# GridSeed.net
KiCad netlist of a schematic drawn in Altium Designer
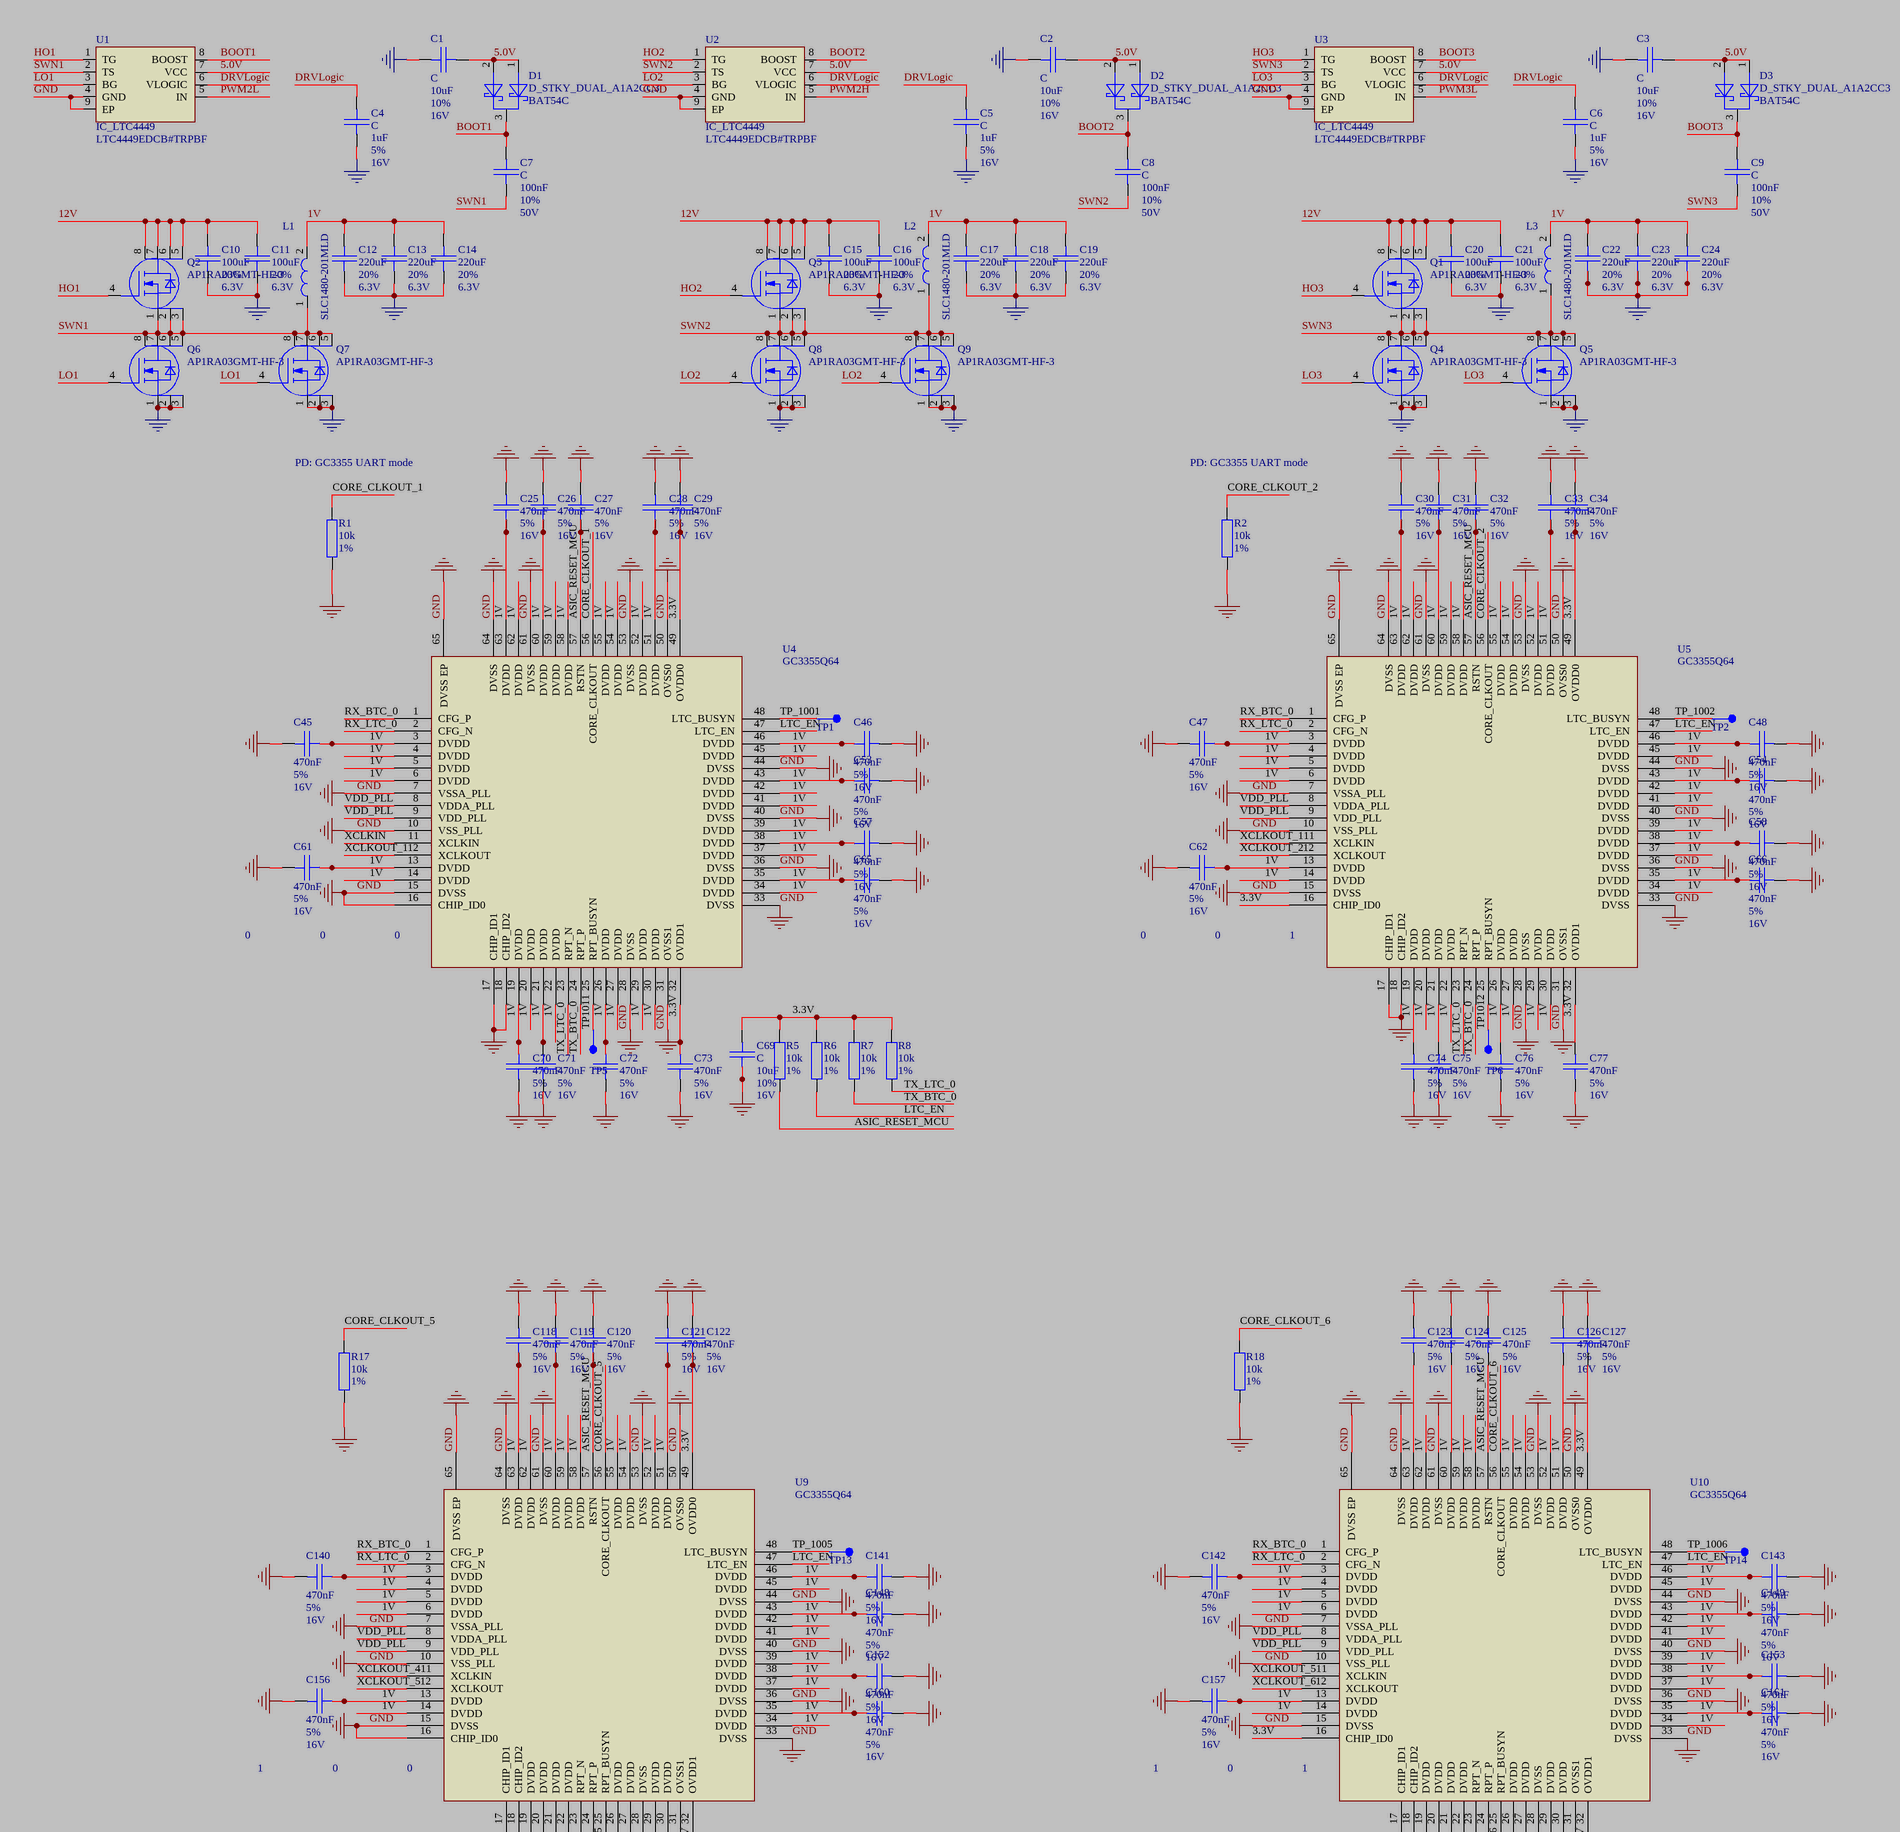
[diagram p0: GridSeed.SchDoc, top left]
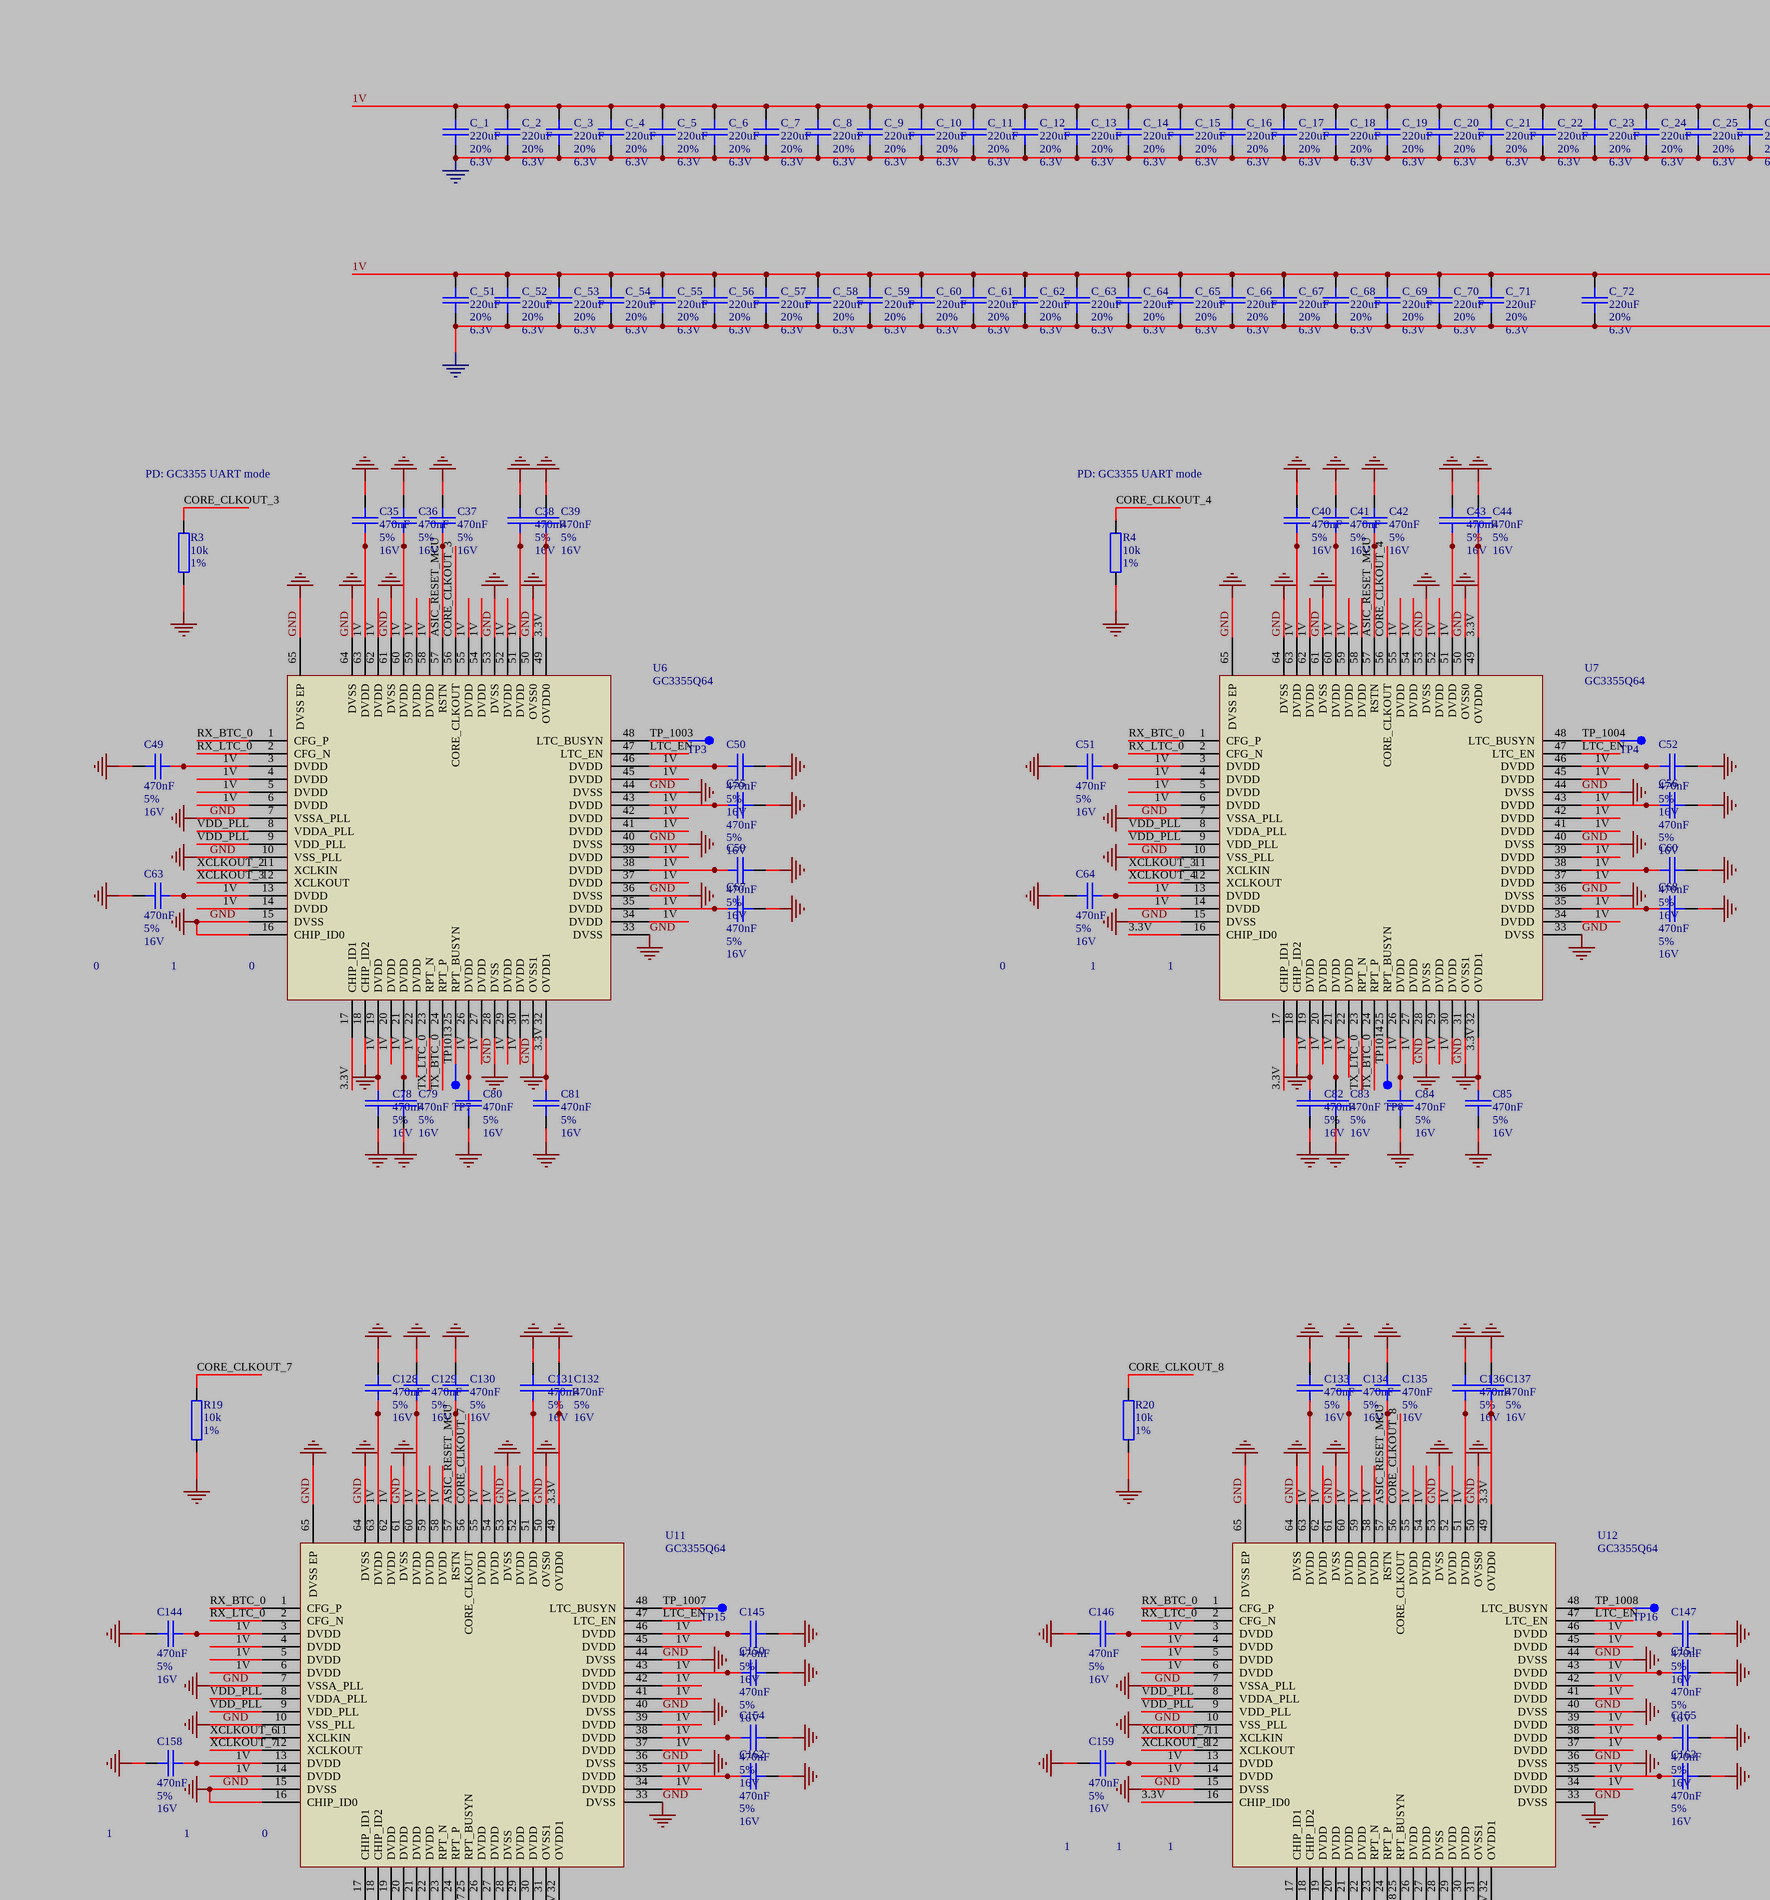
[diagram p1: GridSeed.SchDoc, top middle]
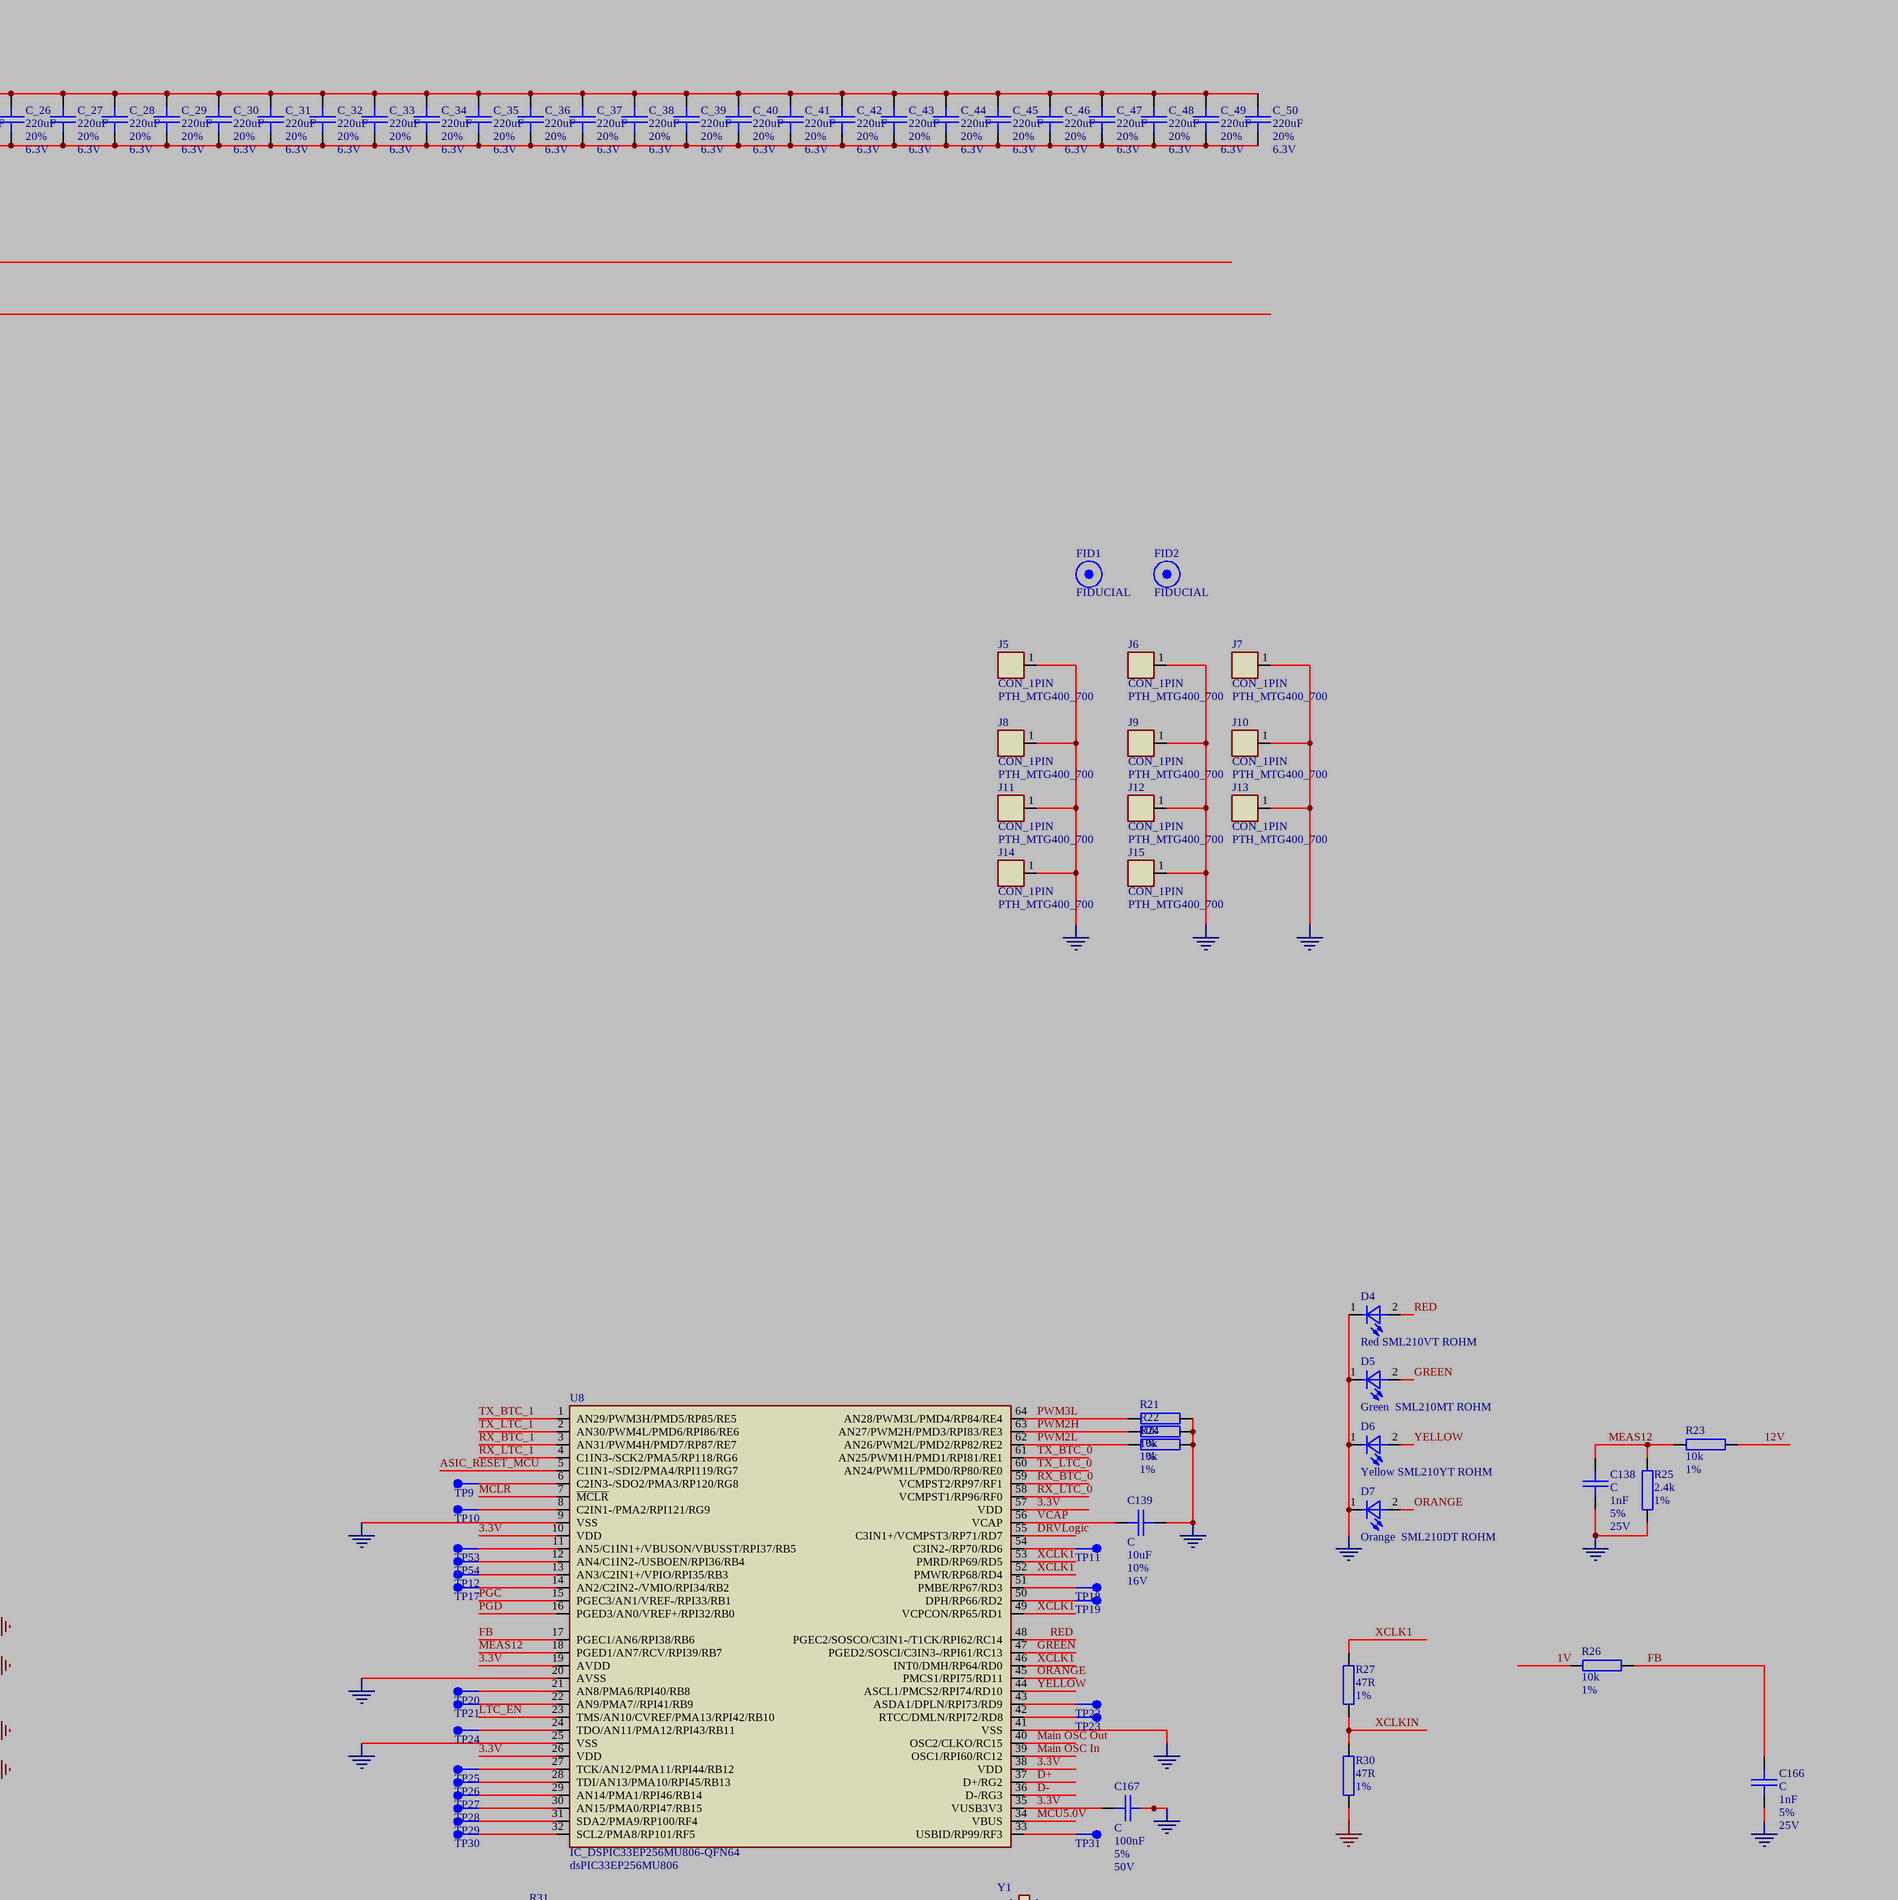
[diagram p2: GridSeed.SchDoc, top right]
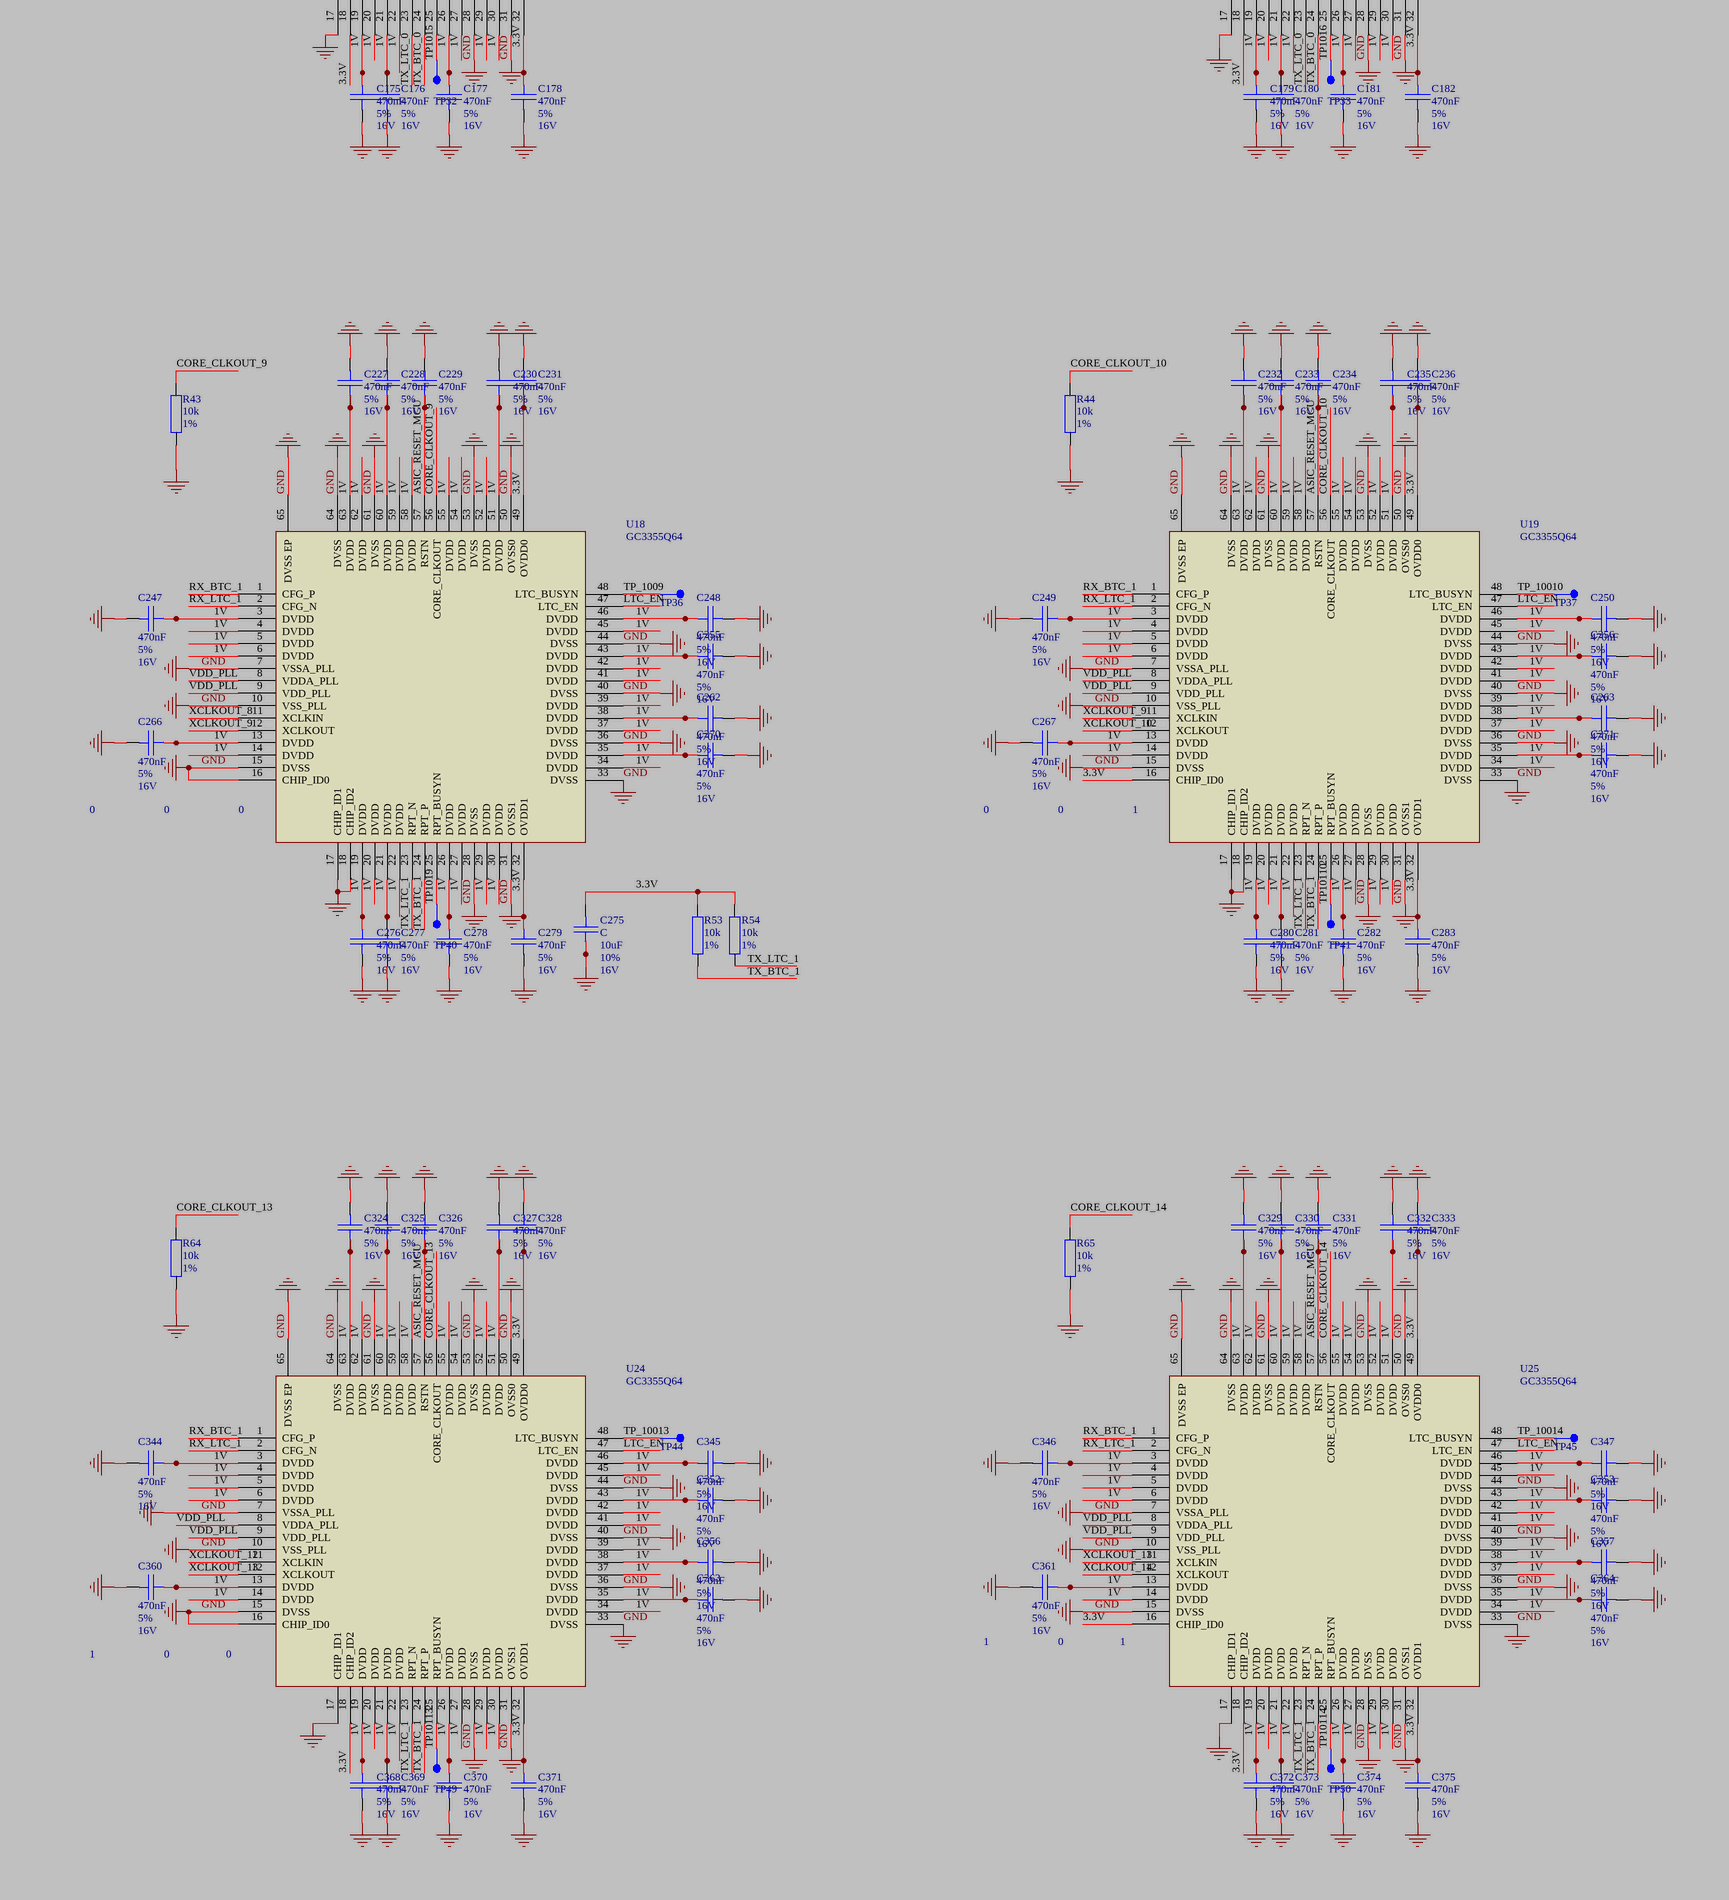
[diagram p3: GridSeed.SchDoc, bottom left]
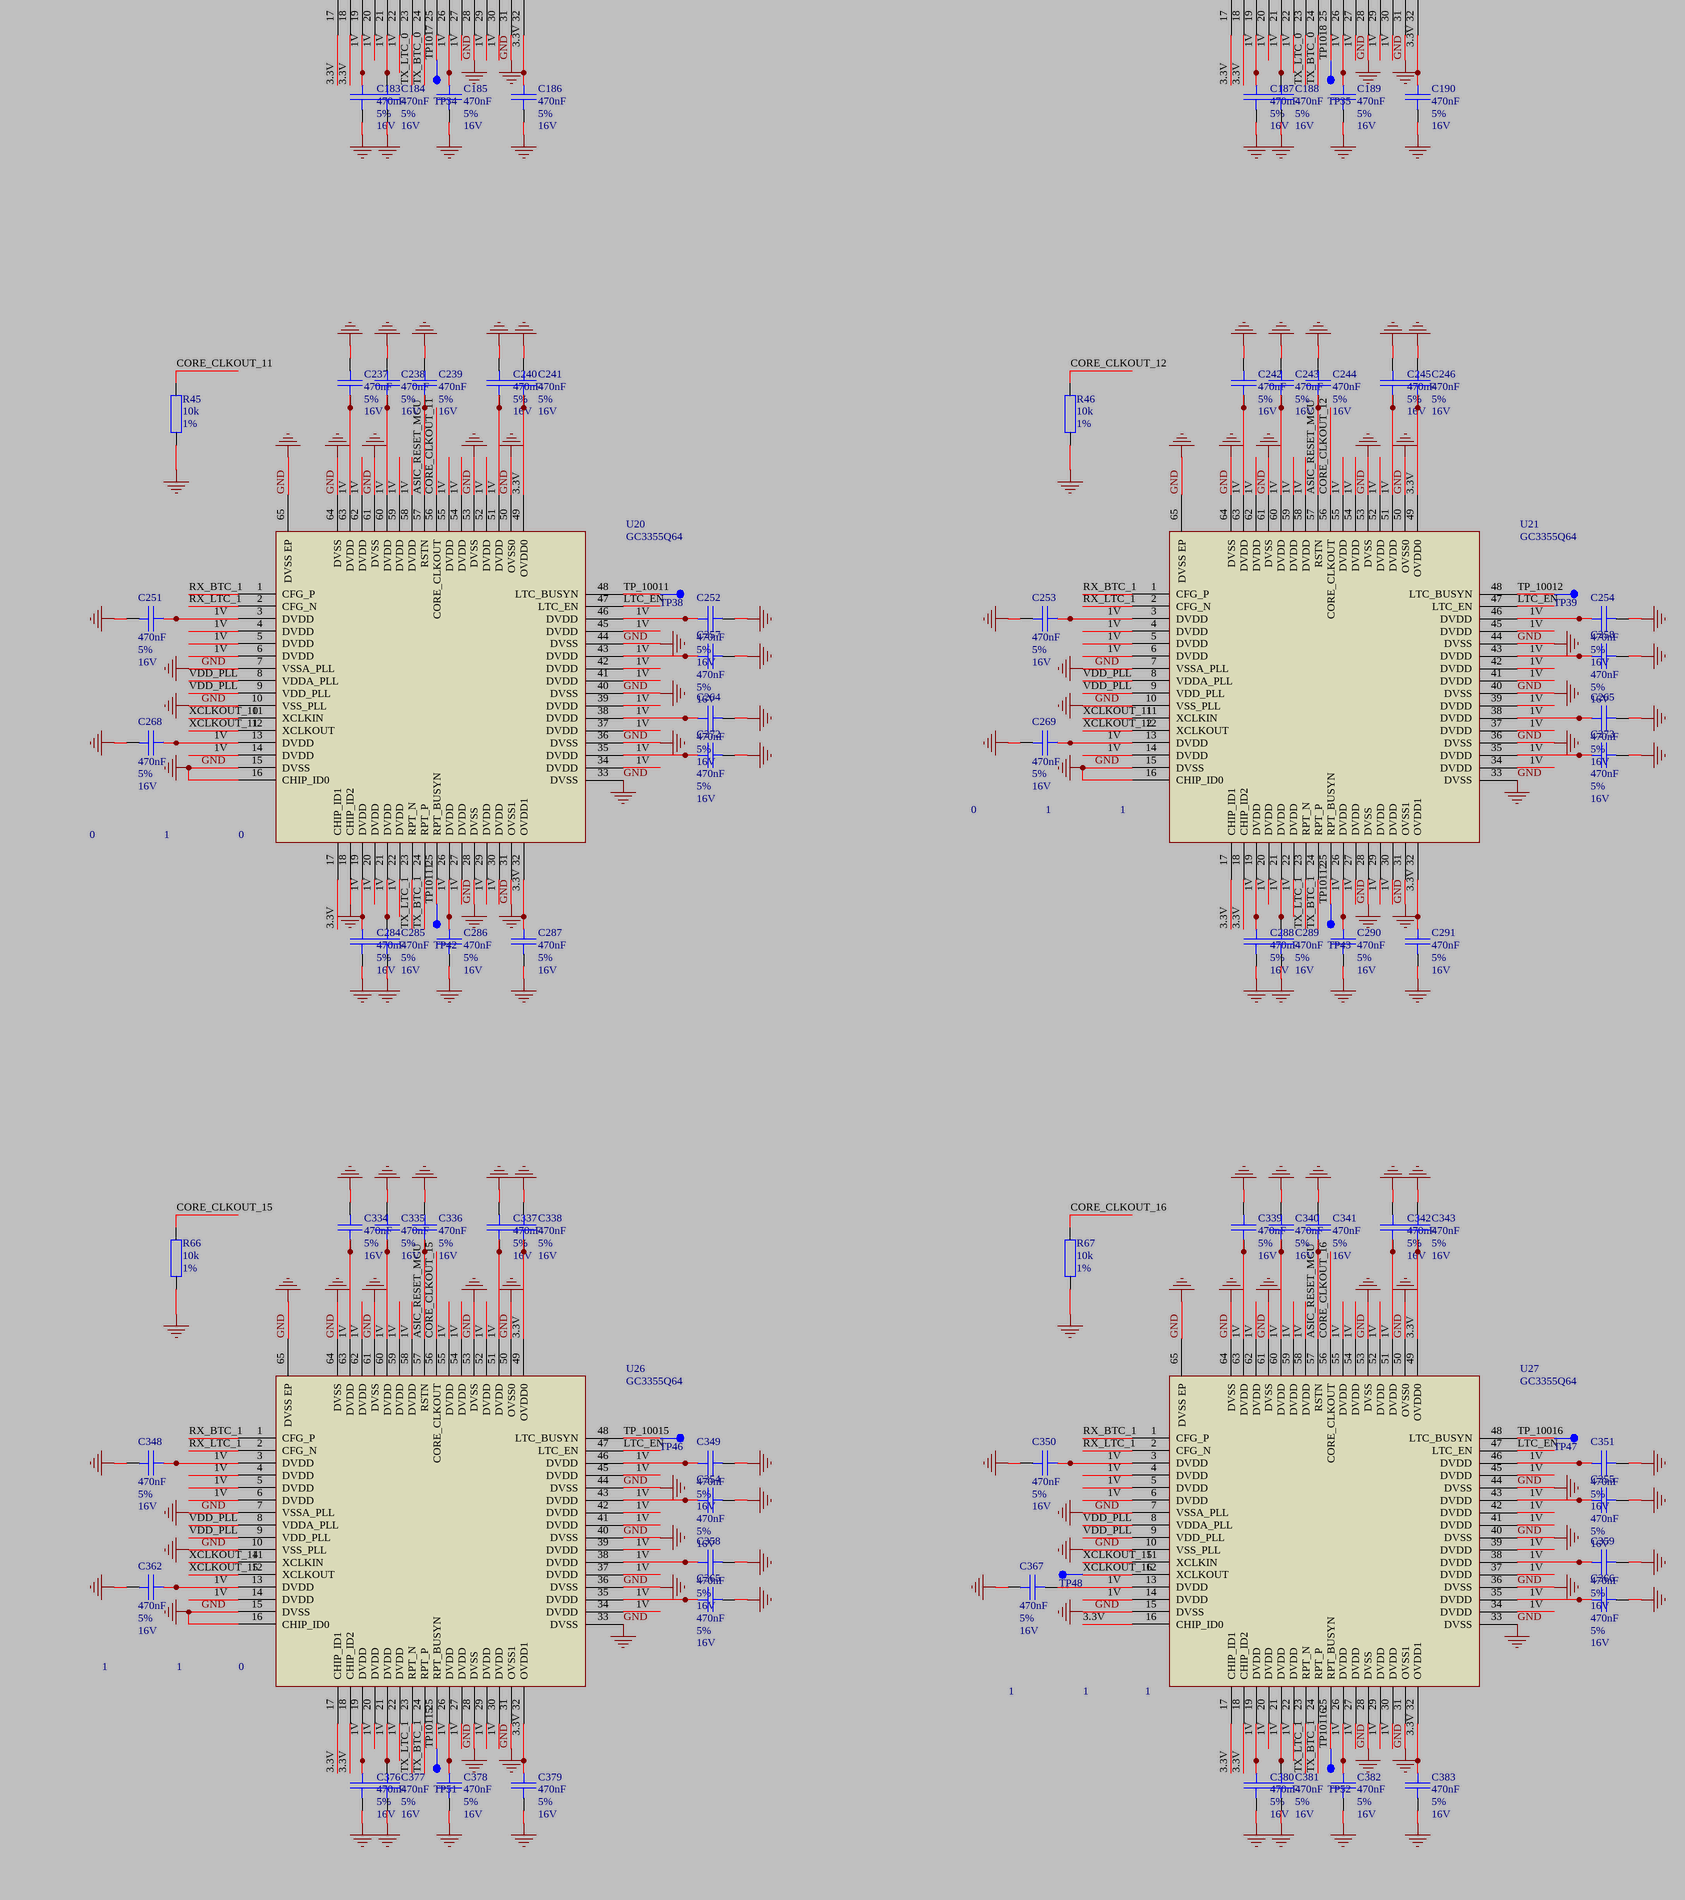
[diagram p4: GridSeed.SchDoc, bottom middle]
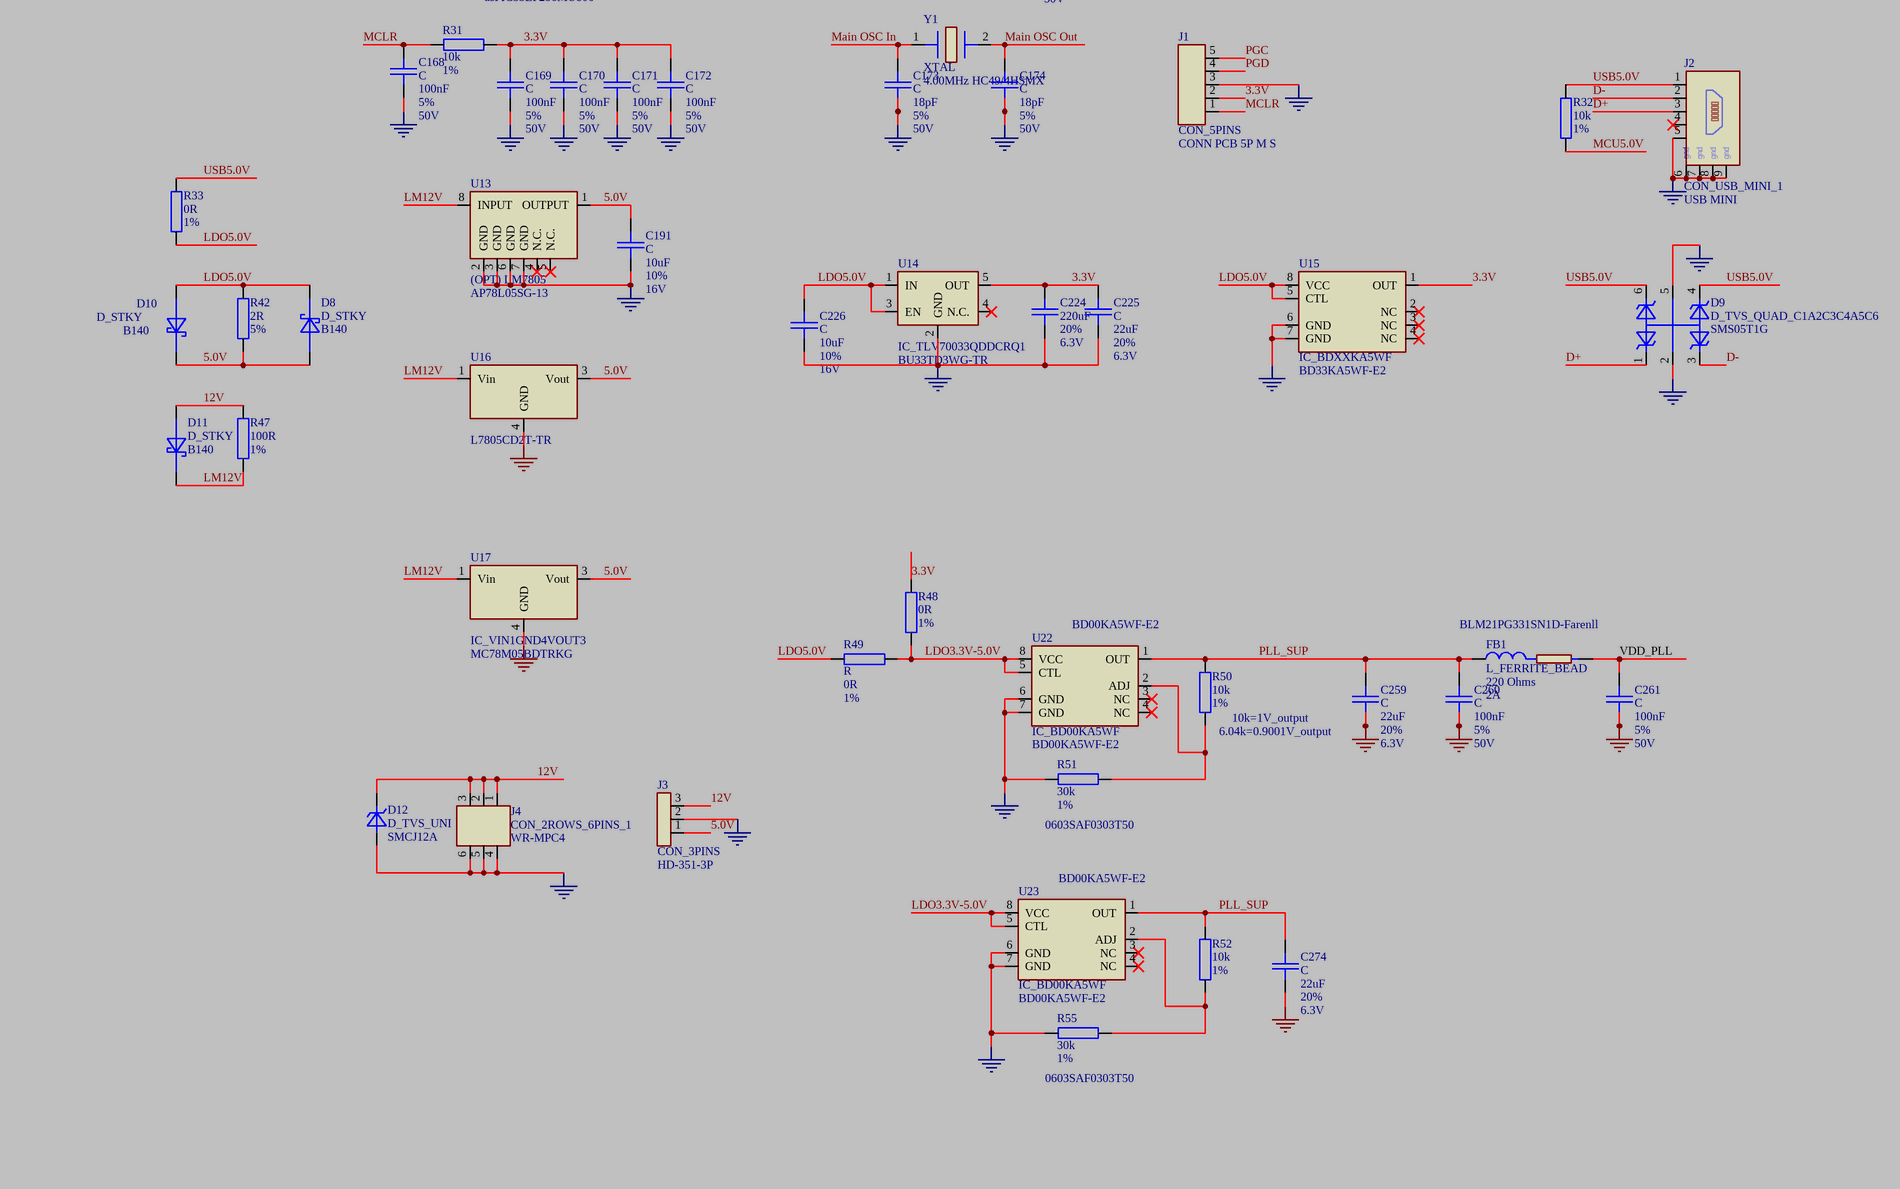
[diagram p5: GridSeed.SchDoc, bottom right]

(export (version "E")
  (design (tool "Eeschema 10.0.6"))
  (components
    (comp (ref "C1")
      (value "C")
      (footprint "SMD_0805_CAPC2012X145N")
      (fields
        (field (name "DB_PART_NUMBER") "CAP000043636")
        (field (name "DB_VALUE") "10uF")
        (field (name "DB_TOLERANCE") "10%")
        (field (name "DB_VOLTAGE") "16V")
        (field (name "DB_MANUFACTURER_PART") "KEMET    C0805C106K4PAC")
        (field (name "DB_APPROVED_BY") "ISHIDDEN=T")
      )
      (libsource (lib "Database_Libs1") (part "C"))
    )
    (comp (ref "C2")
      (value "C")
      (footprint "SMD_0805_CAPC2012X145N")
      (fields
        (field (name "DB_PART_NUMBER") "CAP000043636")
        (field (name "DB_VALUE") "10uF")
        (field (name "DB_TOLERANCE") "10%")
        (field (name "DB_VOLTAGE") "16V")
        (field (name "DB_MANUFACTURER_PART") "KEMET    C0805C106K4PAC")
        (field (name "DB_APPROVED_BY") "ISHIDDEN=T")
      )
      (libsource (lib "Database_Libs1") (part "C"))
    )
    (comp (ref "C3")
      (value "C")
      (footprint "SMD_0805_CAPC2012X145N")
      (fields
        (field (name "DB_PART_NUMBER") "CAP000043636")
        (field (name "DB_VALUE") "10uF")
        (field (name "DB_TOLERANCE") "10%")
        (field (name "DB_VOLTAGE") "16V")
        (field (name "DB_MANUFACTURER_PART") "KEMET    C0805C106K4PAC")
        (field (name "DB_APPROVED_BY") "ISHIDDEN=T")
      )
      (libsource (lib "Database_Libs1") (part "C"))
    )
    (comp (ref "C4")
      (value "C")
      (footprint "SMD_0805_CAPC2012X145N")
      (fields
        (field (name "DB_PART_NUMBER") "CAP000028589")
        (field (name "DB_VALUE") "1uF")
        (field (name "DB_TOLERANCE") "5%")
        (field (name "DB_VOLTAGE") "16V")
        (field (name "DB_MANUFACTURER_PART") "KEMET    C0805C105J4RAC")
        (field (name "DB_APPROVED_BY") "ISHIDDEN=T")
      )
      (libsource (lib "Database_Libs1") (part "C"))
    )
    (comp (ref "C5")
      (value "C")
      (footprint "SMD_0805_CAPC2012X145N")
      (fields
        (field (name "DB_PART_NUMBER") "CAP000028589")
        (field (name "DB_VALUE") "1uF")
        (field (name "DB_TOLERANCE") "5%")
        (field (name "DB_VOLTAGE") "16V")
        (field (name "DB_MANUFACTURER_PART") "KEMET    C0805C105J4RAC")
        (field (name "DB_APPROVED_BY") "ISHIDDEN=T")
      )
      (libsource (lib "Database_Libs1") (part "C"))
    )
    (comp (ref "C6")
      (value "C")
      (footprint "SMD_0805_CAPC2012X145N")
      (fields
        (field (name "DB_PART_NUMBER") "CAP000028589")
        (field (name "DB_VALUE") "1uF")
        (field (name "DB_TOLERANCE") "5%")
        (field (name "DB_VOLTAGE") "16V")
        (field (name "DB_MANUFACTURER_PART") "KEMET    C0805C105J4RAC")
        (field (name "DB_APPROVED_BY") "ISHIDDEN=T")
      )
      (libsource (lib "Database_Libs1") (part "C"))
    )
    (comp (ref "C7")
      (value "C")
      (footprint "SMD_0805_CAPC2012X145N")
      (fields
        (field (name "DB_PART_NUMBER") "CAP000027193")
        (field (name "DB_VALUE") "100nF")
        (field (name "DB_TOLERANCE") "10%")
        (field (name "DB_VOLTAGE") "50V")
        (field (name "DB_MANUFACTURER_PART") "KEMET    C0805C104K5RAC")
        (field (name "DB_APPROVED_BY") "ISHIDDEN=T")
      )
      (libsource (lib "Database_Libs1") (part "C"))
    )
    (comp (ref "C8")
      (value "C")
      (footprint "SMD_0805_CAPC2012X145N")
      (fields
        (field (name "DB_PART_NUMBER") "CAP000027193")
        (field (name "DB_VALUE") "100nF")
        (field (name "DB_TOLERANCE") "10%")
        (field (name "DB_VOLTAGE") "50V")
        (field (name "DB_MANUFACTURER_PART") "KEMET    C0805C104K5RAC")
        (field (name "DB_APPROVED_BY") "ISHIDDEN=T")
      )
      (libsource (lib "Database_Libs1") (part "C"))
    )
    (comp (ref "C9")
      (value "C")
      (footprint "SMD_0805_CAPC2012X145N")
      (fields
        (field (name "DB_PART_NUMBER") "CAP000027193")
        (field (name "DB_VALUE") "100nF")
        (field (name "DB_TOLERANCE") "10%")
        (field (name "DB_VOLTAGE") "50V")
        (field (name "DB_MANUFACTURER_PART") "KEMET    C0805C104K5RAC")
        (field (name "DB_APPROVED_BY") "ISHIDDEN=T")
      )
      (libsource (lib "Database_Libs1") (part "C"))
    )
    (comp (ref "C10")
      (value "C")
      (footprint "SMD_1210_CAPC3225X270N")
      (fields
        (field (name "DB_PART_NUMBER") "CAP000043701")
        (field (name "DB_VALUE") "100uF")
        (field (name "DB_TOLERANCE") "20%")
        (field (name "DB_VOLTAGE") "6.3V")
        (field (name "DB_MANUFACTURER_PART") "KEMET    C1210C107M9PAC")
        (field (name "DB_APPROVED_BY") "ISHIDDEN=T")
      )
      (libsource (lib "Database_Libs1") (part "C"))
    )
    (comp (ref "C11")
      (value "C")
      (footprint "SMD_1210_CAPC3225X270N")
      (fields
        (field (name "DB_PART_NUMBER") "CAP000043701")
        (field (name "DB_VALUE") "100uF")
        (field (name "DB_TOLERANCE") "20%")
        (field (name "DB_VOLTAGE") "6.3V")
        (field (name "DB_MANUFACTURER_PART") "KEMET    C1210C107M9PAC")
        (field (name "DB_APPROVED_BY") "ISHIDDEN=T")
      )
      (libsource (lib "Database_Libs1") (part "C"))
    )
    (comp (ref "C12")
      (value "C")
      (footprint "SMD_1210_CAPC3225X279N")
      (fields
        (field (name "DB_PART_NUMBER") "CAP000047355")
        (field (name "DB_VALUE") "220uF")
        (field (name "DB_TOLERANCE") "20%")
        (field (name "DB_VOLTAGE") "6.3V")
        (field (name "DB_MANUFACTURER_PART") "SAMSUNG    CL32A227MQVNNNE")
        (field (name "DB_APPROVED_BY") "VSN")
      )
      (libsource (lib "Database_Libs1") (part "C"))
    )
    (comp (ref "C13")
      (value "C")
      (footprint "SMD_1210_CAPC3225X279N")
      (fields
        (field (name "DB_PART_NUMBER") "CAP000047355")
        (field (name "DB_VALUE") "220uF")
        (field (name "DB_TOLERANCE") "20%")
        (field (name "DB_VOLTAGE") "6.3V")
        (field (name "DB_MANUFACTURER_PART") "SAMSUNG    CL32A227MQVNNNE")
        (field (name "DB_APPROVED_BY") "VSN")
      )
      (libsource (lib "Database_Libs1") (part "C"))
    )
    (comp (ref "C14")
      (value "C")
      (footprint "SMD_1210_CAPC3225X279N")
      (fields
        (field (name "DB_PART_NUMBER") "CAP000047355")
        (field (name "DB_VALUE") "220uF")
        (field (name "DB_TOLERANCE") "20%")
        (field (name "DB_VOLTAGE") "6.3V")
        (field (name "DB_MANUFACTURER_PART") "SAMSUNG    CL32A227MQVNNNE")
        (field (name "DB_APPROVED_BY") "VSN")
      )
      (libsource (lib "Database_Libs1") (part "C"))
    )
    (comp (ref "C15")
      (value "C")
      (footprint "SMD_1210_CAPC3225X270N")
      (fields
        (field (name "DB_PART_NUMBER") "CAP000043701")
        (field (name "DB_VALUE") "100uF")
        (field (name "DB_TOLERANCE") "20%")
        (field (name "DB_VOLTAGE") "6.3V")
        (field (name "DB_MANUFACTURER_PART") "KEMET    C1210C107M9PAC")
        (field (name "DB_APPROVED_BY") "ISHIDDEN=T")
      )
      (libsource (lib "Database_Libs1") (part "C"))
    )
    (comp (ref "C16")
      (value "C")
      (footprint "SMD_1210_CAPC3225X270N")
      (fields
        (field (name "DB_PART_NUMBER") "CAP000043701")
        (field (name "DB_VALUE") "100uF")
        (field (name "DB_TOLERANCE") "20%")
        (field (name "DB_VOLTAGE") "6.3V")
        (field (name "DB_MANUFACTURER_PART") "KEMET    C1210C107M9PAC")
        (field (name "DB_APPROVED_BY") "ISHIDDEN=T")
      )
      (libsource (lib "Database_Libs1") (part "C"))
    )
    (comp (ref "C17")
      (value "C")
      (footprint "SMD_1210_CAPC3225X279N")
      (fields
        (field (name "DB_PART_NUMBER") "CAP000047355")
        (field (name "DB_VALUE") "220uF")
        (field (name "DB_TOLERANCE") "20%")
        (field (name "DB_VOLTAGE") "6.3V")
        (field (name "DB_MANUFACTURER_PART") "SAMSUNG    CL32A227MQVNNNE")
        (field (name "DB_APPROVED_BY") "VSN")
      )
      (libsource (lib "Database_Libs1") (part "C"))
    )
    (comp (ref "C18")
      (value "C")
      (footprint "SMD_1210_CAPC3225X279N")
      (fields
        (field (name "DB_PART_NUMBER") "CAP000047355")
        (field (name "DB_VALUE") "220uF")
        (field (name "DB_TOLERANCE") "20%")
        (field (name "DB_VOLTAGE") "6.3V")
        (field (name "DB_MANUFACTURER_PART") "SAMSUNG    CL32A227MQVNNNE")
        (field (name "DB_APPROVED_BY") "VSN")
      )
      (libsource (lib "Database_Libs1") (part "C"))
    )
    (comp (ref "C19")
      (value "C")
      (footprint "SMD_1210_CAPC3225X279N")
      (fields
        (field (name "DB_PART_NUMBER") "CAP000047355")
        (field (name "DB_VALUE") "220uF")
        (field (name "DB_TOLERANCE") "20%")
        (field (name "DB_VOLTAGE") "6.3V")
        (field (name "DB_MANUFACTURER_PART") "SAMSUNG    CL32A227MQVNNNE")
        (field (name "DB_APPROVED_BY") "VSN")
      )
      (libsource (lib "Database_Libs1") (part "C"))
    )
    (comp (ref "C20")
      (value "C")
      (footprint "SMD_1210_CAPC3225X270N")
      (fields
        (field (name "DB_PART_NUMBER") "CAP000043701")
        (field (name "DB_VALUE") "100uF")
        (field (name "DB_TOLERANCE") "20%")
        (field (name "DB_VOLTAGE") "6.3V")
        (field (name "DB_MANUFACTURER_PART") "KEMET    C1210C107M9PAC")
        (field (name "DB_APPROVED_BY") "ISHIDDEN=T")
      )
      (libsource (lib "Database_Libs1") (part "C"))
    )
    (comp (ref "C21")
      (value "C")
      (footprint "SMD_1210_CAPC3225X270N")
      (fields
        (field (name "DB_PART_NUMBER") "CAP000043701")
        (field (name "DB_VALUE") "100uF")
        (field (name "DB_TOLERANCE") "20%")
        (field (name "DB_VOLTAGE") "6.3V")
        (field (name "DB_MANUFACTURER_PART") "KEMET    C1210C107M9PAC")
        (field (name "DB_APPROVED_BY") "ISHIDDEN=T")
      )
      (libsource (lib "Database_Libs1") (part "C"))
    )
    (comp (ref "C22")
      (value "C")
      (footprint "SMD_1210_CAPC3225X279N")
      (fields
        (field (name "DB_PART_NUMBER") "CAP000047355")
        (field (name "DB_VALUE") "220uF")
        (field (name "DB_TOLERANCE") "20%")
        (field (name "DB_VOLTAGE") "6.3V")
        (field (name "DB_MANUFACTURER_PART") "SAMSUNG    CL32A227MQVNNNE")
        (field (name "DB_APPROVED_BY") "VSN")
      )
      (libsource (lib "Database_Libs1") (part "C"))
    )
    (comp (ref "C23")
      (value "C")
      (footprint "SMD_1210_CAPC3225X279N")
      (fields
        (field (name "DB_PART_NUMBER") "CAP000047355")
        (field (name "DB_VALUE") "220uF")
        (field (name "DB_TOLERANCE") "20%")
        (field (name "DB_VOLTAGE") "6.3V")
        (field (name "DB_MANUFACTURER_PART") "SAMSUNG    CL32A227MQVNNNE")
        (field (name "DB_APPROVED_BY") "VSN")
      )
      (libsource (lib "Database_Libs1") (part "C"))
    )
    (comp (ref "C24")
      (value "C")
      (footprint "SMD_1210_CAPC3225X279N")
      (fields
        (field (name "DB_PART_NUMBER") "CAP000047355")
        (field (name "DB_VALUE") "220uF")
        (field (name "DB_TOLERANCE") "20%")
        (field (name "DB_VOLTAGE") "6.3V")
        (field (name "DB_MANUFACTURER_PART") "SAMSUNG    CL32A227MQVNNNE")
        (field (name "DB_APPROVED_BY") "VSN")
      )
      (libsource (lib "Database_Libs1") (part "C"))
    )
    (comp (ref "C25")
      (value "C")
      (footprint "SMD_0603_CAPC1608X95N")
      (fields
        (field (name "DB_PART_NUMBER") "CAP000028169")
        (field (name "DB_VALUE") "470nF")
        (field (name "DB_TOLERANCE") "5%")
        (field (name "DB_VOLTAGE") "16V")
        (field (name "DB_MANUFACTURER_PART") "KEMET    C0603C474J4RAC")
        (field (name "DB_APPROVED_BY") "ISHIDDEN=T")
      )
      (libsource (lib "Database_Libs1") (part "C"))
    )
    (comp (ref "C26")
      (value "C")
      (footprint "SMD_0603_CAPC1608X95N")
      (fields
        (field (name "DB_PART_NUMBER") "CAP000028169")
        (field (name "DB_VALUE") "470nF")
        (field (name "DB_TOLERANCE") "5%")
        (field (name "DB_VOLTAGE") "16V")
        (field (name "DB_MANUFACTURER_PART") "KEMET    C0603C474J4RAC")
        (field (name "DB_APPROVED_BY") "ISHIDDEN=T")
      )
      (libsource (lib "Database_Libs1") (part "C"))
    )
    (comp (ref "C27")
      (value "C")
      (footprint "SMD_0603_CAPC1608X95N")
      (fields
        (field (name "DB_PART_NUMBER") "CAP000028169")
        (field (name "DB_VALUE") "470nF")
        (field (name "DB_TOLERANCE") "5%")
        (field (name "DB_VOLTAGE") "16V")
        (field (name "DB_MANUFACTURER_PART") "KEMET    C0603C474J4RAC")
        (field (name "DB_APPROVED_BY") "ISHIDDEN=T")
      )
      (libsource (lib "Database_Libs1") (part "C"))
    )
    (comp (ref "C28")
      (value "C")
      (footprint "SMD_0603_CAPC1608X95N")
      (fields
        (field (name "DB_PART_NUMBER") "CAP000028169")
        (field (name "DB_VALUE") "470nF")
        (field (name "DB_TOLERANCE") "5%")
        (field (name "DB_VOLTAGE") "16V")
        (field (name "DB_MANUFACTURER_PART") "KEMET    C0603C474J4RAC")
        (field (name "DB_APPROVED_BY") "ISHIDDEN=T")
      )
      (libsource (lib "Database_Libs1") (part "C"))
    )
    (comp (ref "C29")
      (value "C")
      (footprint "SMD_0603_CAPC1608X95N")
      (fields
        (field (name "DB_PART_NUMBER") "CAP000028169")
        (field (name "DB_VALUE") "470nF")
        (field (name "DB_TOLERANCE") "5%")
        (field (name "DB_VOLTAGE") "16V")
        (field (name "DB_MANUFACTURER_PART") "KEMET    C0603C474J4RAC")
        (field (name "DB_APPROVED_BY") "ISHIDDEN=T")
      )
      (libsource (lib "Database_Libs1") (part "C"))
    )
    (comp (ref "C30")
      (value "C")
      (footprint "SMD_0603_CAPC1608X95N")
      (fields
        (field (name "DB_PART_NUMBER") "CAP000028169")
        (field (name "DB_VALUE") "470nF")
        (field (name "DB_TOLERANCE") "5%")
        (field (name "DB_VOLTAGE") "16V")
        (field (name "DB_MANUFACTURER_PART") "KEMET    C0603C474J4RAC")
        (field (name "DB_APPROVED_BY") "ISHIDDEN=T")
      )
      (libsource (lib "Database_Libs1") (part "C"))
    )
    (comp (ref "C31")
      (value "C")
      (footprint "SMD_0603_CAPC1608X95N")
      (fields
        (field (name "DB_PART_NUMBER") "CAP000028169")
        (field (name "DB_VALUE") "470nF")
        (field (name "DB_TOLERANCE") "5%")
        (field (name "DB_VOLTAGE") "16V")
        (field (name "DB_MANUFACTURER_PART") "KEMET    C0603C474J4RAC")
        (field (name "DB_APPROVED_BY") "ISHIDDEN=T")
      )
      (libsource (lib "Database_Libs1") (part "C"))
    )
    (comp (ref "C32")
      (value "C")
      (footprint "SMD_0603_CAPC1608X95N")
      (fields
        (field (name "DB_PART_NUMBER") "CAP000028169")
        (field (name "DB_VALUE") "470nF")
        (field (name "DB_TOLERANCE") "5%")
        (field (name "DB_VOLTAGE") "16V")
        (field (name "DB_MANUFACTURER_PART") "KEMET    C0603C474J4RAC")
        (field (name "DB_APPROVED_BY") "ISHIDDEN=T")
      )
      (libsource (lib "Database_Libs1") (part "C"))
    )
    (comp (ref "C33")
      (value "C")
      (footprint "SMD_0603_CAPC1608X95N")
      (fields
        (field (name "DB_PART_NUMBER") "CAP000028169")
        (field (name "DB_VALUE") "470nF")
        (field (name "DB_TOLERANCE") "5%")
        (field (name "DB_VOLTAGE") "16V")
        (field (name "DB_MANUFACTURER_PART") "KEMET    C0603C474J4RAC")
        (field (name "DB_APPROVED_BY") "ISHIDDEN=T")
      )
      (libsource (lib "Database_Libs1") (part "C"))
    )
    (comp (ref "C34")
      (value "C")
      (footprint "SMD_0603_CAPC1608X95N")
      (fields
        (field (name "DB_PART_NUMBER") "CAP000028169")
        (field (name "DB_VALUE") "470nF")
        (field (name "DB_TOLERANCE") "5%")
        (field (name "DB_VOLTAGE") "16V")
        (field (name "DB_MANUFACTURER_PART") "KEMET    C0603C474J4RAC")
        (field (name "DB_APPROVED_BY") "ISHIDDEN=T")
      )
      (libsource (lib "Database_Libs1") (part "C"))
    )
    (comp (ref "C35")
      (value "C")
      (footprint "SMD_0603_CAPC1608X95N")
      (fields
        (field (name "DB_PART_NUMBER") "CAP000028169")
        (field (name "DB_VALUE") "470nF")
        (field (name "DB_TOLERANCE") "5%")
        (field (name "DB_VOLTAGE") "16V")
        (field (name "DB_MANUFACTURER_PART") "KEMET    C0603C474J4RAC")
        (field (name "DB_APPROVED_BY") "ISHIDDEN=T")
      )
      (libsource (lib "Database_Libs1") (part "C"))
    )
    (comp (ref "C36")
      (value "C")
      (footprint "SMD_0603_CAPC1608X95N")
      (fields
        (field (name "DB_PART_NUMBER") "CAP000028169")
        (field (name "DB_VALUE") "470nF")
        (field (name "DB_TOLERANCE") "5%")
        (field (name "DB_VOLTAGE") "16V")
        (field (name "DB_MANUFACTURER_PART") "KEMET    C0603C474J4RAC")
        (field (name "DB_APPROVED_BY") "ISHIDDEN=T")
      )
      (libsource (lib "Database_Libs1") (part "C"))
    )
    (comp (ref "C37")
      (value "C")
      (footprint "SMD_0603_CAPC1608X95N")
      (fields
        (field (name "DB_PART_NUMBER") "CAP000028169")
        (field (name "DB_VALUE") "470nF")
        (field (name "DB_TOLERANCE") "5%")
        (field (name "DB_VOLTAGE") "16V")
        (field (name "DB_MANUFACTURER_PART") "KEMET    C0603C474J4RAC")
        (field (name "DB_APPROVED_BY") "ISHIDDEN=T")
      )
      (libsource (lib "Database_Libs1") (part "C"))
    )
    (comp (ref "C38")
      (value "C")
      (footprint "SMD_0603_CAPC1608X95N")
      (fields
        (field (name "DB_PART_NUMBER") "CAP000028169")
        (field (name "DB_VALUE") "470nF")
        (field (name "DB_TOLERANCE") "5%")
        (field (name "DB_VOLTAGE") "16V")
        (field (name "DB_MANUFACTURER_PART") "KEMET    C0603C474J4RAC")
        (field (name "DB_APPROVED_BY") "ISHIDDEN=T")
      )
      (libsource (lib "Database_Libs1") (part "C"))
    )
    (comp (ref "C39")
      (value "C")
      (footprint "SMD_0603_CAPC1608X95N")
      (fields
        (field (name "DB_PART_NUMBER") "CAP000028169")
        (field (name "DB_VALUE") "470nF")
        (field (name "DB_TOLERANCE") "5%")
        (field (name "DB_VOLTAGE") "16V")
        (field (name "DB_MANUFACTURER_PART") "KEMET    C0603C474J4RAC")
        (field (name "DB_APPROVED_BY") "ISHIDDEN=T")
      )
      (libsource (lib "Database_Libs1") (part "C"))
    )
    (comp (ref "C40")
      (value "C")
      (footprint "SMD_0603_CAPC1608X95N")
      (fields
        (field (name "DB_PART_NUMBER") "CAP000028169")
        (field (name "DB_VALUE") "470nF")
        (field (name "DB_TOLERANCE") "5%")
        (field (name "DB_VOLTAGE") "16V")
        (field (name "DB_MANUFACTURER_PART") "KEMET    C0603C474J4RAC")
        (field (name "DB_APPROVED_BY") "ISHIDDEN=T")
      )
      (libsource (lib "Database_Libs1") (part "C"))
    )
    (comp (ref "C41")
      (value "C")
      (footprint "SMD_0603_CAPC1608X95N")
      (fields
        (field (name "DB_PART_NUMBER") "CAP000028169")
        (field (name "DB_VALUE") "470nF")
        (field (name "DB_TOLERANCE") "5%")
        (field (name "DB_VOLTAGE") "16V")
        (field (name "DB_MANUFACTURER_PART") "KEMET    C0603C474J4RAC")
        (field (name "DB_APPROVED_BY") "ISHIDDEN=T")
      )
      (libsource (lib "Database_Libs1") (part "C"))
    )
    (comp (ref "C42")
      (value "C")
      (footprint "SMD_0603_CAPC1608X95N")
      (fields
        (field (name "DB_PART_NUMBER") "CAP000028169")
        (field (name "DB_VALUE") "470nF")
        (field (name "DB_TOLERANCE") "5%")
        (field (name "DB_VOLTAGE") "16V")
        (field (name "DB_MANUFACTURER_PART") "KEMET    C0603C474J4RAC")
        (field (name "DB_APPROVED_BY") "ISHIDDEN=T")
      )
      (libsource (lib "Database_Libs1") (part "C"))
    )
    (comp (ref "C43")
      (value "C")
      (footprint "SMD_0603_CAPC1608X95N")
      (fields
        (field (name "DB_PART_NUMBER") "CAP000028169")
        (field (name "DB_VALUE") "470nF")
        (field (name "DB_TOLERANCE") "5%")
        (field (name "DB_VOLTAGE") "16V")
        (field (name "DB_MANUFACTURER_PART") "KEMET    C0603C474J4RAC")
        (field (name "DB_APPROVED_BY") "ISHIDDEN=T")
      )
      (libsource (lib "Database_Libs1") (part "C"))
    )
    (comp (ref "C44")
      (value "C")
      (footprint "SMD_0603_CAPC1608X95N")
      (fields
        (field (name "DB_PART_NUMBER") "CAP000028169")
        (field (name "DB_VALUE") "470nF")
        (field (name "DB_TOLERANCE") "5%")
        (field (name "DB_VOLTAGE") "16V")
        (field (name "DB_MANUFACTURER_PART") "KEMET    C0603C474J4RAC")
        (field (name "DB_APPROVED_BY") "ISHIDDEN=T")
      )
      (libsource (lib "Database_Libs1") (part "C"))
    )
    (comp (ref "C45")
      (value "C")
      (footprint "SMD_0603_CAPC1608X95N")
      (fields
        (field (name "DB_PART_NUMBER") "CAP000028169")
        (field (name "DB_VALUE") "470nF")
        (field (name "DB_TOLERANCE") "5%")
        (field (name "DB_VOLTAGE") "16V")
        (field (name "DB_MANUFACTURER_PART") "KEMET    C0603C474J4RAC")
        (field (name "DB_APPROVED_BY") "ISHIDDEN=T")
      )
      (libsource (lib "Database_Libs1") (part "C"))
    )
    (comp (ref "C46")
      (value "C")
      (footprint "SMD_0603_CAPC1608X95N")
      (fields
        (field (name "DB_PART_NUMBER") "CAP000028169")
        (field (name "DB_VALUE") "470nF")
        (field (name "DB_TOLERANCE") "5%")
        (field (name "DB_VOLTAGE") "16V")
        (field (name "DB_MANUFACTURER_PART") "KEMET    C0603C474J4RAC")
        (field (name "DB_APPROVED_BY") "ISHIDDEN=T")
      )
      (libsource (lib "Database_Libs1") (part "C"))
    )
    (comp (ref "C47")
      (value "C")
      (footprint "SMD_0603_CAPC1608X95N")
      (fields
        (field (name "DB_PART_NUMBER") "CAP000028169")
        (field (name "DB_VALUE") "470nF")
        (field (name "DB_TOLERANCE") "5%")
        (field (name "DB_VOLTAGE") "16V")
        (field (name "DB_MANUFACTURER_PART") "KEMET    C0603C474J4RAC")
        (field (name "DB_APPROVED_BY") "ISHIDDEN=T")
      )
      (libsource (lib "Database_Libs1") (part "C"))
    )
    (comp (ref "C48")
      (value "C")
      (footprint "SMD_0603_CAPC1608X95N")
      (fields
        (field (name "DB_PART_NUMBER") "CAP000028169")
        (field (name "DB_VALUE") "470nF")
        (field (name "DB_TOLERANCE") "5%")
        (field (name "DB_VOLTAGE") "16V")
        (field (name "DB_MANUFACTURER_PART") "KEMET    C0603C474J4RAC")
        (field (name "DB_APPROVED_BY") "ISHIDDEN=T")
      )
      (libsource (lib "Database_Libs1") (part "C"))
    )
    (comp (ref "C49")
      (value "C")
      (footprint "SMD_0603_CAPC1608X95N")
      (fields
        (field (name "DB_PART_NUMBER") "CAP000028169")
        (field (name "DB_VALUE") "470nF")
        (field (name "DB_TOLERANCE") "5%")
        (field (name "DB_VOLTAGE") "16V")
        (field (name "DB_MANUFACTURER_PART") "KEMET    C0603C474J4RAC")
        (field (name "DB_APPROVED_BY") "ISHIDDEN=T")
      )
      (libsource (lib "Database_Libs1") (part "C"))
    )
    (comp (ref "C50")
      (value "C")
      (footprint "SMD_0603_CAPC1608X95N")
      (fields
        (field (name "DB_PART_NUMBER") "CAP000028169")
        (field (name "DB_VALUE") "470nF")
        (field (name "DB_TOLERANCE") "5%")
        (field (name "DB_VOLTAGE") "16V")
        (field (name "DB_MANUFACTURER_PART") "KEMET    C0603C474J4RAC")
        (field (name "DB_APPROVED_BY") "ISHIDDEN=T")
      )
      (libsource (lib "Database_Libs1") (part "C"))
    )
    (comp (ref "C51")
      (value "C")
      (footprint "SMD_0603_CAPC1608X95N")
      (fields
        (field (name "DB_PART_NUMBER") "CAP000028169")
        (field (name "DB_VALUE") "470nF")
        (field (name "DB_TOLERANCE") "5%")
        (field (name "DB_VOLTAGE") "16V")
        (field (name "DB_MANUFACTURER_PART") "KEMET    C0603C474J4RAC")
        (field (name "DB_APPROVED_BY") "ISHIDDEN=T")
      )
      (libsource (lib "Database_Libs1") (part "C"))
    )
    (comp (ref "C52")
      (value "C")
      (footprint "SMD_0603_CAPC1608X95N")
      (fields
        (field (name "DB_PART_NUMBER") "CAP000028169")
        (field (name "DB_VALUE") "470nF")
        (field (name "DB_TOLERANCE") "5%")
        (field (name "DB_VOLTAGE") "16V")
        (field (name "DB_MANUFACTURER_PART") "KEMET    C0603C474J4RAC")
        (field (name "DB_APPROVED_BY") "ISHIDDEN=T")
      )
      (libsource (lib "Database_Libs1") (part "C"))
    )
    (comp (ref "C53")
      (value "C")
      (footprint "SMD_0603_CAPC1608X95N")
      (fields
        (field (name "DB_PART_NUMBER") "CAP000028169")
        (field (name "DB_VALUE") "470nF")
        (field (name "DB_TOLERANCE") "5%")
        (field (name "DB_VOLTAGE") "16V")
        (field (name "DB_MANUFACTURER_PART") "KEMET    C0603C474J4RAC")
        (field (name "DB_APPROVED_BY") "ISHIDDEN=T")
      )
      (libsource (lib "Database_Libs1") (part "C"))
    )
    (comp (ref "C54")
      (value "C")
      (footprint "SMD_0603_CAPC1608X95N")
      (fields
        (field (name "DB_PART_NUMBER") "CAP000028169")
        (field (name "DB_VALUE") "470nF")
        (field (name "DB_TOLERANCE") "5%")
        (field (name "DB_VOLTAGE") "16V")
        (field (name "DB_MANUFACTURER_PART") "KEMET    C0603C474J4RAC")
        (field (name "DB_APPROVED_BY") "ISHIDDEN=T")
      )
      (libsource (lib "Database_Libs1") (part "C"))
    )
    (comp (ref "C55")
      (value "C")
      (footprint "SMD_0603_CAPC1608X95N")
      (fields
        (field (name "DB_PART_NUMBER") "CAP000028169")
        (field (name "DB_VALUE") "470nF")
        (field (name "DB_TOLERANCE") "5%")
        (field (name "DB_VOLTAGE") "16V")
        (field (name "DB_MANUFACTURER_PART") "KEMET    C0603C474J4RAC")
        (field (name "DB_APPROVED_BY") "ISHIDDEN=T")
      )
      (libsource (lib "Database_Libs1") (part "C"))
    )
    (comp (ref "C56")
      (value "C")
      (footprint "SMD_0603_CAPC1608X95N")
      (fields
        (field (name "DB_PART_NUMBER") "CAP000028169")
        (field (name "DB_VALUE") "470nF")
        (field (name "DB_TOLERANCE") "5%")
        (field (name "DB_VOLTAGE") "16V")
        (field (name "DB_MANUFACTURER_PART") "KEMET    C0603C474J4RAC")
        (field (name "DB_APPROVED_BY") "ISHIDDEN=T")
      )
      (libsource (lib "Database_Libs1") (part "C"))
    )
    (comp (ref "C57")
      (value "C")
      (footprint "SMD_0603_CAPC1608X95N")
      (fields
        (field (name "DB_PART_NUMBER") "CAP000028169")
        (field (name "DB_VALUE") "470nF")
        (field (name "DB_TOLERANCE") "5%")
        (field (name "DB_VOLTAGE") "16V")
        (field (name "DB_MANUFACTURER_PART") "KEMET    C0603C474J4RAC")
        (field (name "DB_APPROVED_BY") "ISHIDDEN=T")
      )
      (libsource (lib "Database_Libs1") (part "C"))
    )
    (comp (ref "C58")
      (value "C")
      (footprint "SMD_0603_CAPC1608X95N")
      (fields
        (field (name "DB_PART_NUMBER") "CAP000028169")
        (field (name "DB_VALUE") "470nF")
        (field (name "DB_TOLERANCE") "5%")
        (field (name "DB_VOLTAGE") "16V")
        (field (name "DB_MANUFACTURER_PART") "KEMET    C0603C474J4RAC")
        (field (name "DB_APPROVED_BY") "ISHIDDEN=T")
      )
      (libsource (lib "Database_Libs1") (part "C"))
    )
    (comp (ref "C59")
      (value "C")
      (footprint "SMD_0603_CAPC1608X95N")
      (fields
        (field (name "DB_PART_NUMBER") "CAP000028169")
        (field (name "DB_VALUE") "470nF")
        (field (name "DB_TOLERANCE") "5%")
        (field (name "DB_VOLTAGE") "16V")
        (field (name "DB_MANUFACTURER_PART") "KEMET    C0603C474J4RAC")
        (field (name "DB_APPROVED_BY") "ISHIDDEN=T")
      )
      (libsource (lib "Database_Libs1") (part "C"))
    )
    (comp (ref "C60")
      (value "C")
      (footprint "SMD_0603_CAPC1608X95N")
      (fields
        (field (name "DB_PART_NUMBER") "CAP000028169")
        (field (name "DB_VALUE") "470nF")
        (field (name "DB_TOLERANCE") "5%")
        (field (name "DB_VOLTAGE") "16V")
        (field (name "DB_MANUFACTURER_PART") "KEMET    C0603C474J4RAC")
        (field (name "DB_APPROVED_BY") "ISHIDDEN=T")
      )
      (libsource (lib "Database_Libs1") (part "C"))
    )
    (comp (ref "C61")
      (value "C")
      (footprint "SMD_0603_CAPC1608X95N")
      (fields
        (field (name "DB_PART_NUMBER") "CAP000028169")
        (field (name "DB_VALUE") "470nF")
        (field (name "DB_TOLERANCE") "5%")
        (field (name "DB_VOLTAGE") "16V")
        (field (name "DB_MANUFACTURER_PART") "KEMET    C0603C474J4RAC")
        (field (name "DB_APPROVED_BY") "ISHIDDEN=T")
      )
      (libsource (lib "Database_Libs1") (part "C"))
    )
    (comp (ref "C62")
      (value "C")
      (footprint "SMD_0603_CAPC1608X95N")
      (fields
        (field (name "DB_PART_NUMBER") "CAP000028169")
        (field (name "DB_VALUE") "470nF")
        (field (name "DB_TOLERANCE") "5%")
        (field (name "DB_VOLTAGE") "16V")
        (field (name "DB_MANUFACTURER_PART") "KEMET    C0603C474J4RAC")
        (field (name "DB_APPROVED_BY") "ISHIDDEN=T")
      )
      (libsource (lib "Database_Libs1") (part "C"))
    )
    (comp (ref "C63")
      (value "C")
      (footprint "SMD_0603_CAPC1608X95N")
      (fields
        (field (name "DB_PART_NUMBER") "CAP000028169")
        (field (name "DB_VALUE") "470nF")
        (field (name "DB_TOLERANCE") "5%")
        (field (name "DB_VOLTAGE") "16V")
        (field (name "DB_MANUFACTURER_PART") "KEMET    C0603C474J4RAC")
        (field (name "DB_APPROVED_BY") "ISHIDDEN=T")
      )
      (libsource (lib "Database_Libs1") (part "C"))
    )
    (comp (ref "C64")
      (value "C")
      (footprint "SMD_0603_CAPC1608X95N")
      (fields
        (field (name "DB_PART_NUMBER") "CAP000028169")
        (field (name "DB_VALUE") "470nF")
        (field (name "DB_TOLERANCE") "5%")
        (field (name "DB_VOLTAGE") "16V")
        (field (name "DB_MANUFACTURER_PART") "KEMET    C0603C474J4RAC")
        (field (name "DB_APPROVED_BY") "ISHIDDEN=T")
      )
      (libsource (lib "Database_Libs1") (part "C"))
    )
    (comp (ref "C65")
      (value "C")
      (footprint "SMD_0603_CAPC1608X95N")
      (fields
        (field (name "DB_PART_NUMBER") "CAP000028169")
        (field (name "DB_VALUE") "470nF")
        (field (name "DB_TOLERANCE") "5%")
        (field (name "DB_VOLTAGE") "16V")
        (field (name "DB_MANUFACTURER_PART") "KEMET    C0603C474J4RAC")
        (field (name "DB_APPROVED_BY") "ISHIDDEN=T")
      )
      (libsource (lib "Database_Libs1") (part "C"))
    )
    (comp (ref "C66")
      (value "C")
      (footprint "SMD_0603_CAPC1608X95N")
      (fields
        (field (name "DB_PART_NUMBER") "CAP000028169")
        (field (name "DB_VALUE") "470nF")
        (field (name "DB_TOLERANCE") "5%")
        (field (name "DB_VOLTAGE") "16V")
        (field (name "DB_MANUFACTURER_PART") "KEMET    C0603C474J4RAC")
        (field (name "DB_APPROVED_BY") "ISHIDDEN=T")
      )
      (libsource (lib "Database_Libs1") (part "C"))
    )
    (comp (ref "C67")
      (value "C")
      (footprint "SMD_0603_CAPC1608X95N")
      (fields
        (field (name "DB_PART_NUMBER") "CAP000028169")
        (field (name "DB_VALUE") "470nF")
        (field (name "DB_TOLERANCE") "5%")
        (field (name "DB_VOLTAGE") "16V")
        (field (name "DB_MANUFACTURER_PART") "KEMET    C0603C474J4RAC")
        (field (name "DB_APPROVED_BY") "ISHIDDEN=T")
      )
      (libsource (lib "Database_Libs1") (part "C"))
    )
    (comp (ref "C68")
      (value "C")
      (footprint "SMD_0603_CAPC1608X95N")
      (fields
        (field (name "DB_PART_NUMBER") "CAP000028169")
        (field (name "DB_VALUE") "470nF")
        (field (name "DB_TOLERANCE") "5%")
        (field (name "DB_VOLTAGE") "16V")
        (field (name "DB_MANUFACTURER_PART") "KEMET    C0603C474J4RAC")
        (field (name "DB_APPROVED_BY") "ISHIDDEN=T")
      )
      (libsource (lib "Database_Libs1") (part "C"))
    )
    (comp (ref "C69")
      (value "C")
      (footprint "SMD_0805_CAPC2012X145N")
      (fields
        (field (name "DB_PART_NUMBER") "CAP000043636")
        (field (name "DB_VALUE") "10uF")
        (field (name "DB_TOLERANCE") "10%")
        (field (name "DB_VOLTAGE") "16V")
        (field (name "DB_MANUFACTURER_PART") "KEMET    C0805C106K4PAC")
        (field (name "DB_APPROVED_BY") "ISHIDDEN=T")
      )
      (libsource (lib "Database_Libs1") (part "C"))
    )
    (comp (ref "C70")
      (value "C")
      (footprint "SMD_0603_CAPC1608X95N")
      (fields
        (field (name "DB_PART_NUMBER") "CAP000028169")
        (field (name "DB_VALUE") "470nF")
        (field (name "DB_TOLERANCE") "5%")
        (field (name "DB_VOLTAGE") "16V")
        (field (name "DB_MANUFACTURER_PART") "KEMET    C0603C474J4RAC")
        (field (name "DB_APPROVED_BY") "ISHIDDEN=T")
      )
      (libsource (lib "Database_Libs1") (part "C"))
    )
    (comp (ref "C71")
      (value "C")
      (footprint "SMD_0603_CAPC1608X95N")
      (fields
        (field (name "DB_PART_NUMBER") "CAP000028169")
        (field (name "DB_VALUE") "470nF")
        (field (name "DB_TOLERANCE") "5%")
        (field (name "DB_VOLTAGE") "16V")
        (field (name "DB_MANUFACTURER_PART") "KEMET    C0603C474J4RAC")
        (field (name "DB_APPROVED_BY") "ISHIDDEN=T")
      )
      (libsource (lib "Database_Libs1") (part "C"))
    )
    (comp (ref "C72")
      (value "C")
      (footprint "SMD_0603_CAPC1608X95N")
      (fields
        (field (name "DB_PART_NUMBER") "CAP000028169")
        (field (name "DB_VALUE") "470nF")
        (field (name "DB_TOLERANCE") "5%")
        (field (name "DB_VOLTAGE") "16V")
        (field (name "DB_MANUFACTURER_PART") "KEMET    C0603C474J4RAC")
        (field (name "DB_APPROVED_BY") "ISHIDDEN=T")
      )
      (libsource (lib "Database_Libs1") (part "C"))
    )
    (comp (ref "C73")
      (value "C")
      (footprint "SMD_0603_CAPC1608X95N")
      (fields
        (field (name "DB_PART_NUMBER") "CAP000028169")
        (field (name "DB_VALUE") "470nF")
        (field (name "DB_TOLERANCE") "5%")
        (field (name "DB_VOLTAGE") "16V")
        (field (name "DB_MANUFACTURER_PART") "KEMET    C0603C474J4RAC")
        (field (name "DB_APPROVED_BY") "ISHIDDEN=T")
      )
      (libsource (lib "Database_Libs1") (part "C"))
    )
    (comp (ref "C74")
      (value "C")
      (footprint "SMD_0603_CAPC1608X95N")
      (fields
        (field (name "DB_PART_NUMBER") "CAP000028169")
        (field (name "DB_VALUE") "470nF")
        (field (name "DB_TOLERANCE") "5%")
        (field (name "DB_VOLTAGE") "16V")
        (field (name "DB_MANUFACTURER_PART") "KEMET    C0603C474J4RAC")
        (field (name "DB_APPROVED_BY") "ISHIDDEN=T")
      )
      (libsource (lib "Database_Libs1") (part "C"))
    )
    (comp (ref "C75")
      (value "C")
      (footprint "SMD_0603_CAPC1608X95N")
      (fields
        (field (name "DB_PART_NUMBER") "CAP000028169")
        (field (name "DB_VALUE") "470nF")
        (field (name "DB_TOLERANCE") "5%")
        (field (name "DB_VOLTAGE") "16V")
        (field (name "DB_MANUFACTURER_PART") "KEMET    C0603C474J4RAC")
        (field (name "DB_APPROVED_BY") "ISHIDDEN=T")
      )
      (libsource (lib "Database_Libs1") (part "C"))
    )
    (comp (ref "C76")
      (value "C")
      (footprint "SMD_0603_CAPC1608X95N")
      (fields
        (field (name "DB_PART_NUMBER") "CAP000028169")
        (field (name "DB_VALUE") "470nF")
        (field (name "DB_TOLERANCE") "5%")
        (field (name "DB_VOLTAGE") "16V")
        (field (name "DB_MANUFACTURER_PART") "KEMET    C0603C474J4RAC")
        (field (name "DB_APPROVED_BY") "ISHIDDEN=T")
      )
      (libsource (lib "Database_Libs1") (part "C"))
    )
    (comp (ref "C77")
      (value "C")
      (footprint "SMD_0603_CAPC1608X95N")
      (fields
        (field (name "DB_PART_NUMBER") "CAP000028169")
        (field (name "DB_VALUE") "470nF")
        (field (name "DB_TOLERANCE") "5%")
        (field (name "DB_VOLTAGE") "16V")
        (field (name "DB_MANUFACTURER_PART") "KEMET    C0603C474J4RAC")
        (field (name "DB_APPROVED_BY") "ISHIDDEN=T")
      )
      (libsource (lib "Database_Libs1") (part "C"))
    )
    (comp (ref "C78")
      (value "C")
      (footprint "SMD_0603_CAPC1608X95N")
      (fields
        (field (name "DB_PART_NUMBER") "CAP000028169")
        (field (name "DB_VALUE") "470nF")
        (field (name "DB_TOLERANCE") "5%")
        (field (name "DB_VOLTAGE") "16V")
        (field (name "DB_MANUFACTURER_PART") "KEMET    C0603C474J4RAC")
        (field (name "DB_APPROVED_BY") "ISHIDDEN=T")
      )
      (libsource (lib "Database_Libs1") (part "C"))
    )
    (comp (ref "C79")
      (value "C")
      (footprint "SMD_0603_CAPC1608X95N")
      (fields
        (field (name "DB_PART_NUMBER") "CAP000028169")
        (field (name "DB_VALUE") "470nF")
        (field (name "DB_TOLERANCE") "5%")
        (field (name "DB_VOLTAGE") "16V")
        (field (name "DB_MANUFACTURER_PART") "KEMET    C0603C474J4RAC")
        (field (name "DB_APPROVED_BY") "ISHIDDEN=T")
      )
      (libsource (lib "Database_Libs1") (part "C"))
    )
    (comp (ref "C80")
      (value "C")
      (footprint "SMD_0603_CAPC1608X95N")
      (fields
        (field (name "DB_PART_NUMBER") "CAP000028169")
        (field (name "DB_VALUE") "470nF")
        (field (name "DB_TOLERANCE") "5%")
        (field (name "DB_VOLTAGE") "16V")
        (field (name "DB_MANUFACTURER_PART") "KEMET    C0603C474J4RAC")
        (field (name "DB_APPROVED_BY") "ISHIDDEN=T")
      )
      (libsource (lib "Database_Libs1") (part "C"))
    )
    (comp (ref "C81")
      (value "C")
      (footprint "SMD_0603_CAPC1608X95N")
      (fields
        (field (name "DB_PART_NUMBER") "CAP000028169")
        (field (name "DB_VALUE") "470nF")
        (field (name "DB_TOLERANCE") "5%")
        (field (name "DB_VOLTAGE") "16V")
        (field (name "DB_MANUFACTURER_PART") "KEMET    C0603C474J4RAC")
        (field (name "DB_APPROVED_BY") "ISHIDDEN=T")
      )
      (libsource (lib "Database_Libs1") (part "C"))
    )
    (comp (ref "C82")
      (value "C")
      (footprint "SMD_0603_CAPC1608X95N")
      (fields
        (field (name "DB_PART_NUMBER") "CAP000028169")
        (field (name "DB_VALUE") "470nF")
        (field (name "DB_TOLERANCE") "5%")
        (field (name "DB_VOLTAGE") "16V")
        (field (name "DB_MANUFACTURER_PART") "KEMET    C0603C474J4RAC")
        (field (name "DB_APPROVED_BY") "ISHIDDEN=T")
      )
      (libsource (lib "Database_Libs1") (part "C"))
    )
    (comp (ref "C83")
      (value "C")
      (footprint "SMD_0603_CAPC1608X95N")
      (fields
        (field (name "DB_PART_NUMBER") "CAP000028169")
        (field (name "DB_VALUE") "470nF")
        (field (name "DB_TOLERANCE") "5%")
        (field (name "DB_VOLTAGE") "16V")
        (field (name "DB_MANUFACTURER_PART") "KEMET    C0603C474J4RAC")
        (field (name "DB_APPROVED_BY") "ISHIDDEN=T")
      )
      (libsource (lib "Database_Libs1") (part "C"))
    )
    (comp (ref "C84")
      (value "C")
      (footprint "SMD_0603_CAPC1608X95N")
      (fields
        (field (name "DB_PART_NUMBER") "CAP000028169")
        (field (name "DB_VALUE") "470nF")
        (field (name "DB_TOLERANCE") "5%")
        (field (name "DB_VOLTAGE") "16V")
        (field (name "DB_MANUFACTURER_PART") "KEMET    C0603C474J4RAC")
        (field (name "DB_APPROVED_BY") "ISHIDDEN=T")
      )
      (libsource (lib "Database_Libs1") (part "C"))
    )
    (comp (ref "C85")
      (value "C")
      (footprint "SMD_0603_CAPC1608X95N")
      (fields
        (field (name "DB_PART_NUMBER") "CAP000028169")
        (field (name "DB_VALUE") "470nF")
        (field (name "DB_TOLERANCE") "5%")
        (field (name "DB_VOLTAGE") "16V")
        (field (name "DB_MANUFACTURER_PART") "KEMET    C0603C474J4RAC")
        (field (name "DB_APPROVED_BY") "ISHIDDEN=T")
      )
      (libsource (lib "Database_Libs1") (part "C"))
    )
    (comp (ref "C118")
      (value "C")
      (footprint "SMD_0603_CAPC1608X95N")
      (fields
        (field (name "DB_PART_NUMBER") "CAP000028169")
        (field (name "DB_VALUE") "470nF")
        (field (name "DB_TOLERANCE") "5%")
        (field (name "DB_VOLTAGE") "16V")
        (field (name "DB_MANUFACTURER_PART") "KEMET    C0603C474J4RAC")
        (field (name "DB_APPROVED_BY") "ISHIDDEN=T")
      )
      (libsource (lib "Database_Libs1") (part "C"))
    )
    (comp (ref "C119")
      (value "C")
      (footprint "SMD_0603_CAPC1608X95N")
      (fields
        (field (name "DB_PART_NUMBER") "CAP000028169")
        (field (name "DB_VALUE") "470nF")
        (field (name "DB_TOLERANCE") "5%")
        (field (name "DB_VOLTAGE") "16V")
        (field (name "DB_MANUFACTURER_PART") "KEMET    C0603C474J4RAC")
        (field (name "DB_APPROVED_BY") "ISHIDDEN=T")
      )
      (libsource (lib "Database_Libs1") (part "C"))
    )
    (comp (ref "C120")
      (value "C")
      (footprint "SMD_0603_CAPC1608X95N")
      (fields
        (field (name "DB_PART_NUMBER") "CAP000028169")
        (field (name "DB_VALUE") "470nF")
        (field (name "DB_TOLERANCE") "5%")
        (field (name "DB_VOLTAGE") "16V")
        (field (name "DB_MANUFACTURER_PART") "KEMET    C0603C474J4RAC")
        (field (name "DB_APPROVED_BY") "ISHIDDEN=T")
      )
      (libsource (lib "Database_Libs1") (part "C"))
    )
    (comp (ref "C121")
      (value "C")
      (footprint "SMD_0603_CAPC1608X95N")
      (fields
        (field (name "DB_PART_NUMBER") "CAP000028169")
        (field (name "DB_VALUE") "470nF")
        (field (name "DB_TOLERANCE") "5%")
        (field (name "DB_VOLTAGE") "16V")
        (field (name "DB_MANUFACTURER_PART") "KEMET    C0603C474J4RAC")
        (field (name "DB_APPROVED_BY") "ISHIDDEN=T")
      )
      (libsource (lib "Database_Libs1") (part "C"))
    )
    (comp (ref "C122")
      (value "C")
      (footprint "SMD_0603_CAPC1608X95N")
      (fields
        (field (name "DB_PART_NUMBER") "CAP000028169")
        (field (name "DB_VALUE") "470nF")
        (field (name "DB_TOLERANCE") "5%")
        (field (name "DB_VOLTAGE") "16V")
        (field (name "DB_MANUFACTURER_PART") "KEMET    C0603C474J4RAC")
        (field (name "DB_APPROVED_BY") "ISHIDDEN=T")
      )
      (libsource (lib "Database_Libs1") (part "C"))
    )
    (comp (ref "C123")
      (value "C")
      (footprint "SMD_0603_CAPC1608X95N")
      (fields
        (field (name "DB_PART_NUMBER") "CAP000028169")
        (field (name "DB_VALUE") "470nF")
        (field (name "DB_TOLERANCE") "5%")
        (field (name "DB_VOLTAGE") "16V")
        (field (name "DB_MANUFACTURER_PART") "KEMET    C0603C474J4RAC")
        (field (name "DB_APPROVED_BY") "ISHIDDEN=T")
      )
      (libsource (lib "Database_Libs1") (part "C"))
    )
    (comp (ref "C124")
      (value "C")
      (footprint "SMD_0603_CAPC1608X95N")
      (fields
        (field (name "DB_PART_NUMBER") "CAP000028169")
        (field (name "DB_VALUE") "470nF")
        (field (name "DB_TOLERANCE") "5%")
        (field (name "DB_VOLTAGE") "16V")
        (field (name "DB_MANUFACTURER_PART") "KEMET    C0603C474J4RAC")
        (field (name "DB_APPROVED_BY") "ISHIDDEN=T")
      )
      (libsource (lib "Database_Libs1") (part "C"))
    )
    (comp (ref "C125")
      (value "C")
      (footprint "SMD_0603_CAPC1608X95N")
      (fields
        (field (name "DB_PART_NUMBER") "CAP000028169")
        (field (name "DB_VALUE") "470nF")
        (field (name "DB_TOLERANCE") "5%")
        (field (name "DB_VOLTAGE") "16V")
        (field (name "DB_MANUFACTURER_PART") "KEMET    C0603C474J4RAC")
        (field (name "DB_APPROVED_BY") "ISHIDDEN=T")
      )
      (libsource (lib "Database_Libs1") (part "C"))
    )
    (comp (ref "C126")
      (value "C")
      (footprint "SMD_0603_CAPC1608X95N")
      (fields
        (field (name "DB_PART_NUMBER") "CAP000028169")
        (field (name "DB_VALUE") "470nF")
        (field (name "DB_TOLERANCE") "5%")
        (field (name "DB_VOLTAGE") "16V")
        (field (name "DB_MANUFACTURER_PART") "KEMET    C0603C474J4RAC")
        (field (name "DB_APPROVED_BY") "ISHIDDEN=T")
      )
      (libsource (lib "Database_Libs1") (part "C"))
    )
    (comp (ref "C127")
      (value "C")
      (footprint "SMD_0603_CAPC1608X95N")
      (fields
        (field (name "DB_PART_NUMBER") "CAP000028169")
        (field (name "DB_VALUE") "470nF")
        (field (name "DB_TOLERANCE") "5%")
        (field (name "DB_VOLTAGE") "16V")
        (field (name "DB_MANUFACTURER_PART") "KEMET    C0603C474J4RAC")
        (field (name "DB_APPROVED_BY") "ISHIDDEN=T")
      )
      (libsource (lib "Database_Libs1") (part "C"))
    )
    (comp (ref "C128")
      (value "C")
      (footprint "SMD_0603_CAPC1608X95N")
      (fields
        (field (name "DB_PART_NUMBER") "CAP000028169")
        (field (name "DB_VALUE") "470nF")
        (field (name "DB_TOLERANCE") "5%")
        (field (name "DB_VOLTAGE") "16V")
        (field (name "DB_MANUFACTURER_PART") "KEMET    C0603C474J4RAC")
        (field (name "DB_APPROVED_BY") "ISHIDDEN=T")
      )
      (libsource (lib "Database_Libs1") (part "C"))
    )
    (comp (ref "C129")
      (value "C")
      (footprint "SMD_0603_CAPC1608X95N")
      (fields
        (field (name "DB_PART_NUMBER") "CAP000028169")
        (field (name "DB_VALUE") "470nF")
        (field (name "DB_TOLERANCE") "5%")
        (field (name "DB_VOLTAGE") "16V")
        (field (name "DB_MANUFACTURER_PART") "KEMET    C0603C474J4RAC")
        (field (name "DB_APPROVED_BY") "ISHIDDEN=T")
      )
      (libsource (lib "Database_Libs1") (part "C"))
    )
    (comp (ref "C130")
      (value "C")
      (footprint "SMD_0603_CAPC1608X95N")
      (fields
        (field (name "DB_PART_NUMBER") "CAP000028169")
        (field (name "DB_VALUE") "470nF")
        (field (name "DB_TOLERANCE") "5%")
        (field (name "DB_VOLTAGE") "16V")
        (field (name "DB_MANUFACTURER_PART") "KEMET    C0603C474J4RAC")
        (field (name "DB_APPROVED_BY") "ISHIDDEN=T")
      )
      (libsource (lib "Database_Libs1") (part "C"))
    )
    (comp (ref "C131")
      (value "C")
      (footprint "SMD_0603_CAPC1608X95N")
      (fields
        (field (name "DB_PART_NUMBER") "CAP000028169")
        (field (name "DB_VALUE") "470nF")
        (field (name "DB_TOLERANCE") "5%")
        (field (name "DB_VOLTAGE") "16V")
        (field (name "DB_MANUFACTURER_PART") "KEMET    C0603C474J4RAC")
        (field (name "DB_APPROVED_BY") "ISHIDDEN=T")
      )
      (libsource (lib "Database_Libs1") (part "C"))
    )
    (comp (ref "C132")
      (value "C")
      (footprint "SMD_0603_CAPC1608X95N")
      (fields
        (field (name "DB_PART_NUMBER") "CAP000028169")
        (field (name "DB_VALUE") "470nF")
        (field (name "DB_TOLERANCE") "5%")
        (field (name "DB_VOLTAGE") "16V")
        (field (name "DB_MANUFACTURER_PART") "KEMET    C0603C474J4RAC")
        (field (name "DB_APPROVED_BY") "ISHIDDEN=T")
      )
      (libsource (lib "Database_Libs1") (part "C"))
    )
    (comp (ref "C133")
      (value "C")
      (footprint "SMD_0603_CAPC1608X95N")
      (fields
        (field (name "DB_PART_NUMBER") "CAP000028169")
        (field (name "DB_VALUE") "470nF")
        (field (name "DB_TOLERANCE") "5%")
        (field (name "DB_VOLTAGE") "16V")
        (field (name "DB_MANUFACTURER_PART") "KEMET    C0603C474J4RAC")
        (field (name "DB_APPROVED_BY") "ISHIDDEN=T")
      )
      (libsource (lib "Database_Libs1") (part "C"))
    )
    (comp (ref "C134")
      (value "C")
      (footprint "SMD_0603_CAPC1608X95N")
      (fields
        (field (name "DB_PART_NUMBER") "CAP000028169")
        (field (name "DB_VALUE") "470nF")
        (field (name "DB_TOLERANCE") "5%")
        (field (name "DB_VOLTAGE") "16V")
        (field (name "DB_MANUFACTURER_PART") "KEMET    C0603C474J4RAC")
        (field (name "DB_APPROVED_BY") "ISHIDDEN=T")
      )
      (libsource (lib "Database_Libs1") (part "C"))
    )
    (comp (ref "C135")
      (value "C")
      (footprint "SMD_0603_CAPC1608X95N")
      (fields
        (field (name "DB_PART_NUMBER") "CAP000028169")
        (field (name "DB_VALUE") "470nF")
        (field (name "DB_TOLERANCE") "5%")
        (field (name "DB_VOLTAGE") "16V")
        (field (name "DB_MANUFACTURER_PART") "KEMET    C0603C474J4RAC")
        (field (name "DB_APPROVED_BY") "ISHIDDEN=T")
      )
      (libsource (lib "Database_Libs1") (part "C"))
    )
    (comp (ref "C136")
      (value "C")
      (footprint "SMD_0603_CAPC1608X95N")
      (fields
        (field (name "DB_PART_NUMBER") "CAP000028169")
        (field (name "DB_VALUE") "470nF")
        (field (name "DB_TOLERANCE") "5%")
        (field (name "DB_VOLTAGE") "16V")
        (field (name "DB_MANUFACTURER_PART") "KEMET    C0603C474J4RAC")
        (field (name "DB_APPROVED_BY") "ISHIDDEN=T")
      )
      (libsource (lib "Database_Libs1") (part "C"))
    )
    (comp (ref "C137")
      (value "C")
      (footprint "SMD_0603_CAPC1608X95N")
      (fields
        (field (name "DB_PART_NUMBER") "CAP000028169")
        (field (name "DB_VALUE") "470nF")
        (field (name "DB_TOLERANCE") "5%")
        (field (name "DB_VOLTAGE") "16V")
        (field (name "DB_MANUFACTURER_PART") "KEMET    C0603C474J4RAC")
        (field (name "DB_APPROVED_BY") "ISHIDDEN=T")
      )
      (libsource (lib "Database_Libs1") (part "C"))
    )
    (comp (ref "C138")
      (value "C")
      (footprint "SMD_0603_CAPC1608X95N")
      (fields
        (field (name "DB_PART_NUMBER") "CAP000024113")
        (field (name "DB_VALUE") "1nF")
        (field (name "DB_TOLERANCE") "5%")
        (field (name "DB_VOLTAGE") "25V")
        (field (name "DB_MANUFACTURER_PART") "KEMET    C0603C102J3RAC")
        (field (name "DB_APPROVED_BY") "ISHIDDEN=T")
      )
      (libsource (lib "Database_Libs1") (part "C"))
    )
    (comp (ref "C139")
      (value "C")
      (footprint "SMD_0805_CAPC2012X145N")
      (fields
        (field (name "DB_PART_NUMBER") "CAP000043636")
        (field (name "DB_VALUE") "10uF")
        (field (name "DB_TOLERANCE") "10%")
        (field (name "DB_VOLTAGE") "16V")
        (field (name "DB_MANUFACTURER_PART") "KEMET    C0805C106K4PAC")
        (field (name "DB_APPROVED_BY") "ISHIDDEN=T")
      )
      (libsource (lib "Database_Libs1") (part "C"))
    )
    (comp (ref "C140")
      (value "C")
      (footprint "SMD_0603_CAPC1608X95N")
      (fields
        (field (name "DB_PART_NUMBER") "CAP000028169")
        (field (name "DB_VALUE") "470nF")
        (field (name "DB_TOLERANCE") "5%")
        (field (name "DB_VOLTAGE") "16V")
        (field (name "DB_MANUFACTURER_PART") "KEMET    C0603C474J4RAC")
        (field (name "DB_APPROVED_BY") "ISHIDDEN=T")
      )
      (libsource (lib "Database_Libs1") (part "C"))
    )
    (comp (ref "C141")
      (value "C")
      (footprint "SMD_0603_CAPC1608X95N")
      (fields
        (field (name "DB_PART_NUMBER") "CAP000028169")
        (field (name "DB_VALUE") "470nF")
        (field (name "DB_TOLERANCE") "5%")
        (field (name "DB_VOLTAGE") "16V")
        (field (name "DB_MANUFACTURER_PART") "KEMET    C0603C474J4RAC")
        (field (name "DB_APPROVED_BY") "ISHIDDEN=T")
      )
      (libsource (lib "Database_Libs1") (part "C"))
    )
    (comp (ref "C142")
      (value "C")
      (footprint "SMD_0603_CAPC1608X95N")
      (fields
        (field (name "DB_PART_NUMBER") "CAP000028169")
        (field (name "DB_VALUE") "470nF")
        (field (name "DB_TOLERANCE") "5%")
        (field (name "DB_VOLTAGE") "16V")
        (field (name "DB_MANUFACTURER_PART") "KEMET    C0603C474J4RAC")
        (field (name "DB_APPROVED_BY") "ISHIDDEN=T")
      )
      (libsource (lib "Database_Libs1") (part "C"))
    )
    (comp (ref "C143")
      (value "C")
      (footprint "SMD_0603_CAPC1608X95N")
      (fields
        (field (name "DB_PART_NUMBER") "CAP000028169")
        (field (name "DB_VALUE") "470nF")
        (field (name "DB_TOLERANCE") "5%")
        (field (name "DB_VOLTAGE") "16V")
        (field (name "DB_MANUFACTURER_PART") "KEMET    C0603C474J4RAC")
        (field (name "DB_APPROVED_BY") "ISHIDDEN=T")
      )
      (libsource (lib "Database_Libs1") (part "C"))
    )
    (comp (ref "C144")
      (value "C")
      (footprint "SMD_0603_CAPC1608X95N")
      (fields
        (field (name "DB_PART_NUMBER") "CAP000028169")
        (field (name "DB_VALUE") "470nF")
        (field (name "DB_TOLERANCE") "5%")
        (field (name "DB_VOLTAGE") "16V")
        (field (name "DB_MANUFACTURER_PART") "KEMET    C0603C474J4RAC")
        (field (name "DB_APPROVED_BY") "ISHIDDEN=T")
      )
      (libsource (lib "Database_Libs1") (part "C"))
    )
    (comp (ref "C145")
      (value "C")
      (footprint "SMD_0603_CAPC1608X95N")
      (fields
        (field (name "DB_PART_NUMBER") "CAP000028169")
        (field (name "DB_VALUE") "470nF")
        (field (name "DB_TOLERANCE") "5%")
        (field (name "DB_VOLTAGE") "16V")
        (field (name "DB_MANUFACTURER_PART") "KEMET    C0603C474J4RAC")
        (field (name "DB_APPROVED_BY") "ISHIDDEN=T")
      )
      (libsource (lib "Database_Libs1") (part "C"))
    )
    (comp (ref "C146")
      (value "C")
      (footprint "SMD_0603_CAPC1608X95N")
      (fields
        (field (name "DB_PART_NUMBER") "CAP000028169")
        (field (name "DB_VALUE") "470nF")
        (field (name "DB_TOLERANCE") "5%")
        (field (name "DB_VOLTAGE") "16V")
        (field (name "DB_MANUFACTURER_PART") "KEMET    C0603C474J4RAC")
        (field (name "DB_APPROVED_BY") "ISHIDDEN=T")
      )
      (libsource (lib "Database_Libs1") (part "C"))
    )
    (comp (ref "C147")
      (value "C")
      (footprint "SMD_0603_CAPC1608X95N")
      (fields
        (field (name "DB_PART_NUMBER") "CAP000028169")
        (field (name "DB_VALUE") "470nF")
        (field (name "DB_TOLERANCE") "5%")
        (field (name "DB_VOLTAGE") "16V")
        (field (name "DB_MANUFACTURER_PART") "KEMET    C0603C474J4RAC")
        (field (name "DB_APPROVED_BY") "ISHIDDEN=T")
      )
      (libsource (lib "Database_Libs1") (part "C"))
    )
    (comp (ref "C148")
      (value "C")
      (footprint "SMD_0603_CAPC1608X95N")
      (fields
        (field (name "DB_PART_NUMBER") "CAP000028169")
        (field (name "DB_VALUE") "470nF")
        (field (name "DB_TOLERANCE") "5%")
        (field (name "DB_VOLTAGE") "16V")
        (field (name "DB_MANUFACTURER_PART") "KEMET    C0603C474J4RAC")
        (field (name "DB_APPROVED_BY") "ISHIDDEN=T")
      )
      (libsource (lib "Database_Libs1") (part "C"))
    )
    (comp (ref "C149")
      (value "C")
      (footprint "SMD_0603_CAPC1608X95N")
      (fields
        (field (name "DB_PART_NUMBER") "CAP000028169")
        (field (name "DB_VALUE") "470nF")
        (field (name "DB_TOLERANCE") "5%")
        (field (name "DB_VOLTAGE") "16V")
        (field (name "DB_MANUFACTURER_PART") "KEMET    C0603C474J4RAC")
        (field (name "DB_APPROVED_BY") "ISHIDDEN=T")
      )
      (libsource (lib "Database_Libs1") (part "C"))
    )
    (comp (ref "C150")
      (value "C")
      (footprint "SMD_0603_CAPC1608X95N")
      (fields
        (field (name "DB_PART_NUMBER") "CAP000028169")
        (field (name "DB_VALUE") "470nF")
        (field (name "DB_TOLERANCE") "5%")
        (field (name "DB_VOLTAGE") "16V")
        (field (name "DB_MANUFACTURER_PART") "KEMET    C0603C474J4RAC")
        (field (name "DB_APPROVED_BY") "ISHIDDEN=T")
      )
      (libsource (lib "Database_Libs1") (part "C"))
    )
    (comp (ref "C151")
      (value "C")
      (footprint "SMD_0603_CAPC1608X95N")
      (fields
        (field (name "DB_PART_NUMBER") "CAP000028169")
        (field (name "DB_VALUE") "470nF")
        (field (name "DB_TOLERANCE") "5%")
        (field (name "DB_VOLTAGE") "16V")
        (field (name "DB_MANUFACTURER_PART") "KEMET    C0603C474J4RAC")
        (field (name "DB_APPROVED_BY") "ISHIDDEN=T")
      )
      (libsource (lib "Database_Libs1") (part "C"))
    )
    (comp (ref "C152")
      (value "C")
      (footprint "SMD_0603_CAPC1608X95N")
      (fields
        (field (name "DB_PART_NUMBER") "CAP000028169")
        (field (name "DB_VALUE") "470nF")
        (field (name "DB_TOLERANCE") "5%")
        (field (name "DB_VOLTAGE") "16V")
        (field (name "DB_MANUFACTURER_PART") "KEMET    C0603C474J4RAC")
        (field (name "DB_APPROVED_BY") "ISHIDDEN=T")
      )
      (libsource (lib "Database_Libs1") (part "C"))
    )
    (comp (ref "C153")
      (value "C")
      (footprint "SMD_0603_CAPC1608X95N")
      (fields
        (field (name "DB_PART_NUMBER") "CAP000028169")
        (field (name "DB_VALUE") "470nF")
        (field (name "DB_TOLERANCE") "5%")
        (field (name "DB_VOLTAGE") "16V")
        (field (name "DB_MANUFACTURER_PART") "KEMET    C0603C474J4RAC")
        (field (name "DB_APPROVED_BY") "ISHIDDEN=T")
      )
      (libsource (lib "Database_Libs1") (part "C"))
    )
    (comp (ref "C154")
      (value "C")
      (footprint "SMD_0603_CAPC1608X95N")
      (fields
        (field (name "DB_PART_NUMBER") "CAP000028169")
        (field (name "DB_VALUE") "470nF")
        (field (name "DB_TOLERANCE") "5%")
        (field (name "DB_VOLTAGE") "16V")
        (field (name "DB_MANUFACTURER_PART") "KEMET    C0603C474J4RAC")
        (field (name "DB_APPROVED_BY") "ISHIDDEN=T")
      )
      (libsource (lib "Database_Libs1") (part "C"))
    )
    (comp (ref "C155")
      (value "C")
      (footprint "SMD_0603_CAPC1608X95N")
      (fields
        (field (name "DB_PART_NUMBER") "CAP000028169")
        (field (name "DB_VALUE") "470nF")
        (field (name "DB_TOLERANCE") "5%")
        (field (name "DB_VOLTAGE") "16V")
        (field (name "DB_MANUFACTURER_PART") "KEMET    C0603C474J4RAC")
        (field (name "DB_APPROVED_BY") "ISHIDDEN=T")
      )
      (libsource (lib "Database_Libs1") (part "C"))
    )
    (comp (ref "C156")
      (value "C")
      (footprint "SMD_0603_CAPC1608X95N")
      (fields
        (field (name "DB_PART_NUMBER") "CAP000028169")
        (field (name "DB_VALUE") "470nF")
        (field (name "DB_TOLERANCE") "5%")
        (field (name "DB_VOLTAGE") "16V")
        (field (name "DB_MANUFACTURER_PART") "KEMET    C0603C474J4RAC")
        (field (name "DB_APPROVED_BY") "ISHIDDEN=T")
      )
      (libsource (lib "Database_Libs1") (part "C"))
    )
    (comp (ref "C157")
      (value "C")
      (footprint "SMD_0603_CAPC1608X95N")
      (fields
        (field (name "DB_PART_NUMBER") "CAP000028169")
        (field (name "DB_VALUE") "470nF")
        (field (name "DB_TOLERANCE") "5%")
        (field (name "DB_VOLTAGE") "16V")
        (field (name "DB_MANUFACTURER_PART") "KEMET    C0603C474J4RAC")
        (field (name "DB_APPROVED_BY") "ISHIDDEN=T")
      )
      (libsource (lib "Database_Libs1") (part "C"))
    )
    (comp (ref "C158")
      (value "C")
      (footprint "SMD_0603_CAPC1608X95N")
      (fields
        (field (name "DB_PART_NUMBER") "CAP000028169")
        (field (name "DB_VALUE") "470nF")
        (field (name "DB_TOLERANCE") "5%")
        (field (name "DB_VOLTAGE") "16V")
        (field (name "DB_MANUFACTURER_PART") "KEMET    C0603C474J4RAC")
        (field (name "DB_APPROVED_BY") "ISHIDDEN=T")
      )
      (libsource (lib "Database_Libs1") (part "C"))
    )
    (comp (ref "C159")
      (value "C")
      (footprint "SMD_0603_CAPC1608X95N")
      (fields
        (field (name "DB_PART_NUMBER") "CAP000028169")
        (field (name "DB_VALUE") "470nF")
        (field (name "DB_TOLERANCE") "5%")
        (field (name "DB_VOLTAGE") "16V")
        (field (name "DB_MANUFACTURER_PART") "KEMET    C0603C474J4RAC")
        (field (name "DB_APPROVED_BY") "ISHIDDEN=T")
      )
      (libsource (lib "Database_Libs1") (part "C"))
    )
    (comp (ref "C160")
      (value "C")
      (footprint "SMD_0603_CAPC1608X95N")
      (fields
        (field (name "DB_PART_NUMBER") "CAP000028169")
        (field (name "DB_VALUE") "470nF")
        (field (name "DB_TOLERANCE") "5%")
        (field (name "DB_VOLTAGE") "16V")
        (field (name "DB_MANUFACTURER_PART") "KEMET    C0603C474J4RAC")
        (field (name "DB_APPROVED_BY") "ISHIDDEN=T")
      )
      (libsource (lib "Database_Libs1") (part "C"))
    )
    (comp (ref "C161")
      (value "C")
      (footprint "SMD_0603_CAPC1608X95N")
      (fields
        (field (name "DB_PART_NUMBER") "CAP000028169")
        (field (name "DB_VALUE") "470nF")
        (field (name "DB_TOLERANCE") "5%")
        (field (name "DB_VOLTAGE") "16V")
        (field (name "DB_MANUFACTURER_PART") "KEMET    C0603C474J4RAC")
        (field (name "DB_APPROVED_BY") "ISHIDDEN=T")
      )
      (libsource (lib "Database_Libs1") (part "C"))
    )
    (comp (ref "C162")
      (value "C")
      (footprint "SMD_0603_CAPC1608X95N")
      (fields
        (field (name "DB_PART_NUMBER") "CAP000028169")
        (field (name "DB_VALUE") "470nF")
        (field (name "DB_TOLERANCE") "5%")
        (field (name "DB_VOLTAGE") "16V")
        (field (name "DB_MANUFACTURER_PART") "KEMET    C0603C474J4RAC")
        (field (name "DB_APPROVED_BY") "ISHIDDEN=T")
      )
      (libsource (lib "Database_Libs1") (part "C"))
    )
    (comp (ref "C163")
      (value "C")
      (footprint "SMD_0603_CAPC1608X95N")
      (fields
        (field (name "DB_PART_NUMBER") "CAP000028169")
        (field (name "DB_VALUE") "470nF")
        (field (name "DB_TOLERANCE") "5%")
        (field (name "DB_VOLTAGE") "16V")
        (field (name "DB_MANUFACTURER_PART") "KEMET    C0603C474J4RAC")
        (field (name "DB_APPROVED_BY") "ISHIDDEN=T")
      )
      (libsource (lib "Database_Libs1") (part "C"))
    )
    (comp (ref "C166")
      (value "C")
      (footprint "SMD_0603_CAPC1608X95N")
      (fields
        (field (name "DB_PART_NUMBER") "CAP000024113")
        (field (name "DB_VALUE") "1nF")
        (field (name "DB_TOLERANCE") "5%")
        (field (name "DB_VOLTAGE") "25V")
        (field (name "DB_MANUFACTURER_PART") "KEMET    C0603C102J3RAC")
        (field (name "DB_APPROVED_BY") "ISHIDDEN=T")
      )
      (libsource (lib "Database_Libs1") (part "C"))
    )
    (comp (ref "C167")
      (value "C")
      (footprint "SMD_0603_CAPC1608X95N")
      (fields
        (field (name "DB_PART_NUMBER") "CAP000027136")
        (field (name "DB_VALUE") "100nF")
        (field (name "DB_TOLERANCE") "5%")
        (field (name "DB_VOLTAGE") "50V")
        (field (name "DB_MANUFACTURER_PART") "KEMET    C0603C104J5RAC")
        (field (name "DB_APPROVED_BY") "ISHIDDEN=T")
      )
      (libsource (lib "Database_Libs1") (part "C"))
    )
    (comp (ref "C168")
      (value "C")
      (footprint "SMD_0603_CAPC1608X95N")
      (fields
        (field (name "DB_PART_NUMBER") "CAP000027136")
        (field (name "DB_VALUE") "100nF")
        (field (name "DB_TOLERANCE") "5%")
        (field (name "DB_VOLTAGE") "50V")
        (field (name "DB_MANUFACTURER_PART") "KEMET    C0603C104J5RAC")
        (field (name "DB_APPROVED_BY") "ISHIDDEN=T")
      )
      (libsource (lib "Database_Libs1") (part "C"))
    )
    (comp (ref "C169")
      (value "C")
      (footprint "SMD_0603_CAPC1608X95N")
      (fields
        (field (name "DB_PART_NUMBER") "CAP000027136")
        (field (name "DB_VALUE") "100nF")
        (field (name "DB_TOLERANCE") "5%")
        (field (name "DB_VOLTAGE") "50V")
        (field (name "DB_MANUFACTURER_PART") "KEMET    C0603C104J5RAC")
        (field (name "DB_APPROVED_BY") "ISHIDDEN=T")
      )
      (libsource (lib "Database_Libs1") (part "C"))
    )
    (comp (ref "C170")
      (value "C")
      (footprint "SMD_0603_CAPC1608X95N")
      (fields
        (field (name "DB_PART_NUMBER") "CAP000027136")
        (field (name "DB_VALUE") "100nF")
        (field (name "DB_TOLERANCE") "5%")
        (field (name "DB_VOLTAGE") "50V")
        (field (name "DB_MANUFACTURER_PART") "KEMET    C0603C104J5RAC")
        (field (name "DB_APPROVED_BY") "ISHIDDEN=T")
      )
      (libsource (lib "Database_Libs1") (part "C"))
    )
    (comp (ref "C171")
      (value "C")
      (footprint "SMD_0603_CAPC1608X95N")
      (fields
        (field (name "DB_PART_NUMBER") "CAP000027136")
        (field (name "DB_VALUE") "100nF")
        (field (name "DB_TOLERANCE") "5%")
        (field (name "DB_VOLTAGE") "50V")
        (field (name "DB_MANUFACTURER_PART") "KEMET    C0603C104J5RAC")
        (field (name "DB_APPROVED_BY") "ISHIDDEN=T")
      )
      (libsource (lib "Database_Libs1") (part "C"))
    )
    (comp (ref "C172")
      (value "C")
      (footprint "SMD_0603_CAPC1608X95N")
      (fields
        (field (name "DB_PART_NUMBER") "CAP000027136")
        (field (name "DB_VALUE") "100nF")
        (field (name "DB_TOLERANCE") "5%")
        (field (name "DB_VOLTAGE") "50V")
        (field (name "DB_MANUFACTURER_PART") "KEMET    C0603C104J5RAC")
        (field (name "DB_APPROVED_BY") "ISHIDDEN=T")
      )
      (libsource (lib "Database_Libs1") (part "C"))
    )
    (comp (ref "C173")
      (value "C")
      (footprint "SMD_0603_CAPC1608X95N")
      (fields
        (field (name "DB_PART_NUMBER") "CAP000031922")
        (field (name "DB_VALUE") "18pF")
        (field (name "DB_TOLERANCE") "5%")
        (field (name "DB_VOLTAGE") "50V")
        (field (name "DB_MANUFACTURER_PART") "KEMET    C0603C180J5GAC")
        (field (name "DB_APPROVED_BY") "ISHIDDEN=T")
      )
      (libsource (lib "Database_Libs1") (part "C"))
    )
    (comp (ref "C174")
      (value "C")
      (footprint "SMD_0603_CAPC1608X95N")
      (fields
        (field (name "DB_PART_NUMBER") "CAP000031922")
        (field (name "DB_VALUE") "18pF")
        (field (name "DB_TOLERANCE") "5%")
        (field (name "DB_VOLTAGE") "50V")
        (field (name "DB_MANUFACTURER_PART") "KEMET    C0603C180J5GAC")
        (field (name "DB_APPROVED_BY") "ISHIDDEN=T")
      )
      (libsource (lib "Database_Libs1") (part "C"))
    )
    (comp (ref "C175")
      (value "C")
      (footprint "SMD_0603_CAPC1608X95N")
      (fields
        (field (name "DB_PART_NUMBER") "CAP000028169")
        (field (name "DB_VALUE") "470nF")
        (field (name "DB_TOLERANCE") "5%")
        (field (name "DB_VOLTAGE") "16V")
        (field (name "DB_MANUFACTURER_PART") "KEMET    C0603C474J4RAC")
        (field (name "DB_APPROVED_BY") "ISHIDDEN=T")
      )
      (libsource (lib "Database_Libs1") (part "C"))
    )
    (comp (ref "C176")
      (value "C")
      (footprint "SMD_0603_CAPC1608X95N")
      (fields
        (field (name "DB_PART_NUMBER") "CAP000028169")
        (field (name "DB_VALUE") "470nF")
        (field (name "DB_TOLERANCE") "5%")
        (field (name "DB_VOLTAGE") "16V")
        (field (name "DB_MANUFACTURER_PART") "KEMET    C0603C474J4RAC")
        (field (name "DB_APPROVED_BY") "ISHIDDEN=T")
      )
      (libsource (lib "Database_Libs1") (part "C"))
    )
    (comp (ref "C177")
      (value "C")
      (footprint "SMD_0603_CAPC1608X95N")
      (fields
        (field (name "DB_PART_NUMBER") "CAP000028169")
        (field (name "DB_VALUE") "470nF")
        (field (name "DB_TOLERANCE") "5%")
        (field (name "DB_VOLTAGE") "16V")
        (field (name "DB_MANUFACTURER_PART") "KEMET    C0603C474J4RAC")
        (field (name "DB_APPROVED_BY") "ISHIDDEN=T")
      )
      (libsource (lib "Database_Libs1") (part "C"))
    )
    (comp (ref "C178")
      (value "C")
      (footprint "SMD_0603_CAPC1608X95N")
      (fields
        (field (name "DB_PART_NUMBER") "CAP000028169")
        (field (name "DB_VALUE") "470nF")
        (field (name "DB_TOLERANCE") "5%")
        (field (name "DB_VOLTAGE") "16V")
        (field (name "DB_MANUFACTURER_PART") "KEMET    C0603C474J4RAC")
        (field (name "DB_APPROVED_BY") "ISHIDDEN=T")
      )
      (libsource (lib "Database_Libs1") (part "C"))
    )
    (comp (ref "C179")
      (value "C")
      (footprint "SMD_0603_CAPC1608X95N")
      (fields
        (field (name "DB_PART_NUMBER") "CAP000028169")
        (field (name "DB_VALUE") "470nF")
        (field (name "DB_TOLERANCE") "5%")
        (field (name "DB_VOLTAGE") "16V")
        (field (name "DB_MANUFACTURER_PART") "KEMET    C0603C474J4RAC")
        (field (name "DB_APPROVED_BY") "ISHIDDEN=T")
      )
      (libsource (lib "Database_Libs1") (part "C"))
    )
    (comp (ref "C180")
      (value "C")
      (footprint "SMD_0603_CAPC1608X95N")
      (fields
        (field (name "DB_PART_NUMBER") "CAP000028169")
        (field (name "DB_VALUE") "470nF")
        (field (name "DB_TOLERANCE") "5%")
        (field (name "DB_VOLTAGE") "16V")
        (field (name "DB_MANUFACTURER_PART") "KEMET    C0603C474J4RAC")
        (field (name "DB_APPROVED_BY") "ISHIDDEN=T")
      )
      (libsource (lib "Database_Libs1") (part "C"))
    )
    (comp (ref "C181")
      (value "C")
      (footprint "SMD_0603_CAPC1608X95N")
      (fields
        (field (name "DB_PART_NUMBER") "CAP000028169")
        (field (name "DB_VALUE") "470nF")
        (field (name "DB_TOLERANCE") "5%")
        (field (name "DB_VOLTAGE") "16V")
        (field (name "DB_MANUFACTURER_PART") "KEMET    C0603C474J4RAC")
        (field (name "DB_APPROVED_BY") "ISHIDDEN=T")
      )
      (libsource (lib "Database_Libs1") (part "C"))
    )
    (comp (ref "C182")
      (value "C")
      (footprint "SMD_0603_CAPC1608X95N")
      (fields
        (field (name "DB_PART_NUMBER") "CAP000028169")
        (field (name "DB_VALUE") "470nF")
        (field (name "DB_TOLERANCE") "5%")
        (field (name "DB_VOLTAGE") "16V")
        (field (name "DB_MANUFACTURER_PART") "KEMET    C0603C474J4RAC")
        (field (name "DB_APPROVED_BY") "ISHIDDEN=T")
      )
      (libsource (lib "Database_Libs1") (part "C"))
    )
    (comp (ref "C183")
      (value "C")
      (footprint "SMD_0603_CAPC1608X95N")
      (fields
        (field (name "DB_PART_NUMBER") "CAP000028169")
        (field (name "DB_VALUE") "470nF")
        (field (name "DB_TOLERANCE") "5%")
        (field (name "DB_VOLTAGE") "16V")
        (field (name "DB_MANUFACTURER_PART") "KEMET    C0603C474J4RAC")
        (field (name "DB_APPROVED_BY") "ISHIDDEN=T")
      )
      (libsource (lib "Database_Libs1") (part "C"))
    )
    (comp (ref "C184")
      (value "C")
      (footprint "SMD_0603_CAPC1608X95N")
      (fields
        (field (name "DB_PART_NUMBER") "CAP000028169")
        (field (name "DB_VALUE") "470nF")
        (field (name "DB_TOLERANCE") "5%")
        (field (name "DB_VOLTAGE") "16V")
        (field (name "DB_MANUFACTURER_PART") "KEMET    C0603C474J4RAC")
        (field (name "DB_APPROVED_BY") "ISHIDDEN=T")
      )
      (libsource (lib "Database_Libs1") (part "C"))
    )
    (comp (ref "C185")
      (value "C")
      (footprint "SMD_0603_CAPC1608X95N")
      (fields
        (field (name "DB_PART_NUMBER") "CAP000028169")
        (field (name "DB_VALUE") "470nF")
        (field (name "DB_TOLERANCE") "5%")
        (field (name "DB_VOLTAGE") "16V")
        (field (name "DB_MANUFACTURER_PART") "KEMET    C0603C474J4RAC")
        (field (name "DB_APPROVED_BY") "ISHIDDEN=T")
      )
      (libsource (lib "Database_Libs1") (part "C"))
    )
    (comp (ref "C186")
      (value "C")
      (footprint "SMD_0603_CAPC1608X95N")
      (fields
        (field (name "DB_PART_NUMBER") "CAP000028169")
        (field (name "DB_VALUE") "470nF")
        (field (name "DB_TOLERANCE") "5%")
        (field (name "DB_VOLTAGE") "16V")
        (field (name "DB_MANUFACTURER_PART") "KEMET    C0603C474J4RAC")
        (field (name "DB_APPROVED_BY") "ISHIDDEN=T")
      )
      (libsource (lib "Database_Libs1") (part "C"))
    )
    (comp (ref "C187")
      (value "C")
      (footprint "SMD_0603_CAPC1608X95N")
      (fields
        (field (name "DB_PART_NUMBER") "CAP000028169")
        (field (name "DB_VALUE") "470nF")
        (field (name "DB_TOLERANCE") "5%")
        (field (name "DB_VOLTAGE") "16V")
        (field (name "DB_MANUFACTURER_PART") "KEMET    C0603C474J4RAC")
        (field (name "DB_APPROVED_BY") "ISHIDDEN=T")
      )
      (libsource (lib "Database_Libs1") (part "C"))
    )
    (comp (ref "C188")
      (value "C")
      (footprint "SMD_0603_CAPC1608X95N")
      (fields
        (field (name "DB_PART_NUMBER") "CAP000028169")
        (field (name "DB_VALUE") "470nF")
        (field (name "DB_TOLERANCE") "5%")
        (field (name "DB_VOLTAGE") "16V")
        (field (name "DB_MANUFACTURER_PART") "KEMET    C0603C474J4RAC")
        (field (name "DB_APPROVED_BY") "ISHIDDEN=T")
      )
      (libsource (lib "Database_Libs1") (part "C"))
    )
    (comp (ref "C189")
      (value "C")
      (footprint "SMD_0603_CAPC1608X95N")
      (fields
        (field (name "DB_PART_NUMBER") "CAP000028169")
        (field (name "DB_VALUE") "470nF")
        (field (name "DB_TOLERANCE") "5%")
        (field (name "DB_VOLTAGE") "16V")
        (field (name "DB_MANUFACTURER_PART") "KEMET    C0603C474J4RAC")
        (field (name "DB_APPROVED_BY") "ISHIDDEN=T")
      )
      (libsource (lib "Database_Libs1") (part "C"))
    )
    (comp (ref "C190")
      (value "C")
      (footprint "SMD_0603_CAPC1608X95N")
      (fields
        (field (name "DB_PART_NUMBER") "CAP000028169")
        (field (name "DB_VALUE") "470nF")
        (field (name "DB_TOLERANCE") "5%")
        (field (name "DB_VOLTAGE") "16V")
        (field (name "DB_MANUFACTURER_PART") "KEMET    C0603C474J4RAC")
        (field (name "DB_APPROVED_BY") "ISHIDDEN=T")
      )
      (libsource (lib "Database_Libs1") (part "C"))
    )
    (comp (ref "C191")
      (value "C")
      (footprint "SMD_0805_CAPC2012X145N")
      (fields
        (field (name "DB_PART_NUMBER") "CAP000043636")
        (field (name "DB_VALUE") "10uF")
        (field (name "DB_TOLERANCE") "10%")
        (field (name "DB_VOLTAGE") "16V")
        (field (name "DB_MANUFACTURER_PART") "KEMET    C0805C106K4PAC")
        (field (name "DB_APPROVED_BY") "ISHIDDEN=T")
      )
      (libsource (lib "Database_Libs1") (part "C"))
    )
    (comp (ref "C224")
      (value "C")
      (footprint "SMD_1210_CAPC3225X279N")
      (fields
        (field (name "DB_PART_NUMBER") "CAP000047355")
        (field (name "DB_VALUE") "220uF")
        (field (name "DB_TOLERANCE") "20%")
        (field (name "DB_VOLTAGE") "6.3V")
        (field (name "DB_MANUFACTURER_PART") "SAMSUNG    CL32A227MQVNNNE")
        (field (name "DB_APPROVED_BY") "VSN")
      )
      (libsource (lib "Database_Libs1") (part "C"))
    )
    (comp (ref "C225")
      (value "C")
      (footprint "SMD_0805_CAPC2012X145N")
      (fields
        (field (name "DB_PART_NUMBER") "CAP000043686")
        (field (name "DB_VALUE") "22uF")
        (field (name "DB_TOLERANCE") "20%")
        (field (name "DB_VOLTAGE") "6.3V")
        (field (name "DB_MANUFACTURER_PART") "KEMET    C0805C226M9PAC")
        (field (name "DB_APPROVED_BY") "ISHIDDEN=T")
      )
      (libsource (lib "Database_Libs1") (part "C"))
    )
    (comp (ref "C226")
      (value "C")
      (footprint "SMD_0805_CAPC2012X145N")
      (fields
        (field (name "DB_PART_NUMBER") "CAP000043636")
        (field (name "DB_VALUE") "10uF")
        (field (name "DB_TOLERANCE") "10%")
        (field (name "DB_VOLTAGE") "16V")
        (field (name "DB_MANUFACTURER_PART") "KEMET    C0805C106K4PAC")
        (field (name "DB_APPROVED_BY") "ISHIDDEN=T")
      )
      (libsource (lib "Database_Libs1") (part "C"))
    )
    (comp (ref "C227")
      (value "C")
      (footprint "SMD_0603_CAPC1608X95N")
      (fields
        (field (name "DB_PART_NUMBER") "CAP000028169")
        (field (name "DB_VALUE") "470nF")
        (field (name "DB_TOLERANCE") "5%")
        (field (name "DB_VOLTAGE") "16V")
        (field (name "DB_MANUFACTURER_PART") "KEMET    C0603C474J4RAC")
        (field (name "DB_APPROVED_BY") "ISHIDDEN=T")
      )
      (libsource (lib "Database_Libs1") (part "C"))
    )
    (comp (ref "C228")
      (value "C")
      (footprint "SMD_0603_CAPC1608X95N")
      (fields
        (field (name "DB_PART_NUMBER") "CAP000028169")
        (field (name "DB_VALUE") "470nF")
        (field (name "DB_TOLERANCE") "5%")
        (field (name "DB_VOLTAGE") "16V")
        (field (name "DB_MANUFACTURER_PART") "KEMET    C0603C474J4RAC")
        (field (name "DB_APPROVED_BY") "ISHIDDEN=T")
      )
      (libsource (lib "Database_Libs1") (part "C"))
    )
    (comp (ref "C229")
      (value "C")
      (footprint "SMD_0603_CAPC1608X95N")
      (fields
        (field (name "DB_PART_NUMBER") "CAP000028169")
        (field (name "DB_VALUE") "470nF")
        (field (name "DB_TOLERANCE") "5%")
        (field (name "DB_VOLTAGE") "16V")
        (field (name "DB_MANUFACTURER_PART") "KEMET    C0603C474J4RAC")
        (field (name "DB_APPROVED_BY") "ISHIDDEN=T")
      )
      (libsource (lib "Database_Libs1") (part "C"))
    )
    (comp (ref "C230")
      (value "C")
      (footprint "SMD_0603_CAPC1608X95N")
      (fields
        (field (name "DB_PART_NUMBER") "CAP000028169")
        (field (name "DB_VALUE") "470nF")
        (field (name "DB_TOLERANCE") "5%")
        (field (name "DB_VOLTAGE") "16V")
        (field (name "DB_MANUFACTURER_PART") "KEMET    C0603C474J4RAC")
        (field (name "DB_APPROVED_BY") "ISHIDDEN=T")
      )
      (libsource (lib "Database_Libs1") (part "C"))
    )
    (comp (ref "C231")
      (value "C")
      (footprint "SMD_0603_CAPC1608X95N")
      (fields
        (field (name "DB_PART_NUMBER") "CAP000028169")
        (field (name "DB_VALUE") "470nF")
        (field (name "DB_TOLERANCE") "5%")
        (field (name "DB_VOLTAGE") "16V")
        (field (name "DB_MANUFACTURER_PART") "KEMET    C0603C474J4RAC")
        (field (name "DB_APPROVED_BY") "ISHIDDEN=T")
      )
      (libsource (lib "Database_Libs1") (part "C"))
    )
    (comp (ref "C232")
      (value "C")
      (footprint "SMD_0603_CAPC1608X95N")
      (fields
        (field (name "DB_PART_NUMBER") "CAP000028169")
        (field (name "DB_VALUE") "470nF")
        (field (name "DB_TOLERANCE") "5%")
        (field (name "DB_VOLTAGE") "16V")
        (field (name "DB_MANUFACTURER_PART") "KEMET    C0603C474J4RAC")
        (field (name "DB_APPROVED_BY") "ISHIDDEN=T")
      )
      (libsource (lib "Database_Libs1") (part "C"))
    )
    (comp (ref "C233")
      (value "C")
      (footprint "SMD_0603_CAPC1608X95N")
      (fields
        (field (name "DB_PART_NUMBER") "CAP000028169")
        (field (name "DB_VALUE") "470nF")
        (field (name "DB_TOLERANCE") "5%")
        (field (name "DB_VOLTAGE") "16V")
        (field (name "DB_MANUFACTURER_PART") "KEMET    C0603C474J4RAC")
        (field (name "DB_APPROVED_BY") "ISHIDDEN=T")
      )
      (libsource (lib "Database_Libs1") (part "C"))
    )
    (comp (ref "C234")
      (value "C")
      (footprint "SMD_0603_CAPC1608X95N")
      (fields
        (field (name "DB_PART_NUMBER") "CAP000028169")
        (field (name "DB_VALUE") "470nF")
        (field (name "DB_TOLERANCE") "5%")
        (field (name "DB_VOLTAGE") "16V")
        (field (name "DB_MANUFACTURER_PART") "KEMET    C0603C474J4RAC")
        (field (name "DB_APPROVED_BY") "ISHIDDEN=T")
      )
      (libsource (lib "Database_Libs1") (part "C"))
    )
    (comp (ref "C235")
      (value "C")
      (footprint "SMD_0603_CAPC1608X95N")
      (fields
        (field (name "DB_PART_NUMBER") "CAP000028169")
        (field (name "DB_VALUE") "470nF")
        (field (name "DB_TOLERANCE") "5%")
        (field (name "DB_VOLTAGE") "16V")
        (field (name "DB_MANUFACTURER_PART") "KEMET    C0603C474J4RAC")
        (field (name "DB_APPROVED_BY") "ISHIDDEN=T")
      )
      (libsource (lib "Database_Libs1") (part "C"))
    )
    (comp (ref "C236")
      (value "C")
      (footprint "SMD_0603_CAPC1608X95N")
      (fields
        (field (name "DB_PART_NUMBER") "CAP000028169")
        (field (name "DB_VALUE") "470nF")
        (field (name "DB_TOLERANCE") "5%")
        (field (name "DB_VOLTAGE") "16V")
        (field (name "DB_MANUFACTURER_PART") "KEMET    C0603C474J4RAC")
        (field (name "DB_APPROVED_BY") "ISHIDDEN=T")
      )
      (libsource (lib "Database_Libs1") (part "C"))
    )
    (comp (ref "C237")
      (value "C")
      (footprint "SMD_0603_CAPC1608X95N")
      (fields
        (field (name "DB_PART_NUMBER") "CAP000028169")
        (field (name "DB_VALUE") "470nF")
        (field (name "DB_TOLERANCE") "5%")
        (field (name "DB_VOLTAGE") "16V")
        (field (name "DB_MANUFACTURER_PART") "KEMET    C0603C474J4RAC")
        (field (name "DB_APPROVED_BY") "ISHIDDEN=T")
      )
      (libsource (lib "Database_Libs1") (part "C"))
    )
    (comp (ref "C238")
      (value "C")
      (footprint "SMD_0603_CAPC1608X95N")
      (fields
        (field (name "DB_PART_NUMBER") "CAP000028169")
        (field (name "DB_VALUE") "470nF")
        (field (name "DB_TOLERANCE") "5%")
        (field (name "DB_VOLTAGE") "16V")
        (field (name "DB_MANUFACTURER_PART") "KEMET    C0603C474J4RAC")
        (field (name "DB_APPROVED_BY") "ISHIDDEN=T")
      )
      (libsource (lib "Database_Libs1") (part "C"))
    )
    (comp (ref "C239")
      (value "C")
      (footprint "SMD_0603_CAPC1608X95N")
      (fields
        (field (name "DB_PART_NUMBER") "CAP000028169")
        (field (name "DB_VALUE") "470nF")
        (field (name "DB_TOLERANCE") "5%")
        (field (name "DB_VOLTAGE") "16V")
        (field (name "DB_MANUFACTURER_PART") "KEMET    C0603C474J4RAC")
        (field (name "DB_APPROVED_BY") "ISHIDDEN=T")
      )
      (libsource (lib "Database_Libs1") (part "C"))
    )
    (comp (ref "C240")
      (value "C")
      (footprint "SMD_0603_CAPC1608X95N")
      (fields
        (field (name "DB_PART_NUMBER") "CAP000028169")
        (field (name "DB_VALUE") "470nF")
        (field (name "DB_TOLERANCE") "5%")
        (field (name "DB_VOLTAGE") "16V")
        (field (name "DB_MANUFACTURER_PART") "KEMET    C0603C474J4RAC")
        (field (name "DB_APPROVED_BY") "ISHIDDEN=T")
      )
      (libsource (lib "Database_Libs1") (part "C"))
    )
    (comp (ref "C241")
      (value "C")
      (footprint "SMD_0603_CAPC1608X95N")
      (fields
        (field (name "DB_PART_NUMBER") "CAP000028169")
        (field (name "DB_VALUE") "470nF")
        (field (name "DB_TOLERANCE") "5%")
        (field (name "DB_VOLTAGE") "16V")
        (field (name "DB_MANUFACTURER_PART") "KEMET    C0603C474J4RAC")
        (field (name "DB_APPROVED_BY") "ISHIDDEN=T")
      )
      (libsource (lib "Database_Libs1") (part "C"))
    )
    (comp (ref "C242")
      (value "C")
      (footprint "SMD_0603_CAPC1608X95N")
      (fields
        (field (name "DB_PART_NUMBER") "CAP000028169")
        (field (name "DB_VALUE") "470nF")
        (field (name "DB_TOLERANCE") "5%")
        (field (name "DB_VOLTAGE") "16V")
        (field (name "DB_MANUFACTURER_PART") "KEMET    C0603C474J4RAC")
        (field (name "DB_APPROVED_BY") "ISHIDDEN=T")
      )
      (libsource (lib "Database_Libs1") (part "C"))
    )
    (comp (ref "C243")
      (value "C")
      (footprint "SMD_0603_CAPC1608X95N")
      (fields
        (field (name "DB_PART_NUMBER") "CAP000028169")
        (field (name "DB_VALUE") "470nF")
        (field (name "DB_TOLERANCE") "5%")
        (field (name "DB_VOLTAGE") "16V")
        (field (name "DB_MANUFACTURER_PART") "KEMET    C0603C474J4RAC")
        (field (name "DB_APPROVED_BY") "ISHIDDEN=T")
      )
      (libsource (lib "Database_Libs1") (part "C"))
    )
    (comp (ref "C244")
      (value "C")
      (footprint "SMD_0603_CAPC1608X95N")
      (fields
        (field (name "DB_PART_NUMBER") "CAP000028169")
        (field (name "DB_VALUE") "470nF")
        (field (name "DB_TOLERANCE") "5%")
        (field (name "DB_VOLTAGE") "16V")
        (field (name "DB_MANUFACTURER_PART") "KEMET    C0603C474J4RAC")
        (field (name "DB_APPROVED_BY") "ISHIDDEN=T")
      )
      (libsource (lib "Database_Libs1") (part "C"))
    )
    (comp (ref "C245")
      (value "C")
      (footprint "SMD_0603_CAPC1608X95N")
      (fields
        (field (name "DB_PART_NUMBER") "CAP000028169")
        (field (name "DB_VALUE") "470nF")
        (field (name "DB_TOLERANCE") "5%")
        (field (name "DB_VOLTAGE") "16V")
        (field (name "DB_MANUFACTURER_PART") "KEMET    C0603C474J4RAC")
        (field (name "DB_APPROVED_BY") "ISHIDDEN=T")
      )
      (libsource (lib "Database_Libs1") (part "C"))
    )
    (comp (ref "C246")
      (value "C")
      (footprint "SMD_0603_CAPC1608X95N")
      (fields
        (field (name "DB_PART_NUMBER") "CAP000028169")
        (field (name "DB_VALUE") "470nF")
        (field (name "DB_TOLERANCE") "5%")
        (field (name "DB_VOLTAGE") "16V")
        (field (name "DB_MANUFACTURER_PART") "KEMET    C0603C474J4RAC")
        (field (name "DB_APPROVED_BY") "ISHIDDEN=T")
      )
      (libsource (lib "Database_Libs1") (part "C"))
    )
    (comp (ref "C247")
      (value "C")
      (footprint "SMD_0603_CAPC1608X95N")
      (fields
        (field (name "DB_PART_NUMBER") "CAP000028169")
        (field (name "DB_VALUE") "470nF")
        (field (name "DB_TOLERANCE") "5%")
        (field (name "DB_VOLTAGE") "16V")
        (field (name "DB_MANUFACTURER_PART") "KEMET    C0603C474J4RAC")
        (field (name "DB_APPROVED_BY") "ISHIDDEN=T")
      )
      (libsource (lib "Database_Libs1") (part "C"))
    )
    (comp (ref "C248")
      (value "C")
      (footprint "SMD_0603_CAPC1608X95N")
      (fields
        (field (name "DB_PART_NUMBER") "CAP000028169")
        (field (name "DB_VALUE") "470nF")
        (field (name "DB_TOLERANCE") "5%")
        (field (name "DB_VOLTAGE") "16V")
        (field (name "DB_MANUFACTURER_PART") "KEMET    C0603C474J4RAC")
        (field (name "DB_APPROVED_BY") "ISHIDDEN=T")
      )
      (libsource (lib "Database_Libs1") (part "C"))
    )
    (comp (ref "C249")
      (value "C")
      (footprint "SMD_0603_CAPC1608X95N")
      (fields
        (field (name "DB_PART_NUMBER") "CAP000028169")
        (field (name "DB_VALUE") "470nF")
        (field (name "DB_TOLERANCE") "5%")
        (field (name "DB_VOLTAGE") "16V")
        (field (name "DB_MANUFACTURER_PART") "KEMET    C0603C474J4RAC")
        (field (name "DB_APPROVED_BY") "ISHIDDEN=T")
      )
      (libsource (lib "Database_Libs1") (part "C"))
    )
    (comp (ref "C250")
      (value "C")
      (footprint "SMD_0603_CAPC1608X95N")
      (fields
        (field (name "DB_PART_NUMBER") "CAP000028169")
        (field (name "DB_VALUE") "470nF")
        (field (name "DB_TOLERANCE") "5%")
        (field (name "DB_VOLTAGE") "16V")
        (field (name "DB_MANUFACTURER_PART") "KEMET    C0603C474J4RAC")
        (field (name "DB_APPROVED_BY") "ISHIDDEN=T")
      )
      (libsource (lib "Database_Libs1") (part "C"))
    )
    (comp (ref "C251")
      (value "C")
      (footprint "SMD_0603_CAPC1608X95N")
      (fields
        (field (name "DB_PART_NUMBER") "CAP000028169")
        (field (name "DB_VALUE") "470nF")
        (field (name "DB_TOLERANCE") "5%")
        (field (name "DB_VOLTAGE") "16V")
        (field (name "DB_MANUFACTURER_PART") "KEMET    C0603C474J4RAC")
        (field (name "DB_APPROVED_BY") "ISHIDDEN=T")
      )
      (libsource (lib "Database_Libs1") (part "C"))
    )
    (comp (ref "C252")
      (value "C")
      (footprint "SMD_0603_CAPC1608X95N")
      (fields
        (field (name "DB_PART_NUMBER") "CAP000028169")
        (field (name "DB_VALUE") "470nF")
        (field (name "DB_TOLERANCE") "5%")
        (field (name "DB_VOLTAGE") "16V")
        (field (name "DB_MANUFACTURER_PART") "KEMET    C0603C474J4RAC")
        (field (name "DB_APPROVED_BY") "ISHIDDEN=T")
      )
      (libsource (lib "Database_Libs1") (part "C"))
    )
    (comp (ref "C253")
      (value "C")
      (footprint "SMD_0603_CAPC1608X95N")
      (fields
        (field (name "DB_PART_NUMBER") "CAP000028169")
        (field (name "DB_VALUE") "470nF")
        (field (name "DB_TOLERANCE") "5%")
        (field (name "DB_VOLTAGE") "16V")
        (field (name "DB_MANUFACTURER_PART") "KEMET    C0603C474J4RAC")
        (field (name "DB_APPROVED_BY") "ISHIDDEN=T")
      )
      (libsource (lib "Database_Libs1") (part "C"))
    )
    (comp (ref "C254")
      (value "C")
      (footprint "SMD_0603_CAPC1608X95N")
      (fields
        (field (name "DB_PART_NUMBER") "CAP000028169")
        (field (name "DB_VALUE") "470nF")
        (field (name "DB_TOLERANCE") "5%")
        (field (name "DB_VOLTAGE") "16V")
        (field (name "DB_MANUFACTURER_PART") "KEMET    C0603C474J4RAC")
        (field (name "DB_APPROVED_BY") "ISHIDDEN=T")
      )
      (libsource (lib "Database_Libs1") (part "C"))
    )
    (comp (ref "C255")
      (value "C")
      (footprint "SMD_0603_CAPC1608X95N")
      (fields
        (field (name "DB_PART_NUMBER") "CAP000028169")
        (field (name "DB_VALUE") "470nF")
        (field (name "DB_TOLERANCE") "5%")
        (field (name "DB_VOLTAGE") "16V")
        (field (name "DB_MANUFACTURER_PART") "KEMET    C0603C474J4RAC")
        (field (name "DB_APPROVED_BY") "ISHIDDEN=T")
      )
      (libsource (lib "Database_Libs1") (part "C"))
    )
    (comp (ref "C256")
      (value "C")
      (footprint "SMD_0603_CAPC1608X95N")
      (fields
        (field (name "DB_PART_NUMBER") "CAP000028169")
        (field (name "DB_VALUE") "470nF")
        (field (name "DB_TOLERANCE") "5%")
        (field (name "DB_VOLTAGE") "16V")
        (field (name "DB_MANUFACTURER_PART") "KEMET    C0603C474J4RAC")
        (field (name "DB_APPROVED_BY") "ISHIDDEN=T")
      )
      (libsource (lib "Database_Libs1") (part "C"))
    )
    (comp (ref "C257")
      (value "C")
      (footprint "SMD_0603_CAPC1608X95N")
      (fields
        (field (name "DB_PART_NUMBER") "CAP000028169")
        (field (name "DB_VALUE") "470nF")
        (field (name "DB_TOLERANCE") "5%")
        (field (name "DB_VOLTAGE") "16V")
        (field (name "DB_MANUFACTURER_PART") "KEMET    C0603C474J4RAC")
        (field (name "DB_APPROVED_BY") "ISHIDDEN=T")
      )
      (libsource (lib "Database_Libs1") (part "C"))
    )
    (comp (ref "C258")
      (value "C")
      (footprint "SMD_0603_CAPC1608X95N")
      (fields
        (field (name "DB_PART_NUMBER") "CAP000028169")
        (field (name "DB_VALUE") "470nF")
        (field (name "DB_TOLERANCE") "5%")
        (field (name "DB_VOLTAGE") "16V")
        (field (name "DB_MANUFACTURER_PART") "KEMET    C0603C474J4RAC")
        (field (name "DB_APPROVED_BY") "ISHIDDEN=T")
      )
      (libsource (lib "Database_Libs1") (part "C"))
    )
    (comp (ref "C259")
      (value "C")
      (footprint "SMD_0805_CAPC2012X145N")
      (fields
        (field (name "DB_PART_NUMBER") "CAP000043686")
        (field (name "DB_VALUE") "22uF")
        (field (name "DB_TOLERANCE") "20%")
        (field (name "DB_VOLTAGE") "6.3V")
        (field (name "DB_MANUFACTURER_PART") "KEMET    C0805C226M9PAC")
        (field (name "DB_APPROVED_BY") "ISHIDDEN=T")
      )
      (libsource (lib "Database_Libs1") (part "C"))
    )
    (comp (ref "C260")
      (value "C")
      (footprint "SMD_0603_CAPC1608X95N")
      (fields
        (field (name "DB_PART_NUMBER") "CAP000027136")
        (field (name "DB_VALUE") "100nF")
        (field (name "DB_TOLERANCE") "5%")
        (field (name "DB_VOLTAGE") "50V")
        (field (name "DB_MANUFACTURER_PART") "KEMET    C0603C104J5RAC")
        (field (name "DB_APPROVED_BY") "ISHIDDEN=T")
      )
      (libsource (lib "Database_Libs1") (part "C"))
    )
    (comp (ref "C261")
      (value "C")
      (footprint "SMD_0603_CAPC1608X95N")
      (fields
        (field (name "DB_PART_NUMBER") "CAP000027136")
        (field (name "DB_VALUE") "100nF")
        (field (name "DB_TOLERANCE") "5%")
        (field (name "DB_VOLTAGE") "50V")
        (field (name "DB_MANUFACTURER_PART") "KEMET    C0603C104J5RAC")
        (field (name "DB_APPROVED_BY") "ISHIDDEN=T")
      )
      (libsource (lib "Database_Libs1") (part "C"))
    )
    (comp (ref "C262")
      (value "C")
      (footprint "SMD_0603_CAPC1608X95N")
      (fields
        (field (name "DB_PART_NUMBER") "CAP000028169")
        (field (name "DB_VALUE") "470nF")
        (field (name "DB_TOLERANCE") "5%")
        (field (name "DB_VOLTAGE") "16V")
        (field (name "DB_MANUFACTURER_PART") "KEMET    C0603C474J4RAC")
        (field (name "DB_APPROVED_BY") "ISHIDDEN=T")
      )
      (libsource (lib "Database_Libs1") (part "C"))
    )
    (comp (ref "C263")
      (value "C")
      (footprint "SMD_0603_CAPC1608X95N")
      (fields
        (field (name "DB_PART_NUMBER") "CAP000028169")
        (field (name "DB_VALUE") "470nF")
        (field (name "DB_TOLERANCE") "5%")
        (field (name "DB_VOLTAGE") "16V")
        (field (name "DB_MANUFACTURER_PART") "KEMET    C0603C474J4RAC")
        (field (name "DB_APPROVED_BY") "ISHIDDEN=T")
      )
      (libsource (lib "Database_Libs1") (part "C"))
    )
    (comp (ref "C264")
      (value "C")
      (footprint "SMD_0603_CAPC1608X95N")
      (fields
        (field (name "DB_PART_NUMBER") "CAP000028169")
        (field (name "DB_VALUE") "470nF")
        (field (name "DB_TOLERANCE") "5%")
        (field (name "DB_VOLTAGE") "16V")
        (field (name "DB_MANUFACTURER_PART") "KEMET    C0603C474J4RAC")
        (field (name "DB_APPROVED_BY") "ISHIDDEN=T")
      )
      (libsource (lib "Database_Libs1") (part "C"))
    )
    (comp (ref "C265")
      (value "C")
      (footprint "SMD_0603_CAPC1608X95N")
      (fields
        (field (name "DB_PART_NUMBER") "CAP000028169")
        (field (name "DB_VALUE") "470nF")
        (field (name "DB_TOLERANCE") "5%")
        (field (name "DB_VOLTAGE") "16V")
        (field (name "DB_MANUFACTURER_PART") "KEMET    C0603C474J4RAC")
        (field (name "DB_APPROVED_BY") "ISHIDDEN=T")
      )
      (libsource (lib "Database_Libs1") (part "C"))
    )
    (comp (ref "C266")
      (value "C")
      (footprint "SMD_0603_CAPC1608X95N")
      (fields
        (field (name "DB_PART_NUMBER") "CAP000028169")
        (field (name "DB_VALUE") "470nF")
        (field (name "DB_TOLERANCE") "5%")
        (field (name "DB_VOLTAGE") "16V")
        (field (name "DB_MANUFACTURER_PART") "KEMET    C0603C474J4RAC")
        (field (name "DB_APPROVED_BY") "ISHIDDEN=T")
      )
      (libsource (lib "Database_Libs1") (part "C"))
    )
    (comp (ref "C267")
      (value "C")
      (footprint "SMD_0603_CAPC1608X95N")
      (fields
        (field (name "DB_PART_NUMBER") "CAP000028169")
        (field (name "DB_VALUE") "470nF")
        (field (name "DB_TOLERANCE") "5%")
        (field (name "DB_VOLTAGE") "16V")
        (field (name "DB_MANUFACTURER_PART") "KEMET    C0603C474J4RAC")
        (field (name "DB_APPROVED_BY") "ISHIDDEN=T")
      )
      (libsource (lib "Database_Libs1") (part "C"))
    )
    (comp (ref "C268")
      (value "C")
      (footprint "SMD_0603_CAPC1608X95N")
      (fields
        (field (name "DB_PART_NUMBER") "CAP000028169")
        (field (name "DB_VALUE") "470nF")
        (field (name "DB_TOLERANCE") "5%")
        (field (name "DB_VOLTAGE") "16V")
        (field (name "DB_MANUFACTURER_PART") "KEMET    C0603C474J4RAC")
        (field (name "DB_APPROVED_BY") "ISHIDDEN=T")
      )
      (libsource (lib "Database_Libs1") (part "C"))
    )
    (comp (ref "C269")
      (value "C")
      (footprint "SMD_0603_CAPC1608X95N")
      (fields
        (field (name "DB_PART_NUMBER") "CAP000028169")
        (field (name "DB_VALUE") "470nF")
        (field (name "DB_TOLERANCE") "5%")
        (field (name "DB_VOLTAGE") "16V")
        (field (name "DB_MANUFACTURER_PART") "KEMET    C0603C474J4RAC")
        (field (name "DB_APPROVED_BY") "ISHIDDEN=T")
      )
      (libsource (lib "Database_Libs1") (part "C"))
    )
    (comp (ref "C270")
      (value "C")
      (footprint "SMD_0603_CAPC1608X95N")
      (fields
        (field (name "DB_PART_NUMBER") "CAP000028169")
        (field (name "DB_VALUE") "470nF")
        (field (name "DB_TOLERANCE") "5%")
        (field (name "DB_VOLTAGE") "16V")
        (field (name "DB_MANUFACTURER_PART") "KEMET    C0603C474J4RAC")
        (field (name "DB_APPROVED_BY") "ISHIDDEN=T")
      )
      (libsource (lib "Database_Libs1") (part "C"))
    )
    (comp (ref "C271")
      (value "C")
      (footprint "SMD_0603_CAPC1608X95N")
      (fields
        (field (name "DB_PART_NUMBER") "CAP000028169")
        (field (name "DB_VALUE") "470nF")
        (field (name "DB_TOLERANCE") "5%")
        (field (name "DB_VOLTAGE") "16V")
        (field (name "DB_MANUFACTURER_PART") "KEMET    C0603C474J4RAC")
        (field (name "DB_APPROVED_BY") "ISHIDDEN=T")
      )
      (libsource (lib "Database_Libs1") (part "C"))
    )
    (comp (ref "C272")
      (value "C")
      (footprint "SMD_0603_CAPC1608X95N")
      (fields
        (field (name "DB_PART_NUMBER") "CAP000028169")
        (field (name "DB_VALUE") "470nF")
        (field (name "DB_TOLERANCE") "5%")
        (field (name "DB_VOLTAGE") "16V")
        (field (name "DB_MANUFACTURER_PART") "KEMET    C0603C474J4RAC")
        (field (name "DB_APPROVED_BY") "ISHIDDEN=T")
      )
      (libsource (lib "Database_Libs1") (part "C"))
    )
    (comp (ref "C273")
      (value "C")
      (footprint "SMD_0603_CAPC1608X95N")
      (fields
        (field (name "DB_PART_NUMBER") "CAP000028169")
        (field (name "DB_VALUE") "470nF")
        (field (name "DB_TOLERANCE") "5%")
        (field (name "DB_VOLTAGE") "16V")
        (field (name "DB_MANUFACTURER_PART") "KEMET    C0603C474J4RAC")
        (field (name "DB_APPROVED_BY") "ISHIDDEN=T")
      )
      (libsource (lib "Database_Libs1") (part "C"))
    )
    (comp (ref "C274")
      (value "C")
      (footprint "SMD_0805_CAPC2012X145N")
      (fields
        (field (name "DB_PART_NUMBER") "CAP000043686")
        (field (name "DB_VALUE") "22uF")
        (field (name "DB_TOLERANCE") "20%")
        (field (name "DB_VOLTAGE") "6.3V")
        (field (name "DB_MANUFACTURER_PART") "KEMET    C0805C226M9PAC")
        (field (name "DB_APPROVED_BY") "ISHIDDEN=T")
      )
      (libsource (lib "Database_Libs1") (part "C"))
    )
    (comp (ref "C275")
      (value "C")
      (footprint "SMD_0805_CAPC2012X145N")
      (fields
        (field (name "DB_PART_NUMBER") "CAP000043636")
        (field (name "DB_VALUE") "10uF")
        (field (name "DB_TOLERANCE") "10%")
        (field (name "DB_VOLTAGE") "16V")
        (field (name "DB_MANUFACTURER_PART") "KEMET    C0805C106K4PAC")
        (field (name "DB_APPROVED_BY") "ISHIDDEN=T")
      )
      (libsource (lib "Database_Libs1") (part "C"))
    )
    (comp (ref "C276")
      (value "C")
      (footprint "SMD_0603_CAPC1608X95N")
      (fields
        (field (name "DB_PART_NUMBER") "CAP000028169")
        (field (name "DB_VALUE") "470nF")
        (field (name "DB_TOLERANCE") "5%")
        (field (name "DB_VOLTAGE") "16V")
        (field (name "DB_MANUFACTURER_PART") "KEMET    C0603C474J4RAC")
        (field (name "DB_APPROVED_BY") "ISHIDDEN=T")
      )
      (libsource (lib "Database_Libs1") (part "C"))
    )
    (comp (ref "C277")
      (value "C")
      (footprint "SMD_0603_CAPC1608X95N")
      (fields
        (field (name "DB_PART_NUMBER") "CAP000028169")
        (field (name "DB_VALUE") "470nF")
        (field (name "DB_TOLERANCE") "5%")
        (field (name "DB_VOLTAGE") "16V")
        (field (name "DB_MANUFACTURER_PART") "KEMET    C0603C474J4RAC")
        (field (name "DB_APPROVED_BY") "ISHIDDEN=T")
      )
      (libsource (lib "Database_Libs1") (part "C"))
    )
    (comp (ref "C278")
      (value "C")
      (footprint "SMD_0603_CAPC1608X95N")
      (fields
        (field (name "DB_PART_NUMBER") "CAP000028169")
        (field (name "DB_VALUE") "470nF")
        (field (name "DB_TOLERANCE") "5%")
        (field (name "DB_VOLTAGE") "16V")
        (field (name "DB_MANUFACTURER_PART") "KEMET    C0603C474J4RAC")
        (field (name "DB_APPROVED_BY") "ISHIDDEN=T")
      )
      (libsource (lib "Database_Libs1") (part "C"))
    )
    (comp (ref "C279")
      (value "C")
      (footprint "SMD_0603_CAPC1608X95N")
      (fields
        (field (name "DB_PART_NUMBER") "CAP000028169")
        (field (name "DB_VALUE") "470nF")
        (field (name "DB_TOLERANCE") "5%")
        (field (name "DB_VOLTAGE") "16V")
        (field (name "DB_MANUFACTURER_PART") "KEMET    C0603C474J4RAC")
        (field (name "DB_APPROVED_BY") "ISHIDDEN=T")
      )
      (libsource (lib "Database_Libs1") (part "C"))
    )
    (comp (ref "C280")
      (value "C")
      (footprint "SMD_0603_CAPC1608X95N")
      (fields
        (field (name "DB_PART_NUMBER") "CAP000028169")
        (field (name "DB_VALUE") "470nF")
        (field (name "DB_TOLERANCE") "5%")
        (field (name "DB_VOLTAGE") "16V")
        (field (name "DB_MANUFACTURER_PART") "KEMET    C0603C474J4RAC")
        (field (name "DB_APPROVED_BY") "ISHIDDEN=T")
      )
      (libsource (lib "Database_Libs1") (part "C"))
    )
    (comp (ref "C281")
      (value "C")
      (footprint "SMD_0603_CAPC1608X95N")
      (fields
        (field (name "DB_PART_NUMBER") "CAP000028169")
        (field (name "DB_VALUE") "470nF")
        (field (name "DB_TOLERANCE") "5%")
        (field (name "DB_VOLTAGE") "16V")
        (field (name "DB_MANUFACTURER_PART") "KEMET    C0603C474J4RAC")
        (field (name "DB_APPROVED_BY") "ISHIDDEN=T")
      )
      (libsource (lib "Database_Libs1") (part "C"))
    )
    (comp (ref "C282")
      (value "C")
      (footprint "SMD_0603_CAPC1608X95N")
      (fields
        (field (name "DB_PART_NUMBER") "CAP000028169")
        (field (name "DB_VALUE") "470nF")
        (field (name "DB_TOLERANCE") "5%")
        (field (name "DB_VOLTAGE") "16V")
        (field (name "DB_MANUFACTURER_PART") "KEMET    C0603C474J4RAC")
        (field (name "DB_APPROVED_BY") "ISHIDDEN=T")
      )
      (libsource (lib "Database_Libs1") (part "C"))
    )
    (comp (ref "C283")
      (value "C")
      (footprint "SMD_0603_CAPC1608X95N")
      (fields
        (field (name "DB_PART_NUMBER") "CAP000028169")
        (field (name "DB_VALUE") "470nF")
        (field (name "DB_TOLERANCE") "5%")
        (field (name "DB_VOLTAGE") "16V")
        (field (name "DB_MANUFACTURER_PART") "KEMET    C0603C474J4RAC")
        (field (name "DB_APPROVED_BY") "ISHIDDEN=T")
      )
      (libsource (lib "Database_Libs1") (part "C"))
    )
    (comp (ref "C284")
      (value "C")
      (footprint "SMD_0603_CAPC1608X95N")
      (fields
        (field (name "DB_PART_NUMBER") "CAP000028169")
        (field (name "DB_VALUE") "470nF")
        (field (name "DB_TOLERANCE") "5%")
        (field (name "DB_VOLTAGE") "16V")
        (field (name "DB_MANUFACTURER_PART") "KEMET    C0603C474J4RAC")
        (field (name "DB_APPROVED_BY") "ISHIDDEN=T")
      )
      (libsource (lib "Database_Libs1") (part "C"))
    )
    (comp (ref "C285")
      (value "C")
      (footprint "SMD_0603_CAPC1608X95N")
      (fields
        (field (name "DB_PART_NUMBER") "CAP000028169")
        (field (name "DB_VALUE") "470nF")
        (field (name "DB_TOLERANCE") "5%")
        (field (name "DB_VOLTAGE") "16V")
        (field (name "DB_MANUFACTURER_PART") "KEMET    C0603C474J4RAC")
        (field (name "DB_APPROVED_BY") "ISHIDDEN=T")
      )
      (libsource (lib "Database_Libs1") (part "C"))
    )
    (comp (ref "C286")
      (value "C")
      (footprint "SMD_0603_CAPC1608X95N")
      (fields
        (field (name "DB_PART_NUMBER") "CAP000028169")
        (field (name "DB_VALUE") "470nF")
        (field (name "DB_TOLERANCE") "5%")
        (field (name "DB_VOLTAGE") "16V")
        (field (name "DB_MANUFACTURER_PART") "KEMET    C0603C474J4RAC")
        (field (name "DB_APPROVED_BY") "ISHIDDEN=T")
      )
      (libsource (lib "Database_Libs1") (part "C"))
    )
    (comp (ref "C287")
      (value "C")
      (footprint "SMD_0603_CAPC1608X95N")
      (fields
        (field (name "DB_PART_NUMBER") "CAP000028169")
        (field (name "DB_VALUE") "470nF")
        (field (name "DB_TOLERANCE") "5%")
        (field (name "DB_VOLTAGE") "16V")
        (field (name "DB_MANUFACTURER_PART") "KEMET    C0603C474J4RAC")
        (field (name "DB_APPROVED_BY") "ISHIDDEN=T")
      )
      (libsource (lib "Database_Libs1") (part "C"))
    )
    (comp (ref "C288")
      (value "C")
      (footprint "SMD_0603_CAPC1608X95N")
      (fields
        (field (name "DB_PART_NUMBER") "CAP000028169")
        (field (name "DB_VALUE") "470nF")
        (field (name "DB_TOLERANCE") "5%")
        (field (name "DB_VOLTAGE") "16V")
        (field (name "DB_MANUFACTURER_PART") "KEMET    C0603C474J4RAC")
        (field (name "DB_APPROVED_BY") "ISHIDDEN=T")
      )
      (libsource (lib "Database_Libs1") (part "C"))
    )
    (comp (ref "C289")
      (value "C")
      (footprint "SMD_0603_CAPC1608X95N")
      (fields
        (field (name "DB_PART_NUMBER") "CAP000028169")
        (field (name "DB_VALUE") "470nF")
        (field (name "DB_TOLERANCE") "5%")
        (field (name "DB_VOLTAGE") "16V")
        (field (name "DB_MANUFACTURER_PART") "KEMET    C0603C474J4RAC")
        (field (name "DB_APPROVED_BY") "ISHIDDEN=T")
      )
      (libsource (lib "Database_Libs1") (part "C"))
    )
    (comp (ref "C290")
      (value "C")
      (footprint "SMD_0603_CAPC1608X95N")
      (fields
        (field (name "DB_PART_NUMBER") "CAP000028169")
        (field (name "DB_VALUE") "470nF")
        (field (name "DB_TOLERANCE") "5%")
        (field (name "DB_VOLTAGE") "16V")
        (field (name "DB_MANUFACTURER_PART") "KEMET    C0603C474J4RAC")
        (field (name "DB_APPROVED_BY") "ISHIDDEN=T")
      )
      (libsource (lib "Database_Libs1") (part "C"))
    )
    (comp (ref "C291")
      (value "C")
      (footprint "SMD_0603_CAPC1608X95N")
      (fields
        (field (name "DB_PART_NUMBER") "CAP000028169")
        (field (name "DB_VALUE") "470nF")
        (field (name "DB_TOLERANCE") "5%")
        (field (name "DB_VOLTAGE") "16V")
        (field (name "DB_MANUFACTURER_PART") "KEMET    C0603C474J4RAC")
        (field (name "DB_APPROVED_BY") "ISHIDDEN=T")
      )
      (libsource (lib "Database_Libs1") (part "C"))
    )
    (comp (ref "C324")
      (value "C")
      (footprint "SMD_0603_CAPC1608X95N")
      (fields
        (field (name "DB_PART_NUMBER") "CAP000028169")
        (field (name "DB_VALUE") "470nF")
        (field (name "DB_TOLERANCE") "5%")
        (field (name "DB_VOLTAGE") "16V")
        (field (name "DB_MANUFACTURER_PART") "KEMET    C0603C474J4RAC")
        (field (name "DB_APPROVED_BY") "ISHIDDEN=T")
      )
      (libsource (lib "Database_Libs1") (part "C"))
    )
    (comp (ref "C325")
      (value "C")
      (footprint "SMD_0603_CAPC1608X95N")
      (fields
        (field (name "DB_PART_NUMBER") "CAP000028169")
        (field (name "DB_VALUE") "470nF")
        (field (name "DB_TOLERANCE") "5%")
        (field (name "DB_VOLTAGE") "16V")
        (field (name "DB_MANUFACTURER_PART") "KEMET    C0603C474J4RAC")
        (field (name "DB_APPROVED_BY") "ISHIDDEN=T")
      )
      (libsource (lib "Database_Libs1") (part "C"))
    )
    (comp (ref "C326")
      (value "C")
      (footprint "SMD_0603_CAPC1608X95N")
      (fields
        (field (name "DB_PART_NUMBER") "CAP000028169")
        (field (name "DB_VALUE") "470nF")
        (field (name "DB_TOLERANCE") "5%")
        (field (name "DB_VOLTAGE") "16V")
        (field (name "DB_MANUFACTURER_PART") "KEMET    C0603C474J4RAC")
        (field (name "DB_APPROVED_BY") "ISHIDDEN=T")
      )
      (libsource (lib "Database_Libs1") (part "C"))
    )
    (comp (ref "C327")
      (value "C")
      (footprint "SMD_0603_CAPC1608X95N")
      (fields
        (field (name "DB_PART_NUMBER") "CAP000028169")
        (field (name "DB_VALUE") "470nF")
        (field (name "DB_TOLERANCE") "5%")
        (field (name "DB_VOLTAGE") "16V")
        (field (name "DB_MANUFACTURER_PART") "KEMET    C0603C474J4RAC")
        (field (name "DB_APPROVED_BY") "ISHIDDEN=T")
      )
      (libsource (lib "Database_Libs1") (part "C"))
    )
    (comp (ref "C328")
      (value "C")
      (footprint "SMD_0603_CAPC1608X95N")
      (fields
        (field (name "DB_PART_NUMBER") "CAP000028169")
        (field (name "DB_VALUE") "470nF")
        (field (name "DB_TOLERANCE") "5%")
        (field (name "DB_VOLTAGE") "16V")
        (field (name "DB_MANUFACTURER_PART") "KEMET    C0603C474J4RAC")
        (field (name "DB_APPROVED_BY") "ISHIDDEN=T")
      )
      (libsource (lib "Database_Libs1") (part "C"))
    )
    (comp (ref "C329")
      (value "C")
      (footprint "SMD_0603_CAPC1608X95N")
      (fields
        (field (name "DB_PART_NUMBER") "CAP000028169")
        (field (name "DB_VALUE") "470nF")
        (field (name "DB_TOLERANCE") "5%")
        (field (name "DB_VOLTAGE") "16V")
        (field (name "DB_MANUFACTURER_PART") "KEMET    C0603C474J4RAC")
        (field (name "DB_APPROVED_BY") "ISHIDDEN=T")
      )
      (libsource (lib "Database_Libs1") (part "C"))
    )
    (comp (ref "C330")
      (value "C")
      (footprint "SMD_0603_CAPC1608X95N")
      (fields
        (field (name "DB_PART_NUMBER") "CAP000028169")
        (field (name "DB_VALUE") "470nF")
        (field (name "DB_TOLERANCE") "5%")
        (field (name "DB_VOLTAGE") "16V")
        (field (name "DB_MANUFACTURER_PART") "KEMET    C0603C474J4RAC")
        (field (name "DB_APPROVED_BY") "ISHIDDEN=T")
      )
      (libsource (lib "Database_Libs1") (part "C"))
    )
    (comp (ref "C331")
      (value "C")
      (footprint "SMD_0603_CAPC1608X95N")
      (fields
        (field (name "DB_PART_NUMBER") "CAP000028169")
        (field (name "DB_VALUE") "470nF")
        (field (name "DB_TOLERANCE") "5%")
        (field (name "DB_VOLTAGE") "16V")
        (field (name "DB_MANUFACTURER_PART") "KEMET    C0603C474J4RAC")
        (field (name "DB_APPROVED_BY") "ISHIDDEN=T")
      )
      (libsource (lib "Database_Libs1") (part "C"))
    )
    (comp (ref "C332")
      (value "C")
      (footprint "SMD_0603_CAPC1608X95N")
      (fields
        (field (name "DB_PART_NUMBER") "CAP000028169")
        (field (name "DB_VALUE") "470nF")
        (field (name "DB_TOLERANCE") "5%")
        (field (name "DB_VOLTAGE") "16V")
        (field (name "DB_MANUFACTURER_PART") "KEMET    C0603C474J4RAC")
        (field (name "DB_APPROVED_BY") "ISHIDDEN=T")
      )
      (libsource (lib "Database_Libs1") (part "C"))
    )
    (comp (ref "C333")
      (value "C")
      (footprint "SMD_0603_CAPC1608X95N")
      (fields
        (field (name "DB_PART_NUMBER") "CAP000028169")
        (field (name "DB_VALUE") "470nF")
        (field (name "DB_TOLERANCE") "5%")
        (field (name "DB_VOLTAGE") "16V")
        (field (name "DB_MANUFACTURER_PART") "KEMET    C0603C474J4RAC")
        (field (name "DB_APPROVED_BY") "ISHIDDEN=T")
      )
      (libsource (lib "Database_Libs1") (part "C"))
    )
    (comp (ref "C334")
      (value "C")
      (footprint "SMD_0603_CAPC1608X95N")
      (fields
        (field (name "DB_PART_NUMBER") "CAP000028169")
        (field (name "DB_VALUE") "470nF")
        (field (name "DB_TOLERANCE") "5%")
        (field (name "DB_VOLTAGE") "16V")
        (field (name "DB_MANUFACTURER_PART") "KEMET    C0603C474J4RAC")
        (field (name "DB_APPROVED_BY") "ISHIDDEN=T")
      )
      (libsource (lib "Database_Libs1") (part "C"))
    )
    (comp (ref "C335")
      (value "C")
      (footprint "SMD_0603_CAPC1608X95N")
      (fields
        (field (name "DB_PART_NUMBER") "CAP000028169")
        (field (name "DB_VALUE") "470nF")
        (field (name "DB_TOLERANCE") "5%")
        (field (name "DB_VOLTAGE") "16V")
        (field (name "DB_MANUFACTURER_PART") "KEMET    C0603C474J4RAC")
        (field (name "DB_APPROVED_BY") "ISHIDDEN=T")
      )
      (libsource (lib "Database_Libs1") (part "C"))
    )
    (comp (ref "C336")
      (value "C")
      (footprint "SMD_0603_CAPC1608X95N")
      (fields
        (field (name "DB_PART_NUMBER") "CAP000028169")
        (field (name "DB_VALUE") "470nF")
        (field (name "DB_TOLERANCE") "5%")
        (field (name "DB_VOLTAGE") "16V")
        (field (name "DB_MANUFACTURER_PART") "KEMET    C0603C474J4RAC")
        (field (name "DB_APPROVED_BY") "ISHIDDEN=T")
      )
      (libsource (lib "Database_Libs1") (part "C"))
    )
    (comp (ref "C337")
      (value "C")
      (footprint "SMD_0603_CAPC1608X95N")
      (fields
        (field (name "DB_PART_NUMBER") "CAP000028169")
        (field (name "DB_VALUE") "470nF")
        (field (name "DB_TOLERANCE") "5%")
        (field (name "DB_VOLTAGE") "16V")
        (field (name "DB_MANUFACTURER_PART") "KEMET    C0603C474J4RAC")
        (field (name "DB_APPROVED_BY") "ISHIDDEN=T")
      )
      (libsource (lib "Database_Libs1") (part "C"))
    )
    (comp (ref "C338")
      (value "C")
      (footprint "SMD_0603_CAPC1608X95N")
      (fields
        (field (name "DB_PART_NUMBER") "CAP000028169")
        (field (name "DB_VALUE") "470nF")
        (field (name "DB_TOLERANCE") "5%")
        (field (name "DB_VOLTAGE") "16V")
        (field (name "DB_MANUFACTURER_PART") "KEMET    C0603C474J4RAC")
        (field (name "DB_APPROVED_BY") "ISHIDDEN=T")
      )
      (libsource (lib "Database_Libs1") (part "C"))
    )
    (comp (ref "C339")
      (value "C")
      (footprint "SMD_0603_CAPC1608X95N")
      (fields
        (field (name "DB_PART_NUMBER") "CAP000028169")
        (field (name "DB_VALUE") "470nF")
        (field (name "DB_TOLERANCE") "5%")
        (field (name "DB_VOLTAGE") "16V")
        (field (name "DB_MANUFACTURER_PART") "KEMET    C0603C474J4RAC")
        (field (name "DB_APPROVED_BY") "ISHIDDEN=T")
      )
      (libsource (lib "Database_Libs1") (part "C"))
    )
    (comp (ref "C340")
      (value "C")
      (footprint "SMD_0603_CAPC1608X95N")
      (fields
        (field (name "DB_PART_NUMBER") "CAP000028169")
        (field (name "DB_VALUE") "470nF")
        (field (name "DB_TOLERANCE") "5%")
        (field (name "DB_VOLTAGE") "16V")
        (field (name "DB_MANUFACTURER_PART") "KEMET    C0603C474J4RAC")
        (field (name "DB_APPROVED_BY") "ISHIDDEN=T")
      )
      (libsource (lib "Database_Libs1") (part "C"))
    )
    (comp (ref "C341")
      (value "C")
      (footprint "SMD_0603_CAPC1608X95N")
      (fields
        (field (name "DB_PART_NUMBER") "CAP000028169")
        (field (name "DB_VALUE") "470nF")
        (field (name "DB_TOLERANCE") "5%")
        (field (name "DB_VOLTAGE") "16V")
        (field (name "DB_MANUFACTURER_PART") "KEMET    C0603C474J4RAC")
        (field (name "DB_APPROVED_BY") "ISHIDDEN=T")
      )
      (libsource (lib "Database_Libs1") (part "C"))
    )
    (comp (ref "C342")
      (value "C")
      (footprint "SMD_0603_CAPC1608X95N")
      (fields
        (field (name "DB_PART_NUMBER") "CAP000028169")
        (field (name "DB_VALUE") "470nF")
        (field (name "DB_TOLERANCE") "5%")
        (field (name "DB_VOLTAGE") "16V")
        (field (name "DB_MANUFACTURER_PART") "KEMET    C0603C474J4RAC")
        (field (name "DB_APPROVED_BY") "ISHIDDEN=T")
      )
      (libsource (lib "Database_Libs1") (part "C"))
    )
    (comp (ref "C343")
      (value "C")
      (footprint "SMD_0603_CAPC1608X95N")
      (fields
        (field (name "DB_PART_NUMBER") "CAP000028169")
        (field (name "DB_VALUE") "470nF")
        (field (name "DB_TOLERANCE") "5%")
        (field (name "DB_VOLTAGE") "16V")
        (field (name "DB_MANUFACTURER_PART") "KEMET    C0603C474J4RAC")
        (field (name "DB_APPROVED_BY") "ISHIDDEN=T")
      )
      (libsource (lib "Database_Libs1") (part "C"))
    )
    (comp (ref "C344")
      (value "C")
      (footprint "SMD_0603_CAPC1608X95N")
      (fields
        (field (name "DB_PART_NUMBER") "CAP000028169")
        (field (name "DB_VALUE") "470nF")
        (field (name "DB_TOLERANCE") "5%")
        (field (name "DB_VOLTAGE") "16V")
        (field (name "DB_MANUFACTURER_PART") "KEMET    C0603C474J4RAC")
        (field (name "DB_APPROVED_BY") "ISHIDDEN=T")
      )
      (libsource (lib "Database_Libs1") (part "C"))
    )
    (comp (ref "C345")
      (value "C")
      (footprint "SMD_0603_CAPC1608X95N")
      (fields
        (field (name "DB_PART_NUMBER") "CAP000028169")
        (field (name "DB_VALUE") "470nF")
        (field (name "DB_TOLERANCE") "5%")
        (field (name "DB_VOLTAGE") "16V")
        (field (name "DB_MANUFACTURER_PART") "KEMET    C0603C474J4RAC")
        (field (name "DB_APPROVED_BY") "ISHIDDEN=T")
      )
      (libsource (lib "Database_Libs1") (part "C"))
    )
    (comp (ref "C346")
      (value "C")
      (footprint "SMD_0603_CAPC1608X95N")
      (fields
        (field (name "DB_PART_NUMBER") "CAP000028169")
        (field (name "DB_VALUE") "470nF")
        (field (name "DB_TOLERANCE") "5%")
        (field (name "DB_VOLTAGE") "16V")
        (field (name "DB_MANUFACTURER_PART") "KEMET    C0603C474J4RAC")
        (field (name "DB_APPROVED_BY") "ISHIDDEN=T")
      )
      (libsource (lib "Database_Libs1") (part "C"))
    )
    (comp (ref "C347")
      (value "C")
      (footprint "SMD_0603_CAPC1608X95N")
      (fields
        (field (name "DB_PART_NUMBER") "CAP000028169")
        (field (name "DB_VALUE") "470nF")
        (field (name "DB_TOLERANCE") "5%")
        (field (name "DB_VOLTAGE") "16V")
        (field (name "DB_MANUFACTURER_PART") "KEMET    C0603C474J4RAC")
        (field (name "DB_APPROVED_BY") "ISHIDDEN=T")
      )
      (libsource (lib "Database_Libs1") (part "C"))
    )
    (comp (ref "C348")
      (value "C")
      (footprint "SMD_0603_CAPC1608X95N")
      (fields
        (field (name "DB_PART_NUMBER") "CAP000028169")
        (field (name "DB_VALUE") "470nF")
        (field (name "DB_TOLERANCE") "5%")
        (field (name "DB_VOLTAGE") "16V")
        (field (name "DB_MANUFACTURER_PART") "KEMET    C0603C474J4RAC")
        (field (name "DB_APPROVED_BY") "ISHIDDEN=T")
      )
      (libsource (lib "Database_Libs1") (part "C"))
    )
    (comp (ref "C349")
      (value "C")
      (footprint "SMD_0603_CAPC1608X95N")
      (fields
        (field (name "DB_PART_NUMBER") "CAP000028169")
        (field (name "DB_VALUE") "470nF")
        (field (name "DB_TOLERANCE") "5%")
        (field (name "DB_VOLTAGE") "16V")
        (field (name "DB_MANUFACTURER_PART") "KEMET    C0603C474J4RAC")
        (field (name "DB_APPROVED_BY") "ISHIDDEN=T")
      )
      (libsource (lib "Database_Libs1") (part "C"))
    )
    (comp (ref "C350")
      (value "C")
      (footprint "SMD_0603_CAPC1608X95N")
      (fields
        (field (name "DB_PART_NUMBER") "CAP000028169")
        (field (name "DB_VALUE") "470nF")
        (field (name "DB_TOLERANCE") "5%")
        (field (name "DB_VOLTAGE") "16V")
        (field (name "DB_MANUFACTURER_PART") "KEMET    C0603C474J4RAC")
        (field (name "DB_APPROVED_BY") "ISHIDDEN=T")
      )
      (libsource (lib "Database_Libs1") (part "C"))
    )
    (comp (ref "C351")
      (value "C")
      (footprint "SMD_0603_CAPC1608X95N")
      (fields
        (field (name "DB_PART_NUMBER") "CAP000028169")
        (field (name "DB_VALUE") "470nF")
        (field (name "DB_TOLERANCE") "5%")
        (field (name "DB_VOLTAGE") "16V")
        (field (name "DB_MANUFACTURER_PART") "KEMET    C0603C474J4RAC")
        (field (name "DB_APPROVED_BY") "ISHIDDEN=T")
      )
      (libsource (lib "Database_Libs1") (part "C"))
    )
    (comp (ref "C352")
      (value "C")
      (footprint "SMD_0603_CAPC1608X95N")
      (fields
        (field (name "DB_PART_NUMBER") "CAP000028169")
        (field (name "DB_VALUE") "470nF")
        (field (name "DB_TOLERANCE") "5%")
        (field (name "DB_VOLTAGE") "16V")
        (field (name "DB_MANUFACTURER_PART") "KEMET    C0603C474J4RAC")
        (field (name "DB_APPROVED_BY") "ISHIDDEN=T")
      )
      (libsource (lib "Database_Libs1") (part "C"))
    )
    (comp (ref "C353")
      (value "C")
      (footprint "SMD_0603_CAPC1608X95N")
      (fields
        (field (name "DB_PART_NUMBER") "CAP000028169")
        (field (name "DB_VALUE") "470nF")
        (field (name "DB_TOLERANCE") "5%")
        (field (name "DB_VOLTAGE") "16V")
        (field (name "DB_MANUFACTURER_PART") "KEMET    C0603C474J4RAC")
        (field (name "DB_APPROVED_BY") "ISHIDDEN=T")
      )
      (libsource (lib "Database_Libs1") (part "C"))
    )
    (comp (ref "C354")
      (value "C")
      (footprint "SMD_0603_CAPC1608X95N")
      (fields
        (field (name "DB_PART_NUMBER") "CAP000028169")
        (field (name "DB_VALUE") "470nF")
        (field (name "DB_TOLERANCE") "5%")
        (field (name "DB_VOLTAGE") "16V")
        (field (name "DB_MANUFACTURER_PART") "KEMET    C0603C474J4RAC")
        (field (name "DB_APPROVED_BY") "ISHIDDEN=T")
      )
      (libsource (lib "Database_Libs1") (part "C"))
    )
    (comp (ref "C355")
      (value "C")
      (footprint "SMD_0603_CAPC1608X95N")
      (fields
        (field (name "DB_PART_NUMBER") "CAP000028169")
        (field (name "DB_VALUE") "470nF")
        (field (name "DB_TOLERANCE") "5%")
        (field (name "DB_VOLTAGE") "16V")
        (field (name "DB_MANUFACTURER_PART") "KEMET    C0603C474J4RAC")
        (field (name "DB_APPROVED_BY") "ISHIDDEN=T")
      )
      (libsource (lib "Database_Libs1") (part "C"))
    )
    (comp (ref "C356")
      (value "C")
      (footprint "SMD_0603_CAPC1608X95N")
      (fields
        (field (name "DB_PART_NUMBER") "CAP000028169")
        (field (name "DB_VALUE") "470nF")
        (field (name "DB_TOLERANCE") "5%")
        (field (name "DB_VOLTAGE") "16V")
        (field (name "DB_MANUFACTURER_PART") "KEMET    C0603C474J4RAC")
        (field (name "DB_APPROVED_BY") "ISHIDDEN=T")
      )
      (libsource (lib "Database_Libs1") (part "C"))
    )
    (comp (ref "C357")
      (value "C")
      (footprint "SMD_0603_CAPC1608X95N")
      (fields
        (field (name "DB_PART_NUMBER") "CAP000028169")
        (field (name "DB_VALUE") "470nF")
        (field (name "DB_TOLERANCE") "5%")
        (field (name "DB_VOLTAGE") "16V")
        (field (name "DB_MANUFACTURER_PART") "KEMET    C0603C474J4RAC")
        (field (name "DB_APPROVED_BY") "ISHIDDEN=T")
      )
      (libsource (lib "Database_Libs1") (part "C"))
    )
    (comp (ref "C358")
      (value "C")
      (footprint "SMD_0603_CAPC1608X95N")
      (fields
        (field (name "DB_PART_NUMBER") "CAP000028169")
        (field (name "DB_VALUE") "470nF")
        (field (name "DB_TOLERANCE") "5%")
        (field (name "DB_VOLTAGE") "16V")
        (field (name "DB_MANUFACTURER_PART") "KEMET    C0603C474J4RAC")
        (field (name "DB_APPROVED_BY") "ISHIDDEN=T")
      )
      (libsource (lib "Database_Libs1") (part "C"))
    )
    (comp (ref "C359")
      (value "C")
      (footprint "SMD_0603_CAPC1608X95N")
      (fields
        (field (name "DB_PART_NUMBER") "CAP000028169")
        (field (name "DB_VALUE") "470nF")
        (field (name "DB_TOLERANCE") "5%")
        (field (name "DB_VOLTAGE") "16V")
        (field (name "DB_MANUFACTURER_PART") "KEMET    C0603C474J4RAC")
        (field (name "DB_APPROVED_BY") "ISHIDDEN=T")
      )
      (libsource (lib "Database_Libs1") (part "C"))
    )
    (comp (ref "C360")
      (value "C")
      (footprint "SMD_0603_CAPC1608X95N")
      (fields
        (field (name "DB_PART_NUMBER") "CAP000028169")
        (field (name "DB_VALUE") "470nF")
        (field (name "DB_TOLERANCE") "5%")
        (field (name "DB_VOLTAGE") "16V")
        (field (name "DB_MANUFACTURER_PART") "KEMET    C0603C474J4RAC")
        (field (name "DB_APPROVED_BY") "ISHIDDEN=T")
      )
      (libsource (lib "Database_Libs1") (part "C"))
    )
    (comp (ref "C361")
      (value "C")
      (footprint "SMD_0603_CAPC1608X95N")
      (fields
        (field (name "DB_PART_NUMBER") "CAP000028169")
        (field (name "DB_VALUE") "470nF")
        (field (name "DB_TOLERANCE") "5%")
        (field (name "DB_VOLTAGE") "16V")
        (field (name "DB_MANUFACTURER_PART") "KEMET    C0603C474J4RAC")
        (field (name "DB_APPROVED_BY") "ISHIDDEN=T")
      )
      (libsource (lib "Database_Libs1") (part "C"))
    )
    (comp (ref "C362")
      (value "C")
      (footprint "SMD_0603_CAPC1608X95N")
      (fields
        (field (name "DB_PART_NUMBER") "CAP000028169")
        (field (name "DB_VALUE") "470nF")
        (field (name "DB_TOLERANCE") "5%")
        (field (name "DB_VOLTAGE") "16V")
        (field (name "DB_MANUFACTURER_PART") "KEMET    C0603C474J4RAC")
        (field (name "DB_APPROVED_BY") "ISHIDDEN=T")
      )
      (libsource (lib "Database_Libs1") (part "C"))
    )
    (comp (ref "C363")
      (value "C")
      (footprint "SMD_0603_CAPC1608X95N")
      (fields
        (field (name "DB_PART_NUMBER") "CAP000028169")
        (field (name "DB_VALUE") "470nF")
        (field (name "DB_TOLERANCE") "5%")
        (field (name "DB_VOLTAGE") "16V")
        (field (name "DB_MANUFACTURER_PART") "KEMET    C0603C474J4RAC")
        (field (name "DB_APPROVED_BY") "ISHIDDEN=T")
      )
      (libsource (lib "Database_Libs1") (part "C"))
    )
    (comp (ref "C364")
      (value "C")
      (footprint "SMD_0603_CAPC1608X95N")
      (fields
        (field (name "DB_PART_NUMBER") "CAP000028169")
        (field (name "DB_VALUE") "470nF")
        (field (name "DB_TOLERANCE") "5%")
        (field (name "DB_VOLTAGE") "16V")
        (field (name "DB_MANUFACTURER_PART") "KEMET    C0603C474J4RAC")
        (field (name "DB_APPROVED_BY") "ISHIDDEN=T")
      )
      (libsource (lib "Database_Libs1") (part "C"))
    )
    (comp (ref "C365")
      (value "C")
      (footprint "SMD_0603_CAPC1608X95N")
      (fields
        (field (name "DB_PART_NUMBER") "CAP000028169")
        (field (name "DB_VALUE") "470nF")
        (field (name "DB_TOLERANCE") "5%")
        (field (name "DB_VOLTAGE") "16V")
        (field (name "DB_MANUFACTURER_PART") "KEMET    C0603C474J4RAC")
        (field (name "DB_APPROVED_BY") "ISHIDDEN=T")
      )
      (libsource (lib "Database_Libs1") (part "C"))
    )
    (comp (ref "C366")
      (value "C")
      (footprint "SMD_0603_CAPC1608X95N")
      (fields
        (field (name "DB_PART_NUMBER") "CAP000028169")
        (field (name "DB_VALUE") "470nF")
        (field (name "DB_TOLERANCE") "5%")
        (field (name "DB_VOLTAGE") "16V")
        (field (name "DB_MANUFACTURER_PART") "KEMET    C0603C474J4RAC")
        (field (name "DB_APPROVED_BY") "ISHIDDEN=T")
      )
      (libsource (lib "Database_Libs1") (part "C"))
    )
    (comp (ref "C367")
      (value "C")
      (footprint "SMD_0603_CAPC1608X95N")
      (fields
        (field (name "DB_PART_NUMBER") "CAP000028169")
        (field (name "DB_VALUE") "470nF")
        (field (name "DB_TOLERANCE") "5%")
        (field (name "DB_VOLTAGE") "16V")
        (field (name "DB_MANUFACTURER_PART") "KEMET    C0603C474J4RAC")
        (field (name "DB_APPROVED_BY") "ISHIDDEN=T")
      )
      (libsource (lib "Database_Libs1") (part "C"))
    )
    (comp (ref "C368")
      (value "C")
      (footprint "SMD_0603_CAPC1608X95N")
      (fields
        (field (name "DB_PART_NUMBER") "CAP000028169")
        (field (name "DB_VALUE") "470nF")
        (field (name "DB_TOLERANCE") "5%")
        (field (name "DB_VOLTAGE") "16V")
        (field (name "DB_MANUFACTURER_PART") "KEMET    C0603C474J4RAC")
        (field (name "DB_APPROVED_BY") "ISHIDDEN=T")
      )
      (libsource (lib "Database_Libs1") (part "C"))
    )
    (comp (ref "C369")
      (value "C")
      (footprint "SMD_0603_CAPC1608X95N")
      (fields
        (field (name "DB_PART_NUMBER") "CAP000028169")
        (field (name "DB_VALUE") "470nF")
        (field (name "DB_TOLERANCE") "5%")
        (field (name "DB_VOLTAGE") "16V")
        (field (name "DB_MANUFACTURER_PART") "KEMET    C0603C474J4RAC")
        (field (name "DB_APPROVED_BY") "ISHIDDEN=T")
      )
      (libsource (lib "Database_Libs1") (part "C"))
    )
    (comp (ref "C370")
      (value "C")
      (footprint "SMD_0603_CAPC1608X95N")
      (fields
        (field (name "DB_PART_NUMBER") "CAP000028169")
        (field (name "DB_VALUE") "470nF")
        (field (name "DB_TOLERANCE") "5%")
        (field (name "DB_VOLTAGE") "16V")
        (field (name "DB_MANUFACTURER_PART") "KEMET    C0603C474J4RAC")
        (field (name "DB_APPROVED_BY") "ISHIDDEN=T")
      )
      (libsource (lib "Database_Libs1") (part "C"))
    )
    (comp (ref "C371")
      (value "C")
      (footprint "SMD_0603_CAPC1608X95N")
      (fields
        (field (name "DB_PART_NUMBER") "CAP000028169")
        (field (name "DB_VALUE") "470nF")
        (field (name "DB_TOLERANCE") "5%")
        (field (name "DB_VOLTAGE") "16V")
        (field (name "DB_MANUFACTURER_PART") "KEMET    C0603C474J4RAC")
        (field (name "DB_APPROVED_BY") "ISHIDDEN=T")
      )
      (libsource (lib "Database_Libs1") (part "C"))
    )
    (comp (ref "C372")
      (value "C")
      (footprint "SMD_0603_CAPC1608X95N")
      (fields
        (field (name "DB_PART_NUMBER") "CAP000028169")
        (field (name "DB_VALUE") "470nF")
        (field (name "DB_TOLERANCE") "5%")
        (field (name "DB_VOLTAGE") "16V")
        (field (name "DB_MANUFACTURER_PART") "KEMET    C0603C474J4RAC")
        (field (name "DB_APPROVED_BY") "ISHIDDEN=T")
      )
      (libsource (lib "Database_Libs1") (part "C"))
    )
    (comp (ref "C373")
      (value "C")
      (footprint "SMD_0603_CAPC1608X95N")
      (fields
        (field (name "DB_PART_NUMBER") "CAP000028169")
        (field (name "DB_VALUE") "470nF")
        (field (name "DB_TOLERANCE") "5%")
        (field (name "DB_VOLTAGE") "16V")
        (field (name "DB_MANUFACTURER_PART") "KEMET    C0603C474J4RAC")
        (field (name "DB_APPROVED_BY") "ISHIDDEN=T")
      )
      (libsource (lib "Database_Libs1") (part "C"))
    )
    (comp (ref "C374")
      (value "C")
      (footprint "SMD_0603_CAPC1608X95N")
      (fields
        (field (name "DB_PART_NUMBER") "CAP000028169")
        (field (name "DB_VALUE") "470nF")
        (field (name "DB_TOLERANCE") "5%")
        (field (name "DB_VOLTAGE") "16V")
        (field (name "DB_MANUFACTURER_PART") "KEMET    C0603C474J4RAC")
        (field (name "DB_APPROVED_BY") "ISHIDDEN=T")
      )
      (libsource (lib "Database_Libs1") (part "C"))
    )
    (comp (ref "C375")
      (value "C")
      (footprint "SMD_0603_CAPC1608X95N")
      (fields
        (field (name "DB_PART_NUMBER") "CAP000028169")
        (field (name "DB_VALUE") "470nF")
        (field (name "DB_TOLERANCE") "5%")
        (field (name "DB_VOLTAGE") "16V")
        (field (name "DB_MANUFACTURER_PART") "KEMET    C0603C474J4RAC")
        (field (name "DB_APPROVED_BY") "ISHIDDEN=T")
      )
      (libsource (lib "Database_Libs1") (part "C"))
    )
    (comp (ref "C376")
      (value "C")
      (footprint "SMD_0603_CAPC1608X95N")
      (fields
        (field (name "DB_PART_NUMBER") "CAP000028169")
        (field (name "DB_VALUE") "470nF")
        (field (name "DB_TOLERANCE") "5%")
        (field (name "DB_VOLTAGE") "16V")
        (field (name "DB_MANUFACTURER_PART") "KEMET    C0603C474J4RAC")
        (field (name "DB_APPROVED_BY") "ISHIDDEN=T")
      )
      (libsource (lib "Database_Libs1") (part "C"))
    )
    (comp (ref "C377")
      (value "C")
      (footprint "SMD_0603_CAPC1608X95N")
      (fields
        (field (name "DB_PART_NUMBER") "CAP000028169")
        (field (name "DB_VALUE") "470nF")
        (field (name "DB_TOLERANCE") "5%")
        (field (name "DB_VOLTAGE") "16V")
        (field (name "DB_MANUFACTURER_PART") "KEMET    C0603C474J4RAC")
        (field (name "DB_APPROVED_BY") "ISHIDDEN=T")
      )
      (libsource (lib "Database_Libs1") (part "C"))
    )
    (comp (ref "C378")
      (value "C")
      (footprint "SMD_0603_CAPC1608X95N")
      (fields
        (field (name "DB_PART_NUMBER") "CAP000028169")
        (field (name "DB_VALUE") "470nF")
        (field (name "DB_TOLERANCE") "5%")
        (field (name "DB_VOLTAGE") "16V")
        (field (name "DB_MANUFACTURER_PART") "KEMET    C0603C474J4RAC")
        (field (name "DB_APPROVED_BY") "ISHIDDEN=T")
      )
      (libsource (lib "Database_Libs1") (part "C"))
    )
    (comp (ref "C379")
      (value "C")
      (footprint "SMD_0603_CAPC1608X95N")
      (fields
        (field (name "DB_PART_NUMBER") "CAP000028169")
        (field (name "DB_VALUE") "470nF")
        (field (name "DB_TOLERANCE") "5%")
        (field (name "DB_VOLTAGE") "16V")
        (field (name "DB_MANUFACTURER_PART") "KEMET    C0603C474J4RAC")
        (field (name "DB_APPROVED_BY") "ISHIDDEN=T")
      )
      (libsource (lib "Database_Libs1") (part "C"))
    )
    (comp (ref "C380")
      (value "C")
      (footprint "SMD_0603_CAPC1608X95N")
      (fields
        (field (name "DB_PART_NUMBER") "CAP000028169")
        (field (name "DB_VALUE") "470nF")
        (field (name "DB_TOLERANCE") "5%")
        (field (name "DB_VOLTAGE") "16V")
        (field (name "DB_MANUFACTURER_PART") "KEMET    C0603C474J4RAC")
        (field (name "DB_APPROVED_BY") "ISHIDDEN=T")
      )
      (libsource (lib "Database_Libs1") (part "C"))
    )
    (comp (ref "C381")
      (value "C")
      (footprint "SMD_0603_CAPC1608X95N")
      (fields
        (field (name "DB_PART_NUMBER") "CAP000028169")
        (field (name "DB_VALUE") "470nF")
        (field (name "DB_TOLERANCE") "5%")
        (field (name "DB_VOLTAGE") "16V")
        (field (name "DB_MANUFACTURER_PART") "KEMET    C0603C474J4RAC")
        (field (name "DB_APPROVED_BY") "ISHIDDEN=T")
      )
      (libsource (lib "Database_Libs1") (part "C"))
    )
    (comp (ref "C382")
      (value "C")
      (footprint "SMD_0603_CAPC1608X95N")
      (fields
        (field (name "DB_PART_NUMBER") "CAP000028169")
        (field (name "DB_VALUE") "470nF")
        (field (name "DB_TOLERANCE") "5%")
        (field (name "DB_VOLTAGE") "16V")
        (field (name "DB_MANUFACTURER_PART") "KEMET    C0603C474J4RAC")
        (field (name "DB_APPROVED_BY") "ISHIDDEN=T")
      )
      (libsource (lib "Database_Libs1") (part "C"))
    )
    (comp (ref "C383")
      (value "C")
      (footprint "SMD_0603_CAPC1608X95N")
      (fields
        (field (name "DB_PART_NUMBER") "CAP000028169")
        (field (name "DB_VALUE") "470nF")
        (field (name "DB_TOLERANCE") "5%")
        (field (name "DB_VOLTAGE") "16V")
        (field (name "DB_MANUFACTURER_PART") "KEMET    C0603C474J4RAC")
        (field (name "DB_APPROVED_BY") "ISHIDDEN=T")
      )
      (libsource (lib "Database_Libs1") (part "C"))
    )
    (comp (ref "C_1")
      (value "C")
      (footprint "SMD_1210_CAPC3225X279N")
      (fields
        (field (name "DB_PART_NUMBER") "CAP000047355")
        (field (name "DB_VALUE") "220uF")
        (field (name "DB_TOLERANCE") "20%")
        (field (name "DB_VOLTAGE") "6.3V")
        (field (name "DB_MANUFACTURER_PART") "SAMSUNG    CL32A227MQVNNNE")
        (field (name "DB_APPROVED_BY") "VSN")
      )
      (libsource (lib "Database_Libs1") (part "C"))
    )
    (comp (ref "C_2")
      (value "C")
      (footprint "SMD_1210_CAPC3225X279N")
      (fields
        (field (name "DB_PART_NUMBER") "CAP000047355")
        (field (name "DB_VALUE") "220uF")
        (field (name "DB_TOLERANCE") "20%")
        (field (name "DB_VOLTAGE") "6.3V")
        (field (name "DB_MANUFACTURER_PART") "SAMSUNG    CL32A227MQVNNNE")
        (field (name "DB_APPROVED_BY") "VSN")
      )
      (libsource (lib "Database_Libs1") (part "C"))
    )
    (comp (ref "C_3")
      (value "C")
      (footprint "SMD_1210_CAPC3225X279N")
      (fields
        (field (name "DB_PART_NUMBER") "CAP000047355")
        (field (name "DB_VALUE") "220uF")
        (field (name "DB_TOLERANCE") "20%")
        (field (name "DB_VOLTAGE") "6.3V")
        (field (name "DB_MANUFACTURER_PART") "SAMSUNG    CL32A227MQVNNNE")
        (field (name "DB_APPROVED_BY") "VSN")
      )
      (libsource (lib "Database_Libs1") (part "C"))
    )
    (comp (ref "C_4")
      (value "C")
      (footprint "SMD_1210_CAPC3225X279N")
      (fields
        (field (name "DB_PART_NUMBER") "CAP000047355")
        (field (name "DB_VALUE") "220uF")
        (field (name "DB_TOLERANCE") "20%")
        (field (name "DB_VOLTAGE") "6.3V")
        (field (name "DB_MANUFACTURER_PART") "SAMSUNG    CL32A227MQVNNNE")
        (field (name "DB_APPROVED_BY") "VSN")
      )
      (libsource (lib "Database_Libs1") (part "C"))
    )
    (comp (ref "C_5")
      (value "C")
      (footprint "SMD_1210_CAPC3225X279N")
      (fields
        (field (name "DB_PART_NUMBER") "CAP000047355")
        (field (name "DB_VALUE") "220uF")
        (field (name "DB_TOLERANCE") "20%")
        (field (name "DB_VOLTAGE") "6.3V")
        (field (name "DB_MANUFACTURER_PART") "SAMSUNG    CL32A227MQVNNNE")
        (field (name "DB_APPROVED_BY") "VSN")
      )
      (libsource (lib "Database_Libs1") (part "C"))
    )
    (comp (ref "C_6")
      (value "C")
      (footprint "SMD_1210_CAPC3225X279N")
      (fields
        (field (name "DB_PART_NUMBER") "CAP000047355")
        (field (name "DB_VALUE") "220uF")
        (field (name "DB_TOLERANCE") "20%")
        (field (name "DB_VOLTAGE") "6.3V")
        (field (name "DB_MANUFACTURER_PART") "SAMSUNG    CL32A227MQVNNNE")
        (field (name "DB_APPROVED_BY") "VSN")
      )
      (libsource (lib "Database_Libs1") (part "C"))
    )
    (comp (ref "C_7")
      (value "C")
      (footprint "SMD_1210_CAPC3225X279N")
      (fields
        (field (name "DB_PART_NUMBER") "CAP000047355")
        (field (name "DB_VALUE") "220uF")
        (field (name "DB_TOLERANCE") "20%")
        (field (name "DB_VOLTAGE") "6.3V")
        (field (name "DB_MANUFACTURER_PART") "SAMSUNG    CL32A227MQVNNNE")
        (field (name "DB_APPROVED_BY") "VSN")
      )
      (libsource (lib "Database_Libs1") (part "C"))
    )
    (comp (ref "C_8")
      (value "C")
      (footprint "SMD_1210_CAPC3225X279N")
      (fields
        (field (name "DB_PART_NUMBER") "CAP000047355")
        (field (name "DB_VALUE") "220uF")
        (field (name "DB_TOLERANCE") "20%")
        (field (name "DB_VOLTAGE") "6.3V")
        (field (name "DB_MANUFACTURER_PART") "SAMSUNG    CL32A227MQVNNNE")
        (field (name "DB_APPROVED_BY") "VSN")
      )
      (libsource (lib "Database_Libs1") (part "C"))
    )
    (comp (ref "C_9")
      (value "C")
      (footprint "SMD_1210_CAPC3225X279N")
      (fields
        (field (name "DB_PART_NUMBER") "CAP000047355")
        (field (name "DB_VALUE") "220uF")
        (field (name "DB_TOLERANCE") "20%")
        (field (name "DB_VOLTAGE") "6.3V")
        (field (name "DB_MANUFACTURER_PART") "SAMSUNG    CL32A227MQVNNNE")
        (field (name "DB_APPROVED_BY") "VSN")
      )
      (libsource (lib "Database_Libs1") (part "C"))
    )
    (comp (ref "C_10")
      (value "C")
      (footprint "SMD_1210_CAPC3225X279N")
      (fields
        (field (name "DB_PART_NUMBER") "CAP000047355")
        (field (name "DB_VALUE") "220uF")
        (field (name "DB_TOLERANCE") "20%")
        (field (name "DB_VOLTAGE") "6.3V")
        (field (name "DB_MANUFACTURER_PART") "SAMSUNG    CL32A227MQVNNNE")
        (field (name "DB_APPROVED_BY") "VSN")
      )
      (libsource (lib "Database_Libs1") (part "C"))
    )
    (comp (ref "C_11")
      (value "C")
      (footprint "SMD_1210_CAPC3225X279N")
      (fields
        (field (name "DB_PART_NUMBER") "CAP000047355")
        (field (name "DB_VALUE") "220uF")
        (field (name "DB_TOLERANCE") "20%")
        (field (name "DB_VOLTAGE") "6.3V")
        (field (name "DB_MANUFACTURER_PART") "SAMSUNG    CL32A227MQVNNNE")
        (field (name "DB_APPROVED_BY") "VSN")
      )
      (libsource (lib "Database_Libs1") (part "C"))
    )
    (comp (ref "C_12")
      (value "C")
      (footprint "SMD_1210_CAPC3225X279N")
      (fields
        (field (name "DB_PART_NUMBER") "CAP000047355")
        (field (name "DB_VALUE") "220uF")
        (field (name "DB_TOLERANCE") "20%")
        (field (name "DB_VOLTAGE") "6.3V")
        (field (name "DB_MANUFACTURER_PART") "SAMSUNG    CL32A227MQVNNNE")
        (field (name "DB_APPROVED_BY") "VSN")
      )
      (libsource (lib "Database_Libs1") (part "C"))
    )
    (comp (ref "C_13")
      (value "C")
      (footprint "SMD_1210_CAPC3225X279N")
      (fields
        (field (name "DB_PART_NUMBER") "CAP000047355")
        (field (name "DB_VALUE") "220uF")
        (field (name "DB_TOLERANCE") "20%")
        (field (name "DB_VOLTAGE") "6.3V")
        (field (name "DB_MANUFACTURER_PART") "SAMSUNG    CL32A227MQVNNNE")
        (field (name "DB_APPROVED_BY") "VSN")
      )
      (libsource (lib "Database_Libs1") (part "C"))
    )
    (comp (ref "C_14")
      (value "C")
      (footprint "SMD_1210_CAPC3225X279N")
      (fields
        (field (name "DB_PART_NUMBER") "CAP000047355")
        (field (name "DB_VALUE") "220uF")
        (field (name "DB_TOLERANCE") "20%")
        (field (name "DB_VOLTAGE") "6.3V")
        (field (name "DB_MANUFACTURER_PART") "SAMSUNG    CL32A227MQVNNNE")
        (field (name "DB_APPROVED_BY") "VSN")
      )
      (libsource (lib "Database_Libs1") (part "C"))
    )
    (comp (ref "C_15")
      (value "C")
      (footprint "SMD_1210_CAPC3225X279N")
      (fields
        (field (name "DB_PART_NUMBER") "CAP000047355")
        (field (name "DB_VALUE") "220uF")
        (field (name "DB_TOLERANCE") "20%")
        (field (name "DB_VOLTAGE") "6.3V")
        (field (name "DB_MANUFACTURER_PART") "SAMSUNG    CL32A227MQVNNNE")
        (field (name "DB_APPROVED_BY") "VSN")
      )
      (libsource (lib "Database_Libs1") (part "C"))
    )
    (comp (ref "C_16")
      (value "C")
      (footprint "SMD_1210_CAPC3225X279N")
      (fields
        (field (name "DB_PART_NUMBER") "CAP000047355")
        (field (name "DB_VALUE") "220uF")
        (field (name "DB_TOLERANCE") "20%")
        (field (name "DB_VOLTAGE") "6.3V")
        (field (name "DB_MANUFACTURER_PART") "SAMSUNG    CL32A227MQVNNNE")
        (field (name "DB_APPROVED_BY") "VSN")
      )
      (libsource (lib "Database_Libs1") (part "C"))
    )
    (comp (ref "C_17")
      (value "C")
      (footprint "SMD_1210_CAPC3225X279N")
      (fields
        (field (name "DB_PART_NUMBER") "CAP000047355")
        (field (name "DB_VALUE") "220uF")
        (field (name "DB_TOLERANCE") "20%")
        (field (name "DB_VOLTAGE") "6.3V")
        (field (name "DB_MANUFACTURER_PART") "SAMSUNG    CL32A227MQVNNNE")
        (field (name "DB_APPROVED_BY") "VSN")
      )
      (libsource (lib "Database_Libs1") (part "C"))
    )
    (comp (ref "C_18")
      (value "C")
      (footprint "SMD_1210_CAPC3225X279N")
      (fields
        (field (name "DB_PART_NUMBER") "CAP000047355")
        (field (name "DB_VALUE") "220uF")
        (field (name "DB_TOLERANCE") "20%")
        (field (name "DB_VOLTAGE") "6.3V")
        (field (name "DB_MANUFACTURER_PART") "SAMSUNG    CL32A227MQVNNNE")
        (field (name "DB_APPROVED_BY") "VSN")
      )
      (libsource (lib "Database_Libs1") (part "C"))
    )
    (comp (ref "C_19")
      (value "C")
      (footprint "SMD_1210_CAPC3225X279N")
      (fields
        (field (name "DB_PART_NUMBER") "CAP000047355")
        (field (name "DB_VALUE") "220uF")
        (field (name "DB_TOLERANCE") "20%")
        (field (name "DB_VOLTAGE") "6.3V")
        (field (name "DB_MANUFACTURER_PART") "SAMSUNG    CL32A227MQVNNNE")
        (field (name "DB_APPROVED_BY") "VSN")
      )
      (libsource (lib "Database_Libs1") (part "C"))
    )
    (comp (ref "C_20")
      (value "C")
      (footprint "SMD_1210_CAPC3225X279N")
      (fields
        (field (name "DB_PART_NUMBER") "CAP000047355")
        (field (name "DB_VALUE") "220uF")
        (field (name "DB_TOLERANCE") "20%")
        (field (name "DB_VOLTAGE") "6.3V")
        (field (name "DB_MANUFACTURER_PART") "SAMSUNG    CL32A227MQVNNNE")
        (field (name "DB_APPROVED_BY") "VSN")
      )
      (libsource (lib "Database_Libs1") (part "C"))
    )
    (comp (ref "C_21")
      (value "C")
      (footprint "SMD_1210_CAPC3225X279N")
      (fields
        (field (name "DB_PART_NUMBER") "CAP000047355")
        (field (name "DB_VALUE") "220uF")
        (field (name "DB_TOLERANCE") "20%")
        (field (name "DB_VOLTAGE") "6.3V")
        (field (name "DB_MANUFACTURER_PART") "SAMSUNG    CL32A227MQVNNNE")
        (field (name "DB_APPROVED_BY") "VSN")
      )
      (libsource (lib "Database_Libs1") (part "C"))
    )
    (comp (ref "C_22")
      (value "C")
      (footprint "SMD_1210_CAPC3225X279N")
      (fields
        (field (name "DB_PART_NUMBER") "CAP000047355")
        (field (name "DB_VALUE") "220uF")
        (field (name "DB_TOLERANCE") "20%")
        (field (name "DB_VOLTAGE") "6.3V")
        (field (name "DB_MANUFACTURER_PART") "SAMSUNG    CL32A227MQVNNNE")
        (field (name "DB_APPROVED_BY") "VSN")
      )
      (libsource (lib "Database_Libs1") (part "C"))
    )
    (comp (ref "C_23")
      (value "C")
      (footprint "SMD_1210_CAPC3225X279N")
      (fields
        (field (name "DB_PART_NUMBER") "CAP000047355")
        (field (name "DB_VALUE") "220uF")
        (field (name "DB_TOLERANCE") "20%")
        (field (name "DB_VOLTAGE") "6.3V")
        (field (name "DB_MANUFACTURER_PART") "SAMSUNG    CL32A227MQVNNNE")
        (field (name "DB_APPROVED_BY") "VSN")
      )
      (libsource (lib "Database_Libs1") (part "C"))
    )
    (comp (ref "C_24")
      (value "C")
      (footprint "SMD_1210_CAPC3225X279N")
      (fields
        (field (name "DB_PART_NUMBER") "CAP000047355")
        (field (name "DB_VALUE") "220uF")
        (field (name "DB_TOLERANCE") "20%")
        (field (name "DB_VOLTAGE") "6.3V")
        (field (name "DB_MANUFACTURER_PART") "SAMSUNG    CL32A227MQVNNNE")
        (field (name "DB_APPROVED_BY") "VSN")
      )
      (libsource (lib "Database_Libs1") (part "C"))
    )
    (comp (ref "C_25")
      (value "C")
      (footprint "SMD_1210_CAPC3225X279N")
      (fields
        (field (name "DB_PART_NUMBER") "CAP000047355")
        (field (name "DB_VALUE") "220uF")
        (field (name "DB_TOLERANCE") "20%")
        (field (name "DB_VOLTAGE") "6.3V")
        (field (name "DB_MANUFACTURER_PART") "SAMSUNG    CL32A227MQVNNNE")
        (field (name "DB_APPROVED_BY") "VSN")
      )
      (libsource (lib "Database_Libs1") (part "C"))
    )
    (comp (ref "C_26")
      (value "C")
      (footprint "SMD_1210_CAPC3225X279N")
      (fields
        (field (name "DB_PART_NUMBER") "CAP000047355")
        (field (name "DB_VALUE") "220uF")
        (field (name "DB_TOLERANCE") "20%")
        (field (name "DB_VOLTAGE") "6.3V")
        (field (name "DB_MANUFACTURER_PART") "SAMSUNG    CL32A227MQVNNNE")
        (field (name "DB_APPROVED_BY") "VSN")
      )
      (libsource (lib "Database_Libs1") (part "C"))
    )
    (comp (ref "C_27")
      (value "C")
      (footprint "SMD_1210_CAPC3225X279N")
      (fields
        (field (name "DB_PART_NUMBER") "CAP000047355")
        (field (name "DB_VALUE") "220uF")
        (field (name "DB_TOLERANCE") "20%")
        (field (name "DB_VOLTAGE") "6.3V")
        (field (name "DB_MANUFACTURER_PART") "SAMSUNG    CL32A227MQVNNNE")
        (field (name "DB_APPROVED_BY") "VSN")
      )
      (libsource (lib "Database_Libs1") (part "C"))
    )
    (comp (ref "C_28")
      (value "C")
      (footprint "SMD_1210_CAPC3225X279N")
      (fields
        (field (name "DB_PART_NUMBER") "CAP000047355")
        (field (name "DB_VALUE") "220uF")
        (field (name "DB_TOLERANCE") "20%")
        (field (name "DB_VOLTAGE") "6.3V")
        (field (name "DB_MANUFACTURER_PART") "SAMSUNG    CL32A227MQVNNNE")
        (field (name "DB_APPROVED_BY") "VSN")
      )
      (libsource (lib "Database_Libs1") (part "C"))
    )
    (comp (ref "C_29")
      (value "C")
      (footprint "SMD_1210_CAPC3225X279N")
      (fields
        (field (name "DB_PART_NUMBER") "CAP000047355")
        (field (name "DB_VALUE") "220uF")
        (field (name "DB_TOLERANCE") "20%")
        (field (name "DB_VOLTAGE") "6.3V")
        (field (name "DB_MANUFACTURER_PART") "SAMSUNG    CL32A227MQVNNNE")
        (field (name "DB_APPROVED_BY") "VSN")
      )
      (libsource (lib "Database_Libs1") (part "C"))
    )
    (comp (ref "C_30")
      (value "C")
      (footprint "SMD_1210_CAPC3225X279N")
      (fields
        (field (name "DB_PART_NUMBER") "CAP000047355")
        (field (name "DB_VALUE") "220uF")
        (field (name "DB_TOLERANCE") "20%")
        (field (name "DB_VOLTAGE") "6.3V")
        (field (name "DB_MANUFACTURER_PART") "SAMSUNG    CL32A227MQVNNNE")
        (field (name "DB_APPROVED_BY") "VSN")
      )
      (libsource (lib "Database_Libs1") (part "C"))
    )
    (comp (ref "C_31")
      (value "C")
      (footprint "SMD_1210_CAPC3225X279N")
      (fields
        (field (name "DB_PART_NUMBER") "CAP000047355")
        (field (name "DB_VALUE") "220uF")
        (field (name "DB_TOLERANCE") "20%")
        (field (name "DB_VOLTAGE") "6.3V")
        (field (name "DB_MANUFACTURER_PART") "SAMSUNG    CL32A227MQVNNNE")
        (field (name "DB_APPROVED_BY") "VSN")
      )
      (libsource (lib "Database_Libs1") (part "C"))
    )
    (comp (ref "C_32")
      (value "C")
      (footprint "SMD_1210_CAPC3225X279N")
      (fields
        (field (name "DB_PART_NUMBER") "CAP000047355")
        (field (name "DB_VALUE") "220uF")
        (field (name "DB_TOLERANCE") "20%")
        (field (name "DB_VOLTAGE") "6.3V")
        (field (name "DB_MANUFACTURER_PART") "SAMSUNG    CL32A227MQVNNNE")
        (field (name "DB_APPROVED_BY") "VSN")
      )
      (libsource (lib "Database_Libs1") (part "C"))
    )
    (comp (ref "C_33")
      (value "C")
      (footprint "SMD_1210_CAPC3225X279N")
      (fields
        (field (name "DB_PART_NUMBER") "CAP000047355")
        (field (name "DB_VALUE") "220uF")
        (field (name "DB_TOLERANCE") "20%")
        (field (name "DB_VOLTAGE") "6.3V")
        (field (name "DB_MANUFACTURER_PART") "SAMSUNG    CL32A227MQVNNNE")
        (field (name "DB_APPROVED_BY") "VSN")
      )
      (libsource (lib "Database_Libs1") (part "C"))
    )
    (comp (ref "C_34")
      (value "C")
      (footprint "SMD_1210_CAPC3225X279N")
      (fields
        (field (name "DB_PART_NUMBER") "CAP000047355")
        (field (name "DB_VALUE") "220uF")
        (field (name "DB_TOLERANCE") "20%")
        (field (name "DB_VOLTAGE") "6.3V")
        (field (name "DB_MANUFACTURER_PART") "SAMSUNG    CL32A227MQVNNNE")
        (field (name "DB_APPROVED_BY") "VSN")
      )
      (libsource (lib "Database_Libs1") (part "C"))
    )
    (comp (ref "C_35")
      (value "C")
      (footprint "SMD_1210_CAPC3225X279N")
      (fields
        (field (name "DB_PART_NUMBER") "CAP000047355")
        (field (name "DB_VALUE") "220uF")
        (field (name "DB_TOLERANCE") "20%")
        (field (name "DB_VOLTAGE") "6.3V")
        (field (name "DB_MANUFACTURER_PART") "SAMSUNG    CL32A227MQVNNNE")
        (field (name "DB_APPROVED_BY") "VSN")
      )
      (libsource (lib "Database_Libs1") (part "C"))
    )
    (comp (ref "C_36")
      (value "C")
      (footprint "SMD_1210_CAPC3225X279N")
      (fields
        (field (name "DB_PART_NUMBER") "CAP000047355")
        (field (name "DB_VALUE") "220uF")
        (field (name "DB_TOLERANCE") "20%")
        (field (name "DB_VOLTAGE") "6.3V")
        (field (name "DB_MANUFACTURER_PART") "SAMSUNG    CL32A227MQVNNNE")
        (field (name "DB_APPROVED_BY") "VSN")
      )
      (libsource (lib "Database_Libs1") (part "C"))
    )
    (comp (ref "C_37")
      (value "C")
      (footprint "SMD_1210_CAPC3225X279N")
      (fields
        (field (name "DB_PART_NUMBER") "CAP000047355")
        (field (name "DB_VALUE") "220uF")
        (field (name "DB_TOLERANCE") "20%")
        (field (name "DB_VOLTAGE") "6.3V")
        (field (name "DB_MANUFACTURER_PART") "SAMSUNG    CL32A227MQVNNNE")
        (field (name "DB_APPROVED_BY") "VSN")
      )
      (libsource (lib "Database_Libs1") (part "C"))
    )
    (comp (ref "C_38")
      (value "C")
      (footprint "SMD_1210_CAPC3225X279N")
      (fields
        (field (name "DB_PART_NUMBER") "CAP000047355")
        (field (name "DB_VALUE") "220uF")
        (field (name "DB_TOLERANCE") "20%")
        (field (name "DB_VOLTAGE") "6.3V")
        (field (name "DB_MANUFACTURER_PART") "SAMSUNG    CL32A227MQVNNNE")
        (field (name "DB_APPROVED_BY") "VSN")
      )
      (libsource (lib "Database_Libs1") (part "C"))
    )
    (comp (ref "C_39")
      (value "C")
      (footprint "SMD_1210_CAPC3225X279N")
      (fields
        (field (name "DB_PART_NUMBER") "CAP000047355")
        (field (name "DB_VALUE") "220uF")
        (field (name "DB_TOLERANCE") "20%")
        (field (name "DB_VOLTAGE") "6.3V")
        (field (name "DB_MANUFACTURER_PART") "SAMSUNG    CL32A227MQVNNNE")
        (field (name "DB_APPROVED_BY") "VSN")
      )
      (libsource (lib "Database_Libs1") (part "C"))
    )
    (comp (ref "C_40")
      (value "C")
      (footprint "SMD_1210_CAPC3225X279N")
      (fields
        (field (name "DB_PART_NUMBER") "CAP000047355")
        (field (name "DB_VALUE") "220uF")
        (field (name "DB_TOLERANCE") "20%")
        (field (name "DB_VOLTAGE") "6.3V")
        (field (name "DB_MANUFACTURER_PART") "SAMSUNG    CL32A227MQVNNNE")
        (field (name "DB_APPROVED_BY") "VSN")
      )
      (libsource (lib "Database_Libs1") (part "C"))
    )
    (comp (ref "C_41")
      (value "C")
      (footprint "SMD_1210_CAPC3225X279N")
      (fields
        (field (name "DB_PART_NUMBER") "CAP000047355")
        (field (name "DB_VALUE") "220uF")
        (field (name "DB_TOLERANCE") "20%")
        (field (name "DB_VOLTAGE") "6.3V")
        (field (name "DB_MANUFACTURER_PART") "SAMSUNG    CL32A227MQVNNNE")
        (field (name "DB_APPROVED_BY") "VSN")
      )
      (libsource (lib "Database_Libs1") (part "C"))
    )
    (comp (ref "C_42")
      (value "C")
      (footprint "SMD_1210_CAPC3225X279N")
      (fields
        (field (name "DB_PART_NUMBER") "CAP000047355")
        (field (name "DB_VALUE") "220uF")
        (field (name "DB_TOLERANCE") "20%")
        (field (name "DB_VOLTAGE") "6.3V")
        (field (name "DB_MANUFACTURER_PART") "SAMSUNG    CL32A227MQVNNNE")
        (field (name "DB_APPROVED_BY") "VSN")
      )
      (libsource (lib "Database_Libs1") (part "C"))
    )
    (comp (ref "C_43")
      (value "C")
      (footprint "SMD_1210_CAPC3225X279N")
      (fields
        (field (name "DB_PART_NUMBER") "CAP000047355")
        (field (name "DB_VALUE") "220uF")
        (field (name "DB_TOLERANCE") "20%")
        (field (name "DB_VOLTAGE") "6.3V")
        (field (name "DB_MANUFACTURER_PART") "SAMSUNG    CL32A227MQVNNNE")
        (field (name "DB_APPROVED_BY") "VSN")
      )
      (libsource (lib "Database_Libs1") (part "C"))
    )
    (comp (ref "C_44")
      (value "C")
      (footprint "SMD_1210_CAPC3225X279N")
      (fields
        (field (name "DB_PART_NUMBER") "CAP000047355")
        (field (name "DB_VALUE") "220uF")
        (field (name "DB_TOLERANCE") "20%")
        (field (name "DB_VOLTAGE") "6.3V")
        (field (name "DB_MANUFACTURER_PART") "SAMSUNG    CL32A227MQVNNNE")
        (field (name "DB_APPROVED_BY") "VSN")
      )
      (libsource (lib "Database_Libs1") (part "C"))
    )
    (comp (ref "C_45")
      (value "C")
      (footprint "SMD_1210_CAPC3225X279N")
      (fields
        (field (name "DB_PART_NUMBER") "CAP000047355")
        (field (name "DB_VALUE") "220uF")
        (field (name "DB_TOLERANCE") "20%")
        (field (name "DB_VOLTAGE") "6.3V")
        (field (name "DB_MANUFACTURER_PART") "SAMSUNG    CL32A227MQVNNNE")
        (field (name "DB_APPROVED_BY") "VSN")
      )
      (libsource (lib "Database_Libs1") (part "C"))
    )
    (comp (ref "C_46")
      (value "C")
      (footprint "SMD_1210_CAPC3225X279N")
      (fields
        (field (name "DB_PART_NUMBER") "CAP000047355")
        (field (name "DB_VALUE") "220uF")
        (field (name "DB_TOLERANCE") "20%")
        (field (name "DB_VOLTAGE") "6.3V")
        (field (name "DB_MANUFACTURER_PART") "SAMSUNG    CL32A227MQVNNNE")
        (field (name "DB_APPROVED_BY") "VSN")
      )
      (libsource (lib "Database_Libs1") (part "C"))
    )
    (comp (ref "C_47")
      (value "C")
      (footprint "SMD_1210_CAPC3225X279N")
      (fields
        (field (name "DB_PART_NUMBER") "CAP000047355")
        (field (name "DB_VALUE") "220uF")
        (field (name "DB_TOLERANCE") "20%")
        (field (name "DB_VOLTAGE") "6.3V")
        (field (name "DB_MANUFACTURER_PART") "SAMSUNG    CL32A227MQVNNNE")
        (field (name "DB_APPROVED_BY") "VSN")
      )
      (libsource (lib "Database_Libs1") (part "C"))
    )
    (comp (ref "C_48")
      (value "C")
      (footprint "SMD_1210_CAPC3225X279N")
      (fields
        (field (name "DB_PART_NUMBER") "CAP000047355")
        (field (name "DB_VALUE") "220uF")
        (field (name "DB_TOLERANCE") "20%")
        (field (name "DB_VOLTAGE") "6.3V")
        (field (name "DB_MANUFACTURER_PART") "SAMSUNG    CL32A227MQVNNNE")
        (field (name "DB_APPROVED_BY") "VSN")
      )
      (libsource (lib "Database_Libs1") (part "C"))
    )
    (comp (ref "C_49")
      (value "C")
      (footprint "SMD_1210_CAPC3225X279N")
      (fields
        (field (name "DB_PART_NUMBER") "CAP000047355")
        (field (name "DB_VALUE") "220uF")
        (field (name "DB_TOLERANCE") "20%")
        (field (name "DB_VOLTAGE") "6.3V")
        (field (name "DB_MANUFACTURER_PART") "SAMSUNG    CL32A227MQVNNNE")
        (field (name "DB_APPROVED_BY") "VSN")
      )
      (libsource (lib "Database_Libs1") (part "C"))
    )
    (comp (ref "C_50")
      (value "C")
      (footprint "SMD_1210_CAPC3225X279N")
      (fields
        (field (name "DB_PART_NUMBER") "CAP000047355")
        (field (name "DB_VALUE") "220uF")
        (field (name "DB_TOLERANCE") "20%")
        (field (name "DB_VOLTAGE") "6.3V")
        (field (name "DB_MANUFACTURER_PART") "SAMSUNG    CL32A227MQVNNNE")
        (field (name "DB_APPROVED_BY") "VSN")
      )
      (libsource (lib "Database_Libs1") (part "C"))
    )
    (comp (ref "C_51")
      (value "C")
      (footprint "SMD_1210_CAPC3225X279N")
      (fields
        (field (name "DB_PART_NUMBER") "CAP000047355")
        (field (name "DB_VALUE") "220uF")
        (field (name "DB_TOLERANCE") "20%")
        (field (name "DB_VOLTAGE") "6.3V")
        (field (name "DB_MANUFACTURER_PART") "SAMSUNG    CL32A227MQVNNNE")
        (field (name "DB_APPROVED_BY") "VSN")
      )
      (libsource (lib "Database_Libs1") (part "C"))
    )
    (comp (ref "C_52")
      (value "C")
      (footprint "SMD_1210_CAPC3225X279N")
      (fields
        (field (name "DB_PART_NUMBER") "CAP000047355")
        (field (name "DB_VALUE") "220uF")
        (field (name "DB_TOLERANCE") "20%")
        (field (name "DB_VOLTAGE") "6.3V")
        (field (name "DB_MANUFACTURER_PART") "SAMSUNG    CL32A227MQVNNNE")
        (field (name "DB_APPROVED_BY") "VSN")
      )
      (libsource (lib "Database_Libs1") (part "C"))
    )
    (comp (ref "C_53")
      (value "C")
      (footprint "SMD_1210_CAPC3225X279N")
      (fields
        (field (name "DB_PART_NUMBER") "CAP000047355")
        (field (name "DB_VALUE") "220uF")
        (field (name "DB_TOLERANCE") "20%")
        (field (name "DB_VOLTAGE") "6.3V")
        (field (name "DB_MANUFACTURER_PART") "SAMSUNG    CL32A227MQVNNNE")
        (field (name "DB_APPROVED_BY") "VSN")
      )
      (libsource (lib "Database_Libs1") (part "C"))
    )
    (comp (ref "C_54")
      (value "C")
      (footprint "SMD_1210_CAPC3225X279N")
      (fields
        (field (name "DB_PART_NUMBER") "CAP000047355")
        (field (name "DB_VALUE") "220uF")
        (field (name "DB_TOLERANCE") "20%")
        (field (name "DB_VOLTAGE") "6.3V")
        (field (name "DB_MANUFACTURER_PART") "SAMSUNG    CL32A227MQVNNNE")
        (field (name "DB_APPROVED_BY") "VSN")
      )
      (libsource (lib "Database_Libs1") (part "C"))
    )
    (comp (ref "C_55")
      (value "C")
      (footprint "SMD_1210_CAPC3225X279N")
      (fields
        (field (name "DB_PART_NUMBER") "CAP000047355")
        (field (name "DB_VALUE") "220uF")
        (field (name "DB_TOLERANCE") "20%")
        (field (name "DB_VOLTAGE") "6.3V")
        (field (name "DB_MANUFACTURER_PART") "SAMSUNG    CL32A227MQVNNNE")
        (field (name "DB_APPROVED_BY") "VSN")
      )
      (libsource (lib "Database_Libs1") (part "C"))
    )
    (comp (ref "C_56")
      (value "C")
      (footprint "SMD_1210_CAPC3225X279N")
      (fields
        (field (name "DB_PART_NUMBER") "CAP000047355")
        (field (name "DB_VALUE") "220uF")
        (field (name "DB_TOLERANCE") "20%")
        (field (name "DB_VOLTAGE") "6.3V")
        (field (name "DB_MANUFACTURER_PART") "SAMSUNG    CL32A227MQVNNNE")
        (field (name "DB_APPROVED_BY") "VSN")
      )
      (libsource (lib "Database_Libs1") (part "C"))
    )
    (comp (ref "C_57")
      (value "C")
      (footprint "SMD_1210_CAPC3225X279N")
      (fields
        (field (name "DB_PART_NUMBER") "CAP000047355")
        (field (name "DB_VALUE") "220uF")
        (field (name "DB_TOLERANCE") "20%")
        (field (name "DB_VOLTAGE") "6.3V")
        (field (name "DB_MANUFACTURER_PART") "SAMSUNG    CL32A227MQVNNNE")
        (field (name "DB_APPROVED_BY") "VSN")
      )
      (libsource (lib "Database_Libs1") (part "C"))
    )
    (comp (ref "C_58")
      (value "C")
      (footprint "SMD_1210_CAPC3225X279N")
      (fields
        (field (name "DB_PART_NUMBER") "CAP000047355")
        (field (name "DB_VALUE") "220uF")
        (field (name "DB_TOLERANCE") "20%")
        (field (name "DB_VOLTAGE") "6.3V")
        (field (name "DB_MANUFACTURER_PART") "SAMSUNG    CL32A227MQVNNNE")
        (field (name "DB_APPROVED_BY") "VSN")
      )
      (libsource (lib "Database_Libs1") (part "C"))
    )
    (comp (ref "C_59")
      (value "C")
      (footprint "SMD_1210_CAPC3225X279N")
      (fields
        (field (name "DB_PART_NUMBER") "CAP000047355")
        (field (name "DB_VALUE") "220uF")
        (field (name "DB_TOLERANCE") "20%")
        (field (name "DB_VOLTAGE") "6.3V")
        (field (name "DB_MANUFACTURER_PART") "SAMSUNG    CL32A227MQVNNNE")
        (field (name "DB_APPROVED_BY") "VSN")
      )
      (libsource (lib "Database_Libs1") (part "C"))
    )
    (comp (ref "C_60")
      (value "C")
      (footprint "SMD_1210_CAPC3225X279N")
      (fields
        (field (name "DB_PART_NUMBER") "CAP000047355")
        (field (name "DB_VALUE") "220uF")
        (field (name "DB_TOLERANCE") "20%")
        (field (name "DB_VOLTAGE") "6.3V")
        (field (name "DB_MANUFACTURER_PART") "SAMSUNG    CL32A227MQVNNNE")
        (field (name "DB_APPROVED_BY") "VSN")
      )
      (libsource (lib "Database_Libs1") (part "C"))
    )
    (comp (ref "C_61")
      (value "C")
      (footprint "SMD_1210_CAPC3225X279N")
      (fields
        (field (name "DB_PART_NUMBER") "CAP000047355")
        (field (name "DB_VALUE") "220uF")
        (field (name "DB_TOLERANCE") "20%")
        (field (name "DB_VOLTAGE") "6.3V")
        (field (name "DB_MANUFACTURER_PART") "SAMSUNG    CL32A227MQVNNNE")
        (field (name "DB_APPROVED_BY") "VSN")
      )
      (libsource (lib "Database_Libs1") (part "C"))
    )
    (comp (ref "C_62")
      (value "C")
      (footprint "SMD_1210_CAPC3225X279N")
      (fields
        (field (name "DB_PART_NUMBER") "CAP000047355")
        (field (name "DB_VALUE") "220uF")
        (field (name "DB_TOLERANCE") "20%")
        (field (name "DB_VOLTAGE") "6.3V")
        (field (name "DB_MANUFACTURER_PART") "SAMSUNG    CL32A227MQVNNNE")
        (field (name "DB_APPROVED_BY") "VSN")
      )
      (libsource (lib "Database_Libs1") (part "C"))
    )
    (comp (ref "C_63")
      (value "C")
      (footprint "SMD_1210_CAPC3225X279N")
      (fields
        (field (name "DB_PART_NUMBER") "CAP000047355")
        (field (name "DB_VALUE") "220uF")
        (field (name "DB_TOLERANCE") "20%")
        (field (name "DB_VOLTAGE") "6.3V")
        (field (name "DB_MANUFACTURER_PART") "SAMSUNG    CL32A227MQVNNNE")
        (field (name "DB_APPROVED_BY") "VSN")
      )
      (libsource (lib "Database_Libs1") (part "C"))
    )
    (comp (ref "C_64")
      (value "C")
      (footprint "SMD_1210_CAPC3225X279N")
      (fields
        (field (name "DB_PART_NUMBER") "CAP000047355")
        (field (name "DB_VALUE") "220uF")
        (field (name "DB_TOLERANCE") "20%")
        (field (name "DB_VOLTAGE") "6.3V")
        (field (name "DB_MANUFACTURER_PART") "SAMSUNG    CL32A227MQVNNNE")
        (field (name "DB_APPROVED_BY") "VSN")
      )
      (libsource (lib "Database_Libs1") (part "C"))
    )
    (comp (ref "C_65")
      (value "C")
      (footprint "SMD_1210_CAPC3225X279N")
      (fields
        (field (name "DB_PART_NUMBER") "CAP000047355")
        (field (name "DB_VALUE") "220uF")
        (field (name "DB_TOLERANCE") "20%")
        (field (name "DB_VOLTAGE") "6.3V")
        (field (name "DB_MANUFACTURER_PART") "SAMSUNG    CL32A227MQVNNNE")
        (field (name "DB_APPROVED_BY") "VSN")
      )
      (libsource (lib "Database_Libs1") (part "C"))
    )
    (comp (ref "C_66")
      (value "C")
      (footprint "SMD_1210_CAPC3225X279N")
      (fields
        (field (name "DB_PART_NUMBER") "CAP000047355")
        (field (name "DB_VALUE") "220uF")
        (field (name "DB_TOLERANCE") "20%")
        (field (name "DB_VOLTAGE") "6.3V")
        (field (name "DB_MANUFACTURER_PART") "SAMSUNG    CL32A227MQVNNNE")
        (field (name "DB_APPROVED_BY") "VSN")
      )
      (libsource (lib "Database_Libs1") (part "C"))
    )
    (comp (ref "C_67")
      (value "C")
      (footprint "SMD_1210_CAPC3225X279N")
      (fields
        (field (name "DB_PART_NUMBER") "CAP000047355")
        (field (name "DB_VALUE") "220uF")
        (field (name "DB_TOLERANCE") "20%")
        (field (name "DB_VOLTAGE") "6.3V")
        (field (name "DB_MANUFACTURER_PART") "SAMSUNG    CL32A227MQVNNNE")
        (field (name "DB_APPROVED_BY") "VSN")
      )
      (libsource (lib "Database_Libs1") (part "C"))
    )
    (comp (ref "C_68")
      (value "C")
      (footprint "SMD_1210_CAPC3225X279N")
      (fields
        (field (name "DB_PART_NUMBER") "CAP000047355")
        (field (name "DB_VALUE") "220uF")
        (field (name "DB_TOLERANCE") "20%")
        (field (name "DB_VOLTAGE") "6.3V")
        (field (name "DB_MANUFACTURER_PART") "SAMSUNG    CL32A227MQVNNNE")
        (field (name "DB_APPROVED_BY") "VSN")
      )
      (libsource (lib "Database_Libs1") (part "C"))
    )
    (comp (ref "C_69")
      (value "C")
      (footprint "SMD_1210_CAPC3225X279N")
      (fields
        (field (name "DB_PART_NUMBER") "CAP000047355")
        (field (name "DB_VALUE") "220uF")
        (field (name "DB_TOLERANCE") "20%")
        (field (name "DB_VOLTAGE") "6.3V")
        (field (name "DB_MANUFACTURER_PART") "SAMSUNG    CL32A227MQVNNNE")
        (field (name "DB_APPROVED_BY") "VSN")
      )
      (libsource (lib "Database_Libs1") (part "C"))
    )
    (comp (ref "C_70")
      (value "C")
      (footprint "SMD_1210_CAPC3225X279N")
      (fields
        (field (name "DB_PART_NUMBER") "CAP000047355")
        (field (name "DB_VALUE") "220uF")
        (field (name "DB_TOLERANCE") "20%")
        (field (name "DB_VOLTAGE") "6.3V")
        (field (name "DB_MANUFACTURER_PART") "SAMSUNG    CL32A227MQVNNNE")
        (field (name "DB_APPROVED_BY") "VSN")
      )
      (libsource (lib "Database_Libs1") (part "C"))
    )
    (comp (ref "C_71")
      (value "C")
      (footprint "SMD_1210_CAPC3225X279N")
      (fields
        (field (name "DB_PART_NUMBER") "CAP000047355")
        (field (name "DB_VALUE") "220uF")
        (field (name "DB_TOLERANCE") "20%")
        (field (name "DB_VOLTAGE") "6.3V")
        (field (name "DB_MANUFACTURER_PART") "SAMSUNG    CL32A227MQVNNNE")
        (field (name "DB_APPROVED_BY") "VSN")
      )
      (libsource (lib "Database_Libs1") (part "C"))
    )
    (comp (ref "C_72")
      (value "C")
      (footprint "SMD_1210_CAPC3225X279N")
      (fields
        (field (name "DB_PART_NUMBER") "CAP000047355")
        (field (name "DB_VALUE") "220uF")
        (field (name "DB_TOLERANCE") "20%")
        (field (name "DB_VOLTAGE") "6.3V")
        (field (name "DB_MANUFACTURER_PART") "SAMSUNG    CL32A227MQVNNNE")
        (field (name "DB_APPROVED_BY") "VSN")
      )
      (libsource (lib "Database_Libs1") (part "C"))
    )
    (comp (ref "D1")
      (value "D_STKY_DUAL_A1A2CC3")
      (footprint "SMD_SOT23_SOT95P240X120-3N")
      (fields
        (field (name "DB_PART_NUMBER") "DDE000000490")
        (field (name "DB_VALUE") "BAT54C")
        (field (name "DB_MANUFACTURER_PART") "Diodes        BAT54C")
        (field (name "DB_APPROVED_BY") "ISHIDDEN=T")
      )
      (libsource (lib "Database_Libs1") (part "D_STKY_DUAL_A1A2CC3"))
    )
    (comp (ref "D2")
      (value "D_STKY_DUAL_A1A2CC3")
      (footprint "SMD_SOT23_SOT95P240X120-3N")
      (fields
        (field (name "DB_PART_NUMBER") "DDE000000490")
        (field (name "DB_VALUE") "BAT54C")
        (field (name "DB_MANUFACTURER_PART") "Diodes        BAT54C")
        (field (name "DB_APPROVED_BY") "ISHIDDEN=T")
      )
      (libsource (lib "Database_Libs1") (part "D_STKY_DUAL_A1A2CC3"))
    )
    (comp (ref "D3")
      (value "D_STKY_DUAL_A1A2CC3")
      (footprint "SMD_SOT23_SOT95P240X120-3N")
      (fields
        (field (name "DB_PART_NUMBER") "DDE000000490")
        (field (name "DB_VALUE") "BAT54C")
        (field (name "DB_MANUFACTURER_PART") "Diodes        BAT54C")
        (field (name "DB_APPROVED_BY") "ISHIDDEN=T")
      )
      (libsource (lib "Database_Libs1") (part "D_STKY_DUAL_A1A2CC3"))
    )
    (comp (ref "D4")
      (value "Red SML210VT ROHM")
      (footprint "SMD_0805_LED2012X100N")
      (libsource (lib "EPIQ_DND_CIS_Library") (part "LED_2"))
    )
    (comp (ref "D5")
      (value "Green 	SML210MT ROHM")
      (footprint "SMD_0805_LED2012X100N")
      (libsource (lib "EPIQ_DND_CIS_Library") (part "LED_2"))
    )
    (comp (ref "D6")
      (value "Yellow SML210YT ROHM")
      (footprint "SMD_0805_LED2012X100N")
      (libsource (lib "EPIQ_DND_CIS_Library") (part "LED_2"))
    )
    (comp (ref "D7")
      (value "Orange 	SML210DT ROHM")
      (footprint "SMD_0805_LED2012X100N")
      (libsource (lib "EPIQ_DND_CIS_Library") (part "LED_2"))
    )
    (comp (ref "D8")
      (value "D_STKY")
      (footprint "SMD_DO214AC_SMA")
      (fields
        (field (name "DB_PART_NUMBER") "DDE000000580")
        (field (name "DB_VALUE") "B140")
        (field (name "DB_MANUFACTURER_PART") "Diodes        B140")
        (field (name "DB_APPROVED_BY") "ISHIDDEN=T")
      )
      (libsource (lib "Database_Libs1") (part "D_STKY"))
    )
    (comp (ref "D9")
      (value "D_TVS_QUAD_C1A2C3C4A5C6")
      (footprint "SMD_SOT457_SOT95P275X110-6N")
      (fields
        (field (name "DB_PART_NUMBER") "DDE000002846")
        (field (name "DB_VALUE") "SMS05T1G")
        (field (name "DB_MANUFACTURER_PART") "ON SEMICONDUCTOR        SMS05T1G")
        (field (name "DB_APPROVED_BY") "VSN")
      )
      (libsource (lib "Database_Libs1") (part "D_TVS_QUAD_C1A2C3C4A5C6"))
    )
    (comp (ref "D10")
      (value "D_STKY")
      (footprint "SMD_DO214AC_SMA")
      (fields
        (field (name "DB_PART_NUMBER") "DDE000000580")
        (field (name "DB_VALUE") "B140")
        (field (name "DB_MANUFACTURER_PART") "Diodes        B140")
        (field (name "DB_APPROVED_BY") "ISHIDDEN=T")
      )
      (libsource (lib "Database_Libs1") (part "D_STKY"))
    )
    (comp (ref "D11")
      (value "D_STKY")
      (footprint "SMD_DO214AC_SMA")
      (fields
        (field (name "DB_PART_NUMBER") "DDE000000580")
        (field (name "DB_VALUE") "B140")
        (field (name "DB_MANUFACTURER_PART") "Diodes        B140")
        (field (name "DB_APPROVED_BY") "ISHIDDEN=T")
      )
      (libsource (lib "Database_Libs1") (part "D_STKY"))
    )
    (comp (ref "D12")
      (value "D_TVS_UNI")
      (footprint "SMD_DO214AC_SMC")
      (fields
        (field (name "DB_PART_NUMBER") "DDE000001725")
        (field (name "DB_VALUE") "SMCJ12A")
        (field (name "DB_MANUFACTURER_PART") "Diodes        SMCJ12A")
        (field (name "DB_APPROVED_BY") "ISHIDDEN=T")
      )
      (libsource (lib "Database_Libs1") (part "D_TVS_UNI"))
    )
    (comp (ref "FB1")
      (value "L_FERRITE_BEAD")
      (footprint "SMD_0805_INDC2012X105N")
      (fields
        (field (name "DB_PART_NUMBER") "IND000000029")
        (field (name "DB_VALUE") "220 Ohms")
        (field (name "DB_CURRENT") "2A")
        (field (name "DB_MANUFACTURER_PART") "MURATA       BLM21PG221SN1D")
        (field (name "DB_APPROVED_BY") "VSN")
      )
      (libsource (lib "Database_Libs1") (part "L_FERRITE_BEAD"))
    )
    (comp (ref "FID1")
      (value "FIDUCIAL")
      (footprint "FID100X200")
      (fields
        (field (name "DB_PART_NUMBER") "FID000000001")
        (field (name "DB_MANUFACTURER_PART") "ISHIDDEN=T")
        (field (name "DB_APPROVED_BY") "ISHIDDEN=T")
      )
      (libsource (lib "Database_Libs1") (part "FIDUCIAL"))
    )
    (comp (ref "FID2")
      (value "FIDUCIAL")
      (footprint "FID100X200")
      (fields
        (field (name "DB_PART_NUMBER") "FID000000001")
        (field (name "DB_MANUFACTURER_PART") "ISHIDDEN=T")
        (field (name "DB_APPROVED_BY") "ISHIDDEN=T")
      )
      (libsource (lib "Database_Libs1") (part "FIDUCIAL"))
    )
    (comp (ref "J1")
      (value "CON_5PINS")
      (footprint "PTH_HDRV05W64P254_1X05")
      (fields
        (field (name "DB_PART_NUMBER") "CON000000006")
        (field (name "DB_VALUE") "CONN PCB 5P M S")
        (field (name "DB_MANUFACTURER_PART") "W+P        143-12-005-00")
        (field (name "DB_APPROVED_BY") "VSN")
      )
      (libsource (lib "Database_Libs1") (part "CON_5PINS"))
    )
    (comp (ref "J2")
      (value "CON_USB_MINI_1")
      (footprint "SMD_CON-CVILUX-CU04-SCM15B0")
      (fields
        (field (name "DB_PART_NUMBER") "CON000000048")
        (field (name "DB_VALUE") "USB MINI")
        (field (name "DB_MANUFACTURER_PART") "CVILUX       CU04-SCM15B0-R0-LF")
        (field (name "DB_APPROVED_BY") "VSN")
      )
      (libsource (lib "Database_Libs1") (part "CON_USB_MINI_1"))
    )
    (comp (ref "J3")
      (value "CON_3PINS")
      (footprint "PTH_CON_HD-351-3P")
      (fields
        (field (name "DB_PART_NUMBER") "CON000000272")
        (field (name "DB_VALUE") "HD-351-3P")
        (field (name "DB_MANUFACTURER_PART") "HOW DER      HD-351-3P")
        (field (name "DB_APPROVED_BY") "VSN")
      )
      (libsource (lib "Database_Libs1") (part "CON_3PINS"))
    )
    (comp (ref "J4")
      (value "CON_2ROWS_6PINS_1")
      (footprint "PTH_CON_WR-MRC4-6P")
      (fields
        (field (name "DB_PART_NUMBER") "CON000000271")
        (field (name "DB_VALUE") "WR-MPC4")
        (field (name "DB_MANUFACTURER_PART") "WE         649 006 295 22")
        (field (name "DB_APPROVED_BY") "VSN")
      )
      (libsource (lib "Database_Libs1") (part "CON_2ROWS_6PINS_1"))
    )
    (comp (ref "J5")
      (value "CON_1PIN")
      (footprint "PTH_MTG400_700")
      (fields
        (field (name "DB_PART_NUMBER") "MTH000000030")
        (field (name "DB_VALUE") "PTH_MTG400_700")
        (field (name "DB_APPROVED_BY") "VSN")
      )
      (libsource (lib "Database_Libs1") (part "CON_1PIN"))
    )
    (comp (ref "J6")
      (value "CON_1PIN")
      (footprint "PTH_MTG400_700")
      (fields
        (field (name "DB_PART_NUMBER") "MTH000000030")
        (field (name "DB_VALUE") "PTH_MTG400_700")
        (field (name "DB_APPROVED_BY") "VSN")
      )
      (libsource (lib "Database_Libs1") (part "CON_1PIN"))
    )
    (comp (ref "J7")
      (value "CON_1PIN")
      (footprint "PTH_MTG400_700")
      (fields
        (field (name "DB_PART_NUMBER") "MTH000000030")
        (field (name "DB_VALUE") "PTH_MTG400_700")
        (field (name "DB_APPROVED_BY") "VSN")
      )
      (libsource (lib "Database_Libs1") (part "CON_1PIN"))
    )
    (comp (ref "J8")
      (value "CON_1PIN")
      (footprint "PTH_MTG400_700")
      (fields
        (field (name "DB_PART_NUMBER") "MTH000000030")
        (field (name "DB_VALUE") "PTH_MTG400_700")
        (field (name "DB_APPROVED_BY") "VSN")
      )
      (libsource (lib "Database_Libs1") (part "CON_1PIN"))
    )
    (comp (ref "J9")
      (value "CON_1PIN")
      (footprint "PTH_MTG400_700")
      (fields
        (field (name "DB_PART_NUMBER") "MTH000000030")
        (field (name "DB_VALUE") "PTH_MTG400_700")
        (field (name "DB_APPROVED_BY") "VSN")
      )
      (libsource (lib "Database_Libs1") (part "CON_1PIN"))
    )
    (comp (ref "J10")
      (value "CON_1PIN")
      (footprint "PTH_MTG400_700")
      (fields
        (field (name "DB_PART_NUMBER") "MTH000000030")
        (field (name "DB_VALUE") "PTH_MTG400_700")
        (field (name "DB_APPROVED_BY") "VSN")
      )
      (libsource (lib "Database_Libs1") (part "CON_1PIN"))
    )
    (comp (ref "J11")
      (value "CON_1PIN")
      (footprint "PTH_MTG400_700")
      (fields
        (field (name "DB_PART_NUMBER") "MTH000000030")
        (field (name "DB_VALUE") "PTH_MTG400_700")
        (field (name "DB_APPROVED_BY") "VSN")
      )
      (libsource (lib "Database_Libs1") (part "CON_1PIN"))
    )
    (comp (ref "J12")
      (value "CON_1PIN")
      (footprint "PTH_MTG400_700")
      (fields
        (field (name "DB_PART_NUMBER") "MTH000000030")
        (field (name "DB_VALUE") "PTH_MTG400_700")
        (field (name "DB_APPROVED_BY") "VSN")
      )
      (libsource (lib "Database_Libs1") (part "CON_1PIN"))
    )
    (comp (ref "J13")
      (value "CON_1PIN")
      (footprint "PTH_MTG400_700")
      (fields
        (field (name "DB_PART_NUMBER") "MTH000000030")
        (field (name "DB_VALUE") "PTH_MTG400_700")
        (field (name "DB_APPROVED_BY") "VSN")
      )
      (libsource (lib "Database_Libs1") (part "CON_1PIN"))
    )
    (comp (ref "J14")
      (value "CON_1PIN")
      (footprint "PTH_MTG400_700")
      (fields
        (field (name "DB_PART_NUMBER") "MTH000000030")
        (field (name "DB_VALUE") "PTH_MTG400_700")
        (field (name "DB_APPROVED_BY") "VSN")
      )
      (libsource (lib "Database_Libs1") (part "CON_1PIN"))
    )
    (comp (ref "J15")
      (value "CON_1PIN")
      (footprint "PTH_MTG400_700")
      (fields
        (field (name "DB_PART_NUMBER") "MTH000000030")
        (field (name "DB_VALUE") "PTH_MTG400_700")
        (field (name "DB_APPROVED_BY") "VSN")
      )
      (libsource (lib "Database_Libs1") (part "CON_1PIN"))
    )
    (comp (ref "L1")
      (value "SLC1480-201MLD")
      (footprint "SMT_INDM135130X800N")
      (libsource (lib "EPIQ_DND_CIS_Library") (part "L"))
    )
    (comp (ref "L2")
      (value "SLC1480-201MLD")
      (footprint "SMT_INDM135130X800N")
      (libsource (lib "EPIQ_DND_CIS_Library") (part "L"))
    )
    (comp (ref "L3")
      (value "SLC1480-201MLD")
      (footprint "SMT_INDM135130X800N")
      (libsource (lib "EPIQ_DND_CIS_Library") (part "L"))
    )
    (comp (ref "Q1")
      (value "MOS_N_D1_S1S2S3G4D5D6D7D8")
      (footprint "SMD_SOIC127P600X110-9AN")
      (fields
        (field (name "DB_PART_NUMBER") "TRA000001604")
        (field (name "DB_VALUE") "AP1RA03GMT-HF-3")
        (field (name "DB_MANUFACTURER_PART") "ADVANCED POWER ELECTRONICS CORP      AP1RA03GMT-HF-3")
        (field (name "DB_APPROVED_BY") "VSN")
      )
      (libsource (lib "Database_Libs1") (part "MOS_N_D1_S1S2S3G4D5D6D7D8"))
    )
    (comp (ref "Q2")
      (value "MOS_N_D1_S1S2S3G4D5D6D7D8")
      (footprint "SMD_SOIC127P600X110-9AN")
      (fields
        (field (name "DB_PART_NUMBER") "TRA000001604")
        (field (name "DB_VALUE") "AP1RA03GMT-HF-3")
        (field (name "DB_MANUFACTURER_PART") "ADVANCED POWER ELECTRONICS CORP      AP1RA03GMT-HF-3")
        (field (name "DB_APPROVED_BY") "VSN")
      )
      (libsource (lib "Database_Libs1") (part "MOS_N_D1_S1S2S3G4D5D6D7D8"))
    )
    (comp (ref "Q3")
      (value "MOS_N_D1_S1S2S3G4D5D6D7D8")
      (footprint "SMD_SOIC127P600X110-9AN")
      (fields
        (field (name "DB_PART_NUMBER") "TRA000001604")
        (field (name "DB_VALUE") "AP1RA03GMT-HF-3")
        (field (name "DB_MANUFACTURER_PART") "ADVANCED POWER ELECTRONICS CORP      AP1RA03GMT-HF-3")
        (field (name "DB_APPROVED_BY") "VSN")
      )
      (libsource (lib "Database_Libs1") (part "MOS_N_D1_S1S2S3G4D5D6D7D8"))
    )
    (comp (ref "Q4")
      (value "MOS_N_D1_S1S2S3G4D5D6D7D8")
      (footprint "SMD_SOIC127P600X110-9AN")
      (fields
        (field (name "DB_PART_NUMBER") "TRA000001604")
        (field (name "DB_VALUE") "AP1RA03GMT-HF-3")
        (field (name "DB_MANUFACTURER_PART") "ADVANCED POWER ELECTRONICS CORP      AP1RA03GMT-HF-3")
        (field (name "DB_APPROVED_BY") "VSN")
      )
      (libsource (lib "Database_Libs1") (part "MOS_N_D1_S1S2S3G4D5D6D7D8"))
    )
    (comp (ref "Q5")
      (value "MOS_N_D1_S1S2S3G4D5D6D7D8")
      (footprint "SMD_SOIC127P600X110-9AN")
      (fields
        (field (name "DB_PART_NUMBER") "TRA000001604")
        (field (name "DB_VALUE") "AP1RA03GMT-HF-3")
        (field (name "DB_MANUFACTURER_PART") "ADVANCED POWER ELECTRONICS CORP      AP1RA03GMT-HF-3")
        (field (name "DB_APPROVED_BY") "VSN")
      )
      (libsource (lib "Database_Libs1") (part "MOS_N_D1_S1S2S3G4D5D6D7D8"))
    )
    (comp (ref "Q6")
      (value "MOS_N_D1_S1S2S3G4D5D6D7D8")
      (footprint "SMD_SOIC127P600X110-9AN")
      (fields
        (field (name "DB_PART_NUMBER") "TRA000001604")
        (field (name "DB_VALUE") "AP1RA03GMT-HF-3")
        (field (name "DB_MANUFACTURER_PART") "ADVANCED POWER ELECTRONICS CORP      AP1RA03GMT-HF-3")
        (field (name "DB_APPROVED_BY") "VSN")
      )
      (libsource (lib "Database_Libs1") (part "MOS_N_D1_S1S2S3G4D5D6D7D8"))
    )
    (comp (ref "Q7")
      (value "MOS_N_D1_S1S2S3G4D5D6D7D8")
      (footprint "SMD_SOIC127P600X110-9AN")
      (fields
        (field (name "DB_PART_NUMBER") "TRA000001604")
        (field (name "DB_VALUE") "AP1RA03GMT-HF-3")
        (field (name "DB_MANUFACTURER_PART") "ADVANCED POWER ELECTRONICS CORP      AP1RA03GMT-HF-3")
        (field (name "DB_APPROVED_BY") "VSN")
      )
      (libsource (lib "Database_Libs1") (part "MOS_N_D1_S1S2S3G4D5D6D7D8"))
    )
    (comp (ref "Q8")
      (value "MOS_N_D1_S1S2S3G4D5D6D7D8")
      (footprint "SMD_SOIC127P600X110-9AN")
      (fields
        (field (name "DB_PART_NUMBER") "TRA000001604")
        (field (name "DB_VALUE") "AP1RA03GMT-HF-3")
        (field (name "DB_MANUFACTURER_PART") "ADVANCED POWER ELECTRONICS CORP      AP1RA03GMT-HF-3")
        (field (name "DB_APPROVED_BY") "VSN")
      )
      (libsource (lib "Database_Libs1") (part "MOS_N_D1_S1S2S3G4D5D6D7D8"))
    )
    (comp (ref "Q9")
      (value "MOS_N_D1_S1S2S3G4D5D6D7D8")
      (footprint "SMD_SOIC127P600X110-9AN")
      (fields
        (field (name "DB_PART_NUMBER") "TRA000001604")
        (field (name "DB_VALUE") "AP1RA03GMT-HF-3")
        (field (name "DB_MANUFACTURER_PART") "ADVANCED POWER ELECTRONICS CORP      AP1RA03GMT-HF-3")
        (field (name "DB_APPROVED_BY") "VSN")
      )
      (libsource (lib "Database_Libs1") (part "MOS_N_D1_S1S2S3G4D5D6D7D8"))
    )
    (comp (ref "R1")
      (value "R")
      (footprint "SMD_0603_RESC1608X55N")
      (fields
        (field (name "DB_PART_NUMBER") "RES000008663")
        (field (name "DB_VALUE") "10k")
        (field (name "DB_TOLERANCE") "1%")
        (field (name "DB_MANUFACTURER_PART") "YAGEO    RC0603FR-0710KL")
        (field (name "DB_APPROVED_BY") "VSN")
      )
      (libsource (lib "Database_Libs1") (part "R"))
    )
    (comp (ref "R2")
      (value "R")
      (footprint "SMD_0603_RESC1608X55N")
      (fields
        (field (name "DB_PART_NUMBER") "RES000008663")
        (field (name "DB_VALUE") "10k")
        (field (name "DB_TOLERANCE") "1%")
        (field (name "DB_MANUFACTURER_PART") "YAGEO    RC0603FR-0710KL")
        (field (name "DB_APPROVED_BY") "VSN")
      )
      (libsource (lib "Database_Libs1") (part "R"))
    )
    (comp (ref "R3")
      (value "R")
      (footprint "SMD_0603_RESC1608X55N")
      (fields
        (field (name "DB_PART_NUMBER") "RES000008663")
        (field (name "DB_VALUE") "10k")
        (field (name "DB_TOLERANCE") "1%")
        (field (name "DB_MANUFACTURER_PART") "YAGEO    RC0603FR-0710KL")
        (field (name "DB_APPROVED_BY") "VSN")
      )
      (libsource (lib "Database_Libs1") (part "R"))
    )
    (comp (ref "R4")
      (value "R")
      (footprint "SMD_0603_RESC1608X55N")
      (fields
        (field (name "DB_PART_NUMBER") "RES000008663")
        (field (name "DB_VALUE") "10k")
        (field (name "DB_TOLERANCE") "1%")
        (field (name "DB_MANUFACTURER_PART") "YAGEO    RC0603FR-0710KL")
        (field (name "DB_APPROVED_BY") "VSN")
      )
      (libsource (lib "Database_Libs1") (part "R"))
    )
    (comp (ref "R5")
      (value "R")
      (footprint "SMD_0603_RESC1608X55N")
      (fields
        (field (name "DB_PART_NUMBER") "RES000008663")
        (field (name "DB_VALUE") "10k")
        (field (name "DB_TOLERANCE") "1%")
        (field (name "DB_MANUFACTURER_PART") "YAGEO    RC0603FR-0710KL")
        (field (name "DB_APPROVED_BY") "VSN")
      )
      (libsource (lib "Database_Libs1") (part "R"))
    )
    (comp (ref "R6")
      (value "R")
      (footprint "SMD_0603_RESC1608X55N")
      (fields
        (field (name "DB_PART_NUMBER") "RES000008663")
        (field (name "DB_VALUE") "10k")
        (field (name "DB_TOLERANCE") "1%")
        (field (name "DB_MANUFACTURER_PART") "YAGEO    RC0603FR-0710KL")
        (field (name "DB_APPROVED_BY") "VSN")
      )
      (libsource (lib "Database_Libs1") (part "R"))
    )
    (comp (ref "R7")
      (value "R")
      (footprint "SMD_0603_RESC1608X55N")
      (fields
        (field (name "DB_PART_NUMBER") "RES000008663")
        (field (name "DB_VALUE") "10k")
        (field (name "DB_TOLERANCE") "1%")
        (field (name "DB_MANUFACTURER_PART") "YAGEO    RC0603FR-0710KL")
        (field (name "DB_APPROVED_BY") "VSN")
      )
      (libsource (lib "Database_Libs1") (part "R"))
    )
    (comp (ref "R8")
      (value "R")
      (footprint "SMD_0603_RESC1608X55N")
      (fields
        (field (name "DB_PART_NUMBER") "RES000008663")
        (field (name "DB_VALUE") "10k")
        (field (name "DB_TOLERANCE") "1%")
        (field (name "DB_MANUFACTURER_PART") "YAGEO    RC0603FR-0710KL")
        (field (name "DB_APPROVED_BY") "VSN")
      )
      (libsource (lib "Database_Libs1") (part "R"))
    )
    (comp (ref "R17")
      (value "R")
      (footprint "SMD_0603_RESC1608X55N")
      (fields
        (field (name "DB_PART_NUMBER") "RES000008663")
        (field (name "DB_VALUE") "10k")
        (field (name "DB_TOLERANCE") "1%")
        (field (name "DB_MANUFACTURER_PART") "YAGEO    RC0603FR-0710KL")
        (field (name "DB_APPROVED_BY") "VSN")
      )
      (libsource (lib "Database_Libs1") (part "R"))
    )
    (comp (ref "R18")
      (value "R")
      (footprint "SMD_0603_RESC1608X55N")
      (fields
        (field (name "DB_PART_NUMBER") "RES000008663")
        (field (name "DB_VALUE") "10k")
        (field (name "DB_TOLERANCE") "1%")
        (field (name "DB_MANUFACTURER_PART") "YAGEO    RC0603FR-0710KL")
        (field (name "DB_APPROVED_BY") "VSN")
      )
      (libsource (lib "Database_Libs1") (part "R"))
    )
    (comp (ref "R19")
      (value "R")
      (footprint "SMD_0603_RESC1608X55N")
      (fields
        (field (name "DB_PART_NUMBER") "RES000008663")
        (field (name "DB_VALUE") "10k")
        (field (name "DB_TOLERANCE") "1%")
        (field (name "DB_MANUFACTURER_PART") "YAGEO    RC0603FR-0710KL")
        (field (name "DB_APPROVED_BY") "VSN")
      )
      (libsource (lib "Database_Libs1") (part "R"))
    )
    (comp (ref "R20")
      (value "R")
      (footprint "SMD_0603_RESC1608X55N")
      (fields
        (field (name "DB_PART_NUMBER") "RES000008663")
        (field (name "DB_VALUE") "10k")
        (field (name "DB_TOLERANCE") "1%")
        (field (name "DB_MANUFACTURER_PART") "YAGEO    RC0603FR-0710KL")
        (field (name "DB_APPROVED_BY") "VSN")
      )
      (libsource (lib "Database_Libs1") (part "R"))
    )
    (comp (ref "R21")
      (value "R")
      (footprint "SMD_0603_RESC1608X55N")
      (fields
        (field (name "DB_PART_NUMBER") "RES000008663")
        (field (name "DB_VALUE") "10k")
        (field (name "DB_TOLERANCE") "1%")
        (field (name "DB_MANUFACTURER_PART") "YAGEO    RC0603FR-0710KL")
        (field (name "DB_APPROVED_BY") "VSN")
      )
      (libsource (lib "Database_Libs1") (part "R"))
    )
    (comp (ref "R22")
      (value "R")
      (footprint "SMD_0603_RESC1608X55N")
      (fields
        (field (name "DB_PART_NUMBER") "RES000008663")
        (field (name "DB_VALUE") "10k")
        (field (name "DB_TOLERANCE") "1%")
        (field (name "DB_MANUFACTURER_PART") "YAGEO    RC0603FR-0710KL")
        (field (name "DB_APPROVED_BY") "VSN")
      )
      (libsource (lib "Database_Libs1") (part "R"))
    )
    (comp (ref "R23")
      (value "R")
      (footprint "SMD_0603_RESC1608X55N")
      (fields
        (field (name "DB_PART_NUMBER") "RES000008663")
        (field (name "DB_VALUE") "10k")
        (field (name "DB_TOLERANCE") "1%")
        (field (name "DB_MANUFACTURER_PART") "YAGEO    RC0603FR-0710KL")
        (field (name "DB_APPROVED_BY") "VSN")
      )
      (libsource (lib "Database_Libs1") (part "R"))
    )
    (comp (ref "R24")
      (value "R")
      (footprint "SMD_0603_RESC1608X55N")
      (fields
        (field (name "DB_PART_NUMBER") "RES000008663")
        (field (name "DB_VALUE") "10k")
        (field (name "DB_TOLERANCE") "1%")
        (field (name "DB_MANUFACTURER_PART") "YAGEO    RC0603FR-0710KL")
        (field (name "DB_APPROVED_BY") "VSN")
      )
      (libsource (lib "Database_Libs1") (part "R"))
    )
    (comp (ref "R25")
      (value "R")
      (footprint "SMD_0603_RESC1608X55N")
      (fields
        (field (name "DB_PART_NUMBER") "RES000006261")
        (field (name "DB_VALUE") "2.4k")
        (field (name "DB_TOLERANCE") "1%")
        (field (name "DB_MANUFACTURER_PART") "YAGEO    RC0603FR-072K4")
        (field (name "DB_APPROVED_BY") "ISHIDDEN=T")
      )
      (libsource (lib "Database_Libs1") (part "R"))
    )
    (comp (ref "R26")
      (value "R")
      (footprint "SMD_0603_RESC1608X55N")
      (fields
        (field (name "DB_PART_NUMBER") "RES000008663")
        (field (name "DB_VALUE") "10k")
        (field (name "DB_TOLERANCE") "1%")
        (field (name "DB_MANUFACTURER_PART") "YAGEO    RC0603FR-0710KL")
        (field (name "DB_APPROVED_BY") "VSN")
      )
      (libsource (lib "Database_Libs1") (part "R"))
    )
    (comp (ref "R27")
      (value "R")
      (footprint "SMD_0603_RESC1608X55N")
      (fields
        (field (name "DB_PART_NUMBER") "RES000006220")
        (field (name "DB_VALUE") "47R")
        (field (name "DB_TOLERANCE") "1%")
        (field (name "DB_MANUFACTURER_PART") "YAGEO    RC0603FR-0747R")
        (field (name "DB_APPROVED_BY") "ISHIDDEN=T")
      )
      (libsource (lib "Database_Libs1") (part "R"))
    )
    (comp (ref "R30")
      (value "R")
      (footprint "SMD_0603_RESC1608X55N")
      (fields
        (field (name "DB_PART_NUMBER") "RES000006220")
        (field (name "DB_VALUE") "47R")
        (field (name "DB_TOLERANCE") "1%")
        (field (name "DB_MANUFACTURER_PART") "YAGEO    RC0603FR-0747R")
        (field (name "DB_APPROVED_BY") "ISHIDDEN=T")
      )
      (libsource (lib "Database_Libs1") (part "R"))
    )
    (comp (ref "R31")
      (value "R")
      (footprint "SMD_0603_RESC1608X55N")
      (fields
        (field (name "DB_PART_NUMBER") "RES000008663")
        (field (name "DB_VALUE") "10k")
        (field (name "DB_TOLERANCE") "1%")
        (field (name "DB_MANUFACTURER_PART") "YAGEO    RC0603FR-0710KL")
        (field (name "DB_APPROVED_BY") "VSN")
      )
      (libsource (lib "Database_Libs1") (part "R"))
    )
    (comp (ref "R32")
      (value "R")
      (footprint "SMD_0603_RESC1608X55N")
      (fields
        (field (name "DB_PART_NUMBER") "RES000008663")
        (field (name "DB_VALUE") "10k")
        (field (name "DB_TOLERANCE") "1%")
        (field (name "DB_MANUFACTURER_PART") "YAGEO    RC0603FR-0710KL")
        (field (name "DB_APPROVED_BY") "VSN")
      )
      (libsource (lib "Database_Libs1") (part "R"))
    )
    (comp (ref "R33")
      (value "R")
      (footprint "SMD_0603_RESC1608X55N")
      (fields
        (field (name "DB_PART_NUMBER") "RES000008926")
        (field (name "DB_VALUE") "0R")
        (field (name "DB_TOLERANCE") "1%")
        (field (name "DB_MANUFACTURER_PART") "YAGEO    AC0603FR-070RL")
        (field (name "DB_APPROVED_BY") "VSN")
      )
      (libsource (lib "Database_Libs1") (part "R"))
    )
    (comp (ref "R42")
      (value "R")
      (footprint "SMD_1206_RESC3216X65N")
      (fields
        (field (name "DB_PART_NUMBER") "RES000007051")
        (field (name "DB_VALUE") "2R")
        (field (name "DB_TOLERANCE") "5%")
        (field (name "DB_MANUFACTURER_PART") "YAGEO    RC1206JR-072R")
        (field (name "DB_APPROVED_BY") "ISHIDDEN=T")
      )
      (libsource (lib "Database_Libs1") (part "R"))
    )
    (comp (ref "R43")
      (value "R")
      (footprint "SMD_0603_RESC1608X55N")
      (fields
        (field (name "DB_PART_NUMBER") "RES000008663")
        (field (name "DB_VALUE") "10k")
        (field (name "DB_TOLERANCE") "1%")
        (field (name "DB_MANUFACTURER_PART") "YAGEO    RC0603FR-0710KL")
        (field (name "DB_APPROVED_BY") "VSN")
      )
      (libsource (lib "Database_Libs1") (part "R"))
    )
    (comp (ref "R44")
      (value "R")
      (footprint "SMD_0603_RESC1608X55N")
      (fields
        (field (name "DB_PART_NUMBER") "RES000008663")
        (field (name "DB_VALUE") "10k")
        (field (name "DB_TOLERANCE") "1%")
        (field (name "DB_MANUFACTURER_PART") "YAGEO    RC0603FR-0710KL")
        (field (name "DB_APPROVED_BY") "VSN")
      )
      (libsource (lib "Database_Libs1") (part "R"))
    )
    (comp (ref "R45")
      (value "R")
      (footprint "SMD_0603_RESC1608X55N")
      (fields
        (field (name "DB_PART_NUMBER") "RES000008663")
        (field (name "DB_VALUE") "10k")
        (field (name "DB_TOLERANCE") "1%")
        (field (name "DB_MANUFACTURER_PART") "YAGEO    RC0603FR-0710KL")
        (field (name "DB_APPROVED_BY") "VSN")
      )
      (libsource (lib "Database_Libs1") (part "R"))
    )
    (comp (ref "R46")
      (value "R")
      (footprint "SMD_0603_RESC1608X55N")
      (fields
        (field (name "DB_PART_NUMBER") "RES000008663")
        (field (name "DB_VALUE") "10k")
        (field (name "DB_TOLERANCE") "1%")
        (field (name "DB_MANUFACTURER_PART") "YAGEO    RC0603FR-0710KL")
        (field (name "DB_APPROVED_BY") "VSN")
      )
      (libsource (lib "Database_Libs1") (part "R"))
    )
    (comp (ref "R47")
      (value "R")
      (footprint "SMD_1206_RESC3216X65N")
      (fields
        (field (name "DB_PART_NUMBER") "RES000006922")
        (field (name "DB_VALUE") "100R")
        (field (name "DB_TOLERANCE") "1%")
        (field (name "DB_MANUFACTURER_PART") "YAGEO    RC1206FR-07100R")
        (field (name "DB_APPROVED_BY") "ISHIDDEN=T")
      )
      (libsource (lib "Database_Libs1") (part "R"))
    )
    (comp (ref "R48")
      (value "R")
      (footprint "SMD_1206_RESC3216X65N")
      (fields
        (field (name "DB_PART_NUMBER") "RES000008756")
        (field (name "DB_VALUE") "0R")
        (field (name "DB_TOLERANCE") "1%")
        (field (name "DB_MANUFACTURER_PART") "YAGEO    AC1206FR-070RL")
        (field (name "DB_APPROVED_BY") "VSN")
      )
      (libsource (lib "Database_Libs1") (part "R"))
    )
    (comp (ref "R49")
      (value "R")
      (footprint "SMD_1206_RESC3216X65N")
      (fields
        (field (name "DB_PART_NUMBER") "RES000008756")
        (field (name "DB_VALUE") "0R")
        (field (name "DB_TOLERANCE") "1%")
        (field (name "DB_MANUFACTURER_PART") "YAGEO    AC1206FR-070RL")
        (field (name "DB_APPROVED_BY") "VSN")
      )
      (libsource (lib "Database_Libs1") (part "R"))
    )
    (comp (ref "R50")
      (value "R")
      (footprint "SMD_0603_RESC1608X55N")
      (fields
        (field (name "DB_PART_NUMBER") "RES000008663")
        (field (name "DB_VALUE") "10k")
        (field (name "DB_TOLERANCE") "1%")
        (field (name "DB_MANUFACTURER_PART") "YAGEO    RC0603FR-0710KL")
        (field (name "DB_APPROVED_BY") "VSN")
      )
      (libsource (lib "Database_Libs1") (part "R"))
    )
    (comp (ref "R51")
      (value "R")
      (footprint "SMD_0603_RESC1608X55N")
      (fields
        (field (name "DB_PART_NUMBER") "RES000006287")
        (field (name "DB_VALUE") "30k")
        (field (name "DB_TOLERANCE") "1%")
        (field (name "DB_MANUFACTURER_PART") "YAGEO    RC0603FR-0730K")
        (field (name "DB_APPROVED_BY") "ISHIDDEN=T")
      )
      (libsource (lib "Database_Libs1") (part "R"))
    )
    (comp (ref "R52")
      (value "R")
      (footprint "SMD_0603_RESC1608X55N")
      (fields
        (field (name "DB_PART_NUMBER") "RES000008663")
        (field (name "DB_VALUE") "10k")
        (field (name "DB_TOLERANCE") "1%")
        (field (name "DB_MANUFACTURER_PART") "YAGEO    RC0603FR-0710KL")
        (field (name "DB_APPROVED_BY") "VSN")
      )
      (libsource (lib "Database_Libs1") (part "R"))
    )
    (comp (ref "R53")
      (value "R")
      (footprint "SMD_0603_RESC1608X55N")
      (fields
        (field (name "DB_PART_NUMBER") "RES000008663")
        (field (name "DB_VALUE") "10k")
        (field (name "DB_TOLERANCE") "1%")
        (field (name "DB_MANUFACTURER_PART") "YAGEO    RC0603FR-0710KL")
        (field (name "DB_APPROVED_BY") "VSN")
      )
      (libsource (lib "Database_Libs1") (part "R"))
    )
    (comp (ref "R54")
      (value "R")
      (footprint "SMD_0603_RESC1608X55N")
      (fields
        (field (name "DB_PART_NUMBER") "RES000008663")
        (field (name "DB_VALUE") "10k")
        (field (name "DB_TOLERANCE") "1%")
        (field (name "DB_MANUFACTURER_PART") "YAGEO    RC0603FR-0710KL")
        (field (name "DB_APPROVED_BY") "VSN")
      )
      (libsource (lib "Database_Libs1") (part "R"))
    )
    (comp (ref "R55")
      (value "R")
      (footprint "SMD_0603_RESC1608X55N")
      (fields
        (field (name "DB_PART_NUMBER") "RES000006287")
        (field (name "DB_VALUE") "30k")
        (field (name "DB_TOLERANCE") "1%")
        (field (name "DB_MANUFACTURER_PART") "YAGEO    RC0603FR-0730K")
        (field (name "DB_APPROVED_BY") "ISHIDDEN=T")
      )
      (libsource (lib "Database_Libs1") (part "R"))
    )
    (comp (ref "R64")
      (value "R")
      (footprint "SMD_0603_RESC1608X55N")
      (fields
        (field (name "DB_PART_NUMBER") "RES000008663")
        (field (name "DB_VALUE") "10k")
        (field (name "DB_TOLERANCE") "1%")
        (field (name "DB_MANUFACTURER_PART") "YAGEO    RC0603FR-0710KL")
        (field (name "DB_APPROVED_BY") "VSN")
      )
      (libsource (lib "Database_Libs1") (part "R"))
    )
    (comp (ref "R65")
      (value "R")
      (footprint "SMD_0603_RESC1608X55N")
      (fields
        (field (name "DB_PART_NUMBER") "RES000008663")
        (field (name "DB_VALUE") "10k")
        (field (name "DB_TOLERANCE") "1%")
        (field (name "DB_MANUFACTURER_PART") "YAGEO    RC0603FR-0710KL")
        (field (name "DB_APPROVED_BY") "VSN")
      )
      (libsource (lib "Database_Libs1") (part "R"))
    )
    (comp (ref "R66")
      (value "R")
      (footprint "SMD_0603_RESC1608X55N")
      (fields
        (field (name "DB_PART_NUMBER") "RES000008663")
        (field (name "DB_VALUE") "10k")
        (field (name "DB_TOLERANCE") "1%")
        (field (name "DB_MANUFACTURER_PART") "YAGEO    RC0603FR-0710KL")
        (field (name "DB_APPROVED_BY") "VSN")
      )
      (libsource (lib "Database_Libs1") (part "R"))
    )
    (comp (ref "R67")
      (value "R")
      (footprint "SMD_0603_RESC1608X55N")
      (fields
        (field (name "DB_PART_NUMBER") "RES000008663")
        (field (name "DB_VALUE") "10k")
        (field (name "DB_TOLERANCE") "1%")
        (field (name "DB_MANUFACTURER_PART") "YAGEO    RC0603FR-0710KL")
        (field (name "DB_APPROVED_BY") "VSN")
      )
      (libsource (lib "Database_Libs1") (part "R"))
    )
    (comp (ref "TP1")
      (value "TEST_POINT_1")
      (footprint "SMD_TP_100-254")
      (fields
        (field (name "DB_PART_NUMBER") "TPO000000001")
        (field (name "DB_MANUFACTURER_PART") "ISHIDDEN=T")
        (field (name "DB_APPROVED_BY") "ISHIDDEN=T")
      )
      (libsource (lib "Database_Libs1") (part "TEST_POINT_1"))
    )
    (comp (ref "TP2")
      (value "TEST_POINT_1")
      (footprint "SMD_TP_100-254")
      (fields
        (field (name "DB_PART_NUMBER") "TPO000000001")
        (field (name "DB_MANUFACTURER_PART") "ISHIDDEN=T")
        (field (name "DB_APPROVED_BY") "ISHIDDEN=T")
      )
      (libsource (lib "Database_Libs1") (part "TEST_POINT_1"))
    )
    (comp (ref "TP3")
      (value "TEST_POINT_1")
      (footprint "SMD_TP_100-254")
      (fields
        (field (name "DB_PART_NUMBER") "TPO000000001")
        (field (name "DB_MANUFACTURER_PART") "ISHIDDEN=T")
        (field (name "DB_APPROVED_BY") "ISHIDDEN=T")
      )
      (libsource (lib "Database_Libs1") (part "TEST_POINT_1"))
    )
    (comp (ref "TP4")
      (value "TEST_POINT_1")
      (footprint "SMD_TP_100-254")
      (fields
        (field (name "DB_PART_NUMBER") "TPO000000001")
        (field (name "DB_MANUFACTURER_PART") "ISHIDDEN=T")
        (field (name "DB_APPROVED_BY") "ISHIDDEN=T")
      )
      (libsource (lib "Database_Libs1") (part "TEST_POINT_1"))
    )
    (comp (ref "TP5")
      (value "TEST_POINT_1")
      (footprint "SMD_TP_100-254")
      (fields
        (field (name "DB_PART_NUMBER") "TPO000000001")
        (field (name "DB_MANUFACTURER_PART") "ISHIDDEN=T")
        (field (name "DB_APPROVED_BY") "ISHIDDEN=T")
      )
      (libsource (lib "Database_Libs1") (part "TEST_POINT_1"))
    )
    (comp (ref "TP6")
      (value "TEST_POINT_1")
      (footprint "SMD_TP_100-254")
      (fields
        (field (name "DB_PART_NUMBER") "TPO000000001")
        (field (name "DB_MANUFACTURER_PART") "ISHIDDEN=T")
        (field (name "DB_APPROVED_BY") "ISHIDDEN=T")
      )
      (libsource (lib "Database_Libs1") (part "TEST_POINT_1"))
    )
    (comp (ref "TP7")
      (value "TEST_POINT_1")
      (footprint "SMD_TP_100-254")
      (fields
        (field (name "DB_PART_NUMBER") "TPO000000001")
        (field (name "DB_MANUFACTURER_PART") "ISHIDDEN=T")
        (field (name "DB_APPROVED_BY") "ISHIDDEN=T")
      )
      (libsource (lib "Database_Libs1") (part "TEST_POINT_1"))
    )
    (comp (ref "TP8")
      (value "TEST_POINT_1")
      (footprint "SMD_TP_100-254")
      (fields
        (field (name "DB_PART_NUMBER") "TPO000000001")
        (field (name "DB_MANUFACTURER_PART") "ISHIDDEN=T")
        (field (name "DB_APPROVED_BY") "ISHIDDEN=T")
      )
      (libsource (lib "Database_Libs1") (part "TEST_POINT_1"))
    )
    (comp (ref "TP9")
      (value "TEST_POINT_1")
      (footprint "SMD_TP_100-254")
      (fields
        (field (name "DB_PART_NUMBER") "TPO000000001")
        (field (name "DB_MANUFACTURER_PART") "ISHIDDEN=T")
        (field (name "DB_APPROVED_BY") "ISHIDDEN=T")
      )
      (libsource (lib "Database_Libs1") (part "TEST_POINT_1"))
    )
    (comp (ref "TP10")
      (value "TEST_POINT_1")
      (footprint "SMD_TP_100-254")
      (fields
        (field (name "DB_PART_NUMBER") "TPO000000001")
        (field (name "DB_MANUFACTURER_PART") "ISHIDDEN=T")
        (field (name "DB_APPROVED_BY") "ISHIDDEN=T")
      )
      (libsource (lib "Database_Libs1") (part "TEST_POINT_1"))
    )
    (comp (ref "TP11")
      (value "TEST_POINT_1")
      (footprint "SMD_TP_100-254")
      (fields
        (field (name "DB_PART_NUMBER") "TPO000000001")
        (field (name "DB_MANUFACTURER_PART") "ISHIDDEN=T")
        (field (name "DB_APPROVED_BY") "ISHIDDEN=T")
      )
      (libsource (lib "Database_Libs1") (part "TEST_POINT_1"))
    )
    (comp (ref "TP12")
      (value "TEST_POINT_1")
      (footprint "SMD_TP_100-254")
      (fields
        (field (name "DB_PART_NUMBER") "TPO000000001")
        (field (name "DB_MANUFACTURER_PART") "ISHIDDEN=T")
        (field (name "DB_APPROVED_BY") "ISHIDDEN=T")
      )
      (libsource (lib "Database_Libs1") (part "TEST_POINT_1"))
    )
    (comp (ref "TP13")
      (value "TEST_POINT_1")
      (footprint "SMD_TP_100-254")
      (fields
        (field (name "DB_PART_NUMBER") "TPO000000001")
        (field (name "DB_MANUFACTURER_PART") "ISHIDDEN=T")
        (field (name "DB_APPROVED_BY") "ISHIDDEN=T")
      )
      (libsource (lib "Database_Libs1") (part "TEST_POINT_1"))
    )
    (comp (ref "TP14")
      (value "TEST_POINT_1")
      (footprint "SMD_TP_100-254")
      (fields
        (field (name "DB_PART_NUMBER") "TPO000000001")
        (field (name "DB_MANUFACTURER_PART") "ISHIDDEN=T")
        (field (name "DB_APPROVED_BY") "ISHIDDEN=T")
      )
      (libsource (lib "Database_Libs1") (part "TEST_POINT_1"))
    )
    (comp (ref "TP15")
      (value "TEST_POINT_1")
      (footprint "SMD_TP_100-254")
      (fields
        (field (name "DB_PART_NUMBER") "TPO000000001")
        (field (name "DB_MANUFACTURER_PART") "ISHIDDEN=T")
        (field (name "DB_APPROVED_BY") "ISHIDDEN=T")
      )
      (libsource (lib "Database_Libs1") (part "TEST_POINT_1"))
    )
    (comp (ref "TP16")
      (value "TEST_POINT_1")
      (footprint "SMD_TP_100-254")
      (fields
        (field (name "DB_PART_NUMBER") "TPO000000001")
        (field (name "DB_MANUFACTURER_PART") "ISHIDDEN=T")
        (field (name "DB_APPROVED_BY") "ISHIDDEN=T")
      )
      (libsource (lib "Database_Libs1") (part "TEST_POINT_1"))
    )
    (comp (ref "TP17")
      (value "TEST_POINT_1")
      (footprint "SMD_TP_100-254")
      (fields
        (field (name "DB_PART_NUMBER") "TPO000000001")
        (field (name "DB_MANUFACTURER_PART") "ISHIDDEN=T")
        (field (name "DB_APPROVED_BY") "ISHIDDEN=T")
      )
      (libsource (lib "Database_Libs1") (part "TEST_POINT_1"))
    )
    (comp (ref "TP18")
      (value "TEST_POINT_1")
      (footprint "SMD_TP_100-254")
      (fields
        (field (name "DB_PART_NUMBER") "TPO000000001")
        (field (name "DB_MANUFACTURER_PART") "ISHIDDEN=T")
        (field (name "DB_APPROVED_BY") "ISHIDDEN=T")
      )
      (libsource (lib "Database_Libs1") (part "TEST_POINT_1"))
    )
    (comp (ref "TP19")
      (value "TEST_POINT_1")
      (footprint "SMD_TP_100-254")
      (fields
        (field (name "DB_PART_NUMBER") "TPO000000001")
        (field (name "DB_MANUFACTURER_PART") "ISHIDDEN=T")
        (field (name "DB_APPROVED_BY") "ISHIDDEN=T")
      )
      (libsource (lib "Database_Libs1") (part "TEST_POINT_1"))
    )
    (comp (ref "TP20")
      (value "TEST_POINT_1")
      (footprint "SMD_TP_100-254")
      (fields
        (field (name "DB_PART_NUMBER") "TPO000000001")
        (field (name "DB_MANUFACTURER_PART") "ISHIDDEN=T")
        (field (name "DB_APPROVED_BY") "ISHIDDEN=T")
      )
      (libsource (lib "Database_Libs1") (part "TEST_POINT_1"))
    )
    (comp (ref "TP21")
      (value "TEST_POINT_1")
      (footprint "SMD_TP_100-254")
      (fields
        (field (name "DB_PART_NUMBER") "TPO000000001")
        (field (name "DB_MANUFACTURER_PART") "ISHIDDEN=T")
        (field (name "DB_APPROVED_BY") "ISHIDDEN=T")
      )
      (libsource (lib "Database_Libs1") (part "TEST_POINT_1"))
    )
    (comp (ref "TP22")
      (value "TEST_POINT_1")
      (footprint "SMD_TP_100-254")
      (fields
        (field (name "DB_PART_NUMBER") "TPO000000001")
        (field (name "DB_MANUFACTURER_PART") "ISHIDDEN=T")
        (field (name "DB_APPROVED_BY") "ISHIDDEN=T")
      )
      (libsource (lib "Database_Libs1") (part "TEST_POINT_1"))
    )
    (comp (ref "TP23")
      (value "TEST_POINT_1")
      (footprint "SMD_TP_100-254")
      (fields
        (field (name "DB_PART_NUMBER") "TPO000000001")
        (field (name "DB_MANUFACTURER_PART") "ISHIDDEN=T")
        (field (name "DB_APPROVED_BY") "ISHIDDEN=T")
      )
      (libsource (lib "Database_Libs1") (part "TEST_POINT_1"))
    )
    (comp (ref "TP24")
      (value "TEST_POINT_1")
      (footprint "SMD_TP_100-254")
      (fields
        (field (name "DB_PART_NUMBER") "TPO000000001")
        (field (name "DB_MANUFACTURER_PART") "ISHIDDEN=T")
        (field (name "DB_APPROVED_BY") "ISHIDDEN=T")
      )
      (libsource (lib "Database_Libs1") (part "TEST_POINT_1"))
    )
    (comp (ref "TP25")
      (value "TEST_POINT_1")
      (footprint "SMD_TP_100-254")
      (fields
        (field (name "DB_PART_NUMBER") "TPO000000001")
        (field (name "DB_MANUFACTURER_PART") "ISHIDDEN=T")
        (field (name "DB_APPROVED_BY") "ISHIDDEN=T")
      )
      (libsource (lib "Database_Libs1") (part "TEST_POINT_1"))
    )
    (comp (ref "TP26")
      (value "TEST_POINT_1")
      (footprint "SMD_TP_100-254")
      (fields
        (field (name "DB_PART_NUMBER") "TPO000000001")
        (field (name "DB_MANUFACTURER_PART") "ISHIDDEN=T")
        (field (name "DB_APPROVED_BY") "ISHIDDEN=T")
      )
      (libsource (lib "Database_Libs1") (part "TEST_POINT_1"))
    )
    (comp (ref "TP27")
      (value "TEST_POINT_1")
      (footprint "SMD_TP_100-254")
      (fields
        (field (name "DB_PART_NUMBER") "TPO000000001")
        (field (name "DB_MANUFACTURER_PART") "ISHIDDEN=T")
        (field (name "DB_APPROVED_BY") "ISHIDDEN=T")
      )
      (libsource (lib "Database_Libs1") (part "TEST_POINT_1"))
    )
    (comp (ref "TP28")
      (value "TEST_POINT_1")
      (footprint "SMD_TP_100-254")
      (fields
        (field (name "DB_PART_NUMBER") "TPO000000001")
        (field (name "DB_MANUFACTURER_PART") "ISHIDDEN=T")
        (field (name "DB_APPROVED_BY") "ISHIDDEN=T")
      )
      (libsource (lib "Database_Libs1") (part "TEST_POINT_1"))
    )
    (comp (ref "TP29")
      (value "TEST_POINT_1")
      (footprint "SMD_TP_100-254")
      (fields
        (field (name "DB_PART_NUMBER") "TPO000000001")
        (field (name "DB_MANUFACTURER_PART") "ISHIDDEN=T")
        (field (name "DB_APPROVED_BY") "ISHIDDEN=T")
      )
      (libsource (lib "Database_Libs1") (part "TEST_POINT_1"))
    )
    (comp (ref "TP30")
      (value "TEST_POINT_1")
      (footprint "SMD_TP_100-254")
      (fields
        (field (name "DB_PART_NUMBER") "TPO000000001")
        (field (name "DB_MANUFACTURER_PART") "ISHIDDEN=T")
        (field (name "DB_APPROVED_BY") "ISHIDDEN=T")
      )
      (libsource (lib "Database_Libs1") (part "TEST_POINT_1"))
    )
    (comp (ref "TP31")
      (value "TEST_POINT_1")
      (footprint "SMD_TP_100-254")
      (fields
        (field (name "DB_PART_NUMBER") "TPO000000001")
        (field (name "DB_MANUFACTURER_PART") "ISHIDDEN=T")
        (field (name "DB_APPROVED_BY") "ISHIDDEN=T")
      )
      (libsource (lib "Database_Libs1") (part "TEST_POINT_1"))
    )
    (comp (ref "TP32")
      (value "TEST_POINT_1")
      (footprint "SMD_TP_100-254")
      (fields
        (field (name "DB_PART_NUMBER") "TPO000000001")
        (field (name "DB_MANUFACTURER_PART") "ISHIDDEN=T")
        (field (name "DB_APPROVED_BY") "ISHIDDEN=T")
      )
      (libsource (lib "Database_Libs1") (part "TEST_POINT_1"))
    )
    (comp (ref "TP33")
      (value "TEST_POINT_1")
      (footprint "SMD_TP_100-254")
      (fields
        (field (name "DB_PART_NUMBER") "TPO000000001")
        (field (name "DB_MANUFACTURER_PART") "ISHIDDEN=T")
        (field (name "DB_APPROVED_BY") "ISHIDDEN=T")
      )
      (libsource (lib "Database_Libs1") (part "TEST_POINT_1"))
    )
    (comp (ref "TP34")
      (value "TEST_POINT_1")
      (footprint "SMD_TP_100-254")
      (fields
        (field (name "DB_PART_NUMBER") "TPO000000001")
        (field (name "DB_MANUFACTURER_PART") "ISHIDDEN=T")
        (field (name "DB_APPROVED_BY") "ISHIDDEN=T")
      )
      (libsource (lib "Database_Libs1") (part "TEST_POINT_1"))
    )
    (comp (ref "TP35")
      (value "TEST_POINT_1")
      (footprint "SMD_TP_100-254")
      (fields
        (field (name "DB_PART_NUMBER") "TPO000000001")
        (field (name "DB_MANUFACTURER_PART") "ISHIDDEN=T")
        (field (name "DB_APPROVED_BY") "ISHIDDEN=T")
      )
      (libsource (lib "Database_Libs1") (part "TEST_POINT_1"))
    )
    (comp (ref "TP36")
      (value "TEST_POINT_1")
      (footprint "SMD_TP_100-254")
      (fields
        (field (name "DB_PART_NUMBER") "TPO000000001")
        (field (name "DB_MANUFACTURER_PART") "ISHIDDEN=T")
        (field (name "DB_APPROVED_BY") "ISHIDDEN=T")
      )
      (libsource (lib "Database_Libs1") (part "TEST_POINT_1"))
    )
    (comp (ref "TP37")
      (value "TEST_POINT_1")
      (footprint "SMD_TP_100-254")
      (fields
        (field (name "DB_PART_NUMBER") "TPO000000001")
        (field (name "DB_MANUFACTURER_PART") "ISHIDDEN=T")
        (field (name "DB_APPROVED_BY") "ISHIDDEN=T")
      )
      (libsource (lib "Database_Libs1") (part "TEST_POINT_1"))
    )
    (comp (ref "TP38")
      (value "TEST_POINT_1")
      (footprint "SMD_TP_100-254")
      (fields
        (field (name "DB_PART_NUMBER") "TPO000000001")
        (field (name "DB_MANUFACTURER_PART") "ISHIDDEN=T")
        (field (name "DB_APPROVED_BY") "ISHIDDEN=T")
      )
      (libsource (lib "Database_Libs1") (part "TEST_POINT_1"))
    )
    (comp (ref "TP39")
      (value "TEST_POINT_1")
      (footprint "SMD_TP_100-254")
      (fields
        (field (name "DB_PART_NUMBER") "TPO000000001")
        (field (name "DB_MANUFACTURER_PART") "ISHIDDEN=T")
        (field (name "DB_APPROVED_BY") "ISHIDDEN=T")
      )
      (libsource (lib "Database_Libs1") (part "TEST_POINT_1"))
    )
    (comp (ref "TP40")
      (value "TEST_POINT_1")
      (footprint "SMD_TP_100-254")
      (fields
        (field (name "DB_PART_NUMBER") "TPO000000001")
        (field (name "DB_MANUFACTURER_PART") "ISHIDDEN=T")
        (field (name "DB_APPROVED_BY") "ISHIDDEN=T")
      )
      (libsource (lib "Database_Libs1") (part "TEST_POINT_1"))
    )
    (comp (ref "TP41")
      (value "TEST_POINT_1")
      (footprint "SMD_TP_100-254")
      (fields
        (field (name "DB_PART_NUMBER") "TPO000000001")
        (field (name "DB_MANUFACTURER_PART") "ISHIDDEN=T")
        (field (name "DB_APPROVED_BY") "ISHIDDEN=T")
      )
      (libsource (lib "Database_Libs1") (part "TEST_POINT_1"))
    )
    (comp (ref "TP42")
      (value "TEST_POINT_1")
      (footprint "SMD_TP_100-254")
      (fields
        (field (name "DB_PART_NUMBER") "TPO000000001")
        (field (name "DB_MANUFACTURER_PART") "ISHIDDEN=T")
        (field (name "DB_APPROVED_BY") "ISHIDDEN=T")
      )
      (libsource (lib "Database_Libs1") (part "TEST_POINT_1"))
    )
    (comp (ref "TP43")
      (value "TEST_POINT_1")
      (footprint "SMD_TP_100-254")
      (fields
        (field (name "DB_PART_NUMBER") "TPO000000001")
        (field (name "DB_MANUFACTURER_PART") "ISHIDDEN=T")
        (field (name "DB_APPROVED_BY") "ISHIDDEN=T")
      )
      (libsource (lib "Database_Libs1") (part "TEST_POINT_1"))
    )
    (comp (ref "TP44")
      (value "TEST_POINT_1")
      (footprint "SMD_TP_100-254")
      (fields
        (field (name "DB_PART_NUMBER") "TPO000000001")
        (field (name "DB_MANUFACTURER_PART") "ISHIDDEN=T")
        (field (name "DB_APPROVED_BY") "ISHIDDEN=T")
      )
      (libsource (lib "Database_Libs1") (part "TEST_POINT_1"))
    )
    (comp (ref "TP45")
      (value "TEST_POINT_1")
      (footprint "SMD_TP_100-254")
      (fields
        (field (name "DB_PART_NUMBER") "TPO000000001")
        (field (name "DB_MANUFACTURER_PART") "ISHIDDEN=T")
        (field (name "DB_APPROVED_BY") "ISHIDDEN=T")
      )
      (libsource (lib "Database_Libs1") (part "TEST_POINT_1"))
    )
    (comp (ref "TP46")
      (value "TEST_POINT_1")
      (footprint "SMD_TP_100-254")
      (fields
        (field (name "DB_PART_NUMBER") "TPO000000001")
        (field (name "DB_MANUFACTURER_PART") "ISHIDDEN=T")
        (field (name "DB_APPROVED_BY") "ISHIDDEN=T")
      )
      (libsource (lib "Database_Libs1") (part "TEST_POINT_1"))
    )
    (comp (ref "TP47")
      (value "TEST_POINT_1")
      (footprint "SMD_TP_100-254")
      (fields
        (field (name "DB_PART_NUMBER") "TPO000000001")
        (field (name "DB_MANUFACTURER_PART") "ISHIDDEN=T")
        (field (name "DB_APPROVED_BY") "ISHIDDEN=T")
      )
      (libsource (lib "Database_Libs1") (part "TEST_POINT_1"))
    )
    (comp (ref "TP48")
      (value "TEST_POINT_1")
      (footprint "SMD_TP_100-254")
      (fields
        (field (name "DB_PART_NUMBER") "TPO000000001")
        (field (name "DB_MANUFACTURER_PART") "ISHIDDEN=T")
        (field (name "DB_APPROVED_BY") "ISHIDDEN=T")
      )
      (libsource (lib "Database_Libs1") (part "TEST_POINT_1"))
    )
    (comp (ref "TP49")
      (value "TEST_POINT_1")
      (footprint "SMD_TP_100-254")
      (fields
        (field (name "DB_PART_NUMBER") "TPO000000001")
        (field (name "DB_MANUFACTURER_PART") "ISHIDDEN=T")
        (field (name "DB_APPROVED_BY") "ISHIDDEN=T")
      )
      (libsource (lib "Database_Libs1") (part "TEST_POINT_1"))
    )
    (comp (ref "TP50")
      (value "TEST_POINT_1")
      (footprint "SMD_TP_100-254")
      (fields
        (field (name "DB_PART_NUMBER") "TPO000000001")
        (field (name "DB_MANUFACTURER_PART") "ISHIDDEN=T")
        (field (name "DB_APPROVED_BY") "ISHIDDEN=T")
      )
      (libsource (lib "Database_Libs1") (part "TEST_POINT_1"))
    )
    (comp (ref "TP51")
      (value "TEST_POINT_1")
      (footprint "SMD_TP_100-254")
      (fields
        (field (name "DB_PART_NUMBER") "TPO000000001")
        (field (name "DB_MANUFACTURER_PART") "ISHIDDEN=T")
        (field (name "DB_APPROVED_BY") "ISHIDDEN=T")
      )
      (libsource (lib "Database_Libs1") (part "TEST_POINT_1"))
    )
    (comp (ref "TP52")
      (value "TEST_POINT_1")
      (footprint "SMD_TP_100-254")
      (fields
        (field (name "DB_PART_NUMBER") "TPO000000001")
        (field (name "DB_MANUFACTURER_PART") "ISHIDDEN=T")
        (field (name "DB_APPROVED_BY") "ISHIDDEN=T")
      )
      (libsource (lib "Database_Libs1") (part "TEST_POINT_1"))
    )
    (comp (ref "TP53")
      (value "TEST_POINT_1")
      (footprint "SMD_TP_100-254")
      (fields
        (field (name "DB_PART_NUMBER") "TPO000000001")
        (field (name "DB_MANUFACTURER_PART") "ISHIDDEN=T")
        (field (name "DB_APPROVED_BY") "ISHIDDEN=T")
      )
      (libsource (lib "Database_Libs1") (part "TEST_POINT_1"))
    )
    (comp (ref "TP54")
      (value "TEST_POINT_1")
      (footprint "SMD_TP_100-254")
      (fields
        (field (name "DB_PART_NUMBER") "TPO000000001")
        (field (name "DB_MANUFACTURER_PART") "ISHIDDEN=T")
        (field (name "DB_APPROVED_BY") "ISHIDDEN=T")
      )
      (libsource (lib "Database_Libs1") (part "TEST_POINT_1"))
    )
    (comp (ref "U1")
      (value "IC_LTC4449")
      (footprint "SMD_SON45P300X200X80-9N")
      (fields
        (field (name "DB_PART_NUMBER") "DRV000000079")
        (field (name "DB_VALUE") "LTC4449EDCB#TRPBF")
        (field (name "DB_MANUFACTURER_PART") "LINEAR       LTC4449EDCB#TRPBF")
        (field (name "DB_APPROVED_BY") "VSN")
      )
      (libsource (lib "Database_Libs1") (part "IC_LTC4449"))
    )
    (comp (ref "U2")
      (value "IC_LTC4449")
      (footprint "SMD_SON45P300X200X80-9N")
      (fields
        (field (name "DB_PART_NUMBER") "DRV000000079")
        (field (name "DB_VALUE") "LTC4449EDCB#TRPBF")
        (field (name "DB_MANUFACTURER_PART") "LINEAR       LTC4449EDCB#TRPBF")
        (field (name "DB_APPROVED_BY") "VSN")
      )
      (libsource (lib "Database_Libs1") (part "IC_LTC4449"))
    )
    (comp (ref "U3")
      (value "IC_LTC4449")
      (footprint "SMD_SON45P300X200X80-9N")
      (fields
        (field (name "DB_PART_NUMBER") "DRV000000079")
        (field (name "DB_VALUE") "LTC4449EDCB#TRPBF")
        (field (name "DB_MANUFACTURER_PART") "LINEAR       LTC4449EDCB#TRPBF")
        (field (name "DB_APPROVED_BY") "VSN")
      )
      (libsource (lib "Database_Libs1") (part "IC_LTC4449"))
    )
    (comp (ref "U4")
      (value "GC3355Q64")
      (footprint "SMT_QFN40P800X800X90-65N")
      (description "GridSeed")
      (libsource (lib "altium-import") (part "root_0__*"))
    )
    (comp (ref "U5")
      (value "GC3355Q64")
      (footprint "SMT_QFN40P800X800X90-65N")
      (description "GridSeed")
      (libsource (lib "altium-import") (part "root_0__*"))
    )
    (comp (ref "U6")
      (value "GC3355Q64")
      (footprint "SMT_QFN40P800X800X90-65N")
      (description "GridSeed")
      (libsource (lib "altium-import") (part "root_0__*"))
    )
    (comp (ref "U7")
      (value "GC3355Q64")
      (footprint "SMT_QFN40P800X800X90-65N")
      (description "GridSeed")
      (libsource (lib "altium-import") (part "root_0__*"))
    )
    (comp (ref "U8")
      (value "IC_DSPIC33EP256MU806-QFN64")
      (footprint "SMD_QFP50P1200X1200X120-64N")
      (fields
        (field (name "DB_PART_NUMBER") "MCU000000070")
        (field (name "DB_VALUE") "dsPIC33EP256MU806")
        (field (name "DB_MANUFACTURER_PART") "MICROCHIP        DSPIC33EP256MU806-E/PT")
        (field (name "DB_APPROVED_BY") "VSN")
      )
      (libsource (lib "Database_Libs1") (part "IC_DSPIC33EP256MU806-QFN64"))
    )
    (comp (ref "U9")
      (value "GC3355Q64")
      (footprint "SMT_QFN40P800X800X90-65N")
      (description "GridSeed")
      (libsource (lib "altium-import") (part "root_0__*"))
    )
    (comp (ref "U10")
      (value "GC3355Q64")
      (footprint "SMT_QFN40P800X800X90-65N")
      (description "GridSeed")
      (libsource (lib "altium-import") (part "root_0__*"))
    )
    (comp (ref "U11")
      (value "GC3355Q64")
      (footprint "SMT_QFN40P800X800X90-65N")
      (description "GridSeed")
      (libsource (lib "altium-import") (part "root_0__*"))
    )
    (comp (ref "U12")
      (value "GC3355Q64")
      (footprint "SMT_QFN40P800X800X90-65N")
      (description "GridSeed")
      (libsource (lib "altium-import") (part "root_0__*"))
    )
    (comp (ref "U13")
      (value "(OPT) LM7805")
      (footprint "SMD_SOIC127P600X175-8N")
      (fields
        (field (name "DB_PART_NUMBER") "PSU000000125")
        (field (name "DB_VALUE") "AP78L05SG-13")
        (field (name "DB_MANUFACTURER_PART") "DIODES        AP78L05SG-13")
        (field (name "DB_APPROVED_BY") "VSN")
      )
      (libsource (lib "Database_Libs1") (part "IC_LM2931AD-5.0R2G_SO-8"))
    )
    (comp (ref "U14")
      (value "IC_TLV70033QDDCRQ1")
      (footprint "SMD_SOT95P280X135-5N")
      (fields
        (field (name "DB_PART_NUMBER") "PSU000000126")
        (field (name "DB_VALUE") "BU33TD3WG-TR")
        (field (name "DB_MANUFACTURER_PART") "ROHM     BU33TD3WG-TR")
        (field (name "DB_APPROVED_BY") "VSN")
      )
      (libsource (lib "Database_Libs1") (part "IC_TLV70033QDDCRQ1"))
    )
    (comp (ref "U15")
      (value "IC_BDXXKA5WF")
      (footprint "SMD_SOIC127P620X160-8N")
      (fields
        (field (name "DB_PART_NUMBER") "PSU000000127")
        (field (name "DB_VALUE") "BD33KA5WF-E2")
        (field (name "DB_MANUFACTURER_PART") "ROHM        BD33KA5WF-E2")
        (field (name "DB_APPROVED_BY") "VSN")
      )
      (libsource (lib "Database_Libs1") (part "IC_BDXXKA5WF"))
    )
    (comp (ref "U16")
      (value "IC_IN1OUT3GND4")
      (footprint "SMD_TO254P1542X460-3_4N")
      (fields
        (field (name "DB_PART_NUMBER") "PSU000000129")
        (field (name "DB_VALUE") "L7805CD2T-TR")
        (field (name "DB_MANUFACTURER_PART") "ST       L7805CD2T-TR")
        (field (name "DB_APPROVED_BY") "VSN")
      )
      (libsource (lib "Database_Libs1") (part "IC_IN1OUT3GND4"))
    )
    (comp (ref "U17")
      (value "IC_VIN1GND4VOUT3")
      (footprint "SMD_TO229P991X239-4N_DPAK")
      (fields
        (field (name "DB_PART_NUMBER") "PSU000000031")
        (field (name "DB_VALUE") "MC78M05BDTRKG")
        (field (name "DB_MANUFACTURER_PART") "ON Semiconductor       MC78M05BDTRKG")
        (field (name "DB_APPROVED_BY") "VSN")
      )
      (libsource (lib "Database_Libs1") (part "IC_VIN1GND4VOUT3"))
    )
    (comp (ref "U18")
      (value "GC3355Q64")
      (footprint "SMT_QFN40P800X800X90-65N")
      (description "GridSeed")
      (libsource (lib "altium-import") (part "root_0__*"))
    )
    (comp (ref "U19")
      (value "GC3355Q64")
      (footprint "SMT_QFN40P800X800X90-65N")
      (description "GridSeed")
      (libsource (lib "altium-import") (part "root_0__*"))
    )
    (comp (ref "U20")
      (value "GC3355Q64")
      (footprint "SMT_QFN40P800X800X90-65N")
      (description "GridSeed")
      (libsource (lib "altium-import") (part "root_0__*"))
    )
    (comp (ref "U21")
      (value "GC3355Q64")
      (footprint "SMT_QFN40P800X800X90-65N")
      (description "GridSeed")
      (libsource (lib "altium-import") (part "root_0__*"))
    )
    (comp (ref "U22")
      (value "IC_BD00KA5WF")
      (footprint "SMD_SOIC127P620X160-8N")
      (fields
        (field (name "DB_PART_NUMBER") "PSU000000128")
        (field (name "DB_VALUE") "BD00KA5WF-E2")
        (field (name "DB_MANUFACTURER_PART") "ROHM        BD00KA5WF-E2")
        (field (name "DB_APPROVED_BY") "VSN")
      )
      (libsource (lib "Database_Libs1") (part "IC_BD00KA5WF"))
    )
    (comp (ref "U23")
      (value "IC_BD00KA5WF")
      (footprint "SMD_SOIC127P620X160-8N")
      (fields
        (field (name "DB_PART_NUMBER") "PSU000000128")
        (field (name "DB_VALUE") "BD00KA5WF-E2")
        (field (name "DB_MANUFACTURER_PART") "ROHM        BD00KA5WF-E2")
        (field (name "DB_APPROVED_BY") "VSN")
      )
      (libsource (lib "Database_Libs1") (part "IC_BD00KA5WF"))
    )
    (comp (ref "U24")
      (value "GC3355Q64")
      (footprint "SMT_QFN40P800X800X90-65N")
      (description "GridSeed")
      (libsource (lib "altium-import") (part "root_0__*"))
    )
    (comp (ref "U25")
      (value "GC3355Q64")
      (footprint "SMT_QFN40P800X800X90-65N")
      (description "GridSeed")
      (libsource (lib "altium-import") (part "root_0__*"))
    )
    (comp (ref "U26")
      (value "GC3355Q64")
      (footprint "SMT_QFN40P800X800X90-65N")
      (description "GridSeed")
      (libsource (lib "altium-import") (part "root_0__*"))
    )
    (comp (ref "U27")
      (value "GC3355Q64")
      (footprint "SMT_QFN40P800X800X90-65N")
      (description "GridSeed")
      (libsource (lib "altium-import") (part "root_0__*"))
    )
    (comp (ref "Y1")
      (value "XTAL")
      (footprint "SMD_HC49_XTAL1140X480X420N")
      (fields
        (field (name "DB_PART_NUMBER") "OSC000000012")
        (field (name "DB_VALUE") "4.00MHz HC49/4HSMX")
        (field (name "DB_MANUFACTURER_PART") "IQD       4.00MHz HC49/4HSMX")
        (field (name "DB_APPROVED_BY") "VSN")
      )
      (libsource (lib "Database_Libs1") (part "XTAL"))
    )
  )
  (nets
    (net (code "1") (name "/1V") (class "Default")
      (node (ref "C118") (pin "2") (pinfunction "2_2") (pintype "passive"))
      (node (ref "C119") (pin "2") (pinfunction "2_2") (pintype "passive"))
      (node (ref "C12") (pin "2") (pinfunction "2_2") (pintype "passive"))
      (node (ref "C121") (pin "2") (pinfunction "2_2") (pintype "passive"))
      (node (ref "C123") (pin "2") (pinfunction "2_2") (pintype "passive"))
      (node (ref "C124") (pin "2") (pinfunction "2_2") (pintype "passive"))
      (node (ref "C126") (pin "2") (pinfunction "2_2") (pintype "passive"))
      (node (ref "C128") (pin "2") (pinfunction "2_2") (pintype "passive"))
      (node (ref "C129") (pin "2") (pinfunction "2_2") (pintype "passive"))
      (node (ref "C13") (pin "2") (pinfunction "2_2") (pintype "passive"))
      (node (ref "C131") (pin "2") (pinfunction "2_2") (pintype "passive"))
      (node (ref "C133") (pin "2") (pinfunction "2_2") (pintype "passive"))
      (node (ref "C134") (pin "2") (pinfunction "2_2") (pintype "passive"))
      (node (ref "C136") (pin "2") (pinfunction "2_2") (pintype "passive"))
      (node (ref "C14") (pin "2") (pinfunction "2_2") (pintype "passive"))
      (node (ref "C140") (pin "2") (pinfunction "2_2") (pintype "passive"))
      (node (ref "C141") (pin "2") (pinfunction "2_2") (pintype "passive"))
      (node (ref "C142") (pin "2") (pinfunction "2_2") (pintype "passive"))
      (node (ref "C143") (pin "2") (pinfunction "2_2") (pintype "passive"))
      (node (ref "C144") (pin "2") (pinfunction "2_2") (pintype "passive"))
      (node (ref "C145") (pin "2") (pinfunction "2_2") (pintype "passive"))
      (node (ref "C146") (pin "2") (pinfunction "2_2") (pintype "passive"))
      (node (ref "C147") (pin "2") (pinfunction "2_2") (pintype "passive"))
      (node (ref "C148") (pin "2") (pinfunction "2_2") (pintype "passive"))
      (node (ref "C149") (pin "2") (pinfunction "2_2") (pintype "passive"))
      (node (ref "C150") (pin "2") (pinfunction "2_2") (pintype "passive"))
      (node (ref "C151") (pin "2") (pinfunction "2_2") (pintype "passive"))
      (node (ref "C152") (pin "2") (pinfunction "2_2") (pintype "passive"))
      (node (ref "C153") (pin "2") (pinfunction "2_2") (pintype "passive"))
      (node (ref "C154") (pin "2") (pinfunction "2_2") (pintype "passive"))
      (node (ref "C155") (pin "2") (pinfunction "2_2") (pintype "passive"))
      (node (ref "C156") (pin "2") (pinfunction "2_2") (pintype "passive"))
      (node (ref "C157") (pin "2") (pinfunction "2_2") (pintype "passive"))
      (node (ref "C158") (pin "2") (pinfunction "2_2") (pintype "passive"))
      (node (ref "C159") (pin "2") (pinfunction "2_2") (pintype "passive"))
      (node (ref "C160") (pin "2") (pinfunction "2_2") (pintype "passive"))
      (node (ref "C161") (pin "2") (pinfunction "2_2") (pintype "passive"))
      (node (ref "C162") (pin "2") (pinfunction "2_2") (pintype "passive"))
      (node (ref "C163") (pin "2") (pinfunction "2_2") (pintype "passive"))
      (node (ref "C17") (pin "2") (pinfunction "2_2") (pintype "passive"))
      (node (ref "C175") (pin "2") (pinfunction "2_2") (pintype "passive"))
      (node (ref "C176") (pin "2") (pinfunction "2_2") (pintype "passive"))
      (node (ref "C177") (pin "2") (pinfunction "2_2") (pintype "passive"))
      (node (ref "C179") (pin "2") (pinfunction "2_2") (pintype "passive"))
      (node (ref "C18") (pin "2") (pinfunction "2_2") (pintype "passive"))
      (node (ref "C180") (pin "2") (pinfunction "2_2") (pintype "passive"))
      (node (ref "C181") (pin "2") (pinfunction "2_2") (pintype "passive"))
      (node (ref "C183") (pin "2") (pinfunction "2_2") (pintype "passive"))
      (node (ref "C184") (pin "2") (pinfunction "2_2") (pintype "passive"))
      (node (ref "C185") (pin "2") (pinfunction "2_2") (pintype "passive"))
      (node (ref "C187") (pin "2") (pinfunction "2_2") (pintype "passive"))
      (node (ref "C188") (pin "2") (pinfunction "2_2") (pintype "passive"))
      (node (ref "C189") (pin "2") (pinfunction "2_2") (pintype "passive"))
      (node (ref "C19") (pin "2") (pinfunction "2_2") (pintype "passive"))
      (node (ref "C22") (pin "2") (pinfunction "2_2") (pintype "passive"))
      (node (ref "C227") (pin "2") (pinfunction "2_2") (pintype "passive"))
      (node (ref "C228") (pin "2") (pinfunction "2_2") (pintype "passive"))
      (node (ref "C23") (pin "2") (pinfunction "2_2") (pintype "passive"))
      (node (ref "C230") (pin "2") (pinfunction "2_2") (pintype "passive"))
      (node (ref "C232") (pin "2") (pinfunction "2_2") (pintype "passive"))
      (node (ref "C233") (pin "2") (pinfunction "2_2") (pintype "passive"))
      (node (ref "C235") (pin "2") (pinfunction "2_2") (pintype "passive"))
      (node (ref "C237") (pin "2") (pinfunction "2_2") (pintype "passive"))
      (node (ref "C238") (pin "2") (pinfunction "2_2") (pintype "passive"))
      (node (ref "C24") (pin "2") (pinfunction "2_2") (pintype "passive"))
      (node (ref "C240") (pin "2") (pinfunction "2_2") (pintype "passive"))
      (node (ref "C242") (pin "2") (pinfunction "2_2") (pintype "passive"))
      (node (ref "C243") (pin "2") (pinfunction "2_2") (pintype "passive"))
      (node (ref "C245") (pin "2") (pinfunction "2_2") (pintype "passive"))
      (node (ref "C247") (pin "2") (pinfunction "2_2") (pintype "passive"))
      (node (ref "C248") (pin "2") (pinfunction "2_2") (pintype "passive"))
      (node (ref "C249") (pin "2") (pinfunction "2_2") (pintype "passive"))
      (node (ref "C25") (pin "2") (pinfunction "2_2") (pintype "passive"))
      (node (ref "C250") (pin "2") (pinfunction "2_2") (pintype "passive"))
      (node (ref "C251") (pin "2") (pinfunction "2_2") (pintype "passive"))
      (node (ref "C252") (pin "2") (pinfunction "2_2") (pintype "passive"))
      (node (ref "C253") (pin "2") (pinfunction "2_2") (pintype "passive"))
      (node (ref "C254") (pin "2") (pinfunction "2_2") (pintype "passive"))
      (node (ref "C255") (pin "2") (pinfunction "2_2") (pintype "passive"))
      (node (ref "C256") (pin "2") (pinfunction "2_2") (pintype "passive"))
      (node (ref "C257") (pin "2") (pinfunction "2_2") (pintype "passive"))
      (node (ref "C258") (pin "2") (pinfunction "2_2") (pintype "passive"))
      (node (ref "C26") (pin "2") (pinfunction "2_2") (pintype "passive"))
      (node (ref "C262") (pin "2") (pinfunction "2_2") (pintype "passive"))
      (node (ref "C263") (pin "2") (pinfunction "2_2") (pintype "passive"))
      (node (ref "C264") (pin "2") (pinfunction "2_2") (pintype "passive"))
      (node (ref "C265") (pin "2") (pinfunction "2_2") (pintype "passive"))
      (node (ref "C266") (pin "2") (pinfunction "2_2") (pintype "passive"))
      (node (ref "C267") (pin "2") (pinfunction "2_2") (pintype "passive"))
      (node (ref "C268") (pin "2") (pinfunction "2_2") (pintype "passive"))
      (node (ref "C269") (pin "2") (pinfunction "2_2") (pintype "passive"))
      (node (ref "C270") (pin "2") (pinfunction "2_2") (pintype "passive"))
      (node (ref "C271") (pin "2") (pinfunction "2_2") (pintype "passive"))
      (node (ref "C272") (pin "2") (pinfunction "2_2") (pintype "passive"))
      (node (ref "C273") (pin "2") (pinfunction "2_2") (pintype "passive"))
      (node (ref "C276") (pin "2") (pinfunction "2_2") (pintype "passive"))
      (node (ref "C277") (pin "2") (pinfunction "2_2") (pintype "passive"))
      (node (ref "C278") (pin "2") (pinfunction "2_2") (pintype "passive"))
      (node (ref "C28") (pin "2") (pinfunction "2_2") (pintype "passive"))
      (node (ref "C280") (pin "2") (pinfunction "2_2") (pintype "passive"))
      (node (ref "C281") (pin "2") (pinfunction "2_2") (pintype "passive"))
      (node (ref "C282") (pin "2") (pinfunction "2_2") (pintype "passive"))
      (node (ref "C284") (pin "2") (pinfunction "2_2") (pintype "passive"))
      (node (ref "C285") (pin "2") (pinfunction "2_2") (pintype "passive"))
      (node (ref "C286") (pin "2") (pinfunction "2_2") (pintype "passive"))
      (node (ref "C288") (pin "2") (pinfunction "2_2") (pintype "passive"))
      (node (ref "C289") (pin "2") (pinfunction "2_2") (pintype "passive"))
      (node (ref "C290") (pin "2") (pinfunction "2_2") (pintype "passive"))
      (node (ref "C30") (pin "2") (pinfunction "2_2") (pintype "passive"))
      (node (ref "C31") (pin "2") (pinfunction "2_2") (pintype "passive"))
      (node (ref "C324") (pin "2") (pinfunction "2_2") (pintype "passive"))
      (node (ref "C325") (pin "2") (pinfunction "2_2") (pintype "passive"))
      (node (ref "C327") (pin "2") (pinfunction "2_2") (pintype "passive"))
      (node (ref "C329") (pin "2") (pinfunction "2_2") (pintype "passive"))
      (node (ref "C33") (pin "2") (pinfunction "2_2") (pintype "passive"))
      (node (ref "C330") (pin "2") (pinfunction "2_2") (pintype "passive"))
      (node (ref "C332") (pin "2") (pinfunction "2_2") (pintype "passive"))
      (node (ref "C334") (pin "2") (pinfunction "2_2") (pintype "passive"))
      (node (ref "C335") (pin "2") (pinfunction "2_2") (pintype "passive"))
      (node (ref "C337") (pin "2") (pinfunction "2_2") (pintype "passive"))
      (node (ref "C339") (pin "2") (pinfunction "2_2") (pintype "passive"))
      (node (ref "C340") (pin "2") (pinfunction "2_2") (pintype "passive"))
      (node (ref "C342") (pin "2") (pinfunction "2_2") (pintype "passive"))
      (node (ref "C344") (pin "2") (pinfunction "2_2") (pintype "passive"))
      (node (ref "C345") (pin "2") (pinfunction "2_2") (pintype "passive"))
      (node (ref "C346") (pin "2") (pinfunction "2_2") (pintype "passive"))
      (node (ref "C347") (pin "2") (pinfunction "2_2") (pintype "passive"))
      (node (ref "C348") (pin "2") (pinfunction "2_2") (pintype "passive"))
      (node (ref "C349") (pin "2") (pinfunction "2_2") (pintype "passive"))
      (node (ref "C35") (pin "2") (pinfunction "2_2") (pintype "passive"))
      (node (ref "C350") (pin "2") (pinfunction "2_2") (pintype "passive"))
      (node (ref "C351") (pin "2") (pinfunction "2_2") (pintype "passive"))
      (node (ref "C352") (pin "2") (pinfunction "2_2") (pintype "passive"))
      (node (ref "C353") (pin "2") (pinfunction "2_2") (pintype "passive"))
      (node (ref "C354") (pin "2") (pinfunction "2_2") (pintype "passive"))
      (node (ref "C355") (pin "2") (pinfunction "2_2") (pintype "passive"))
      (node (ref "C356") (pin "2") (pinfunction "2_2") (pintype "passive"))
      (node (ref "C357") (pin "2") (pinfunction "2_2") (pintype "passive"))
      (node (ref "C358") (pin "2") (pinfunction "2_2") (pintype "passive"))
      (node (ref "C359") (pin "2") (pinfunction "2_2") (pintype "passive"))
      (node (ref "C36") (pin "2") (pinfunction "2_2") (pintype "passive"))
      (node (ref "C360") (pin "2") (pinfunction "2_2") (pintype "passive"))
      (node (ref "C361") (pin "2") (pinfunction "2_2") (pintype "passive"))
      (node (ref "C362") (pin "2") (pinfunction "2_2") (pintype "passive"))
      (node (ref "C363") (pin "2") (pinfunction "2_2") (pintype "passive"))
      (node (ref "C364") (pin "2") (pinfunction "2_2") (pintype "passive"))
      (node (ref "C365") (pin "2") (pinfunction "2_2") (pintype "passive"))
      (node (ref "C366") (pin "2") (pinfunction "2_2") (pintype "passive"))
      (node (ref "C367") (pin "2") (pinfunction "2_2") (pintype "passive"))
      (node (ref "C368") (pin "2") (pinfunction "2_2") (pintype "passive"))
      (node (ref "C369") (pin "2") (pinfunction "2_2") (pintype "passive"))
      (node (ref "C370") (pin "2") (pinfunction "2_2") (pintype "passive"))
      (node (ref "C372") (pin "2") (pinfunction "2_2") (pintype "passive"))
      (node (ref "C373") (pin "2") (pinfunction "2_2") (pintype "passive"))
      (node (ref "C374") (pin "2") (pinfunction "2_2") (pintype "passive"))
      (node (ref "C376") (pin "2") (pinfunction "2_2") (pintype "passive"))
      (node (ref "C377") (pin "2") (pinfunction "2_2") (pintype "passive"))
      (node (ref "C378") (pin "2") (pinfunction "2_2") (pintype "passive"))
      (node (ref "C38") (pin "2") (pinfunction "2_2") (pintype "passive"))
      (node (ref "C380") (pin "2") (pinfunction "2_2") (pintype "passive"))
      (node (ref "C381") (pin "2") (pinfunction "2_2") (pintype "passive"))
      (node (ref "C382") (pin "2") (pinfunction "2_2") (pintype "passive"))
      (node (ref "C40") (pin "2") (pinfunction "2_2") (pintype "passive"))
      (node (ref "C41") (pin "2") (pinfunction "2_2") (pintype "passive"))
      (node (ref "C43") (pin "2") (pinfunction "2_2") (pintype "passive"))
      (node (ref "C45") (pin "2") (pinfunction "2_2") (pintype "passive"))
      (node (ref "C46") (pin "2") (pinfunction "2_2") (pintype "passive"))
      (node (ref "C47") (pin "2") (pinfunction "2_2") (pintype "passive"))
      (node (ref "C48") (pin "2") (pinfunction "2_2") (pintype "passive"))
      (node (ref "C49") (pin "2") (pinfunction "2_2") (pintype "passive"))
      (node (ref "C50") (pin "2") (pinfunction "2_2") (pintype "passive"))
      (node (ref "C51") (pin "2") (pinfunction "2_2") (pintype "passive"))
      (node (ref "C52") (pin "2") (pinfunction "2_2") (pintype "passive"))
      (node (ref "C53") (pin "2") (pinfunction "2_2") (pintype "passive"))
      (node (ref "C54") (pin "2") (pinfunction "2_2") (pintype "passive"))
      (node (ref "C55") (pin "2") (pinfunction "2_2") (pintype "passive"))
      (node (ref "C56") (pin "2") (pinfunction "2_2") (pintype "passive"))
      (node (ref "C57") (pin "2") (pinfunction "2_2") (pintype "passive"))
      (node (ref "C58") (pin "2") (pinfunction "2_2") (pintype "passive"))
      (node (ref "C59") (pin "2") (pinfunction "2_2") (pintype "passive"))
      (node (ref "C60") (pin "2") (pinfunction "2_2") (pintype "passive"))
      (node (ref "C61") (pin "2") (pinfunction "2_2") (pintype "passive"))
      (node (ref "C62") (pin "2") (pinfunction "2_2") (pintype "passive"))
      (node (ref "C63") (pin "2") (pinfunction "2_2") (pintype "passive"))
      (node (ref "C64") (pin "2") (pinfunction "2_2") (pintype "passive"))
      (node (ref "C65") (pin "2") (pinfunction "2_2") (pintype "passive"))
      (node (ref "C66") (pin "2") (pinfunction "2_2") (pintype "passive"))
      (node (ref "C67") (pin "2") (pinfunction "2_2") (pintype "passive"))
      (node (ref "C68") (pin "2") (pinfunction "2_2") (pintype "passive"))
      (node (ref "C70") (pin "2") (pinfunction "2_2") (pintype "passive"))
      (node (ref "C71") (pin "2") (pinfunction "2_2") (pintype "passive"))
      (node (ref "C72") (pin "2") (pinfunction "2_2") (pintype "passive"))
      (node (ref "C74") (pin "2") (pinfunction "2_2") (pintype "passive"))
      (node (ref "C75") (pin "2") (pinfunction "2_2") (pintype "passive"))
      (node (ref "C76") (pin "2") (pinfunction "2_2") (pintype "passive"))
      (node (ref "C78") (pin "2") (pinfunction "2_2") (pintype "passive"))
      (node (ref "C79") (pin "2") (pinfunction "2_2") (pintype "passive"))
      (node (ref "C80") (pin "2") (pinfunction "2_2") (pintype "passive"))
      (node (ref "C82") (pin "2") (pinfunction "2_2") (pintype "passive"))
      (node (ref "C83") (pin "2") (pinfunction "2_2") (pintype "passive"))
      (node (ref "C84") (pin "2") (pinfunction "2_2") (pintype "passive"))
      (node (ref "C_1") (pin "1") (pinfunction "1_1") (pintype "passive"))
      (node (ref "C_10") (pin "1") (pinfunction "1_1") (pintype "passive"))
      (node (ref "C_11") (pin "1") (pinfunction "1_1") (pintype "passive"))
      (node (ref "C_12") (pin "1") (pinfunction "1_1") (pintype "passive"))
      (node (ref "C_13") (pin "1") (pinfunction "1_1") (pintype "passive"))
      (node (ref "C_14") (pin "1") (pinfunction "1_1") (pintype "passive"))
      (node (ref "C_15") (pin "1") (pinfunction "1_1") (pintype "passive"))
      (node (ref "C_16") (pin "1") (pinfunction "1_1") (pintype "passive"))
      (node (ref "C_17") (pin "1") (pinfunction "1_1") (pintype "passive"))
      (node (ref "C_18") (pin "1") (pinfunction "1_1") (pintype "passive"))
      (node (ref "C_19") (pin "1") (pinfunction "1_1") (pintype "passive"))
      (node (ref "C_2") (pin "1") (pinfunction "1_1") (pintype "passive"))
      (node (ref "C_20") (pin "1") (pinfunction "1_1") (pintype "passive"))
      (node (ref "C_21") (pin "1") (pinfunction "1_1") (pintype "passive"))
      (node (ref "C_22") (pin "1") (pinfunction "1_1") (pintype "passive"))
      (node (ref "C_23") (pin "1") (pinfunction "1_1") (pintype "passive"))
      (node (ref "C_24") (pin "1") (pinfunction "1_1") (pintype "passive"))
      (node (ref "C_25") (pin "1") (pinfunction "1_1") (pintype "passive"))
      (node (ref "C_26") (pin "1") (pinfunction "1_1") (pintype "passive"))
      (node (ref "C_27") (pin "1") (pinfunction "1_1") (pintype "passive"))
      (node (ref "C_28") (pin "1") (pinfunction "1_1") (pintype "passive"))
      (node (ref "C_29") (pin "1") (pinfunction "1_1") (pintype "passive"))
      (node (ref "C_3") (pin "1") (pinfunction "1_1") (pintype "passive"))
      (node (ref "C_30") (pin "1") (pinfunction "1_1") (pintype "passive"))
      (node (ref "C_31") (pin "1") (pinfunction "1_1") (pintype "passive"))
      (node (ref "C_32") (pin "1") (pinfunction "1_1") (pintype "passive"))
      (node (ref "C_33") (pin "1") (pinfunction "1_1") (pintype "passive"))
      (node (ref "C_34") (pin "1") (pinfunction "1_1") (pintype "passive"))
      (node (ref "C_35") (pin "1") (pinfunction "1_1") (pintype "passive"))
      (node (ref "C_36") (pin "1") (pinfunction "1_1") (pintype "passive"))
      (node (ref "C_37") (pin "1") (pinfunction "1_1") (pintype "passive"))
      (node (ref "C_38") (pin "1") (pinfunction "1_1") (pintype "passive"))
      (node (ref "C_39") (pin "1") (pinfunction "1_1") (pintype "passive"))
      (node (ref "C_4") (pin "1") (pinfunction "1_1") (pintype "passive"))
      (node (ref "C_40") (pin "1") (pinfunction "1_1") (pintype "passive"))
      (node (ref "C_41") (pin "1") (pinfunction "1_1") (pintype "passive"))
      (node (ref "C_42") (pin "1") (pinfunction "1_1") (pintype "passive"))
      (node (ref "C_43") (pin "1") (pinfunction "1_1") (pintype "passive"))
      (node (ref "C_44") (pin "1") (pinfunction "1_1") (pintype "passive"))
      (node (ref "C_45") (pin "1") (pinfunction "1_1") (pintype "passive"))
      (node (ref "C_46") (pin "1") (pinfunction "1_1") (pintype "passive"))
      (node (ref "C_47") (pin "1") (pinfunction "1_1") (pintype "passive"))
      (node (ref "C_48") (pin "1") (pinfunction "1_1") (pintype "passive"))
      (node (ref "C_49") (pin "1") (pinfunction "1_1") (pintype "passive"))
      (node (ref "C_5") (pin "1") (pinfunction "1_1") (pintype "passive"))
      (node (ref "C_50") (pin "1") (pinfunction "1_1") (pintype "passive"))
      (node (ref "C_51") (pin "1") (pinfunction "1_1") (pintype "passive"))
      (node (ref "C_52") (pin "1") (pinfunction "1_1") (pintype "passive"))
      (node (ref "C_53") (pin "1") (pinfunction "1_1") (pintype "passive"))
      (node (ref "C_54") (pin "1") (pinfunction "1_1") (pintype "passive"))
      (node (ref "C_55") (pin "1") (pinfunction "1_1") (pintype "passive"))
      (node (ref "C_56") (pin "1") (pinfunction "1_1") (pintype "passive"))
      (node (ref "C_57") (pin "1") (pinfunction "1_1") (pintype "passive"))
      (node (ref "C_58") (pin "1") (pinfunction "1_1") (pintype "passive"))
      (node (ref "C_59") (pin "1") (pinfunction "1_1") (pintype "passive"))
      (node (ref "C_6") (pin "1") (pinfunction "1_1") (pintype "passive"))
      (node (ref "C_60") (pin "1") (pinfunction "1_1") (pintype "passive"))
      (node (ref "C_61") (pin "1") (pinfunction "1_1") (pintype "passive"))
      (node (ref "C_62") (pin "1") (pinfunction "1_1") (pintype "passive"))
      (node (ref "C_63") (pin "1") (pinfunction "1_1") (pintype "passive"))
      (node (ref "C_64") (pin "1") (pinfunction "1_1") (pintype "passive"))
      (node (ref "C_65") (pin "1") (pinfunction "1_1") (pintype "passive"))
      (node (ref "C_66") (pin "1") (pinfunction "1_1") (pintype "passive"))
      (node (ref "C_67") (pin "1") (pinfunction "1_1") (pintype "passive"))
      (node (ref "C_68") (pin "1") (pinfunction "1_1") (pintype "passive"))
      (node (ref "C_69") (pin "1") (pinfunction "1_1") (pintype "passive"))
      (node (ref "C_7") (pin "1") (pinfunction "1_1") (pintype "passive"))
      (node (ref "C_70") (pin "1") (pinfunction "1_1") (pintype "passive"))
      (node (ref "C_71") (pin "1") (pinfunction "1_1") (pintype "passive"))
      (node (ref "C_72") (pin "1") (pinfunction "1_1") (pintype "passive"))
      (node (ref "C_8") (pin "1") (pinfunction "1_1") (pintype "passive"))
      (node (ref "C_9") (pin "1") (pinfunction "1_1") (pintype "passive"))
      (node (ref "L1") (pin "2") (pinfunction "2_2") (pintype "passive"))
      (node (ref "L2") (pin "2") (pinfunction "2_2") (pintype "passive"))
      (node (ref "L3") (pin "2") (pinfunction "2_2") (pintype "passive"))
      (node (ref "R26") (pin "2") (pinfunction "2_2") (pintype "passive"))
      (node (ref "U10") (pin "13") (pinfunction "DVDD_13") (pintype "passive"))
      (node (ref "U10") (pin "14") (pinfunction "DVDD_14") (pintype "passive"))
      (node (ref "U10") (pin "19") (pinfunction "DVDD_19") (pintype "passive"))
      (node (ref "U10") (pin "20") (pinfunction "DVDD_20") (pintype "passive"))
      (node (ref "U10") (pin "21") (pinfunction "DVDD_21") (pintype "passive"))
      (node (ref "U10") (pin "22") (pinfunction "DVDD_22") (pintype "passive"))
      (node (ref "U10") (pin "26") (pinfunction "DVDD_26") (pintype "passive"))
      (node (ref "U10") (pin "27") (pinfunction "DVDD_27") (pintype "passive"))
      (node (ref "U10") (pin "29") (pinfunction "DVDD_29") (pintype "passive"))
      (node (ref "U10") (pin "3") (pinfunction "DVDD_3") (pintype "passive"))
      (node (ref "U10") (pin "30") (pinfunction "DVDD_30") (pintype "passive"))
      (node (ref "U10") (pin "34") (pinfunction "DVDD_34") (pintype "passive"))
      (node (ref "U10") (pin "35") (pinfunction "DVDD_35") (pintype "passive"))
      (node (ref "U10") (pin "37") (pinfunction "DVDD_37") (pintype "passive"))
      (node (ref "U10") (pin "38") (pinfunction "DVDD_38") (pintype "passive"))
      (node (ref "U10") (pin "39") (pinfunction "DVDD_39") (pintype "passive"))
      (node (ref "U10") (pin "4") (pinfunction "DVDD_4") (pintype "passive"))
      (node (ref "U10") (pin "41") (pinfunction "DVDD_41") (pintype "passive"))
      (node (ref "U10") (pin "42") (pinfunction "DVDD_42") (pintype "passive"))
      (node (ref "U10") (pin "43") (pinfunction "DVDD_43") (pintype "passive"))
      (node (ref "U10") (pin "45") (pinfunction "DVDD_45") (pintype "passive"))
      (node (ref "U10") (pin "46") (pinfunction "DVDD_46") (pintype "passive"))
      (node (ref "U10") (pin "5") (pinfunction "DVDD_5") (pintype "passive"))
      (node (ref "U10") (pin "51") (pinfunction "DVDD_51") (pintype "passive"))
      (node (ref "U10") (pin "52") (pinfunction "DVDD_52") (pintype "passive"))
      (node (ref "U10") (pin "54") (pinfunction "DVDD_54") (pintype "passive"))
      (node (ref "U10") (pin "55") (pinfunction "DVDD_55") (pintype "passive"))
      (node (ref "U10") (pin "58") (pinfunction "DVDD_58") (pintype "passive"))
      (node (ref "U10") (pin "59") (pinfunction "DVDD_59") (pintype "passive"))
      (node (ref "U10") (pin "6") (pinfunction "DVDD_6") (pintype "passive"))
      (node (ref "U10") (pin "60") (pinfunction "DVDD_60") (pintype "passive"))
      (node (ref "U10") (pin "62") (pinfunction "DVDD_62") (pintype "passive"))
      (node (ref "U10") (pin "63") (pinfunction "DVDD_63") (pintype "passive"))
      (node (ref "U11") (pin "13") (pinfunction "DVDD_13") (pintype "passive"))
      (node (ref "U11") (pin "14") (pinfunction "DVDD_14") (pintype "passive"))
      (node (ref "U11") (pin "19") (pinfunction "DVDD_19") (pintype "passive"))
      (node (ref "U11") (pin "20") (pinfunction "DVDD_20") (pintype "passive"))
      (node (ref "U11") (pin "21") (pinfunction "DVDD_21") (pintype "passive"))
      (node (ref "U11") (pin "22") (pinfunction "DVDD_22") (pintype "passive"))
      (node (ref "U11") (pin "26") (pinfunction "DVDD_26") (pintype "passive"))
      (node (ref "U11") (pin "27") (pinfunction "DVDD_27") (pintype "passive"))
      (node (ref "U11") (pin "29") (pinfunction "DVDD_29") (pintype "passive"))
      (node (ref "U11") (pin "3") (pinfunction "DVDD_3") (pintype "passive"))
      (node (ref "U11") (pin "30") (pinfunction "DVDD_30") (pintype "passive"))
      (node (ref "U11") (pin "34") (pinfunction "DVDD_34") (pintype "passive"))
      (node (ref "U11") (pin "35") (pinfunction "DVDD_35") (pintype "passive"))
      (node (ref "U11") (pin "37") (pinfunction "DVDD_37") (pintype "passive"))
      (node (ref "U11") (pin "38") (pinfunction "DVDD_38") (pintype "passive"))
      (node (ref "U11") (pin "39") (pinfunction "DVDD_39") (pintype "passive"))
      (node (ref "U11") (pin "4") (pinfunction "DVDD_4") (pintype "passive"))
      (node (ref "U11") (pin "41") (pinfunction "DVDD_41") (pintype "passive"))
      (node (ref "U11") (pin "42") (pinfunction "DVDD_42") (pintype "passive"))
      (node (ref "U11") (pin "43") (pinfunction "DVDD_43") (pintype "passive"))
      (node (ref "U11") (pin "45") (pinfunction "DVDD_45") (pintype "passive"))
      (node (ref "U11") (pin "46") (pinfunction "DVDD_46") (pintype "passive"))
      (node (ref "U11") (pin "5") (pinfunction "DVDD_5") (pintype "passive"))
      (node (ref "U11") (pin "51") (pinfunction "DVDD_51") (pintype "passive"))
      (node (ref "U11") (pin "52") (pinfunction "DVDD_52") (pintype "passive"))
      (node (ref "U11") (pin "54") (pinfunction "DVDD_54") (pintype "passive"))
      (node (ref "U11") (pin "55") (pinfunction "DVDD_55") (pintype "passive"))
      (node (ref "U11") (pin "58") (pinfunction "DVDD_58") (pintype "passive"))
      (node (ref "U11") (pin "59") (pinfunction "DVDD_59") (pintype "passive"))
      (node (ref "U11") (pin "6") (pinfunction "DVDD_6") (pintype "passive"))
      (node (ref "U11") (pin "60") (pinfunction "DVDD_60") (pintype "passive"))
      (node (ref "U11") (pin "62") (pinfunction "DVDD_62") (pintype "passive"))
      (node (ref "U11") (pin "63") (pinfunction "DVDD_63") (pintype "passive"))
      (node (ref "U12") (pin "13") (pinfunction "DVDD_13") (pintype "passive"))
      (node (ref "U12") (pin "14") (pinfunction "DVDD_14") (pintype "passive"))
      (node (ref "U12") (pin "19") (pinfunction "DVDD_19") (pintype "passive"))
      (node (ref "U12") (pin "20") (pinfunction "DVDD_20") (pintype "passive"))
      (node (ref "U12") (pin "21") (pinfunction "DVDD_21") (pintype "passive"))
      (node (ref "U12") (pin "22") (pinfunction "DVDD_22") (pintype "passive"))
      (node (ref "U12") (pin "26") (pinfunction "DVDD_26") (pintype "passive"))
      (node (ref "U12") (pin "27") (pinfunction "DVDD_27") (pintype "passive"))
      (node (ref "U12") (pin "29") (pinfunction "DVDD_29") (pintype "passive"))
      (node (ref "U12") (pin "3") (pinfunction "DVDD_3") (pintype "passive"))
      (node (ref "U12") (pin "30") (pinfunction "DVDD_30") (pintype "passive"))
      (node (ref "U12") (pin "34") (pinfunction "DVDD_34") (pintype "passive"))
      (node (ref "U12") (pin "35") (pinfunction "DVDD_35") (pintype "passive"))
      (node (ref "U12") (pin "37") (pinfunction "DVDD_37") (pintype "passive"))
      (node (ref "U12") (pin "38") (pinfunction "DVDD_38") (pintype "passive"))
      (node (ref "U12") (pin "39") (pinfunction "DVDD_39") (pintype "passive"))
      (node (ref "U12") (pin "4") (pinfunction "DVDD_4") (pintype "passive"))
      (node (ref "U12") (pin "41") (pinfunction "DVDD_41") (pintype "passive"))
      (node (ref "U12") (pin "42") (pinfunction "DVDD_42") (pintype "passive"))
      (node (ref "U12") (pin "43") (pinfunction "DVDD_43") (pintype "passive"))
      (node (ref "U12") (pin "45") (pinfunction "DVDD_45") (pintype "passive"))
      (node (ref "U12") (pin "46") (pinfunction "DVDD_46") (pintype "passive"))
      (node (ref "U12") (pin "5") (pinfunction "DVDD_5") (pintype "passive"))
      (node (ref "U12") (pin "51") (pinfunction "DVDD_51") (pintype "passive"))
      (node (ref "U12") (pin "52") (pinfunction "DVDD_52") (pintype "passive"))
      (node (ref "U12") (pin "54") (pinfunction "DVDD_54") (pintype "passive"))
      (node (ref "U12") (pin "55") (pinfunction "DVDD_55") (pintype "passive"))
      (node (ref "U12") (pin "58") (pinfunction "DVDD_58") (pintype "passive"))
      (node (ref "U12") (pin "59") (pinfunction "DVDD_59") (pintype "passive"))
      (node (ref "U12") (pin "6") (pinfunction "DVDD_6") (pintype "passive"))
      (node (ref "U12") (pin "60") (pinfunction "DVDD_60") (pintype "passive"))
      (node (ref "U12") (pin "62") (pinfunction "DVDD_62") (pintype "passive"))
      (node (ref "U12") (pin "63") (pinfunction "DVDD_63") (pintype "passive"))
      (node (ref "U18") (pin "13") (pinfunction "DVDD_13") (pintype "passive"))
      (node (ref "U18") (pin "14") (pinfunction "DVDD_14") (pintype "passive"))
      (node (ref "U18") (pin "19") (pinfunction "DVDD_19") (pintype "passive"))
      (node (ref "U18") (pin "20") (pinfunction "DVDD_20") (pintype "passive"))
      (node (ref "U18") (pin "21") (pinfunction "DVDD_21") (pintype "passive"))
      (node (ref "U18") (pin "22") (pinfunction "DVDD_22") (pintype "passive"))
      (node (ref "U18") (pin "26") (pinfunction "DVDD_26") (pintype "passive"))
      (node (ref "U18") (pin "27") (pinfunction "DVDD_27") (pintype "passive"))
      (node (ref "U18") (pin "29") (pinfunction "DVDD_29") (pintype "passive"))
      (node (ref "U18") (pin "3") (pinfunction "DVDD_3") (pintype "passive"))
      (node (ref "U18") (pin "30") (pinfunction "DVDD_30") (pintype "passive"))
      (node (ref "U18") (pin "34") (pinfunction "DVDD_34") (pintype "passive"))
      (node (ref "U18") (pin "35") (pinfunction "DVDD_35") (pintype "passive"))
      (node (ref "U18") (pin "37") (pinfunction "DVDD_37") (pintype "passive"))
      (node (ref "U18") (pin "38") (pinfunction "DVDD_38") (pintype "passive"))
      (node (ref "U18") (pin "39") (pinfunction "DVDD_39") (pintype "passive"))
      (node (ref "U18") (pin "4") (pinfunction "DVDD_4") (pintype "passive"))
      (node (ref "U18") (pin "41") (pinfunction "DVDD_41") (pintype "passive"))
      (node (ref "U18") (pin "42") (pinfunction "DVDD_42") (pintype "passive"))
      (node (ref "U18") (pin "43") (pinfunction "DVDD_43") (pintype "passive"))
      (node (ref "U18") (pin "45") (pinfunction "DVDD_45") (pintype "passive"))
      (node (ref "U18") (pin "46") (pinfunction "DVDD_46") (pintype "passive"))
      (node (ref "U18") (pin "5") (pinfunction "DVDD_5") (pintype "passive"))
      (node (ref "U18") (pin "51") (pinfunction "DVDD_51") (pintype "passive"))
      (node (ref "U18") (pin "52") (pinfunction "DVDD_52") (pintype "passive"))
      (node (ref "U18") (pin "54") (pinfunction "DVDD_54") (pintype "passive"))
      (node (ref "U18") (pin "55") (pinfunction "DVDD_55") (pintype "passive"))
      (node (ref "U18") (pin "58") (pinfunction "DVDD_58") (pintype "passive"))
      (node (ref "U18") (pin "59") (pinfunction "DVDD_59") (pintype "passive"))
      (node (ref "U18") (pin "6") (pinfunction "DVDD_6") (pintype "passive"))
      (node (ref "U18") (pin "60") (pinfunction "DVDD_60") (pintype "passive"))
      (node (ref "U18") (pin "62") (pinfunction "DVDD_62") (pintype "passive"))
      (node (ref "U18") (pin "63") (pinfunction "DVDD_63") (pintype "passive"))
      (node (ref "U19") (pin "13") (pinfunction "DVDD_13") (pintype "passive"))
      (node (ref "U19") (pin "14") (pinfunction "DVDD_14") (pintype "passive"))
      (node (ref "U19") (pin "19") (pinfunction "DVDD_19") (pintype "passive"))
      (node (ref "U19") (pin "20") (pinfunction "DVDD_20") (pintype "passive"))
      (node (ref "U19") (pin "21") (pinfunction "DVDD_21") (pintype "passive"))
      (node (ref "U19") (pin "22") (pinfunction "DVDD_22") (pintype "passive"))
      (node (ref "U19") (pin "26") (pinfunction "DVDD_26") (pintype "passive"))
      (node (ref "U19") (pin "27") (pinfunction "DVDD_27") (pintype "passive"))
      (node (ref "U19") (pin "29") (pinfunction "DVDD_29") (pintype "passive"))
      (node (ref "U19") (pin "3") (pinfunction "DVDD_3") (pintype "passive"))
      (node (ref "U19") (pin "30") (pinfunction "DVDD_30") (pintype "passive"))
      (node (ref "U19") (pin "34") (pinfunction "DVDD_34") (pintype "passive"))
      (node (ref "U19") (pin "35") (pinfunction "DVDD_35") (pintype "passive"))
      (node (ref "U19") (pin "37") (pinfunction "DVDD_37") (pintype "passive"))
      (node (ref "U19") (pin "38") (pinfunction "DVDD_38") (pintype "passive"))
      (node (ref "U19") (pin "39") (pinfunction "DVDD_39") (pintype "passive"))
      (node (ref "U19") (pin "4") (pinfunction "DVDD_4") (pintype "passive"))
      (node (ref "U19") (pin "41") (pinfunction "DVDD_41") (pintype "passive"))
      (node (ref "U19") (pin "42") (pinfunction "DVDD_42") (pintype "passive"))
      (node (ref "U19") (pin "43") (pinfunction "DVDD_43") (pintype "passive"))
      (node (ref "U19") (pin "45") (pinfunction "DVDD_45") (pintype "passive"))
      (node (ref "U19") (pin "46") (pinfunction "DVDD_46") (pintype "passive"))
      (node (ref "U19") (pin "5") (pinfunction "DVDD_5") (pintype "passive"))
      (node (ref "U19") (pin "51") (pinfunction "DVDD_51") (pintype "passive"))
      (node (ref "U19") (pin "52") (pinfunction "DVDD_52") (pintype "passive"))
      (node (ref "U19") (pin "54") (pinfunction "DVDD_54") (pintype "passive"))
      (node (ref "U19") (pin "55") (pinfunction "DVDD_55") (pintype "passive"))
      (node (ref "U19") (pin "58") (pinfunction "DVDD_58") (pintype "passive"))
      (node (ref "U19") (pin "59") (pinfunction "DVDD_59") (pintype "passive"))
      (node (ref "U19") (pin "6") (pinfunction "DVDD_6") (pintype "passive"))
      (node (ref "U19") (pin "60") (pinfunction "DVDD_60") (pintype "passive"))
      (node (ref "U19") (pin "62") (pinfunction "DVDD_62") (pintype "passive"))
      (node (ref "U19") (pin "63") (pinfunction "DVDD_63") (pintype "passive"))
      (node (ref "U20") (pin "13") (pinfunction "DVDD_13") (pintype "passive"))
      (node (ref "U20") (pin "14") (pinfunction "DVDD_14") (pintype "passive"))
      (node (ref "U20") (pin "19") (pinfunction "DVDD_19") (pintype "passive"))
      (node (ref "U20") (pin "20") (pinfunction "DVDD_20") (pintype "passive"))
      (node (ref "U20") (pin "21") (pinfunction "DVDD_21") (pintype "passive"))
      (node (ref "U20") (pin "22") (pinfunction "DVDD_22") (pintype "passive"))
      (node (ref "U20") (pin "26") (pinfunction "DVDD_26") (pintype "passive"))
      (node (ref "U20") (pin "27") (pinfunction "DVDD_27") (pintype "passive"))
      (node (ref "U20") (pin "29") (pinfunction "DVDD_29") (pintype "passive"))
      (node (ref "U20") (pin "3") (pinfunction "DVDD_3") (pintype "passive"))
      (node (ref "U20") (pin "30") (pinfunction "DVDD_30") (pintype "passive"))
      (node (ref "U20") (pin "34") (pinfunction "DVDD_34") (pintype "passive"))
      (node (ref "U20") (pin "35") (pinfunction "DVDD_35") (pintype "passive"))
      (node (ref "U20") (pin "37") (pinfunction "DVDD_37") (pintype "passive"))
      (node (ref "U20") (pin "38") (pinfunction "DVDD_38") (pintype "passive"))
      (node (ref "U20") (pin "39") (pinfunction "DVDD_39") (pintype "passive"))
      (node (ref "U20") (pin "4") (pinfunction "DVDD_4") (pintype "passive"))
      (node (ref "U20") (pin "41") (pinfunction "DVDD_41") (pintype "passive"))
      (node (ref "U20") (pin "42") (pinfunction "DVDD_42") (pintype "passive"))
      (node (ref "U20") (pin "43") (pinfunction "DVDD_43") (pintype "passive"))
      (node (ref "U20") (pin "45") (pinfunction "DVDD_45") (pintype "passive"))
      (node (ref "U20") (pin "46") (pinfunction "DVDD_46") (pintype "passive"))
      (node (ref "U20") (pin "5") (pinfunction "DVDD_5") (pintype "passive"))
      (node (ref "U20") (pin "51") (pinfunction "DVDD_51") (pintype "passive"))
      (node (ref "U20") (pin "52") (pinfunction "DVDD_52") (pintype "passive"))
      (node (ref "U20") (pin "54") (pinfunction "DVDD_54") (pintype "passive"))
      (node (ref "U20") (pin "55") (pinfunction "DVDD_55") (pintype "passive"))
      (node (ref "U20") (pin "58") (pinfunction "DVDD_58") (pintype "passive"))
      (node (ref "U20") (pin "59") (pinfunction "DVDD_59") (pintype "passive"))
      (node (ref "U20") (pin "6") (pinfunction "DVDD_6") (pintype "passive"))
      (node (ref "U20") (pin "60") (pinfunction "DVDD_60") (pintype "passive"))
      (node (ref "U20") (pin "62") (pinfunction "DVDD_62") (pintype "passive"))
      (node (ref "U20") (pin "63") (pinfunction "DVDD_63") (pintype "passive"))
      (node (ref "U21") (pin "13") (pinfunction "DVDD_13") (pintype "passive"))
      (node (ref "U21") (pin "14") (pinfunction "DVDD_14") (pintype "passive"))
      (node (ref "U21") (pin "19") (pinfunction "DVDD_19") (pintype "passive"))
      (node (ref "U21") (pin "20") (pinfunction "DVDD_20") (pintype "passive"))
      (node (ref "U21") (pin "21") (pinfunction "DVDD_21") (pintype "passive"))
      (node (ref "U21") (pin "22") (pinfunction "DVDD_22") (pintype "passive"))
      (node (ref "U21") (pin "26") (pinfunction "DVDD_26") (pintype "passive"))
      (node (ref "U21") (pin "27") (pinfunction "DVDD_27") (pintype "passive"))
      (node (ref "U21") (pin "29") (pinfunction "DVDD_29") (pintype "passive"))
      (node (ref "U21") (pin "3") (pinfunction "DVDD_3") (pintype "passive"))
      (node (ref "U21") (pin "30") (pinfunction "DVDD_30") (pintype "passive"))
      (node (ref "U21") (pin "34") (pinfunction "DVDD_34") (pintype "passive"))
      (node (ref "U21") (pin "35") (pinfunction "DVDD_35") (pintype "passive"))
      (node (ref "U21") (pin "37") (pinfunction "DVDD_37") (pintype "passive"))
      (node (ref "U21") (pin "38") (pinfunction "DVDD_38") (pintype "passive"))
      (node (ref "U21") (pin "39") (pinfunction "DVDD_39") (pintype "passive"))
      (node (ref "U21") (pin "4") (pinfunction "DVDD_4") (pintype "passive"))
      (node (ref "U21") (pin "41") (pinfunction "DVDD_41") (pintype "passive"))
      (node (ref "U21") (pin "42") (pinfunction "DVDD_42") (pintype "passive"))
      (node (ref "U21") (pin "43") (pinfunction "DVDD_43") (pintype "passive"))
      (node (ref "U21") (pin "45") (pinfunction "DVDD_45") (pintype "passive"))
      (node (ref "U21") (pin "46") (pinfunction "DVDD_46") (pintype "passive"))
      (node (ref "U21") (pin "5") (pinfunction "DVDD_5") (pintype "passive"))
      (node (ref "U21") (pin "51") (pinfunction "DVDD_51") (pintype "passive"))
      (node (ref "U21") (pin "52") (pinfunction "DVDD_52") (pintype "passive"))
      (node (ref "U21") (pin "54") (pinfunction "DVDD_54") (pintype "passive"))
      (node (ref "U21") (pin "55") (pinfunction "DVDD_55") (pintype "passive"))
      (node (ref "U21") (pin "58") (pinfunction "DVDD_58") (pintype "passive"))
      (node (ref "U21") (pin "59") (pinfunction "DVDD_59") (pintype "passive"))
      (node (ref "U21") (pin "6") (pinfunction "DVDD_6") (pintype "passive"))
      (node (ref "U21") (pin "60") (pinfunction "DVDD_60") (pintype "passive"))
      (node (ref "U21") (pin "62") (pinfunction "DVDD_62") (pintype "passive"))
      (node (ref "U21") (pin "63") (pinfunction "DVDD_63") (pintype "passive"))
      (node (ref "U24") (pin "13") (pinfunction "DVDD_13") (pintype "passive"))
      (node (ref "U24") (pin "14") (pinfunction "DVDD_14") (pintype "passive"))
      (node (ref "U24") (pin "19") (pinfunction "DVDD_19") (pintype "passive"))
      (node (ref "U24") (pin "20") (pinfunction "DVDD_20") (pintype "passive"))
      (node (ref "U24") (pin "21") (pinfunction "DVDD_21") (pintype "passive"))
      (node (ref "U24") (pin "22") (pinfunction "DVDD_22") (pintype "passive"))
      (node (ref "U24") (pin "26") (pinfunction "DVDD_26") (pintype "passive"))
      (node (ref "U24") (pin "27") (pinfunction "DVDD_27") (pintype "passive"))
      (node (ref "U24") (pin "29") (pinfunction "DVDD_29") (pintype "passive"))
      (node (ref "U24") (pin "3") (pinfunction "DVDD_3") (pintype "passive"))
      (node (ref "U24") (pin "30") (pinfunction "DVDD_30") (pintype "passive"))
      (node (ref "U24") (pin "34") (pinfunction "DVDD_34") (pintype "passive"))
      (node (ref "U24") (pin "35") (pinfunction "DVDD_35") (pintype "passive"))
      (node (ref "U24") (pin "37") (pinfunction "DVDD_37") (pintype "passive"))
      (node (ref "U24") (pin "38") (pinfunction "DVDD_38") (pintype "passive"))
      (node (ref "U24") (pin "39") (pinfunction "DVDD_39") (pintype "passive"))
      (node (ref "U24") (pin "4") (pinfunction "DVDD_4") (pintype "passive"))
      (node (ref "U24") (pin "41") (pinfunction "DVDD_41") (pintype "passive"))
      (node (ref "U24") (pin "42") (pinfunction "DVDD_42") (pintype "passive"))
      (node (ref "U24") (pin "43") (pinfunction "DVDD_43") (pintype "passive"))
      (node (ref "U24") (pin "45") (pinfunction "DVDD_45") (pintype "passive"))
      (node (ref "U24") (pin "46") (pinfunction "DVDD_46") (pintype "passive"))
      (node (ref "U24") (pin "5") (pinfunction "DVDD_5") (pintype "passive"))
      (node (ref "U24") (pin "51") (pinfunction "DVDD_51") (pintype "passive"))
      (node (ref "U24") (pin "52") (pinfunction "DVDD_52") (pintype "passive"))
      (node (ref "U24") (pin "54") (pinfunction "DVDD_54") (pintype "passive"))
      (node (ref "U24") (pin "55") (pinfunction "DVDD_55") (pintype "passive"))
      (node (ref "U24") (pin "58") (pinfunction "DVDD_58") (pintype "passive"))
      (node (ref "U24") (pin "59") (pinfunction "DVDD_59") (pintype "passive"))
      (node (ref "U24") (pin "6") (pinfunction "DVDD_6") (pintype "passive"))
      (node (ref "U24") (pin "60") (pinfunction "DVDD_60") (pintype "passive"))
      (node (ref "U24") (pin "62") (pinfunction "DVDD_62") (pintype "passive"))
      (node (ref "U24") (pin "63") (pinfunction "DVDD_63") (pintype "passive"))
      (node (ref "U25") (pin "13") (pinfunction "DVDD_13") (pintype "passive"))
      (node (ref "U25") (pin "14") (pinfunction "DVDD_14") (pintype "passive"))
      (node (ref "U25") (pin "19") (pinfunction "DVDD_19") (pintype "passive"))
      (node (ref "U25") (pin "20") (pinfunction "DVDD_20") (pintype "passive"))
      (node (ref "U25") (pin "21") (pinfunction "DVDD_21") (pintype "passive"))
      (node (ref "U25") (pin "22") (pinfunction "DVDD_22") (pintype "passive"))
      (node (ref "U25") (pin "26") (pinfunction "DVDD_26") (pintype "passive"))
      (node (ref "U25") (pin "27") (pinfunction "DVDD_27") (pintype "passive"))
      (node (ref "U25") (pin "29") (pinfunction "DVDD_29") (pintype "passive"))
      (node (ref "U25") (pin "3") (pinfunction "DVDD_3") (pintype "passive"))
      (node (ref "U25") (pin "30") (pinfunction "DVDD_30") (pintype "passive"))
      (node (ref "U25") (pin "34") (pinfunction "DVDD_34") (pintype "passive"))
      (node (ref "U25") (pin "35") (pinfunction "DVDD_35") (pintype "passive"))
      (node (ref "U25") (pin "37") (pinfunction "DVDD_37") (pintype "passive"))
      (node (ref "U25") (pin "38") (pinfunction "DVDD_38") (pintype "passive"))
      (node (ref "U25") (pin "39") (pinfunction "DVDD_39") (pintype "passive"))
      (node (ref "U25") (pin "4") (pinfunction "DVDD_4") (pintype "passive"))
      (node (ref "U25") (pin "41") (pinfunction "DVDD_41") (pintype "passive"))
      (node (ref "U25") (pin "42") (pinfunction "DVDD_42") (pintype "passive"))
      (node (ref "U25") (pin "43") (pinfunction "DVDD_43") (pintype "passive"))
      (node (ref "U25") (pin "45") (pinfunction "DVDD_45") (pintype "passive"))
      (node (ref "U25") (pin "46") (pinfunction "DVDD_46") (pintype "passive"))
      (node (ref "U25") (pin "5") (pinfunction "DVDD_5") (pintype "passive"))
      (node (ref "U25") (pin "51") (pinfunction "DVDD_51") (pintype "passive"))
      (node (ref "U25") (pin "52") (pinfunction "DVDD_52") (pintype "passive"))
      (node (ref "U25") (pin "54") (pinfunction "DVDD_54") (pintype "passive"))
      (node (ref "U25") (pin "55") (pinfunction "DVDD_55") (pintype "passive"))
      (node (ref "U25") (pin "58") (pinfunction "DVDD_58") (pintype "passive"))
      (node (ref "U25") (pin "59") (pinfunction "DVDD_59") (pintype "passive"))
      (node (ref "U25") (pin "6") (pinfunction "DVDD_6") (pintype "passive"))
      (node (ref "U25") (pin "60") (pinfunction "DVDD_60") (pintype "passive"))
      (node (ref "U25") (pin "62") (pinfunction "DVDD_62") (pintype "passive"))
      (node (ref "U25") (pin "63") (pinfunction "DVDD_63") (pintype "passive"))
      (node (ref "U26") (pin "13") (pinfunction "DVDD_13") (pintype "passive"))
      (node (ref "U26") (pin "14") (pinfunction "DVDD_14") (pintype "passive"))
      (node (ref "U26") (pin "19") (pinfunction "DVDD_19") (pintype "passive"))
      (node (ref "U26") (pin "20") (pinfunction "DVDD_20") (pintype "passive"))
      (node (ref "U26") (pin "21") (pinfunction "DVDD_21") (pintype "passive"))
      (node (ref "U26") (pin "22") (pinfunction "DVDD_22") (pintype "passive"))
      (node (ref "U26") (pin "26") (pinfunction "DVDD_26") (pintype "passive"))
      (node (ref "U26") (pin "27") (pinfunction "DVDD_27") (pintype "passive"))
      (node (ref "U26") (pin "29") (pinfunction "DVDD_29") (pintype "passive"))
      (node (ref "U26") (pin "3") (pinfunction "DVDD_3") (pintype "passive"))
      (node (ref "U26") (pin "30") (pinfunction "DVDD_30") (pintype "passive"))
      (node (ref "U26") (pin "34") (pinfunction "DVDD_34") (pintype "passive"))
      (node (ref "U26") (pin "35") (pinfunction "DVDD_35") (pintype "passive"))
      (node (ref "U26") (pin "37") (pinfunction "DVDD_37") (pintype "passive"))
      (node (ref "U26") (pin "38") (pinfunction "DVDD_38") (pintype "passive"))
      (node (ref "U26") (pin "39") (pinfunction "DVDD_39") (pintype "passive"))
      (node (ref "U26") (pin "4") (pinfunction "DVDD_4") (pintype "passive"))
      (node (ref "U26") (pin "41") (pinfunction "DVDD_41") (pintype "passive"))
      (node (ref "U26") (pin "42") (pinfunction "DVDD_42") (pintype "passive"))
      (node (ref "U26") (pin "43") (pinfunction "DVDD_43") (pintype "passive"))
      (node (ref "U26") (pin "45") (pinfunction "DVDD_45") (pintype "passive"))
      (node (ref "U26") (pin "46") (pinfunction "DVDD_46") (pintype "passive"))
      (node (ref "U26") (pin "5") (pinfunction "DVDD_5") (pintype "passive"))
      (node (ref "U26") (pin "51") (pinfunction "DVDD_51") (pintype "passive"))
      (node (ref "U26") (pin "52") (pinfunction "DVDD_52") (pintype "passive"))
      (node (ref "U26") (pin "54") (pinfunction "DVDD_54") (pintype "passive"))
      (node (ref "U26") (pin "55") (pinfunction "DVDD_55") (pintype "passive"))
      (node (ref "U26") (pin "58") (pinfunction "DVDD_58") (pintype "passive"))
      (node (ref "U26") (pin "59") (pinfunction "DVDD_59") (pintype "passive"))
      (node (ref "U26") (pin "6") (pinfunction "DVDD_6") (pintype "passive"))
      (node (ref "U26") (pin "60") (pinfunction "DVDD_60") (pintype "passive"))
      (node (ref "U26") (pin "62") (pinfunction "DVDD_62") (pintype "passive"))
      (node (ref "U26") (pin "63") (pinfunction "DVDD_63") (pintype "passive"))
      (node (ref "U27") (pin "13") (pinfunction "DVDD_13") (pintype "passive"))
      (node (ref "U27") (pin "14") (pinfunction "DVDD_14") (pintype "passive"))
      (node (ref "U27") (pin "19") (pinfunction "DVDD_19") (pintype "passive"))
      (node (ref "U27") (pin "20") (pinfunction "DVDD_20") (pintype "passive"))
      (node (ref "U27") (pin "21") (pinfunction "DVDD_21") (pintype "passive"))
      (node (ref "U27") (pin "22") (pinfunction "DVDD_22") (pintype "passive"))
      (node (ref "U27") (pin "26") (pinfunction "DVDD_26") (pintype "passive"))
      (node (ref "U27") (pin "27") (pinfunction "DVDD_27") (pintype "passive"))
      (node (ref "U27") (pin "29") (pinfunction "DVDD_29") (pintype "passive"))
      (node (ref "U27") (pin "3") (pinfunction "DVDD_3") (pintype "passive"))
      (node (ref "U27") (pin "30") (pinfunction "DVDD_30") (pintype "passive"))
      (node (ref "U27") (pin "34") (pinfunction "DVDD_34") (pintype "passive"))
      (node (ref "U27") (pin "35") (pinfunction "DVDD_35") (pintype "passive"))
      (node (ref "U27") (pin "37") (pinfunction "DVDD_37") (pintype "passive"))
      (node (ref "U27") (pin "38") (pinfunction "DVDD_38") (pintype "passive"))
      (node (ref "U27") (pin "39") (pinfunction "DVDD_39") (pintype "passive"))
      (node (ref "U27") (pin "4") (pinfunction "DVDD_4") (pintype "passive"))
      (node (ref "U27") (pin "41") (pinfunction "DVDD_41") (pintype "passive"))
      (node (ref "U27") (pin "42") (pinfunction "DVDD_42") (pintype "passive"))
      (node (ref "U27") (pin "43") (pinfunction "DVDD_43") (pintype "passive"))
      (node (ref "U27") (pin "45") (pinfunction "DVDD_45") (pintype "passive"))
      (node (ref "U27") (pin "46") (pinfunction "DVDD_46") (pintype "passive"))
      (node (ref "U27") (pin "5") (pinfunction "DVDD_5") (pintype "passive"))
      (node (ref "U27") (pin "51") (pinfunction "DVDD_51") (pintype "passive"))
      (node (ref "U27") (pin "52") (pinfunction "DVDD_52") (pintype "passive"))
      (node (ref "U27") (pin "54") (pinfunction "DVDD_54") (pintype "passive"))
      (node (ref "U27") (pin "55") (pinfunction "DVDD_55") (pintype "passive"))
      (node (ref "U27") (pin "58") (pinfunction "DVDD_58") (pintype "passive"))
      (node (ref "U27") (pin "59") (pinfunction "DVDD_59") (pintype "passive"))
      (node (ref "U27") (pin "6") (pinfunction "DVDD_6") (pintype "passive"))
      (node (ref "U27") (pin "60") (pinfunction "DVDD_60") (pintype "passive"))
      (node (ref "U27") (pin "62") (pinfunction "DVDD_62") (pintype "passive"))
      (node (ref "U27") (pin "63") (pinfunction "DVDD_63") (pintype "passive"))
      (node (ref "U4") (pin "13") (pinfunction "DVDD_13") (pintype "passive"))
      (node (ref "U4") (pin "14") (pinfunction "DVDD_14") (pintype "passive"))
      (node (ref "U4") (pin "19") (pinfunction "DVDD_19") (pintype "passive"))
      (node (ref "U4") (pin "20") (pinfunction "DVDD_20") (pintype "passive"))
      (node (ref "U4") (pin "21") (pinfunction "DVDD_21") (pintype "passive"))
      (node (ref "U4") (pin "22") (pinfunction "DVDD_22") (pintype "passive"))
      (node (ref "U4") (pin "26") (pinfunction "DVDD_26") (pintype "passive"))
      (node (ref "U4") (pin "27") (pinfunction "DVDD_27") (pintype "passive"))
      (node (ref "U4") (pin "29") (pinfunction "DVDD_29") (pintype "passive"))
      (node (ref "U4") (pin "3") (pinfunction "DVDD_3") (pintype "passive"))
      (node (ref "U4") (pin "30") (pinfunction "DVDD_30") (pintype "passive"))
      (node (ref "U4") (pin "34") (pinfunction "DVDD_34") (pintype "passive"))
      (node (ref "U4") (pin "35") (pinfunction "DVDD_35") (pintype "passive"))
      (node (ref "U4") (pin "37") (pinfunction "DVDD_37") (pintype "passive"))
      (node (ref "U4") (pin "38") (pinfunction "DVDD_38") (pintype "passive"))
      (node (ref "U4") (pin "39") (pinfunction "DVDD_39") (pintype "passive"))
      (node (ref "U4") (pin "4") (pinfunction "DVDD_4") (pintype "passive"))
      (node (ref "U4") (pin "41") (pinfunction "DVDD_41") (pintype "passive"))
      (node (ref "U4") (pin "42") (pinfunction "DVDD_42") (pintype "passive"))
      (node (ref "U4") (pin "43") (pinfunction "DVDD_43") (pintype "passive"))
      (node (ref "U4") (pin "45") (pinfunction "DVDD_45") (pintype "passive"))
      (node (ref "U4") (pin "46") (pinfunction "DVDD_46") (pintype "passive"))
      (node (ref "U4") (pin "5") (pinfunction "DVDD_5") (pintype "passive"))
      (node (ref "U4") (pin "51") (pinfunction "DVDD_51") (pintype "passive"))
      (node (ref "U4") (pin "52") (pinfunction "DVDD_52") (pintype "passive"))
      (node (ref "U4") (pin "54") (pinfunction "DVDD_54") (pintype "passive"))
      (node (ref "U4") (pin "55") (pinfunction "DVDD_55") (pintype "passive"))
      (node (ref "U4") (pin "58") (pinfunction "DVDD_58") (pintype "passive"))
      (node (ref "U4") (pin "59") (pinfunction "DVDD_59") (pintype "passive"))
      (node (ref "U4") (pin "6") (pinfunction "DVDD_6") (pintype "passive"))
      (node (ref "U4") (pin "60") (pinfunction "DVDD_60") (pintype "passive"))
      (node (ref "U4") (pin "62") (pinfunction "DVDD_62") (pintype "passive"))
      (node (ref "U4") (pin "63") (pinfunction "DVDD_63") (pintype "passive"))
      (node (ref "U5") (pin "13") (pinfunction "DVDD_13") (pintype "passive"))
      (node (ref "U5") (pin "14") (pinfunction "DVDD_14") (pintype "passive"))
      (node (ref "U5") (pin "19") (pinfunction "DVDD_19") (pintype "passive"))
      (node (ref "U5") (pin "20") (pinfunction "DVDD_20") (pintype "passive"))
      (node (ref "U5") (pin "21") (pinfunction "DVDD_21") (pintype "passive"))
      (node (ref "U5") (pin "22") (pinfunction "DVDD_22") (pintype "passive"))
      (node (ref "U5") (pin "26") (pinfunction "DVDD_26") (pintype "passive"))
      (node (ref "U5") (pin "27") (pinfunction "DVDD_27") (pintype "passive"))
      (node (ref "U5") (pin "29") (pinfunction "DVDD_29") (pintype "passive"))
      (node (ref "U5") (pin "3") (pinfunction "DVDD_3") (pintype "passive"))
      (node (ref "U5") (pin "30") (pinfunction "DVDD_30") (pintype "passive"))
      (node (ref "U5") (pin "34") (pinfunction "DVDD_34") (pintype "passive"))
      (node (ref "U5") (pin "35") (pinfunction "DVDD_35") (pintype "passive"))
      (node (ref "U5") (pin "37") (pinfunction "DVDD_37") (pintype "passive"))
      (node (ref "U5") (pin "38") (pinfunction "DVDD_38") (pintype "passive"))
      (node (ref "U5") (pin "39") (pinfunction "DVDD_39") (pintype "passive"))
      (node (ref "U5") (pin "4") (pinfunction "DVDD_4") (pintype "passive"))
      (node (ref "U5") (pin "41") (pinfunction "DVDD_41") (pintype "passive"))
      (node (ref "U5") (pin "42") (pinfunction "DVDD_42") (pintype "passive"))
      (node (ref "U5") (pin "43") (pinfunction "DVDD_43") (pintype "passive"))
      (node (ref "U5") (pin "45") (pinfunction "DVDD_45") (pintype "passive"))
      (node (ref "U5") (pin "46") (pinfunction "DVDD_46") (pintype "passive"))
      (node (ref "U5") (pin "5") (pinfunction "DVDD_5") (pintype "passive"))
      (node (ref "U5") (pin "51") (pinfunction "DVDD_51") (pintype "passive"))
      (node (ref "U5") (pin "52") (pinfunction "DVDD_52") (pintype "passive"))
      (node (ref "U5") (pin "54") (pinfunction "DVDD_54") (pintype "passive"))
      (node (ref "U5") (pin "55") (pinfunction "DVDD_55") (pintype "passive"))
      (node (ref "U5") (pin "58") (pinfunction "DVDD_58") (pintype "passive"))
      (node (ref "U5") (pin "59") (pinfunction "DVDD_59") (pintype "passive"))
      (node (ref "U5") (pin "6") (pinfunction "DVDD_6") (pintype "passive"))
      (node (ref "U5") (pin "60") (pinfunction "DVDD_60") (pintype "passive"))
      (node (ref "U5") (pin "62") (pinfunction "DVDD_62") (pintype "passive"))
      (node (ref "U5") (pin "63") (pinfunction "DVDD_63") (pintype "passive"))
      (node (ref "U6") (pin "13") (pinfunction "DVDD_13") (pintype "passive"))
      (node (ref "U6") (pin "14") (pinfunction "DVDD_14") (pintype "passive"))
      (node (ref "U6") (pin "19") (pinfunction "DVDD_19") (pintype "passive"))
      (node (ref "U6") (pin "20") (pinfunction "DVDD_20") (pintype "passive"))
      (node (ref "U6") (pin "21") (pinfunction "DVDD_21") (pintype "passive"))
      (node (ref "U6") (pin "22") (pinfunction "DVDD_22") (pintype "passive"))
      (node (ref "U6") (pin "26") (pinfunction "DVDD_26") (pintype "passive"))
      (node (ref "U6") (pin "27") (pinfunction "DVDD_27") (pintype "passive"))
      (node (ref "U6") (pin "29") (pinfunction "DVDD_29") (pintype "passive"))
      (node (ref "U6") (pin "3") (pinfunction "DVDD_3") (pintype "passive"))
      (node (ref "U6") (pin "30") (pinfunction "DVDD_30") (pintype "passive"))
      (node (ref "U6") (pin "34") (pinfunction "DVDD_34") (pintype "passive"))
      (node (ref "U6") (pin "35") (pinfunction "DVDD_35") (pintype "passive"))
      (node (ref "U6") (pin "37") (pinfunction "DVDD_37") (pintype "passive"))
      (node (ref "U6") (pin "38") (pinfunction "DVDD_38") (pintype "passive"))
      (node (ref "U6") (pin "39") (pinfunction "DVDD_39") (pintype "passive"))
      (node (ref "U6") (pin "4") (pinfunction "DVDD_4") (pintype "passive"))
      (node (ref "U6") (pin "41") (pinfunction "DVDD_41") (pintype "passive"))
      (node (ref "U6") (pin "42") (pinfunction "DVDD_42") (pintype "passive"))
      (node (ref "U6") (pin "43") (pinfunction "DVDD_43") (pintype "passive"))
      (node (ref "U6") (pin "45") (pinfunction "DVDD_45") (pintype "passive"))
      (node (ref "U6") (pin "46") (pinfunction "DVDD_46") (pintype "passive"))
      (node (ref "U6") (pin "5") (pinfunction "DVDD_5") (pintype "passive"))
      (node (ref "U6") (pin "51") (pinfunction "DVDD_51") (pintype "passive"))
      (node (ref "U6") (pin "52") (pinfunction "DVDD_52") (pintype "passive"))
      (node (ref "U6") (pin "54") (pinfunction "DVDD_54") (pintype "passive"))
      (node (ref "U6") (pin "55") (pinfunction "DVDD_55") (pintype "passive"))
      (node (ref "U6") (pin "58") (pinfunction "DVDD_58") (pintype "passive"))
      (node (ref "U6") (pin "59") (pinfunction "DVDD_59") (pintype "passive"))
      (node (ref "U6") (pin "6") (pinfunction "DVDD_6") (pintype "passive"))
      (node (ref "U6") (pin "60") (pinfunction "DVDD_60") (pintype "passive"))
      (node (ref "U6") (pin "62") (pinfunction "DVDD_62") (pintype "passive"))
      (node (ref "U6") (pin "63") (pinfunction "DVDD_63") (pintype "passive"))
      (node (ref "U7") (pin "13") (pinfunction "DVDD_13") (pintype "passive"))
      (node (ref "U7") (pin "14") (pinfunction "DVDD_14") (pintype "passive"))
      (node (ref "U7") (pin "19") (pinfunction "DVDD_19") (pintype "passive"))
      (node (ref "U7") (pin "20") (pinfunction "DVDD_20") (pintype "passive"))
      (node (ref "U7") (pin "21") (pinfunction "DVDD_21") (pintype "passive"))
      (node (ref "U7") (pin "22") (pinfunction "DVDD_22") (pintype "passive"))
      (node (ref "U7") (pin "26") (pinfunction "DVDD_26") (pintype "passive"))
      (node (ref "U7") (pin "27") (pinfunction "DVDD_27") (pintype "passive"))
      (node (ref "U7") (pin "29") (pinfunction "DVDD_29") (pintype "passive"))
      (node (ref "U7") (pin "3") (pinfunction "DVDD_3") (pintype "passive"))
      (node (ref "U7") (pin "30") (pinfunction "DVDD_30") (pintype "passive"))
      (node (ref "U7") (pin "34") (pinfunction "DVDD_34") (pintype "passive"))
      (node (ref "U7") (pin "35") (pinfunction "DVDD_35") (pintype "passive"))
      (node (ref "U7") (pin "37") (pinfunction "DVDD_37") (pintype "passive"))
      (node (ref "U7") (pin "38") (pinfunction "DVDD_38") (pintype "passive"))
      (node (ref "U7") (pin "39") (pinfunction "DVDD_39") (pintype "passive"))
      (node (ref "U7") (pin "4") (pinfunction "DVDD_4") (pintype "passive"))
      (node (ref "U7") (pin "41") (pinfunction "DVDD_41") (pintype "passive"))
      (node (ref "U7") (pin "42") (pinfunction "DVDD_42") (pintype "passive"))
      (node (ref "U7") (pin "43") (pinfunction "DVDD_43") (pintype "passive"))
      (node (ref "U7") (pin "45") (pinfunction "DVDD_45") (pintype "passive"))
      (node (ref "U7") (pin "46") (pinfunction "DVDD_46") (pintype "passive"))
      (node (ref "U7") (pin "5") (pinfunction "DVDD_5") (pintype "passive"))
      (node (ref "U7") (pin "51") (pinfunction "DVDD_51") (pintype "passive"))
      (node (ref "U7") (pin "52") (pinfunction "DVDD_52") (pintype "passive"))
      (node (ref "U7") (pin "54") (pinfunction "DVDD_54") (pintype "passive"))
      (node (ref "U7") (pin "55") (pinfunction "DVDD_55") (pintype "passive"))
      (node (ref "U7") (pin "58") (pinfunction "DVDD_58") (pintype "passive"))
      (node (ref "U7") (pin "59") (pinfunction "DVDD_59") (pintype "passive"))
      (node (ref "U7") (pin "6") (pinfunction "DVDD_6") (pintype "passive"))
      (node (ref "U7") (pin "60") (pinfunction "DVDD_60") (pintype "passive"))
      (node (ref "U7") (pin "62") (pinfunction "DVDD_62") (pintype "passive"))
      (node (ref "U7") (pin "63") (pinfunction "DVDD_63") (pintype "passive"))
      (node (ref "U9") (pin "13") (pinfunction "DVDD_13") (pintype "passive"))
      (node (ref "U9") (pin "14") (pinfunction "DVDD_14") (pintype "passive"))
      (node (ref "U9") (pin "19") (pinfunction "DVDD_19") (pintype "passive"))
      (node (ref "U9") (pin "20") (pinfunction "DVDD_20") (pintype "passive"))
      (node (ref "U9") (pin "21") (pinfunction "DVDD_21") (pintype "passive"))
      (node (ref "U9") (pin "22") (pinfunction "DVDD_22") (pintype "passive"))
      (node (ref "U9") (pin "26") (pinfunction "DVDD_26") (pintype "passive"))
      (node (ref "U9") (pin "27") (pinfunction "DVDD_27") (pintype "passive"))
      (node (ref "U9") (pin "29") (pinfunction "DVDD_29") (pintype "passive"))
      (node (ref "U9") (pin "3") (pinfunction "DVDD_3") (pintype "passive"))
      (node (ref "U9") (pin "30") (pinfunction "DVDD_30") (pintype "passive"))
      (node (ref "U9") (pin "34") (pinfunction "DVDD_34") (pintype "passive"))
      (node (ref "U9") (pin "35") (pinfunction "DVDD_35") (pintype "passive"))
      (node (ref "U9") (pin "37") (pinfunction "DVDD_37") (pintype "passive"))
      (node (ref "U9") (pin "38") (pinfunction "DVDD_38") (pintype "passive"))
      (node (ref "U9") (pin "39") (pinfunction "DVDD_39") (pintype "passive"))
      (node (ref "U9") (pin "4") (pinfunction "DVDD_4") (pintype "passive"))
      (node (ref "U9") (pin "41") (pinfunction "DVDD_41") (pintype "passive"))
      (node (ref "U9") (pin "42") (pinfunction "DVDD_42") (pintype "passive"))
      (node (ref "U9") (pin "43") (pinfunction "DVDD_43") (pintype "passive"))
      (node (ref "U9") (pin "45") (pinfunction "DVDD_45") (pintype "passive"))
      (node (ref "U9") (pin "46") (pinfunction "DVDD_46") (pintype "passive"))
      (node (ref "U9") (pin "5") (pinfunction "DVDD_5") (pintype "passive"))
      (node (ref "U9") (pin "51") (pinfunction "DVDD_51") (pintype "passive"))
      (node (ref "U9") (pin "52") (pinfunction "DVDD_52") (pintype "passive"))
      (node (ref "U9") (pin "54") (pinfunction "DVDD_54") (pintype "passive"))
      (node (ref "U9") (pin "55") (pinfunction "DVDD_55") (pintype "passive"))
      (node (ref "U9") (pin "58") (pinfunction "DVDD_58") (pintype "passive"))
      (node (ref "U9") (pin "59") (pinfunction "DVDD_59") (pintype "passive"))
      (node (ref "U9") (pin "6") (pinfunction "DVDD_6") (pintype "passive"))
      (node (ref "U9") (pin "60") (pinfunction "DVDD_60") (pintype "passive"))
      (node (ref "U9") (pin "62") (pinfunction "DVDD_62") (pintype "passive"))
      (node (ref "U9") (pin "63") (pinfunction "DVDD_63") (pintype "passive"))
    )
    (net (code "2") (name "/3.3V") (class "Default")
      (node (ref "C122") (pin "2") (pinfunction "2_2") (pintype "passive"))
      (node (ref "C127") (pin "2") (pinfunction "2_2") (pintype "passive"))
      (node (ref "C132") (pin "2") (pinfunction "2_2") (pintype "passive"))
      (node (ref "C137") (pin "2") (pinfunction "2_2") (pintype "passive"))
      (node (ref "C167") (pin "1") (pinfunction "1_1") (pintype "passive"))
      (node (ref "C169") (pin "1") (pinfunction "1_1") (pintype "passive"))
      (node (ref "C170") (pin "1") (pinfunction "1_1") (pintype "passive"))
      (node (ref "C171") (pin "1") (pinfunction "1_1") (pintype "passive"))
      (node (ref "C172") (pin "1") (pinfunction "1_1") (pintype "passive"))
      (node (ref "C178") (pin "2") (pinfunction "2_2") (pintype "passive"))
      (node (ref "C182") (pin "2") (pinfunction "2_2") (pintype "passive"))
      (node (ref "C186") (pin "2") (pinfunction "2_2") (pintype "passive"))
      (node (ref "C190") (pin "2") (pinfunction "2_2") (pintype "passive"))
      (node (ref "C224") (pin "2") (pinfunction "2_2") (pintype "passive"))
      (node (ref "C225") (pin "1") (pinfunction "1_1") (pintype "passive"))
      (node (ref "C231") (pin "2") (pinfunction "2_2") (pintype "passive"))
      (node (ref "C236") (pin "2") (pinfunction "2_2") (pintype "passive"))
      (node (ref "C241") (pin "2") (pinfunction "2_2") (pintype "passive"))
      (node (ref "C246") (pin "2") (pinfunction "2_2") (pintype "passive"))
      (node (ref "C275") (pin "1") (pinfunction "1_1") (pintype "passive"))
      (node (ref "C279") (pin "2") (pinfunction "2_2") (pintype "passive"))
      (node (ref "C283") (pin "2") (pinfunction "2_2") (pintype "passive"))
      (node (ref "C287") (pin "2") (pinfunction "2_2") (pintype "passive"))
      (node (ref "C29") (pin "2") (pinfunction "2_2") (pintype "passive"))
      (node (ref "C291") (pin "2") (pinfunction "2_2") (pintype "passive"))
      (node (ref "C328") (pin "2") (pinfunction "2_2") (pintype "passive"))
      (node (ref "C333") (pin "2") (pinfunction "2_2") (pintype "passive"))
      (node (ref "C338") (pin "2") (pinfunction "2_2") (pintype "passive"))
      (node (ref "C34") (pin "2") (pinfunction "2_2") (pintype "passive"))
      (node (ref "C343") (pin "2") (pinfunction "2_2") (pintype "passive"))
      (node (ref "C371") (pin "2") (pinfunction "2_2") (pintype "passive"))
      (node (ref "C375") (pin "2") (pinfunction "2_2") (pintype "passive"))
      (node (ref "C379") (pin "2") (pinfunction "2_2") (pintype "passive"))
      (node (ref "C383") (pin "2") (pinfunction "2_2") (pintype "passive"))
      (node (ref "C39") (pin "2") (pinfunction "2_2") (pintype "passive"))
      (node (ref "C44") (pin "2") (pinfunction "2_2") (pintype "passive"))
      (node (ref "C69") (pin "1") (pinfunction "1_1") (pintype "passive"))
      (node (ref "C73") (pin "2") (pinfunction "2_2") (pintype "passive"))
      (node (ref "C77") (pin "2") (pinfunction "2_2") (pintype "passive"))
      (node (ref "C81") (pin "2") (pinfunction "2_2") (pintype "passive"))
      (node (ref "C85") (pin "2") (pinfunction "2_2") (pintype "passive"))
      (node (ref "J1") (pin "2") (pinfunction "2_2") (pintype "passive"))
      (node (ref "R31") (pin "2") (pinfunction "2_2") (pintype "passive"))
      (node (ref "R48") (pin "2") (pinfunction "2_2") (pintype "passive"))
      (node (ref "R5") (pin "2") (pinfunction "2_2") (pintype "passive"))
      (node (ref "R53") (pin "2") (pinfunction "2_2") (pintype "passive"))
      (node (ref "R54") (pin "1") (pinfunction "1_1") (pintype "passive"))
      (node (ref "R6") (pin "2") (pinfunction "2_2") (pintype "passive"))
      (node (ref "R7") (pin "2") (pinfunction "2_2") (pintype "passive"))
      (node (ref "R8") (pin "1") (pinfunction "1_1") (pintype "passive"))
      (node (ref "U10") (pin "16") (pinfunction "CHIP_ID0_16") (pintype "passive"))
      (node (ref "U10") (pin "18") (pinfunction "CHIP_ID2_18") (pintype "passive"))
      (node (ref "U10") (pin "32") (pinfunction "OVDD1_32") (pintype "passive"))
      (node (ref "U10") (pin "49") (pinfunction "OVDD0_49") (pintype "passive"))
      (node (ref "U11") (pin "17") (pinfunction "CHIP_ID1_17") (pintype "passive"))
      (node (ref "U11") (pin "18") (pinfunction "CHIP_ID2_18") (pintype "passive"))
      (node (ref "U11") (pin "32") (pinfunction "OVDD1_32") (pintype "passive"))
      (node (ref "U11") (pin "49") (pinfunction "OVDD0_49") (pintype "passive"))
      (node (ref "U12") (pin "16") (pinfunction "CHIP_ID0_16") (pintype "passive"))
      (node (ref "U12") (pin "17") (pinfunction "CHIP_ID1_17") (pintype "passive"))
      (node (ref "U12") (pin "18") (pinfunction "CHIP_ID2_18") (pintype "passive"))
      (node (ref "U12") (pin "32") (pinfunction "OVDD1_32") (pintype "passive"))
      (node (ref "U12") (pin "49") (pinfunction "OVDD0_49") (pintype "passive"))
      (node (ref "U14") (pin "5") (pinfunction "OUT_5") (pintype "passive"))
      (node (ref "U15") (pin "1") (pinfunction "OUT_1") (pintype "passive"))
      (node (ref "U18") (pin "32") (pinfunction "OVDD1_32") (pintype "passive"))
      (node (ref "U18") (pin "49") (pinfunction "OVDD0_49") (pintype "passive"))
      (node (ref "U19") (pin "16") (pinfunction "CHIP_ID0_16") (pintype "passive"))
      (node (ref "U19") (pin "32") (pinfunction "OVDD1_32") (pintype "passive"))
      (node (ref "U19") (pin "49") (pinfunction "OVDD0_49") (pintype "passive"))
      (node (ref "U20") (pin "17") (pinfunction "CHIP_ID1_17") (pintype "passive"))
      (node (ref "U20") (pin "32") (pinfunction "OVDD1_32") (pintype "passive"))
      (node (ref "U20") (pin "49") (pinfunction "OVDD0_49") (pintype "passive"))
      (node (ref "U21") (pin "17") (pinfunction "CHIP_ID1_17") (pintype "passive"))
      (node (ref "U21") (pin "18") (pinfunction "CHIP_ID2_18") (pintype "passive"))
      (node (ref "U21") (pin "32") (pinfunction "OVDD1_32") (pintype "passive"))
      (node (ref "U21") (pin "49") (pinfunction "OVDD0_49") (pintype "passive"))
      (node (ref "U24") (pin "18") (pinfunction "CHIP_ID2_18") (pintype "passive"))
      (node (ref "U24") (pin "32") (pinfunction "OVDD1_32") (pintype "passive"))
      (node (ref "U24") (pin "49") (pinfunction "OVDD0_49") (pintype "passive"))
      (node (ref "U25") (pin "16") (pinfunction "CHIP_ID0_16") (pintype "passive"))
      (node (ref "U25") (pin "18") (pinfunction "CHIP_ID2_18") (pintype "passive"))
      (node (ref "U25") (pin "32") (pinfunction "OVDD1_32") (pintype "passive"))
      (node (ref "U25") (pin "49") (pinfunction "OVDD0_49") (pintype "passive"))
      (node (ref "U26") (pin "17") (pinfunction "CHIP_ID1_17") (pintype "passive"))
      (node (ref "U26") (pin "18") (pinfunction "CHIP_ID2_18") (pintype "passive"))
      (node (ref "U26") (pin "32") (pinfunction "OVDD1_32") (pintype "passive"))
      (node (ref "U26") (pin "49") (pinfunction "OVDD0_49") (pintype "passive"))
      (node (ref "U27") (pin "16") (pinfunction "CHIP_ID0_16") (pintype "passive"))
      (node (ref "U27") (pin "17") (pinfunction "CHIP_ID1_17") (pintype "passive"))
      (node (ref "U27") (pin "18") (pinfunction "CHIP_ID2_18") (pintype "passive"))
      (node (ref "U27") (pin "32") (pinfunction "OVDD1_32") (pintype "passive"))
      (node (ref "U27") (pin "49") (pinfunction "OVDD0_49") (pintype "passive"))
      (node (ref "U4") (pin "32") (pinfunction "OVDD1_32") (pintype "passive"))
      (node (ref "U4") (pin "49") (pinfunction "OVDD0_49") (pintype "passive"))
      (node (ref "U5") (pin "16") (pinfunction "CHIP_ID0_16") (pintype "passive"))
      (node (ref "U5") (pin "32") (pinfunction "OVDD1_32") (pintype "passive"))
      (node (ref "U5") (pin "49") (pinfunction "OVDD0_49") (pintype "passive"))
      (node (ref "U6") (pin "17") (pinfunction "CHIP_ID1_17") (pintype "passive"))
      (node (ref "U6") (pin "32") (pinfunction "OVDD1_32") (pintype "passive"))
      (node (ref "U6") (pin "49") (pinfunction "OVDD0_49") (pintype "passive"))
      (node (ref "U7") (pin "16") (pinfunction "CHIP_ID0_16") (pintype "passive"))
      (node (ref "U7") (pin "17") (pinfunction "CHIP_ID1_17") (pintype "passive"))
      (node (ref "U7") (pin "32") (pinfunction "OVDD1_32") (pintype "passive"))
      (node (ref "U7") (pin "49") (pinfunction "OVDD0_49") (pintype "passive"))
      (node (ref "U8") (pin "10") (pinfunction "VDD_10") (pintype "passive"))
      (node (ref "U8") (pin "19") (pinfunction "AVDD_19") (pintype "passive"))
      (node (ref "U8") (pin "26") (pinfunction "VDD_26") (pintype "passive"))
      (node (ref "U8") (pin "35") (pinfunction "VUSB3V3_35") (pintype "passive"))
      (node (ref "U8") (pin "38") (pinfunction "VDD_38") (pintype "passive"))
      (node (ref "U8") (pin "57") (pinfunction "VDD_57") (pintype "passive"))
      (node (ref "U9") (pin "18") (pinfunction "CHIP_ID2_18") (pintype "passive"))
      (node (ref "U9") (pin "32") (pinfunction "OVDD1_32") (pintype "passive"))
      (node (ref "U9") (pin "49") (pinfunction "OVDD0_49") (pintype "passive"))
    )
    (net (code "3") (name "/5.0V") (class "Default")
      (node (ref "C1") (pin "2") (pinfunction "2_2") (pintype "passive"))
      (node (ref "C191") (pin "1") (pinfunction "1_1") (pintype "passive"))
      (node (ref "C2") (pin "2") (pinfunction "2_2") (pintype "passive"))
      (node (ref "C3") (pin "2") (pinfunction "2_2") (pintype "passive"))
      (node (ref "D1") (pin "1") (pinfunction "A1_1") (pintype "passive"))
      (node (ref "D1") (pin "2") (pinfunction "A2_2") (pintype "passive"))
      (node (ref "D10") (pin "1") (pinfunction "C_1") (pintype "passive"))
      (node (ref "D2") (pin "1") (pinfunction "A1_1") (pintype "passive"))
      (node (ref "D2") (pin "2") (pinfunction "A2_2") (pintype "passive"))
      (node (ref "D3") (pin "1") (pinfunction "A1_1") (pintype "passive"))
      (node (ref "D3") (pin "2") (pinfunction "A2_2") (pintype "passive"))
      (node (ref "D8") (pin "2") (pinfunction "A_2") (pintype "passive"))
      (node (ref "J3") (pin "1") (pinfunction "1_1") (pintype "passive"))
      (node (ref "R42") (pin "1") (pinfunction "1_1") (pintype "passive"))
      (node (ref "U1") (pin "7") (pinfunction "VCC_7") (pintype "passive"))
      (node (ref "U13") (pin "1") (pinfunction "OUTPUT_1") (pintype "passive"))
      (node (ref "U16") (pin "3") (pinfunction "Vout_3") (pintype "passive"))
      (node (ref "U17") (pin "3") (pinfunction "Vout_3") (pintype "passive"))
      (node (ref "U2") (pin "7") (pinfunction "VCC_7") (pintype "passive"))
      (node (ref "U3") (pin "7") (pinfunction "VCC_7") (pintype "passive"))
    )
    (net (code "4") (name "/12V") (class "Default")
      (node (ref "C10") (pin "2") (pinfunction "2_2") (pintype "passive"))
      (node (ref "C11") (pin "2") (pinfunction "2_2") (pintype "passive"))
      (node (ref "C15") (pin "2") (pinfunction "2_2") (pintype "passive"))
      (node (ref "C16") (pin "2") (pinfunction "2_2") (pintype "passive"))
      (node (ref "C20") (pin "1") (pinfunction "1_1") (pintype "passive"))
      (node (ref "C21") (pin "1") (pinfunction "1_1") (pintype "passive"))
      (node (ref "D11") (pin "2") (pinfunction "A_2") (pintype "passive"))
      (node (ref "D12") (pin "1") (pinfunction "C_1") (pintype "passive"))
      (node (ref "J3") (pin "3") (pinfunction "3_3") (pintype "passive"))
      (node (ref "J4") (pin "1") (pinfunction "1_1") (pintype "passive"))
      (node (ref "J4") (pin "2") (pinfunction "2_2") (pintype "passive"))
      (node (ref "J4") (pin "3") (pinfunction "3_3") (pintype "passive"))
      (node (ref "Q1") (pin "5") (pinfunction "D_5") (pintype "passive"))
      (node (ref "Q1") (pin "6") (pinfunction "D_6") (pintype "passive"))
      (node (ref "Q1") (pin "7") (pinfunction "D_7") (pintype "passive"))
      (node (ref "Q1") (pin "8") (pinfunction "D_8") (pintype "passive"))
      (node (ref "Q2") (pin "5") (pinfunction "D_5") (pintype "passive"))
      (node (ref "Q2") (pin "6") (pinfunction "D_6") (pintype "passive"))
      (node (ref "Q2") (pin "7") (pinfunction "D_7") (pintype "passive"))
      (node (ref "Q2") (pin "8") (pinfunction "D_8") (pintype "passive"))
      (node (ref "Q3") (pin "5") (pinfunction "D_5") (pintype "passive"))
      (node (ref "Q3") (pin "6") (pinfunction "D_6") (pintype "passive"))
      (node (ref "Q3") (pin "7") (pinfunction "D_7") (pintype "passive"))
      (node (ref "Q3") (pin "8") (pinfunction "D_8") (pintype "passive"))
      (node (ref "R23") (pin "1") (pinfunction "1_1") (pintype "passive"))
      (node (ref "R47") (pin "2") (pinfunction "2_2") (pintype "passive"))
    )
    (net (code "5") (name "/ASIC_RESET_MCU") (class "Default")
      (node (ref "C120") (pin "2") (pinfunction "2_2") (pintype "passive"))
      (node (ref "C125") (pin "2") (pinfunction "2_2") (pintype "passive"))
      (node (ref "C130") (pin "2") (pinfunction "2_2") (pintype "passive"))
      (node (ref "C135") (pin "2") (pinfunction "2_2") (pintype "passive"))
      (node (ref "C229") (pin "2") (pinfunction "2_2") (pintype "passive"))
      (node (ref "C234") (pin "2") (pinfunction "2_2") (pintype "passive"))
      (node (ref "C239") (pin "2") (pinfunction "2_2") (pintype "passive"))
      (node (ref "C244") (pin "2") (pinfunction "2_2") (pintype "passive"))
      (node (ref "C27") (pin "2") (pinfunction "2_2") (pintype "passive"))
      (node (ref "C32") (pin "2") (pinfunction "2_2") (pintype "passive"))
      (node (ref "C326") (pin "2") (pinfunction "2_2") (pintype "passive"))
      (node (ref "C331") (pin "2") (pinfunction "2_2") (pintype "passive"))
      (node (ref "C336") (pin "2") (pinfunction "2_2") (pintype "passive"))
      (node (ref "C341") (pin "2") (pinfunction "2_2") (pintype "passive"))
      (node (ref "C37") (pin "2") (pinfunction "2_2") (pintype "passive"))
      (node (ref "C42") (pin "2") (pinfunction "2_2") (pintype "passive"))
      (node (ref "R5") (pin "1") (pinfunction "1_1") (pintype "passive"))
      (node (ref "U10") (pin "57") (pinfunction "RSTN_57") (pintype "passive"))
      (node (ref "U11") (pin "57") (pinfunction "RSTN_57") (pintype "passive"))
      (node (ref "U12") (pin "57") (pinfunction "RSTN_57") (pintype "passive"))
      (node (ref "U18") (pin "57") (pinfunction "RSTN_57") (pintype "passive"))
      (node (ref "U19") (pin "57") (pinfunction "RSTN_57") (pintype "passive"))
      (node (ref "U20") (pin "57") (pinfunction "RSTN_57") (pintype "passive"))
      (node (ref "U21") (pin "57") (pinfunction "RSTN_57") (pintype "passive"))
      (node (ref "U24") (pin "57") (pinfunction "RSTN_57") (pintype "passive"))
      (node (ref "U25") (pin "57") (pinfunction "RSTN_57") (pintype "passive"))
      (node (ref "U26") (pin "57") (pinfunction "RSTN_57") (pintype "passive"))
      (node (ref "U27") (pin "57") (pinfunction "RSTN_57") (pintype "passive"))
      (node (ref "U4") (pin "57") (pinfunction "RSTN_57") (pintype "passive"))
      (node (ref "U5") (pin "57") (pinfunction "RSTN_57") (pintype "passive"))
      (node (ref "U6") (pin "57") (pinfunction "RSTN_57") (pintype "passive"))
      (node (ref "U7") (pin "57") (pinfunction "RSTN_57") (pintype "passive"))
      (node (ref "U8") (pin "5") (pinfunction "C1IN1-/SDI2/PMA4/RPI119/RG7_5") (pintype "passive"))
      (node (ref "U9") (pin "57") (pinfunction "RSTN_57") (pintype "passive"))
    )
    (net (code "6") (name "/BOOT1") (class "Default")
      (node (ref "C7") (pin "1") (pinfunction "1_1") (pintype "passive"))
      (node (ref "D1") (pin "3") (pinfunction "CC_3") (pintype "passive"))
      (node (ref "U1") (pin "8") (pinfunction "BOOST_8") (pintype "passive"))
    )
    (net (code "7") (name "/BOOT2") (class "Default")
      (node (ref "C8") (pin "1") (pinfunction "1_1") (pintype "passive"))
      (node (ref "D2") (pin "3") (pinfunction "CC_3") (pintype "passive"))
      (node (ref "U2") (pin "8") (pinfunction "BOOST_8") (pintype "passive"))
    )
    (net (code "8") (name "/BOOT3") (class "Default")
      (node (ref "C9") (pin "1") (pinfunction "1_1") (pintype "passive"))
      (node (ref "D3") (pin "3") (pinfunction "CC_3") (pintype "passive"))
      (node (ref "U3") (pin "8") (pinfunction "BOOST_8") (pintype "passive"))
    )
    (net (code "9") (name "/CORE_CLKOUT_1") (class "Default")
      (node (ref "R1") (pin "2") (pinfunction "2_2") (pintype "passive"))
      (node (ref "U4") (pin "56") (pinfunction "CORE_CLKOUT_56") (pintype "passive"))
    )
    (net (code "10") (name "/CORE_CLKOUT_2") (class "Default")
      (node (ref "R2") (pin "2") (pinfunction "2_2") (pintype "passive"))
      (node (ref "U5") (pin "56") (pinfunction "CORE_CLKOUT_56") (pintype "passive"))
    )
    (net (code "11") (name "/CORE_CLKOUT_3") (class "Default")
      (node (ref "R3") (pin "2") (pinfunction "2_2") (pintype "passive"))
      (node (ref "U6") (pin "56") (pinfunction "CORE_CLKOUT_56") (pintype "passive"))
    )
    (net (code "12") (name "/CORE_CLKOUT_4") (class "Default")
      (node (ref "R4") (pin "2") (pinfunction "2_2") (pintype "passive"))
      (node (ref "U7") (pin "56") (pinfunction "CORE_CLKOUT_56") (pintype "passive"))
    )
    (net (code "13") (name "/CORE_CLKOUT_5") (class "Default")
      (node (ref "R17") (pin "1") (pinfunction "1_1") (pintype "passive"))
      (node (ref "U9") (pin "56") (pinfunction "CORE_CLKOUT_56") (pintype "passive"))
    )
    (net (code "14") (name "/CORE_CLKOUT_6") (class "Default")
      (node (ref "R18") (pin "2") (pinfunction "2_2") (pintype "passive"))
      (node (ref "U10") (pin "56") (pinfunction "CORE_CLKOUT_56") (pintype "passive"))
    )
    (net (code "15") (name "/CORE_CLKOUT_7") (class "Default")
      (node (ref "R19") (pin "2") (pinfunction "2_2") (pintype "passive"))
      (node (ref "U11") (pin "56") (pinfunction "CORE_CLKOUT_56") (pintype "passive"))
    )
    (net (code "16") (name "/CORE_CLKOUT_8") (class "Default")
      (node (ref "R20") (pin "2") (pinfunction "2_2") (pintype "passive"))
      (node (ref "U12") (pin "56") (pinfunction "CORE_CLKOUT_56") (pintype "passive"))
    )
    (net (code "17") (name "/CORE_CLKOUT_9") (class "Default")
      (node (ref "R43") (pin "2") (pinfunction "2_2") (pintype "passive"))
      (node (ref "U18") (pin "56") (pinfunction "CORE_CLKOUT_56") (pintype "passive"))
    )
    (net (code "18") (name "/CORE_CLKOUT_10") (class "Default")
      (node (ref "R44") (pin "2") (pinfunction "2_2") (pintype "passive"))
      (node (ref "U19") (pin "56") (pinfunction "CORE_CLKOUT_56") (pintype "passive"))
    )
    (net (code "19") (name "/CORE_CLKOUT_11") (class "Default")
      (node (ref "R45") (pin "2") (pinfunction "2_2") (pintype "passive"))
      (node (ref "U20") (pin "56") (pinfunction "CORE_CLKOUT_56") (pintype "passive"))
    )
    (net (code "20") (name "/CORE_CLKOUT_12") (class "Default")
      (node (ref "R46") (pin "2") (pinfunction "2_2") (pintype "passive"))
      (node (ref "U21") (pin "56") (pinfunction "CORE_CLKOUT_56") (pintype "passive"))
    )
    (net (code "21") (name "/CORE_CLKOUT_13") (class "Default")
      (node (ref "R64") (pin "2") (pinfunction "2_2") (pintype "passive"))
      (node (ref "U24") (pin "56") (pinfunction "CORE_CLKOUT_56") (pintype "passive"))
    )
    (net (code "22") (name "/CORE_CLKOUT_14") (class "Default")
      (node (ref "R65") (pin "2") (pinfunction "2_2") (pintype "passive"))
      (node (ref "U25") (pin "56") (pinfunction "CORE_CLKOUT_56") (pintype "passive"))
    )
    (net (code "23") (name "/CORE_CLKOUT_15") (class "Default")
      (node (ref "R66") (pin "2") (pinfunction "2_2") (pintype "passive"))
      (node (ref "U26") (pin "56") (pinfunction "CORE_CLKOUT_56") (pintype "passive"))
    )
    (net (code "24") (name "/CORE_CLKOUT_16") (class "Default")
      (node (ref "R67") (pin "2") (pinfunction "2_2") (pintype "passive"))
      (node (ref "U27") (pin "56") (pinfunction "CORE_CLKOUT_56") (pintype "passive"))
    )
    (net (code "25") (name "/D+") (class "Default")
      (node (ref "D9") (pin "1") (pinfunction "1_1") (pintype "passive"))
      (node (ref "J2") (pin "3") (pinfunction "3_3") (pintype "passive"))
      (node (ref "U8") (pin "37") (pinfunction "D+/RG2_37") (pintype "passive"))
    )
    (net (code "26") (name "/D-") (class "Default")
      (node (ref "D9") (pin "3") (pinfunction "3_3") (pintype "passive"))
      (node (ref "J2") (pin "2") (pinfunction "2_2") (pintype "passive"))
      (node (ref "U8") (pin "36") (pinfunction "D-/RG3_36") (pintype "passive"))
    )
    (net (code "27") (name "/DRVLogic") (class "Default")
      (node (ref "C4") (pin "1") (pinfunction "1_1") (pintype "passive"))
      (node (ref "C5") (pin "1") (pinfunction "1_1") (pintype "passive"))
      (node (ref "C6") (pin "1") (pinfunction "1_1") (pintype "passive"))
      (node (ref "U1") (pin "6") (pinfunction "VLOGIC_6") (pintype "passive"))
      (node (ref "U2") (pin "6") (pinfunction "VLOGIC_6") (pintype "passive"))
      (node (ref "U3") (pin "6") (pinfunction "VLOGIC_6") (pintype "passive"))
      (node (ref "U8") (pin "55") (pinfunction "C3IN1+/VCMPST3/RP71/RD7_55") (pintype "passive"))
    )
    (net (code "28") (name "/FB") (class "Default")
      (node (ref "C166") (pin "1") (pinfunction "1_1") (pintype "passive"))
      (node (ref "R26") (pin "1") (pinfunction "1_1") (pintype "passive"))
      (node (ref "U8") (pin "17") (pinfunction "PGEC1/AN6/RPI38/RB6_17") (pintype "passive"))
    )
    (net (code "29") (name "/GREEN") (class "Default")
      (node (ref "D5") (pin "2") (pinfunction "A_2") (pintype "passive"))
      (node (ref "U8") (pin "47") (pinfunction "PGED2/SOSCI/C3IN3-/RPI61/RC13_47") (pintype "passive"))
    )
    (net (code "30") (name "/HO1") (class "Default")
      (node (ref "Q2") (pin "4") (pinfunction "G_4") (pintype "passive"))
      (node (ref "U1") (pin "1") (pinfunction "TG_1") (pintype "passive"))
    )
    (net (code "31") (name "/HO2") (class "Default")
      (node (ref "Q3") (pin "4") (pinfunction "G_4") (pintype "passive"))
      (node (ref "U2") (pin "1") (pinfunction "TG_1") (pintype "passive"))
    )
    (net (code "32") (name "/HO3") (class "Default")
      (node (ref "Q1") (pin "4") (pinfunction "G_4") (pintype "passive"))
      (node (ref "U3") (pin "1") (pinfunction "TG_1") (pintype "passive"))
    )
    (net (code "33") (name "/LDO3.3V-5.0V") (class "Default")
      (node (ref "R48") (pin "1") (pinfunction "1_1") (pintype "passive"))
      (node (ref "R49") (pin "1") (pinfunction "1_1") (pintype "passive"))
      (node (ref "U22") (pin "5") (pinfunction "CTL_5") (pintype "passive"))
      (node (ref "U22") (pin "8") (pinfunction "VCC_8") (pintype "passive"))
      (node (ref "U23") (pin "5") (pinfunction "CTL_5") (pintype "passive"))
      (node (ref "U23") (pin "8") (pinfunction "VCC_8") (pintype "passive"))
    )
    (net (code "34") (name "/LDO5.0V") (class "Default")
      (node (ref "C226") (pin "1") (pinfunction "1_1") (pintype "passive"))
      (node (ref "D10") (pin "2") (pinfunction "A_2") (pintype "passive"))
      (node (ref "D8") (pin "1") (pinfunction "C_1") (pintype "passive"))
      (node (ref "R33") (pin "1") (pinfunction "1_1") (pintype "passive"))
      (node (ref "R42") (pin "2") (pinfunction "2_2") (pintype "passive"))
      (node (ref "R49") (pin "2") (pinfunction "2_2") (pintype "passive"))
      (node (ref "U14") (pin "1") (pinfunction "IN_1") (pintype "passive"))
      (node (ref "U14") (pin "3") (pinfunction "EN_3") (pintype "passive"))
      (node (ref "U15") (pin "5") (pinfunction "CTL_5") (pintype "passive"))
      (node (ref "U15") (pin "8") (pinfunction "VCC_8") (pintype "passive"))
    )
    (net (code "35") (name "/LM12V") (class "Default")
      (node (ref "D11") (pin "1") (pinfunction "C_1") (pintype "passive"))
      (node (ref "R47") (pin "1") (pinfunction "1_1") (pintype "passive"))
      (node (ref "U13") (pin "8") (pinfunction "INPUT_8") (pintype "passive"))
      (node (ref "U16") (pin "1") (pinfunction "Vin_1") (pintype "passive"))
      (node (ref "U17") (pin "1") (pinfunction "Vin_1") (pintype "passive"))
    )
    (net (code "36") (name "/LO1") (class "Default")
      (node (ref "Q6") (pin "4") (pinfunction "G_4") (pintype "passive"))
      (node (ref "Q7") (pin "4") (pinfunction "G_4") (pintype "passive"))
      (node (ref "U1") (pin "3") (pinfunction "BG_3") (pintype "passive"))
    )
    (net (code "37") (name "/LO2") (class "Default")
      (node (ref "Q8") (pin "4") (pinfunction "G_4") (pintype "passive"))
      (node (ref "Q9") (pin "4") (pinfunction "G_4") (pintype "passive"))
      (node (ref "U2") (pin "3") (pinfunction "BG_3") (pintype "passive"))
    )
    (net (code "38") (name "/LO3") (class "Default")
      (node (ref "Q4") (pin "4") (pinfunction "G_4") (pintype "passive"))
      (node (ref "Q5") (pin "4") (pinfunction "G_4") (pintype "passive"))
      (node (ref "U3") (pin "3") (pinfunction "BG_3") (pintype "passive"))
    )
    (net (code "39") (name "/LTC_EN") (class "Default")
      (node (ref "R6") (pin "1") (pinfunction "1_1") (pintype "passive"))
      (node (ref "U10") (pin "47") (pinfunction "LTC_EN_47") (pintype "passive"))
      (node (ref "U11") (pin "47") (pinfunction "LTC_EN_47") (pintype "passive"))
      (node (ref "U12") (pin "47") (pinfunction "LTC_EN_47") (pintype "passive"))
      (node (ref "U18") (pin "47") (pinfunction "LTC_EN_47") (pintype "passive"))
      (node (ref "U19") (pin "47") (pinfunction "LTC_EN_47") (pintype "passive"))
      (node (ref "U20") (pin "47") (pinfunction "LTC_EN_47") (pintype "passive"))
      (node (ref "U21") (pin "47") (pinfunction "LTC_EN_47") (pintype "passive"))
      (node (ref "U24") (pin "47") (pinfunction "LTC_EN_47") (pintype "passive"))
      (node (ref "U25") (pin "47") (pinfunction "LTC_EN_47") (pintype "passive"))
      (node (ref "U26") (pin "47") (pinfunction "LTC_EN_47") (pintype "passive"))
      (node (ref "U27") (pin "47") (pinfunction "LTC_EN_47") (pintype "passive"))
      (node (ref "U4") (pin "47") (pinfunction "LTC_EN_47") (pintype "passive"))
      (node (ref "U5") (pin "47") (pinfunction "LTC_EN_47") (pintype "passive"))
      (node (ref "U6") (pin "47") (pinfunction "LTC_EN_47") (pintype "passive"))
      (node (ref "U7") (pin "47") (pinfunction "LTC_EN_47") (pintype "passive"))
      (node (ref "U8") (pin "23") (pinfunction "TMS/AN10/CVREF/PMA13/RPI42/RB10_23") (pintype "passive"))
      (node (ref "U9") (pin "47") (pinfunction "LTC_EN_47") (pintype "passive"))
    )
    (net (code "40") (name "/MCLR") (class "Default")
      (node (ref "C168") (pin "1") (pinfunction "1_1") (pintype "passive"))
      (node (ref "J1") (pin "1") (pinfunction "1_1") (pintype "passive"))
      (node (ref "R31") (pin "1") (pinfunction "1_1") (pintype "passive"))
      (node (ref "U8") (pin "7") (pinfunction "~{MCLR}_7") (pintype "passive"))
    )
    (net (code "41") (name "/MCU5.0V") (class "Default")
      (node (ref "R32") (pin "2") (pinfunction "2_2") (pintype "passive"))
      (node (ref "U8") (pin "34") (pinfunction "VBUS_34") (pintype "passive"))
    )
    (net (code "42") (name "/MEAS12") (class "Default")
      (node (ref "C138") (pin "1") (pinfunction "1_1") (pintype "passive"))
      (node (ref "R23") (pin "2") (pinfunction "2_2") (pintype "passive"))
      (node (ref "R25") (pin "2") (pinfunction "2_2") (pintype "passive"))
      (node (ref "U8") (pin "18") (pinfunction "PGED1/AN7/RCV/RPI39/RB7_18") (pintype "passive"))
    )
    (net (code "43") (name "/Main OSC In") (class "Default")
      (node (ref "C173") (pin "1") (pinfunction "1_1") (pintype "passive"))
      (node (ref "U8") (pin "39") (pinfunction "OSC1/RPI60/RC12_39") (pintype "passive"))
      (node (ref "Y1") (pin "1") (pinfunction "1_1") (pintype "passive"))
    )
    (net (code "44") (name "/Main OSC Out") (class "Default")
      (node (ref "C174") (pin "1") (pinfunction "1_1") (pintype "passive"))
      (node (ref "U8") (pin "40") (pinfunction "OSC2/CLKO/RC15_40") (pintype "passive"))
      (node (ref "Y1") (pin "2") (pinfunction "2_2") (pintype "passive"))
    )
    (net (code "45") (name "/ORANGE") (class "Default")
      (node (ref "D7") (pin "2") (pinfunction "A_2") (pintype "passive"))
      (node (ref "U8") (pin "45") (pinfunction "PMCS1/RPI75/RD11_45") (pintype "passive"))
    )
    (net (code "46") (name "/PGC") (class "Default")
      (node (ref "J1") (pin "5") (pinfunction "5_5") (pintype "passive"))
      (node (ref "U8") (pin "15") (pinfunction "PGEC3/AN1/VREF-/RPI33/RB1_15") (pintype "passive"))
    )
    (net (code "47") (name "/PGD") (class "Default")
      (node (ref "J1") (pin "4") (pinfunction "4_4") (pintype "passive"))
      (node (ref "U8") (pin "16") (pinfunction "PGED3/AN0/VREF+/RPI32/RB0_16") (pintype "passive"))
    )
    (net (code "48") (name "/PLL_SUP") (class "Default")
      (node (ref "C259") (pin "1") (pinfunction "1_1") (pintype "passive"))
      (node (ref "C260") (pin "1") (pinfunction "1_1") (pintype "passive"))
      (node (ref "C274") (pin "1") (pinfunction "1_1") (pintype "passive"))
      (node (ref "FB1") (pin "1") (pinfunction "1_1") (pintype "passive"))
      (node (ref "R50") (pin "1") (pinfunction "1_1") (pintype "passive"))
      (node (ref "R52") (pin "1") (pinfunction "1_1") (pintype "passive"))
      (node (ref "U22") (pin "1") (pinfunction "OUT_1") (pintype "passive"))
      (node (ref "U23") (pin "1") (pinfunction "OUT_1") (pintype "passive"))
    )
    (net (code "49") (name "/PWM2H") (class "Default")
      (node (ref "R22") (pin "1") (pinfunction "1_1") (pintype "passive"))
      (node (ref "U2") (pin "5") (pinfunction "IN_5") (pintype "passive"))
      (node (ref "U8") (pin "63") (pinfunction "AN27/PWM2H/PMD3/RPI83/RE3_63") (pintype "passive"))
    )
    (net (code "50") (name "/PWM2L") (class "Default")
      (node (ref "R24") (pin "1") (pinfunction "1_1") (pintype "passive"))
      (node (ref "U1") (pin "5") (pinfunction "IN_5") (pintype "passive"))
      (node (ref "U8") (pin "62") (pinfunction "AN26/PWM2L/PMD2/RP82/RE2_62") (pintype "passive"))
    )
    (net (code "51") (name "/PWM3L") (class "Default")
      (node (ref "R21") (pin "1") (pinfunction "1_1") (pintype "passive"))
      (node (ref "U3") (pin "5") (pinfunction "IN_5") (pintype "passive"))
      (node (ref "U8") (pin "64") (pinfunction "AN28/PWM3L/PMD4/RP84/RE4_64") (pintype "passive"))
    )
    (net (code "52") (name "/RED") (class "Default")
      (node (ref "D4") (pin "2") (pinfunction "A_2") (pintype "passive"))
      (node (ref "U8") (pin "48") (pinfunction "PGEC2/SOSCO/C3IN1-/T1CK/RPI62/RC14_48") (pintype "passive"))
    )
    (net (code "53") (name "/RX_BTC_0") (class "Default")
      (node (ref "U10") (pin "1") (pinfunction "CFG_P_1") (pintype "passive"))
      (node (ref "U11") (pin "1") (pinfunction "CFG_P_1") (pintype "passive"))
      (node (ref "U12") (pin "1") (pinfunction "CFG_P_1") (pintype "passive"))
      (node (ref "U4") (pin "1") (pinfunction "CFG_P_1") (pintype "passive"))
      (node (ref "U5") (pin "1") (pinfunction "CFG_P_1") (pintype "passive"))
      (node (ref "U6") (pin "1") (pinfunction "CFG_P_1") (pintype "passive"))
      (node (ref "U7") (pin "1") (pinfunction "CFG_P_1") (pintype "passive"))
      (node (ref "U8") (pin "59") (pinfunction "VCMPST2/RP97/RF1_59") (pintype "passive"))
      (node (ref "U9") (pin "1") (pinfunction "CFG_P_1") (pintype "passive"))
    )
    (net (code "54") (name "/RX_BTC_1") (class "Default")
      (node (ref "U18") (pin "1") (pinfunction "CFG_P_1") (pintype "passive"))
      (node (ref "U19") (pin "1") (pinfunction "CFG_P_1") (pintype "passive"))
      (node (ref "U20") (pin "1") (pinfunction "CFG_P_1") (pintype "passive"))
      (node (ref "U21") (pin "1") (pinfunction "CFG_P_1") (pintype "passive"))
      (node (ref "U24") (pin "1") (pinfunction "CFG_P_1") (pintype "passive"))
      (node (ref "U25") (pin "1") (pinfunction "CFG_P_1") (pintype "passive"))
      (node (ref "U26") (pin "1") (pinfunction "CFG_P_1") (pintype "passive"))
      (node (ref "U27") (pin "1") (pinfunction "CFG_P_1") (pintype "passive"))
      (node (ref "U8") (pin "3") (pinfunction "AN31/PWM4H/PMD7/RP87/RE7_3") (pintype "passive"))
    )
    (net (code "55") (name "/RX_LTC_0") (class "Default")
      (node (ref "U10") (pin "2") (pinfunction "CFG_N_2") (pintype "passive"))
      (node (ref "U11") (pin "2") (pinfunction "CFG_N_2") (pintype "passive"))
      (node (ref "U12") (pin "2") (pinfunction "CFG_N_2") (pintype "passive"))
      (node (ref "U4") (pin "2") (pinfunction "CFG_N_2") (pintype "passive"))
      (node (ref "U5") (pin "2") (pinfunction "CFG_N_2") (pintype "passive"))
      (node (ref "U6") (pin "2") (pinfunction "CFG_N_2") (pintype "passive"))
      (node (ref "U7") (pin "2") (pinfunction "CFG_N_2") (pintype "passive"))
      (node (ref "U8") (pin "58") (pinfunction "VCMPST1/RP96/RF0_58") (pintype "passive"))
      (node (ref "U9") (pin "2") (pinfunction "CFG_N_2") (pintype "passive"))
    )
    (net (code "56") (name "/RX_LTC_1") (class "Default")
      (node (ref "U18") (pin "2") (pinfunction "CFG_N_2") (pintype "passive"))
      (node (ref "U19") (pin "2") (pinfunction "CFG_N_2") (pintype "passive"))
      (node (ref "U20") (pin "2") (pinfunction "CFG_N_2") (pintype "passive"))
      (node (ref "U21") (pin "2") (pinfunction "CFG_N_2") (pintype "passive"))
      (node (ref "U24") (pin "2") (pinfunction "CFG_N_2") (pintype "passive"))
      (node (ref "U25") (pin "2") (pinfunction "CFG_N_2") (pintype "passive"))
      (node (ref "U26") (pin "2") (pinfunction "CFG_N_2") (pintype "passive"))
      (node (ref "U27") (pin "2") (pinfunction "CFG_N_2") (pintype "passive"))
      (node (ref "U8") (pin "4") (pinfunction "C1IN3-/SCK2/PMA5/RP118/RG6_4") (pintype "passive"))
    )
    (net (code "57") (name "/SWN1") (class "Default")
      (node (ref "C7") (pin "2") (pinfunction "2_2") (pintype "passive"))
      (node (ref "L1") (pin "1") (pinfunction "1_1") (pintype "passive"))
      (node (ref "Q2") (pin "1") (pinfunction "S_1") (pintype "passive"))
      (node (ref "Q2") (pin "2") (pinfunction "S_2") (pintype "passive"))
      (node (ref "Q2") (pin "3") (pinfunction "S_3") (pintype "passive"))
      (node (ref "Q6") (pin "5") (pinfunction "D_5") (pintype "passive"))
      (node (ref "Q6") (pin "6") (pinfunction "D_6") (pintype "passive"))
      (node (ref "Q6") (pin "7") (pinfunction "D_7") (pintype "passive"))
      (node (ref "Q6") (pin "8") (pinfunction "D_8") (pintype "passive"))
      (node (ref "Q7") (pin "5") (pinfunction "D_5") (pintype "passive"))
      (node (ref "Q7") (pin "6") (pinfunction "D_6") (pintype "passive"))
      (node (ref "Q7") (pin "7") (pinfunction "D_7") (pintype "passive"))
      (node (ref "Q7") (pin "8") (pinfunction "D_8") (pintype "passive"))
      (node (ref "U1") (pin "2") (pinfunction "TS_2") (pintype "passive"))
    )
    (net (code "58") (name "/SWN2") (class "Default")
      (node (ref "C8") (pin "2") (pinfunction "2_2") (pintype "passive"))
      (node (ref "L2") (pin "1") (pinfunction "1_1") (pintype "passive"))
      (node (ref "Q3") (pin "1") (pinfunction "S_1") (pintype "passive"))
      (node (ref "Q3") (pin "2") (pinfunction "S_2") (pintype "passive"))
      (node (ref "Q3") (pin "3") (pinfunction "S_3") (pintype "passive"))
      (node (ref "Q8") (pin "5") (pinfunction "D_5") (pintype "passive"))
      (node (ref "Q8") (pin "6") (pinfunction "D_6") (pintype "passive"))
      (node (ref "Q8") (pin "7") (pinfunction "D_7") (pintype "passive"))
      (node (ref "Q8") (pin "8") (pinfunction "D_8") (pintype "passive"))
      (node (ref "Q9") (pin "5") (pinfunction "D_5") (pintype "passive"))
      (node (ref "Q9") (pin "6") (pinfunction "D_6") (pintype "passive"))
      (node (ref "Q9") (pin "7") (pinfunction "D_7") (pintype "passive"))
      (node (ref "Q9") (pin "8") (pinfunction "D_8") (pintype "passive"))
      (node (ref "U2") (pin "2") (pinfunction "TS_2") (pintype "passive"))
    )
    (net (code "59") (name "/SWN3") (class "Default")
      (node (ref "C9") (pin "2") (pinfunction "2_2") (pintype "passive"))
      (node (ref "L3") (pin "1") (pinfunction "1_1") (pintype "passive"))
      (node (ref "Q1") (pin "1") (pinfunction "S_1") (pintype "passive"))
      (node (ref "Q1") (pin "2") (pinfunction "S_2") (pintype "passive"))
      (node (ref "Q1") (pin "3") (pinfunction "S_3") (pintype "passive"))
      (node (ref "Q4") (pin "5") (pinfunction "D_5") (pintype "passive"))
      (node (ref "Q4") (pin "6") (pinfunction "D_6") (pintype "passive"))
      (node (ref "Q4") (pin "7") (pinfunction "D_7") (pintype "passive"))
      (node (ref "Q4") (pin "8") (pinfunction "D_8") (pintype "passive"))
      (node (ref "Q5") (pin "5") (pinfunction "D_5") (pintype "passive"))
      (node (ref "Q5") (pin "6") (pinfunction "D_6") (pintype "passive"))
      (node (ref "Q5") (pin "7") (pinfunction "D_7") (pintype "passive"))
      (node (ref "Q5") (pin "8") (pinfunction "D_8") (pintype "passive"))
      (node (ref "U3") (pin "2") (pinfunction "TS_2") (pintype "passive"))
    )
    (net (code "60") (name "/TP1011") (class "Default")
      (node (ref "TP5") (pin "1") (pinfunction "1_1") (pintype "passive"))
      (node (ref "U4") (pin "25") (pinfunction "RPT_BUSYN_25") (pintype "passive"))
    )
    (net (code "61") (name "/TP1012") (class "Default")
      (node (ref "TP6") (pin "1") (pinfunction "1_1") (pintype "passive"))
      (node (ref "U5") (pin "25") (pinfunction "RPT_BUSYN_25") (pintype "passive"))
    )
    (net (code "62") (name "/TP1013") (class "Default")
      (node (ref "TP7") (pin "1") (pinfunction "1_1") (pintype "passive"))
      (node (ref "U6") (pin "25") (pinfunction "RPT_BUSYN_25") (pintype "passive"))
    )
    (net (code "63") (name "/TP1014") (class "Default")
      (node (ref "TP8") (pin "1") (pinfunction "1_1") (pintype "passive"))
      (node (ref "U7") (pin "25") (pinfunction "RPT_BUSYN_25") (pintype "passive"))
    )
    (net (code "64") (name "/TP1015") (class "Default")
      (node (ref "TP32") (pin "1") (pinfunction "1_1") (pintype "passive"))
      (node (ref "U9") (pin "25") (pinfunction "RPT_BUSYN_25") (pintype "passive"))
    )
    (net (code "65") (name "/TP1016") (class "Default")
      (node (ref "TP33") (pin "1") (pinfunction "1_1") (pintype "passive"))
      (node (ref "U10") (pin "25") (pinfunction "RPT_BUSYN_25") (pintype "passive"))
    )
    (net (code "66") (name "/TP1017") (class "Default")
      (node (ref "TP34") (pin "1") (pinfunction "1_1") (pintype "passive"))
      (node (ref "U11") (pin "25") (pinfunction "RPT_BUSYN_25") (pintype "passive"))
    )
    (net (code "67") (name "/TP1018") (class "Default")
      (node (ref "TP35") (pin "1") (pinfunction "1_1") (pintype "passive"))
      (node (ref "U12") (pin "25") (pinfunction "RPT_BUSYN_25") (pintype "passive"))
    )
    (net (code "68") (name "/TP1019") (class "Default")
      (node (ref "TP40") (pin "1") (pinfunction "1_1") (pintype "passive"))
      (node (ref "U18") (pin "25") (pinfunction "RPT_BUSYN_25") (pintype "passive"))
    )
    (net (code "69") (name "/TP10110") (class "Default")
      (node (ref "TP41") (pin "1") (pinfunction "1_1") (pintype "passive"))
      (node (ref "U19") (pin "25") (pinfunction "RPT_BUSYN_25") (pintype "passive"))
    )
    (net (code "70") (name "/TP10111") (class "Default")
      (node (ref "TP42") (pin "1") (pinfunction "1_1") (pintype "passive"))
      (node (ref "U20") (pin "25") (pinfunction "RPT_BUSYN_25") (pintype "passive"))
    )
    (net (code "71") (name "/TP10112") (class "Default")
      (node (ref "TP43") (pin "1") (pinfunction "1_1") (pintype "passive"))
      (node (ref "U21") (pin "25") (pinfunction "RPT_BUSYN_25") (pintype "passive"))
    )
    (net (code "72") (name "/TP10113") (class "Default")
      (node (ref "TP49") (pin "1") (pinfunction "1_1") (pintype "passive"))
      (node (ref "U24") (pin "25") (pinfunction "RPT_BUSYN_25") (pintype "passive"))
    )
    (net (code "73") (name "/TP10114") (class "Default")
      (node (ref "TP50") (pin "1") (pinfunction "1_1") (pintype "passive"))
      (node (ref "U25") (pin "25") (pinfunction "RPT_BUSYN_25") (pintype "passive"))
    )
    (net (code "74") (name "/TP10115") (class "Default")
      (node (ref "TP51") (pin "1") (pinfunction "1_1") (pintype "passive"))
      (node (ref "U26") (pin "25") (pinfunction "RPT_BUSYN_25") (pintype "passive"))
    )
    (net (code "75") (name "/TP10116") (class "Default")
      (node (ref "TP52") (pin "1") (pinfunction "1_1") (pintype "passive"))
      (node (ref "U27") (pin "25") (pinfunction "RPT_BUSYN_25") (pintype "passive"))
    )
    (net (code "76") (name "/TP_1001") (class "Default")
      (node (ref "TP1") (pin "1") (pinfunction "1_1") (pintype "passive"))
      (node (ref "U4") (pin "48") (pinfunction "LTC_BUSYN_48") (pintype "passive"))
    )
    (net (code "77") (name "/TP_1002") (class "Default")
      (node (ref "TP2") (pin "1") (pinfunction "1_1") (pintype "passive"))
      (node (ref "U5") (pin "48") (pinfunction "LTC_BUSYN_48") (pintype "passive"))
    )
    (net (code "78") (name "/TP_1003") (class "Default")
      (node (ref "TP3") (pin "1") (pinfunction "1_1") (pintype "passive"))
      (node (ref "U6") (pin "48") (pinfunction "LTC_BUSYN_48") (pintype "passive"))
    )
    (net (code "79") (name "/TP_1004") (class "Default")
      (node (ref "TP4") (pin "1") (pinfunction "1_1") (pintype "passive"))
      (node (ref "U7") (pin "48") (pinfunction "LTC_BUSYN_48") (pintype "passive"))
    )
    (net (code "80") (name "/TP_1005") (class "Default")
      (node (ref "TP13") (pin "1") (pinfunction "1_1") (pintype "passive"))
      (node (ref "U9") (pin "48") (pinfunction "LTC_BUSYN_48") (pintype "passive"))
    )
    (net (code "81") (name "/TP_1006") (class "Default")
      (node (ref "TP14") (pin "1") (pinfunction "1_1") (pintype "passive"))
      (node (ref "U10") (pin "48") (pinfunction "LTC_BUSYN_48") (pintype "passive"))
    )
    (net (code "82") (name "/TP_1007") (class "Default")
      (node (ref "TP15") (pin "1") (pinfunction "1_1") (pintype "passive"))
      (node (ref "U11") (pin "48") (pinfunction "LTC_BUSYN_48") (pintype "passive"))
    )
    (net (code "83") (name "/TP_1008") (class "Default")
      (node (ref "TP16") (pin "1") (pinfunction "1_1") (pintype "passive"))
      (node (ref "U12") (pin "48") (pinfunction "LTC_BUSYN_48") (pintype "passive"))
    )
    (net (code "84") (name "/TP_1009") (class "Default")
      (node (ref "TP36") (pin "1") (pinfunction "1_1") (pintype "passive"))
      (node (ref "U18") (pin "48") (pinfunction "LTC_BUSYN_48") (pintype "passive"))
    )
    (net (code "85") (name "/TP_10010") (class "Default")
      (node (ref "TP37") (pin "1") (pinfunction "1_1") (pintype "passive"))
      (node (ref "U19") (pin "48") (pinfunction "LTC_BUSYN_48") (pintype "passive"))
    )
    (net (code "86") (name "/TP_10011") (class "Default")
      (node (ref "TP38") (pin "1") (pinfunction "1_1") (pintype "passive"))
      (node (ref "U20") (pin "48") (pinfunction "LTC_BUSYN_48") (pintype "passive"))
    )
    (net (code "87") (name "/TP_10012") (class "Default")
      (node (ref "TP39") (pin "1") (pinfunction "1_1") (pintype "passive"))
      (node (ref "U21") (pin "48") (pinfunction "LTC_BUSYN_48") (pintype "passive"))
    )
    (net (code "88") (name "/TP_10013") (class "Default")
      (node (ref "TP44") (pin "1") (pinfunction "1_1") (pintype "passive"))
      (node (ref "U24") (pin "48") (pinfunction "LTC_BUSYN_48") (pintype "passive"))
    )
    (net (code "89") (name "/TP_10014") (class "Default")
      (node (ref "TP45") (pin "1") (pinfunction "1_1") (pintype "passive"))
      (node (ref "U25") (pin "48") (pinfunction "LTC_BUSYN_48") (pintype "passive"))
    )
    (net (code "90") (name "/TP_10015") (class "Default")
      (node (ref "TP46") (pin "1") (pinfunction "1_1") (pintype "passive"))
      (node (ref "U26") (pin "48") (pinfunction "LTC_BUSYN_48") (pintype "passive"))
    )
    (net (code "91") (name "/TP_10016") (class "Default")
      (node (ref "TP47") (pin "1") (pinfunction "1_1") (pintype "passive"))
      (node (ref "U27") (pin "48") (pinfunction "LTC_BUSYN_48") (pintype "passive"))
    )
    (net (code "92") (name "/TX_BTC_0") (class "Default")
      (node (ref "R7") (pin "1") (pinfunction "1_1") (pintype "passive"))
      (node (ref "U10") (pin "24") (pinfunction "RPT_P_24") (pintype "passive"))
      (node (ref "U11") (pin "24") (pinfunction "RPT_P_24") (pintype "passive"))
      (node (ref "U12") (pin "24") (pinfunction "RPT_P_24") (pintype "passive"))
      (node (ref "U4") (pin "24") (pinfunction "RPT_P_24") (pintype "passive"))
      (node (ref "U5") (pin "24") (pinfunction "RPT_P_24") (pintype "passive"))
      (node (ref "U6") (pin "24") (pinfunction "RPT_P_24") (pintype "passive"))
      (node (ref "U7") (pin "24") (pinfunction "RPT_P_24") (pintype "passive"))
      (node (ref "U8") (pin "61") (pinfunction "AN25/PWM1H/PMD1/RPI81/RE1_61") (pintype "passive"))
      (node (ref "U9") (pin "24") (pinfunction "RPT_P_24") (pintype "passive"))
    )
    (net (code "93") (name "/TX_BTC_1") (class "Default")
      (node (ref "R53") (pin "1") (pinfunction "1_1") (pintype "passive"))
      (node (ref "U18") (pin "24") (pinfunction "RPT_P_24") (pintype "passive"))
      (node (ref "U19") (pin "24") (pinfunction "RPT_P_24") (pintype "passive"))
      (node (ref "U20") (pin "24") (pinfunction "RPT_P_24") (pintype "passive"))
      (node (ref "U21") (pin "24") (pinfunction "RPT_P_24") (pintype "passive"))
      (node (ref "U24") (pin "24") (pinfunction "RPT_P_24") (pintype "passive"))
      (node (ref "U25") (pin "24") (pinfunction "RPT_P_24") (pintype "passive"))
      (node (ref "U26") (pin "24") (pinfunction "RPT_P_24") (pintype "passive"))
      (node (ref "U27") (pin "24") (pinfunction "RPT_P_24") (pintype "passive"))
      (node (ref "U8") (pin "1") (pinfunction "AN29/PWM3H/PMD5/RP85/RE5_1") (pintype "passive"))
    )
    (net (code "94") (name "/TX_LTC_0") (class "Default")
      (node (ref "R8") (pin "2") (pinfunction "2_2") (pintype "passive"))
      (node (ref "U10") (pin "23") (pinfunction "RPT_N_23") (pintype "passive"))
      (node (ref "U11") (pin "23") (pinfunction "RPT_N_23") (pintype "passive"))
      (node (ref "U12") (pin "23") (pinfunction "RPT_N_23") (pintype "passive"))
      (node (ref "U4") (pin "23") (pinfunction "RPT_N_23") (pintype "passive"))
      (node (ref "U5") (pin "23") (pinfunction "RPT_N_23") (pintype "passive"))
      (node (ref "U6") (pin "23") (pinfunction "RPT_N_23") (pintype "passive"))
      (node (ref "U7") (pin "23") (pinfunction "RPT_N_23") (pintype "passive"))
      (node (ref "U8") (pin "60") (pinfunction "AN24/PWM1L/PMD0/RP80/RE0_60") (pintype "passive"))
      (node (ref "U9") (pin "23") (pinfunction "RPT_N_23") (pintype "passive"))
    )
    (net (code "95") (name "/TX_LTC_1") (class "Default")
      (node (ref "R54") (pin "2") (pinfunction "2_2") (pintype "passive"))
      (node (ref "U18") (pin "23") (pinfunction "RPT_N_23") (pintype "passive"))
      (node (ref "U19") (pin "23") (pinfunction "RPT_N_23") (pintype "passive"))
      (node (ref "U20") (pin "23") (pinfunction "RPT_N_23") (pintype "passive"))
      (node (ref "U21") (pin "23") (pinfunction "RPT_N_23") (pintype "passive"))
      (node (ref "U24") (pin "23") (pinfunction "RPT_N_23") (pintype "passive"))
      (node (ref "U25") (pin "23") (pinfunction "RPT_N_23") (pintype "passive"))
      (node (ref "U26") (pin "23") (pinfunction "RPT_N_23") (pintype "passive"))
      (node (ref "U27") (pin "23") (pinfunction "RPT_N_23") (pintype "passive"))
      (node (ref "U8") (pin "2") (pinfunction "AN30/PWM4L/PMD6/RPI86/RE6_2") (pintype "passive"))
    )
    (net (code "96") (name "/USB5.0V") (class "Default")
      (node (ref "D9") (pin "4") (pinfunction "4_4") (pintype "passive"))
      (node (ref "D9") (pin "6") (pinfunction "6_6") (pintype "passive"))
      (node (ref "J2") (pin "1") (pinfunction "1_1") (pintype "passive"))
      (node (ref "R32") (pin "1") (pinfunction "1_1") (pintype "passive"))
      (node (ref "R33") (pin "2") (pinfunction "2_2") (pintype "passive"))
    )
    (net (code "97") (name "/VCAP") (class "Default")
      (node (ref "C139") (pin "1") (pinfunction "1_1") (pintype "passive"))
      (node (ref "U8") (pin "56") (pinfunction "VCAP_56") (pintype "passive"))
    )
    (net (code "98") (name "/VDD_PLL") (class "Default")
      (node (ref "C261") (pin "1") (pinfunction "1_1") (pintype "passive"))
      (node (ref "FB1") (pin "2") (pinfunction "2_2") (pintype "passive"))
      (node (ref "U10") (pin "8") (pinfunction "VDDA_PLL_8") (pintype "passive"))
      (node (ref "U10") (pin "9") (pinfunction "VDD_PLL_9") (pintype "passive"))
      (node (ref "U11") (pin "8") (pinfunction "VDDA_PLL_8") (pintype "passive"))
      (node (ref "U11") (pin "9") (pinfunction "VDD_PLL_9") (pintype "passive"))
      (node (ref "U12") (pin "8") (pinfunction "VDDA_PLL_8") (pintype "passive"))
      (node (ref "U12") (pin "9") (pinfunction "VDD_PLL_9") (pintype "passive"))
      (node (ref "U18") (pin "8") (pinfunction "VDDA_PLL_8") (pintype "passive"))
      (node (ref "U18") (pin "9") (pinfunction "VDD_PLL_9") (pintype "passive"))
      (node (ref "U19") (pin "8") (pinfunction "VDDA_PLL_8") (pintype "passive"))
      (node (ref "U19") (pin "9") (pinfunction "VDD_PLL_9") (pintype "passive"))
      (node (ref "U20") (pin "8") (pinfunction "VDDA_PLL_8") (pintype "passive"))
      (node (ref "U20") (pin "9") (pinfunction "VDD_PLL_9") (pintype "passive"))
      (node (ref "U21") (pin "8") (pinfunction "VDDA_PLL_8") (pintype "passive"))
      (node (ref "U21") (pin "9") (pinfunction "VDD_PLL_9") (pintype "passive"))
      (node (ref "U24") (pin "8") (pinfunction "VDDA_PLL_8") (pintype "passive"))
      (node (ref "U24") (pin "9") (pinfunction "VDD_PLL_9") (pintype "passive"))
      (node (ref "U25") (pin "8") (pinfunction "VDDA_PLL_8") (pintype "passive"))
      (node (ref "U25") (pin "9") (pinfunction "VDD_PLL_9") (pintype "passive"))
      (node (ref "U26") (pin "8") (pinfunction "VDDA_PLL_8") (pintype "passive"))
      (node (ref "U26") (pin "9") (pinfunction "VDD_PLL_9") (pintype "passive"))
      (node (ref "U27") (pin "8") (pinfunction "VDDA_PLL_8") (pintype "passive"))
      (node (ref "U27") (pin "9") (pinfunction "VDD_PLL_9") (pintype "passive"))
      (node (ref "U4") (pin "8") (pinfunction "VDDA_PLL_8") (pintype "passive"))
      (node (ref "U4") (pin "9") (pinfunction "VDD_PLL_9") (pintype "passive"))
      (node (ref "U5") (pin "8") (pinfunction "VDDA_PLL_8") (pintype "passive"))
      (node (ref "U5") (pin "9") (pinfunction "VDD_PLL_9") (pintype "passive"))
      (node (ref "U6") (pin "8") (pinfunction "VDDA_PLL_8") (pintype "passive"))
      (node (ref "U6") (pin "9") (pinfunction "VDD_PLL_9") (pintype "passive"))
      (node (ref "U7") (pin "8") (pinfunction "VDDA_PLL_8") (pintype "passive"))
      (node (ref "U7") (pin "9") (pinfunction "VDD_PLL_9") (pintype "passive"))
      (node (ref "U9") (pin "8") (pinfunction "VDDA_PLL_8") (pintype "passive"))
      (node (ref "U9") (pin "9") (pinfunction "VDD_PLL_9") (pintype "passive"))
    )
    (net (code "99") (name "/XCLK1") (class "Default")
      (node (ref "R27") (pin "2") (pinfunction "2_2") (pintype "passive"))
      (node (ref "U8") (pin "46") (pinfunction "INT0/DMH/RP64/RD0_46") (pintype "passive"))
      (node (ref "U8") (pin "49") (pinfunction "VCPCON/RP65/RD1_49") (pintype "passive"))
      (node (ref "U8") (pin "52") (pinfunction "PMWR/RP68/RD4_52") (pintype "passive"))
      (node (ref "U8") (pin "53") (pinfunction "PMRD/RP69/RD5_53") (pintype "passive"))
    )
    (net (code "100") (name "/XCLKIN") (class "Default")
      (node (ref "R27") (pin "1") (pinfunction "1_1") (pintype "passive"))
      (node (ref "R30") (pin "1") (pinfunction "1_1") (pintype "passive"))
      (node (ref "U4") (pin "11") (pinfunction "XCLKIN_11") (pintype "passive"))
    )
    (net (code "101") (name "/XCLKOUT_1") (class "Default")
      (node (ref "U4") (pin "12") (pinfunction "XCLKOUT_12") (pintype "passive"))
      (node (ref "U5") (pin "11") (pinfunction "XCLKIN_11") (pintype "passive"))
    )
    (net (code "102") (name "/XCLKOUT_2") (class "Default")
      (node (ref "U5") (pin "12") (pinfunction "XCLKOUT_12") (pintype "passive"))
      (node (ref "U6") (pin "11") (pinfunction "XCLKIN_11") (pintype "passive"))
    )
    (net (code "103") (name "/XCLKOUT_3") (class "Default")
      (node (ref "U6") (pin "12") (pinfunction "XCLKOUT_12") (pintype "passive"))
      (node (ref "U7") (pin "11") (pinfunction "XCLKIN_11") (pintype "passive"))
    )
    (net (code "104") (name "/XCLKOUT_4") (class "Default")
      (node (ref "U7") (pin "12") (pinfunction "XCLKOUT_12") (pintype "passive"))
      (node (ref "U9") (pin "11") (pinfunction "XCLKIN_11") (pintype "passive"))
    )
    (net (code "105") (name "/XCLKOUT_5") (class "Default")
      (node (ref "U10") (pin "11") (pinfunction "XCLKIN_11") (pintype "passive"))
      (node (ref "U9") (pin "12") (pinfunction "XCLKOUT_12") (pintype "passive"))
    )
    (net (code "106") (name "/XCLKOUT_6") (class "Default")
      (node (ref "U10") (pin "12") (pinfunction "XCLKOUT_12") (pintype "passive"))
      (node (ref "U11") (pin "11") (pinfunction "XCLKIN_11") (pintype "passive"))
    )
    (net (code "107") (name "/XCLKOUT_7") (class "Default")
      (node (ref "U11") (pin "12") (pinfunction "XCLKOUT_12") (pintype "passive"))
      (node (ref "U12") (pin "11") (pinfunction "XCLKIN_11") (pintype "passive"))
    )
    (net (code "108") (name "/XCLKOUT_8") (class "Default")
      (node (ref "U12") (pin "12") (pinfunction "XCLKOUT_12") (pintype "passive"))
      (node (ref "U18") (pin "11") (pinfunction "XCLKIN_11") (pintype "passive"))
    )
    (net (code "109") (name "/XCLKOUT_9") (class "Default")
      (node (ref "U18") (pin "12") (pinfunction "XCLKOUT_12") (pintype "passive"))
      (node (ref "U19") (pin "11") (pinfunction "XCLKIN_11") (pintype "passive"))
    )
    (net (code "110") (name "/XCLKOUT_10") (class "Default")
      (node (ref "U19") (pin "12") (pinfunction "XCLKOUT_12") (pintype "passive"))
      (node (ref "U20") (pin "11") (pinfunction "XCLKIN_11") (pintype "passive"))
    )
    (net (code "111") (name "/XCLKOUT_11") (class "Default")
      (node (ref "U20") (pin "12") (pinfunction "XCLKOUT_12") (pintype "passive"))
      (node (ref "U21") (pin "11") (pinfunction "XCLKIN_11") (pintype "passive"))
    )
    (net (code "112") (name "/XCLKOUT_12") (class "Default")
      (node (ref "U21") (pin "12") (pinfunction "XCLKOUT_12") (pintype "passive"))
      (node (ref "U24") (pin "11") (pinfunction "XCLKIN_11") (pintype "passive"))
    )
    (net (code "113") (name "/XCLKOUT_13") (class "Default")
      (node (ref "U24") (pin "12") (pinfunction "XCLKOUT_12") (pintype "passive"))
      (node (ref "U25") (pin "11") (pinfunction "XCLKIN_11") (pintype "passive"))
    )
    (net (code "114") (name "/XCLKOUT_14") (class "Default")
      (node (ref "U25") (pin "12") (pinfunction "XCLKOUT_12") (pintype "passive"))
      (node (ref "U26") (pin "11") (pinfunction "XCLKIN_11") (pintype "passive"))
    )
    (net (code "115") (name "/XCLKOUT_15") (class "Default")
      (node (ref "U26") (pin "12") (pinfunction "XCLKOUT_12") (pintype "passive"))
      (node (ref "U27") (pin "11") (pinfunction "XCLKIN_11") (pintype "passive"))
    )
    (net (code "116") (name "/XCLKOUT_16") (class "Default")
      (node (ref "TP48") (pin "1") (pinfunction "1_1") (pintype "passive"))
      (node (ref "U27") (pin "12") (pinfunction "XCLKOUT_12") (pintype "passive"))
    )
    (net (code "117") (name "/YELLOW") (class "Default")
      (node (ref "D6") (pin "2") (pinfunction "A_2") (pintype "passive"))
      (node (ref "U8") (pin "44") (pinfunction "ASCL1/PMCS2/RPI74/RD10_44") (pintype "passive"))
    )
    (net (code "118") (name "GND") (class "Default")
      (node (ref "C1") (pin "1") (pinfunction "1_1") (pintype "passive"))
      (node (ref "C10") (pin "1") (pinfunction "1_1") (pintype "passive"))
      (node (ref "C11") (pin "1") (pinfunction "1_1") (pintype "passive"))
      (node (ref "C118") (pin "1") (pinfunction "1_1") (pintype "passive"))
      (node (ref "C119") (pin "1") (pinfunction "1_1") (pintype "passive"))
      (node (ref "C12") (pin "1") (pinfunction "1_1") (pintype "passive"))
      (node (ref "C120") (pin "1") (pinfunction "1_1") (pintype "passive"))
      (node (ref "C121") (pin "1") (pinfunction "1_1") (pintype "passive"))
      (node (ref "C122") (pin "1") (pinfunction "1_1") (pintype "passive"))
      (node (ref "C123") (pin "1") (pinfunction "1_1") (pintype "passive"))
      (node (ref "C124") (pin "1") (pinfunction "1_1") (pintype "passive"))
      (node (ref "C125") (pin "1") (pinfunction "1_1") (pintype "passive"))
      (node (ref "C126") (pin "1") (pinfunction "1_1") (pintype "passive"))
      (node (ref "C127") (pin "1") (pinfunction "1_1") (pintype "passive"))
      (node (ref "C128") (pin "1") (pinfunction "1_1") (pintype "passive"))
      (node (ref "C129") (pin "1") (pinfunction "1_1") (pintype "passive"))
      (node (ref "C13") (pin "1") (pinfunction "1_1") (pintype "passive"))
      (node (ref "C130") (pin "1") (pinfunction "1_1") (pintype "passive"))
      (node (ref "C131") (pin "1") (pinfunction "1_1") (pintype "passive"))
      (node (ref "C132") (pin "1") (pinfunction "1_1") (pintype "passive"))
      (node (ref "C133") (pin "1") (pinfunction "1_1") (pintype "passive"))
      (node (ref "C134") (pin "1") (pinfunction "1_1") (pintype "passive"))
      (node (ref "C135") (pin "1") (pinfunction "1_1") (pintype "passive"))
      (node (ref "C136") (pin "1") (pinfunction "1_1") (pintype "passive"))
      (node (ref "C137") (pin "1") (pinfunction "1_1") (pintype "passive"))
      (node (ref "C138") (pin "2") (pinfunction "2_2") (pintype "passive"))
      (node (ref "C139") (pin "2") (pinfunction "2_2") (pintype "passive"))
      (node (ref "C14") (pin "1") (pinfunction "1_1") (pintype "passive"))
      (node (ref "C140") (pin "1") (pinfunction "1_1") (pintype "passive"))
      (node (ref "C141") (pin "1") (pinfunction "1_1") (pintype "passive"))
      (node (ref "C142") (pin "1") (pinfunction "1_1") (pintype "passive"))
      (node (ref "C143") (pin "1") (pinfunction "1_1") (pintype "passive"))
      (node (ref "C144") (pin "1") (pinfunction "1_1") (pintype "passive"))
      (node (ref "C145") (pin "1") (pinfunction "1_1") (pintype "passive"))
      (node (ref "C146") (pin "1") (pinfunction "1_1") (pintype "passive"))
      (node (ref "C147") (pin "1") (pinfunction "1_1") (pintype "passive"))
      (node (ref "C148") (pin "1") (pinfunction "1_1") (pintype "passive"))
      (node (ref "C149") (pin "1") (pinfunction "1_1") (pintype "passive"))
      (node (ref "C15") (pin "1") (pinfunction "1_1") (pintype "passive"))
      (node (ref "C150") (pin "1") (pinfunction "1_1") (pintype "passive"))
      (node (ref "C151") (pin "1") (pinfunction "1_1") (pintype "passive"))
      (node (ref "C152") (pin "1") (pinfunction "1_1") (pintype "passive"))
      (node (ref "C153") (pin "1") (pinfunction "1_1") (pintype "passive"))
      (node (ref "C154") (pin "1") (pinfunction "1_1") (pintype "passive"))
      (node (ref "C155") (pin "1") (pinfunction "1_1") (pintype "passive"))
      (node (ref "C156") (pin "1") (pinfunction "1_1") (pintype "passive"))
      (node (ref "C157") (pin "1") (pinfunction "1_1") (pintype "passive"))
      (node (ref "C158") (pin "1") (pinfunction "1_1") (pintype "passive"))
      (node (ref "C159") (pin "1") (pinfunction "1_1") (pintype "passive"))
      (node (ref "C16") (pin "1") (pinfunction "1_1") (pintype "passive"))
      (node (ref "C160") (pin "1") (pinfunction "1_1") (pintype "passive"))
      (node (ref "C161") (pin "1") (pinfunction "1_1") (pintype "passive"))
      (node (ref "C162") (pin "1") (pinfunction "1_1") (pintype "passive"))
      (node (ref "C163") (pin "1") (pinfunction "1_1") (pintype "passive"))
      (node (ref "C166") (pin "2") (pinfunction "2_2") (pintype "passive"))
      (node (ref "C167") (pin "2") (pinfunction "2_2") (pintype "passive"))
      (node (ref "C168") (pin "2") (pinfunction "2_2") (pintype "passive"))
      (node (ref "C169") (pin "2") (pinfunction "2_2") (pintype "passive"))
      (node (ref "C17") (pin "1") (pinfunction "1_1") (pintype "passive"))
      (node (ref "C170") (pin "2") (pinfunction "2_2") (pintype "passive"))
      (node (ref "C171") (pin "2") (pinfunction "2_2") (pintype "passive"))
      (node (ref "C172") (pin "2") (pinfunction "2_2") (pintype "passive"))
      (node (ref "C173") (pin "2") (pinfunction "2_2") (pintype "passive"))
      (node (ref "C174") (pin "2") (pinfunction "2_2") (pintype "passive"))
      (node (ref "C175") (pin "1") (pinfunction "1_1") (pintype "passive"))
      (node (ref "C176") (pin "1") (pinfunction "1_1") (pintype "passive"))
      (node (ref "C177") (pin "1") (pinfunction "1_1") (pintype "passive"))
      (node (ref "C178") (pin "1") (pinfunction "1_1") (pintype "passive"))
      (node (ref "C179") (pin "1") (pinfunction "1_1") (pintype "passive"))
      (node (ref "C18") (pin "1") (pinfunction "1_1") (pintype "passive"))
      (node (ref "C180") (pin "1") (pinfunction "1_1") (pintype "passive"))
      (node (ref "C181") (pin "1") (pinfunction "1_1") (pintype "passive"))
      (node (ref "C182") (pin "1") (pinfunction "1_1") (pintype "passive"))
      (node (ref "C183") (pin "1") (pinfunction "1_1") (pintype "passive"))
      (node (ref "C184") (pin "1") (pinfunction "1_1") (pintype "passive"))
      (node (ref "C185") (pin "1") (pinfunction "1_1") (pintype "passive"))
      (node (ref "C186") (pin "1") (pinfunction "1_1") (pintype "passive"))
      (node (ref "C187") (pin "1") (pinfunction "1_1") (pintype "passive"))
      (node (ref "C188") (pin "1") (pinfunction "1_1") (pintype "passive"))
      (node (ref "C189") (pin "1") (pinfunction "1_1") (pintype "passive"))
      (node (ref "C19") (pin "1") (pinfunction "1_1") (pintype "passive"))
      (node (ref "C190") (pin "1") (pinfunction "1_1") (pintype "passive"))
      (node (ref "C191") (pin "2") (pinfunction "2_2") (pintype "passive"))
      (node (ref "C2") (pin "1") (pinfunction "1_1") (pintype "passive"))
      (node (ref "C20") (pin "2") (pinfunction "2_2") (pintype "passive"))
      (node (ref "C21") (pin "2") (pinfunction "2_2") (pintype "passive"))
      (node (ref "C22") (pin "1") (pinfunction "1_1") (pintype "passive"))
      (node (ref "C224") (pin "1") (pinfunction "1_1") (pintype "passive"))
      (node (ref "C225") (pin "2") (pinfunction "2_2") (pintype "passive"))
      (node (ref "C226") (pin "2") (pinfunction "2_2") (pintype "passive"))
      (node (ref "C227") (pin "1") (pinfunction "1_1") (pintype "passive"))
      (node (ref "C228") (pin "1") (pinfunction "1_1") (pintype "passive"))
      (node (ref "C229") (pin "1") (pinfunction "1_1") (pintype "passive"))
      (node (ref "C23") (pin "1") (pinfunction "1_1") (pintype "passive"))
      (node (ref "C230") (pin "1") (pinfunction "1_1") (pintype "passive"))
      (node (ref "C231") (pin "1") (pinfunction "1_1") (pintype "passive"))
      (node (ref "C232") (pin "1") (pinfunction "1_1") (pintype "passive"))
      (node (ref "C233") (pin "1") (pinfunction "1_1") (pintype "passive"))
      (node (ref "C234") (pin "1") (pinfunction "1_1") (pintype "passive"))
      (node (ref "C235") (pin "1") (pinfunction "1_1") (pintype "passive"))
      (node (ref "C236") (pin "1") (pinfunction "1_1") (pintype "passive"))
      (node (ref "C237") (pin "1") (pinfunction "1_1") (pintype "passive"))
      (node (ref "C238") (pin "1") (pinfunction "1_1") (pintype "passive"))
      (node (ref "C239") (pin "1") (pinfunction "1_1") (pintype "passive"))
      (node (ref "C24") (pin "1") (pinfunction "1_1") (pintype "passive"))
      (node (ref "C240") (pin "1") (pinfunction "1_1") (pintype "passive"))
      (node (ref "C241") (pin "1") (pinfunction "1_1") (pintype "passive"))
      (node (ref "C242") (pin "1") (pinfunction "1_1") (pintype "passive"))
      (node (ref "C243") (pin "1") (pinfunction "1_1") (pintype "passive"))
      (node (ref "C244") (pin "1") (pinfunction "1_1") (pintype "passive"))
      (node (ref "C245") (pin "1") (pinfunction "1_1") (pintype "passive"))
      (node (ref "C246") (pin "1") (pinfunction "1_1") (pintype "passive"))
      (node (ref "C247") (pin "1") (pinfunction "1_1") (pintype "passive"))
      (node (ref "C248") (pin "1") (pinfunction "1_1") (pintype "passive"))
      (node (ref "C249") (pin "1") (pinfunction "1_1") (pintype "passive"))
      (node (ref "C25") (pin "1") (pinfunction "1_1") (pintype "passive"))
      (node (ref "C250") (pin "1") (pinfunction "1_1") (pintype "passive"))
      (node (ref "C251") (pin "1") (pinfunction "1_1") (pintype "passive"))
      (node (ref "C252") (pin "1") (pinfunction "1_1") (pintype "passive"))
      (node (ref "C253") (pin "1") (pinfunction "1_1") (pintype "passive"))
      (node (ref "C254") (pin "1") (pinfunction "1_1") (pintype "passive"))
      (node (ref "C255") (pin "1") (pinfunction "1_1") (pintype "passive"))
      (node (ref "C256") (pin "1") (pinfunction "1_1") (pintype "passive"))
      (node (ref "C257") (pin "1") (pinfunction "1_1") (pintype "passive"))
      (node (ref "C258") (pin "1") (pinfunction "1_1") (pintype "passive"))
      (node (ref "C259") (pin "2") (pinfunction "2_2") (pintype "passive"))
      (node (ref "C26") (pin "1") (pinfunction "1_1") (pintype "passive"))
      (node (ref "C260") (pin "2") (pinfunction "2_2") (pintype "passive"))
      (node (ref "C261") (pin "2") (pinfunction "2_2") (pintype "passive"))
      (node (ref "C262") (pin "1") (pinfunction "1_1") (pintype "passive"))
      (node (ref "C263") (pin "1") (pinfunction "1_1") (pintype "passive"))
      (node (ref "C264") (pin "1") (pinfunction "1_1") (pintype "passive"))
      (node (ref "C265") (pin "1") (pinfunction "1_1") (pintype "passive"))
      (node (ref "C266") (pin "1") (pinfunction "1_1") (pintype "passive"))
      (node (ref "C267") (pin "1") (pinfunction "1_1") (pintype "passive"))
      (node (ref "C268") (pin "1") (pinfunction "1_1") (pintype "passive"))
      (node (ref "C269") (pin "1") (pinfunction "1_1") (pintype "passive"))
      (node (ref "C27") (pin "1") (pinfunction "1_1") (pintype "passive"))
      (node (ref "C270") (pin "1") (pinfunction "1_1") (pintype "passive"))
      (node (ref "C271") (pin "1") (pinfunction "1_1") (pintype "passive"))
      (node (ref "C272") (pin "1") (pinfunction "1_1") (pintype "passive"))
      (node (ref "C273") (pin "1") (pinfunction "1_1") (pintype "passive"))
      (node (ref "C274") (pin "2") (pinfunction "2_2") (pintype "passive"))
      (node (ref "C275") (pin "2") (pinfunction "2_2") (pintype "passive"))
      (node (ref "C276") (pin "1") (pinfunction "1_1") (pintype "passive"))
      (node (ref "C277") (pin "1") (pinfunction "1_1") (pintype "passive"))
      (node (ref "C278") (pin "1") (pinfunction "1_1") (pintype "passive"))
      (node (ref "C279") (pin "1") (pinfunction "1_1") (pintype "passive"))
      (node (ref "C28") (pin "1") (pinfunction "1_1") (pintype "passive"))
      (node (ref "C280") (pin "1") (pinfunction "1_1") (pintype "passive"))
      (node (ref "C281") (pin "1") (pinfunction "1_1") (pintype "passive"))
      (node (ref "C282") (pin "1") (pinfunction "1_1") (pintype "passive"))
      (node (ref "C283") (pin "1") (pinfunction "1_1") (pintype "passive"))
      (node (ref "C284") (pin "1") (pinfunction "1_1") (pintype "passive"))
      (node (ref "C285") (pin "1") (pinfunction "1_1") (pintype "passive"))
      (node (ref "C286") (pin "1") (pinfunction "1_1") (pintype "passive"))
      (node (ref "C287") (pin "1") (pinfunction "1_1") (pintype "passive"))
      (node (ref "C288") (pin "1") (pinfunction "1_1") (pintype "passive"))
      (node (ref "C289") (pin "1") (pinfunction "1_1") (pintype "passive"))
      (node (ref "C29") (pin "1") (pinfunction "1_1") (pintype "passive"))
      (node (ref "C290") (pin "1") (pinfunction "1_1") (pintype "passive"))
      (node (ref "C291") (pin "1") (pinfunction "1_1") (pintype "passive"))
      (node (ref "C3") (pin "1") (pinfunction "1_1") (pintype "passive"))
      (node (ref "C30") (pin "1") (pinfunction "1_1") (pintype "passive"))
      (node (ref "C31") (pin "1") (pinfunction "1_1") (pintype "passive"))
      (node (ref "C32") (pin "1") (pinfunction "1_1") (pintype "passive"))
      (node (ref "C324") (pin "1") (pinfunction "1_1") (pintype "passive"))
      (node (ref "C325") (pin "1") (pinfunction "1_1") (pintype "passive"))
      (node (ref "C326") (pin "1") (pinfunction "1_1") (pintype "passive"))
      (node (ref "C327") (pin "1") (pinfunction "1_1") (pintype "passive"))
      (node (ref "C328") (pin "1") (pinfunction "1_1") (pintype "passive"))
      (node (ref "C329") (pin "1") (pinfunction "1_1") (pintype "passive"))
      (node (ref "C33") (pin "1") (pinfunction "1_1") (pintype "passive"))
      (node (ref "C330") (pin "1") (pinfunction "1_1") (pintype "passive"))
      (node (ref "C331") (pin "1") (pinfunction "1_1") (pintype "passive"))
      (node (ref "C332") (pin "1") (pinfunction "1_1") (pintype "passive"))
      (node (ref "C333") (pin "1") (pinfunction "1_1") (pintype "passive"))
      (node (ref "C334") (pin "1") (pinfunction "1_1") (pintype "passive"))
      (node (ref "C335") (pin "1") (pinfunction "1_1") (pintype "passive"))
      (node (ref "C336") (pin "1") (pinfunction "1_1") (pintype "passive"))
      (node (ref "C337") (pin "1") (pinfunction "1_1") (pintype "passive"))
      (node (ref "C338") (pin "1") (pinfunction "1_1") (pintype "passive"))
      (node (ref "C339") (pin "1") (pinfunction "1_1") (pintype "passive"))
      (node (ref "C34") (pin "1") (pinfunction "1_1") (pintype "passive"))
      (node (ref "C340") (pin "1") (pinfunction "1_1") (pintype "passive"))
      (node (ref "C341") (pin "1") (pinfunction "1_1") (pintype "passive"))
      (node (ref "C342") (pin "1") (pinfunction "1_1") (pintype "passive"))
      (node (ref "C343") (pin "1") (pinfunction "1_1") (pintype "passive"))
      (node (ref "C344") (pin "1") (pinfunction "1_1") (pintype "passive"))
      (node (ref "C345") (pin "1") (pinfunction "1_1") (pintype "passive"))
      (node (ref "C346") (pin "1") (pinfunction "1_1") (pintype "passive"))
      (node (ref "C347") (pin "1") (pinfunction "1_1") (pintype "passive"))
      (node (ref "C348") (pin "1") (pinfunction "1_1") (pintype "passive"))
      (node (ref "C349") (pin "1") (pinfunction "1_1") (pintype "passive"))
      (node (ref "C35") (pin "1") (pinfunction "1_1") (pintype "passive"))
      (node (ref "C350") (pin "1") (pinfunction "1_1") (pintype "passive"))
      (node (ref "C351") (pin "1") (pinfunction "1_1") (pintype "passive"))
      (node (ref "C352") (pin "1") (pinfunction "1_1") (pintype "passive"))
      (node (ref "C353") (pin "1") (pinfunction "1_1") (pintype "passive"))
      (node (ref "C354") (pin "1") (pinfunction "1_1") (pintype "passive"))
      (node (ref "C355") (pin "1") (pinfunction "1_1") (pintype "passive"))
      (node (ref "C356") (pin "1") (pinfunction "1_1") (pintype "passive"))
      (node (ref "C357") (pin "1") (pinfunction "1_1") (pintype "passive"))
      (node (ref "C358") (pin "1") (pinfunction "1_1") (pintype "passive"))
      (node (ref "C359") (pin "1") (pinfunction "1_1") (pintype "passive"))
      (node (ref "C36") (pin "1") (pinfunction "1_1") (pintype "passive"))
      (node (ref "C360") (pin "1") (pinfunction "1_1") (pintype "passive"))
      (node (ref "C361") (pin "1") (pinfunction "1_1") (pintype "passive"))
      (node (ref "C362") (pin "1") (pinfunction "1_1") (pintype "passive"))
      (node (ref "C363") (pin "1") (pinfunction "1_1") (pintype "passive"))
      (node (ref "C364") (pin "1") (pinfunction "1_1") (pintype "passive"))
      (node (ref "C365") (pin "1") (pinfunction "1_1") (pintype "passive"))
      (node (ref "C366") (pin "1") (pinfunction "1_1") (pintype "passive"))
      (node (ref "C367") (pin "1") (pinfunction "1_1") (pintype "passive"))
      (node (ref "C368") (pin "1") (pinfunction "1_1") (pintype "passive"))
      (node (ref "C369") (pin "1") (pinfunction "1_1") (pintype "passive"))
      (node (ref "C37") (pin "1") (pinfunction "1_1") (pintype "passive"))
      (node (ref "C370") (pin "1") (pinfunction "1_1") (pintype "passive"))
      (node (ref "C371") (pin "1") (pinfunction "1_1") (pintype "passive"))
      (node (ref "C372") (pin "1") (pinfunction "1_1") (pintype "passive"))
      (node (ref "C373") (pin "1") (pinfunction "1_1") (pintype "passive"))
      (node (ref "C374") (pin "1") (pinfunction "1_1") (pintype "passive"))
      (node (ref "C375") (pin "1") (pinfunction "1_1") (pintype "passive"))
      (node (ref "C376") (pin "1") (pinfunction "1_1") (pintype "passive"))
      (node (ref "C377") (pin "1") (pinfunction "1_1") (pintype "passive"))
      (node (ref "C378") (pin "1") (pinfunction "1_1") (pintype "passive"))
      (node (ref "C379") (pin "1") (pinfunction "1_1") (pintype "passive"))
      (node (ref "C38") (pin "1") (pinfunction "1_1") (pintype "passive"))
      (node (ref "C380") (pin "1") (pinfunction "1_1") (pintype "passive"))
      (node (ref "C381") (pin "1") (pinfunction "1_1") (pintype "passive"))
      (node (ref "C382") (pin "1") (pinfunction "1_1") (pintype "passive"))
      (node (ref "C383") (pin "1") (pinfunction "1_1") (pintype "passive"))
      (node (ref "C39") (pin "1") (pinfunction "1_1") (pintype "passive"))
      (node (ref "C4") (pin "2") (pinfunction "2_2") (pintype "passive"))
      (node (ref "C40") (pin "1") (pinfunction "1_1") (pintype "passive"))
      (node (ref "C41") (pin "1") (pinfunction "1_1") (pintype "passive"))
      (node (ref "C42") (pin "1") (pinfunction "1_1") (pintype "passive"))
      (node (ref "C43") (pin "1") (pinfunction "1_1") (pintype "passive"))
      (node (ref "C44") (pin "1") (pinfunction "1_1") (pintype "passive"))
      (node (ref "C45") (pin "1") (pinfunction "1_1") (pintype "passive"))
      (node (ref "C46") (pin "1") (pinfunction "1_1") (pintype "passive"))
      (node (ref "C47") (pin "1") (pinfunction "1_1") (pintype "passive"))
      (node (ref "C48") (pin "1") (pinfunction "1_1") (pintype "passive"))
      (node (ref "C49") (pin "1") (pinfunction "1_1") (pintype "passive"))
      (node (ref "C5") (pin "2") (pinfunction "2_2") (pintype "passive"))
      (node (ref "C50") (pin "1") (pinfunction "1_1") (pintype "passive"))
      (node (ref "C51") (pin "1") (pinfunction "1_1") (pintype "passive"))
      (node (ref "C52") (pin "1") (pinfunction "1_1") (pintype "passive"))
      (node (ref "C53") (pin "1") (pinfunction "1_1") (pintype "passive"))
      (node (ref "C54") (pin "1") (pinfunction "1_1") (pintype "passive"))
      (node (ref "C55") (pin "1") (pinfunction "1_1") (pintype "passive"))
      (node (ref "C56") (pin "1") (pinfunction "1_1") (pintype "passive"))
      (node (ref "C57") (pin "1") (pinfunction "1_1") (pintype "passive"))
      (node (ref "C58") (pin "1") (pinfunction "1_1") (pintype "passive"))
      (node (ref "C59") (pin "1") (pinfunction "1_1") (pintype "passive"))
      (node (ref "C6") (pin "2") (pinfunction "2_2") (pintype "passive"))
      (node (ref "C60") (pin "1") (pinfunction "1_1") (pintype "passive"))
      (node (ref "C61") (pin "1") (pinfunction "1_1") (pintype "passive"))
      (node (ref "C62") (pin "1") (pinfunction "1_1") (pintype "passive"))
      (node (ref "C63") (pin "1") (pinfunction "1_1") (pintype "passive"))
      (node (ref "C64") (pin "1") (pinfunction "1_1") (pintype "passive"))
      (node (ref "C65") (pin "1") (pinfunction "1_1") (pintype "passive"))
      (node (ref "C66") (pin "1") (pinfunction "1_1") (pintype "passive"))
      (node (ref "C67") (pin "1") (pinfunction "1_1") (pintype "passive"))
      (node (ref "C68") (pin "1") (pinfunction "1_1") (pintype "passive"))
      (node (ref "C69") (pin "2") (pinfunction "2_2") (pintype "passive"))
      (node (ref "C70") (pin "1") (pinfunction "1_1") (pintype "passive"))
      (node (ref "C71") (pin "1") (pinfunction "1_1") (pintype "passive"))
      (node (ref "C72") (pin "1") (pinfunction "1_1") (pintype "passive"))
      (node (ref "C73") (pin "1") (pinfunction "1_1") (pintype "passive"))
      (node (ref "C74") (pin "1") (pinfunction "1_1") (pintype "passive"))
      (node (ref "C75") (pin "1") (pinfunction "1_1") (pintype "passive"))
      (node (ref "C76") (pin "1") (pinfunction "1_1") (pintype "passive"))
      (node (ref "C77") (pin "1") (pinfunction "1_1") (pintype "passive"))
      (node (ref "C78") (pin "1") (pinfunction "1_1") (pintype "passive"))
      (node (ref "C79") (pin "1") (pinfunction "1_1") (pintype "passive"))
      (node (ref "C80") (pin "1") (pinfunction "1_1") (pintype "passive"))
      (node (ref "C81") (pin "1") (pinfunction "1_1") (pintype "passive"))
      (node (ref "C82") (pin "1") (pinfunction "1_1") (pintype "passive"))
      (node (ref "C83") (pin "1") (pinfunction "1_1") (pintype "passive"))
      (node (ref "C84") (pin "1") (pinfunction "1_1") (pintype "passive"))
      (node (ref "C85") (pin "1") (pinfunction "1_1") (pintype "passive"))
      (node (ref "C_1") (pin "2") (pinfunction "2_2") (pintype "passive"))
      (node (ref "C_10") (pin "2") (pinfunction "2_2") (pintype "passive"))
      (node (ref "C_11") (pin "2") (pinfunction "2_2") (pintype "passive"))
      (node (ref "C_12") (pin "2") (pinfunction "2_2") (pintype "passive"))
      (node (ref "C_13") (pin "2") (pinfunction "2_2") (pintype "passive"))
      (node (ref "C_14") (pin "2") (pinfunction "2_2") (pintype "passive"))
      (node (ref "C_15") (pin "2") (pinfunction "2_2") (pintype "passive"))
      (node (ref "C_16") (pin "2") (pinfunction "2_2") (pintype "passive"))
      (node (ref "C_17") (pin "2") (pinfunction "2_2") (pintype "passive"))
      (node (ref "C_18") (pin "2") (pinfunction "2_2") (pintype "passive"))
      (node (ref "C_19") (pin "2") (pinfunction "2_2") (pintype "passive"))
      (node (ref "C_2") (pin "2") (pinfunction "2_2") (pintype "passive"))
      (node (ref "C_20") (pin "2") (pinfunction "2_2") (pintype "passive"))
      (node (ref "C_21") (pin "2") (pinfunction "2_2") (pintype "passive"))
      (node (ref "C_22") (pin "2") (pinfunction "2_2") (pintype "passive"))
      (node (ref "C_23") (pin "2") (pinfunction "2_2") (pintype "passive"))
      (node (ref "C_24") (pin "2") (pinfunction "2_2") (pintype "passive"))
      (node (ref "C_25") (pin "2") (pinfunction "2_2") (pintype "passive"))
      (node (ref "C_26") (pin "2") (pinfunction "2_2") (pintype "passive"))
      (node (ref "C_27") (pin "2") (pinfunction "2_2") (pintype "passive"))
      (node (ref "C_28") (pin "2") (pinfunction "2_2") (pintype "passive"))
      (node (ref "C_29") (pin "2") (pinfunction "2_2") (pintype "passive"))
      (node (ref "C_3") (pin "2") (pinfunction "2_2") (pintype "passive"))
      (node (ref "C_30") (pin "2") (pinfunction "2_2") (pintype "passive"))
      (node (ref "C_31") (pin "2") (pinfunction "2_2") (pintype "passive"))
      (node (ref "C_32") (pin "2") (pinfunction "2_2") (pintype "passive"))
      (node (ref "C_33") (pin "2") (pinfunction "2_2") (pintype "passive"))
      (node (ref "C_34") (pin "2") (pinfunction "2_2") (pintype "passive"))
      (node (ref "C_35") (pin "2") (pinfunction "2_2") (pintype "passive"))
      (node (ref "C_36") (pin "2") (pinfunction "2_2") (pintype "passive"))
      (node (ref "C_37") (pin "2") (pinfunction "2_2") (pintype "passive"))
      (node (ref "C_38") (pin "2") (pinfunction "2_2") (pintype "passive"))
      (node (ref "C_39") (pin "2") (pinfunction "2_2") (pintype "passive"))
      (node (ref "C_4") (pin "2") (pinfunction "2_2") (pintype "passive"))
      (node (ref "C_40") (pin "2") (pinfunction "2_2") (pintype "passive"))
      (node (ref "C_41") (pin "2") (pinfunction "2_2") (pintype "passive"))
      (node (ref "C_42") (pin "2") (pinfunction "2_2") (pintype "passive"))
      (node (ref "C_43") (pin "2") (pinfunction "2_2") (pintype "passive"))
      (node (ref "C_44") (pin "2") (pinfunction "2_2") (pintype "passive"))
      (node (ref "C_45") (pin "2") (pinfunction "2_2") (pintype "passive"))
      (node (ref "C_46") (pin "2") (pinfunction "2_2") (pintype "passive"))
      (node (ref "C_47") (pin "2") (pinfunction "2_2") (pintype "passive"))
      (node (ref "C_48") (pin "2") (pinfunction "2_2") (pintype "passive"))
      (node (ref "C_49") (pin "2") (pinfunction "2_2") (pintype "passive"))
      (node (ref "C_5") (pin "2") (pinfunction "2_2") (pintype "passive"))
      (node (ref "C_50") (pin "2") (pinfunction "2_2") (pintype "passive"))
      (node (ref "C_51") (pin "2") (pinfunction "2_2") (pintype "passive"))
      (node (ref "C_52") (pin "2") (pinfunction "2_2") (pintype "passive"))
      (node (ref "C_53") (pin "2") (pinfunction "2_2") (pintype "passive"))
      (node (ref "C_54") (pin "2") (pinfunction "2_2") (pintype "passive"))
      (node (ref "C_55") (pin "2") (pinfunction "2_2") (pintype "passive"))
      (node (ref "C_56") (pin "2") (pinfunction "2_2") (pintype "passive"))
      (node (ref "C_57") (pin "2") (pinfunction "2_2") (pintype "passive"))
      (node (ref "C_58") (pin "2") (pinfunction "2_2") (pintype "passive"))
      (node (ref "C_59") (pin "2") (pinfunction "2_2") (pintype "passive"))
      (node (ref "C_6") (pin "2") (pinfunction "2_2") (pintype "passive"))
      (node (ref "C_60") (pin "2") (pinfunction "2_2") (pintype "passive"))
      (node (ref "C_61") (pin "2") (pinfunction "2_2") (pintype "passive"))
      (node (ref "C_62") (pin "2") (pinfunction "2_2") (pintype "passive"))
      (node (ref "C_63") (pin "2") (pinfunction "2_2") (pintype "passive"))
      (node (ref "C_64") (pin "2") (pinfunction "2_2") (pintype "passive"))
      (node (ref "C_65") (pin "2") (pinfunction "2_2") (pintype "passive"))
      (node (ref "C_66") (pin "2") (pinfunction "2_2") (pintype "passive"))
      (node (ref "C_67") (pin "2") (pinfunction "2_2") (pintype "passive"))
      (node (ref "C_68") (pin "2") (pinfunction "2_2") (pintype "passive"))
      (node (ref "C_69") (pin "2") (pinfunction "2_2") (pintype "passive"))
      (node (ref "C_7") (pin "2") (pinfunction "2_2") (pintype "passive"))
      (node (ref "C_70") (pin "2") (pinfunction "2_2") (pintype "passive"))
      (node (ref "C_71") (pin "2") (pinfunction "2_2") (pintype "passive"))
      (node (ref "C_72") (pin "2") (pinfunction "2_2") (pintype "passive"))
      (node (ref "C_8") (pin "2") (pinfunction "2_2") (pintype "passive"))
      (node (ref "C_9") (pin "2") (pinfunction "2_2") (pintype "passive"))
      (node (ref "D12") (pin "2") (pinfunction "A_2") (pintype "passive"))
      (node (ref "D4") (pin "1") (pinfunction "C_1") (pintype "passive"))
      (node (ref "D5") (pin "1") (pinfunction "C_1") (pintype "passive"))
      (node (ref "D6") (pin "1") (pinfunction "C_1") (pintype "passive"))
      (node (ref "D7") (pin "1") (pinfunction "C_1") (pintype "passive"))
      (node (ref "D9") (pin "2") (pinfunction "2_2") (pintype "passive"))
      (node (ref "D9") (pin "5") (pinfunction "5_5") (pintype "passive"))
      (node (ref "J1") (pin "3") (pinfunction "3_3") (pintype "passive"))
      (node (ref "J10") (pin "1") (pinfunction "1_1") (pintype "passive"))
      (node (ref "J11") (pin "1") (pinfunction "1_1") (pintype "passive"))
      (node (ref "J12") (pin "1") (pinfunction "1_1") (pintype "passive"))
      (node (ref "J13") (pin "1") (pinfunction "1_1") (pintype "passive"))
      (node (ref "J14") (pin "1") (pinfunction "1_1") (pintype "passive"))
      (node (ref "J15") (pin "1") (pinfunction "1_1") (pintype "passive"))
      (node (ref "J2") (pin "5") (pinfunction "5_5") (pintype "passive"))
      (node (ref "J2") (pin "6") (pinfunction "6_6") (pintype "passive"))
      (node (ref "J2") (pin "7") (pinfunction "7_7") (pintype "passive"))
      (node (ref "J2") (pin "8") (pinfunction "8_8") (pintype "passive"))
      (node (ref "J2") (pin "9") (pinfunction "9_9") (pintype "passive"))
      (node (ref "J3") (pin "2") (pinfunction "2_2") (pintype "passive"))
      (node (ref "J4") (pin "4") (pinfunction "4_4") (pintype "passive"))
      (node (ref "J4") (pin "5") (pinfunction "5_5") (pintype "passive"))
      (node (ref "J4") (pin "6") (pinfunction "6_6") (pintype "passive"))
      (node (ref "J5") (pin "1") (pinfunction "1_1") (pintype "passive"))
      (node (ref "J6") (pin "1") (pinfunction "1_1") (pintype "passive"))
      (node (ref "J7") (pin "1") (pinfunction "1_1") (pintype "passive"))
      (node (ref "J8") (pin "1") (pinfunction "1_1") (pintype "passive"))
      (node (ref "J9") (pin "1") (pinfunction "1_1") (pintype "passive"))
      (node (ref "Q4") (pin "1") (pinfunction "S_1") (pintype "passive"))
      (node (ref "Q4") (pin "2") (pinfunction "S_2") (pintype "passive"))
      (node (ref "Q4") (pin "3") (pinfunction "S_3") (pintype "passive"))
      (node (ref "Q5") (pin "1") (pinfunction "S_1") (pintype "passive"))
      (node (ref "Q5") (pin "2") (pinfunction "S_2") (pintype "passive"))
      (node (ref "Q5") (pin "3") (pinfunction "S_3") (pintype "passive"))
      (node (ref "Q6") (pin "1") (pinfunction "S_1") (pintype "passive"))
      (node (ref "Q6") (pin "2") (pinfunction "S_2") (pintype "passive"))
      (node (ref "Q6") (pin "3") (pinfunction "S_3") (pintype "passive"))
      (node (ref "Q7") (pin "1") (pinfunction "S_1") (pintype "passive"))
      (node (ref "Q7") (pin "2") (pinfunction "S_2") (pintype "passive"))
      (node (ref "Q7") (pin "3") (pinfunction "S_3") (pintype "passive"))
      (node (ref "Q8") (pin "1") (pinfunction "S_1") (pintype "passive"))
      (node (ref "Q8") (pin "2") (pinfunction "S_2") (pintype "passive"))
      (node (ref "Q8") (pin "3") (pinfunction "S_3") (pintype "passive"))
      (node (ref "Q9") (pin "1") (pinfunction "S_1") (pintype "passive"))
      (node (ref "Q9") (pin "2") (pinfunction "S_2") (pintype "passive"))
      (node (ref "Q9") (pin "3") (pinfunction "S_3") (pintype "passive"))
      (node (ref "R1") (pin "1") (pinfunction "1_1") (pintype "passive"))
      (node (ref "R17") (pin "2") (pinfunction "2_2") (pintype "passive"))
      (node (ref "R18") (pin "1") (pinfunction "1_1") (pintype "passive"))
      (node (ref "R19") (pin "1") (pinfunction "1_1") (pintype "passive"))
      (node (ref "R2") (pin "1") (pinfunction "1_1") (pintype "passive"))
      (node (ref "R20") (pin "1") (pinfunction "1_1") (pintype "passive"))
      (node (ref "R21") (pin "2") (pinfunction "2_2") (pintype "passive"))
      (node (ref "R22") (pin "2") (pinfunction "2_2") (pintype "passive"))
      (node (ref "R24") (pin "2") (pinfunction "2_2") (pintype "passive"))
      (node (ref "R25") (pin "1") (pinfunction "1_1") (pintype "passive"))
      (node (ref "R3") (pin "1") (pinfunction "1_1") (pintype "passive"))
      (node (ref "R30") (pin "2") (pinfunction "2_2") (pintype "passive"))
      (node (ref "R4") (pin "1") (pinfunction "1_1") (pintype "passive"))
      (node (ref "R43") (pin "1") (pinfunction "1_1") (pintype "passive"))
      (node (ref "R44") (pin "1") (pinfunction "1_1") (pintype "passive"))
      (node (ref "R45") (pin "1") (pinfunction "1_1") (pintype "passive"))
      (node (ref "R46") (pin "1") (pinfunction "1_1") (pintype "passive"))
      (node (ref "R51") (pin "2") (pinfunction "2_2") (pintype "passive"))
      (node (ref "R55") (pin "2") (pinfunction "2_2") (pintype "passive"))
      (node (ref "R64") (pin "1") (pinfunction "1_1") (pintype "passive"))
      (node (ref "R65") (pin "1") (pinfunction "1_1") (pintype "passive"))
      (node (ref "R66") (pin "1") (pinfunction "1_1") (pintype "passive"))
      (node (ref "R67") (pin "1") (pinfunction "1_1") (pintype "passive"))
      (node (ref "U1") (pin "4") (pinfunction "GND_4") (pintype "passive"))
      (node (ref "U1") (pin "9") (pinfunction "EP_9") (pintype "passive"))
      (node (ref "U10") (pin "10") (pinfunction "VSS_PLL_10") (pintype "passive"))
      (node (ref "U10") (pin "15") (pinfunction "DVSS_15") (pintype "passive"))
      (node (ref "U10") (pin "17") (pinfunction "CHIP_ID1_17") (pintype "passive"))
      (node (ref "U10") (pin "28") (pinfunction "DVSS_28") (pintype "passive"))
      (node (ref "U10") (pin "31") (pinfunction "OVSS1_31") (pintype "passive"))
      (node (ref "U10") (pin "33") (pinfunction "DVSS_33") (pintype "passive"))
      (node (ref "U10") (pin "36") (pinfunction "DVSS_36") (pintype "passive"))
      (node (ref "U10") (pin "40") (pinfunction "DVSS_40") (pintype "passive"))
      (node (ref "U10") (pin "44") (pinfunction "DVSS_44") (pintype "passive"))
      (node (ref "U10") (pin "50") (pinfunction "OVSS0_50") (pintype "passive"))
      (node (ref "U10") (pin "53") (pinfunction "DVSS_53") (pintype "passive"))
      (node (ref "U10") (pin "61") (pinfunction "DVSS_61") (pintype "passive"))
      (node (ref "U10") (pin "64") (pinfunction "DVSS_64") (pintype "passive"))
      (node (ref "U10") (pin "65") (pinfunction "DVSS_EP_65") (pintype "passive"))
      (node (ref "U10") (pin "7") (pinfunction "VSSA_PLL_7") (pintype "passive"))
      (node (ref "U11") (pin "10") (pinfunction "VSS_PLL_10") (pintype "passive"))
      (node (ref "U11") (pin "15") (pinfunction "DVSS_15") (pintype "passive"))
      (node (ref "U11") (pin "16") (pinfunction "CHIP_ID0_16") (pintype "passive"))
      (node (ref "U11") (pin "28") (pinfunction "DVSS_28") (pintype "passive"))
      (node (ref "U11") (pin "31") (pinfunction "OVSS1_31") (pintype "passive"))
      (node (ref "U11") (pin "33") (pinfunction "DVSS_33") (pintype "passive"))
      (node (ref "U11") (pin "36") (pinfunction "DVSS_36") (pintype "passive"))
      (node (ref "U11") (pin "40") (pinfunction "DVSS_40") (pintype "passive"))
      (node (ref "U11") (pin "44") (pinfunction "DVSS_44") (pintype "passive"))
      (node (ref "U11") (pin "50") (pinfunction "OVSS0_50") (pintype "passive"))
      (node (ref "U11") (pin "53") (pinfunction "DVSS_53") (pintype "passive"))
      (node (ref "U11") (pin "61") (pinfunction "DVSS_61") (pintype "passive"))
      (node (ref "U11") (pin "64") (pinfunction "DVSS_64") (pintype "passive"))
      (node (ref "U11") (pin "65") (pinfunction "DVSS_EP_65") (pintype "passive"))
      (node (ref "U11") (pin "7") (pinfunction "VSSA_PLL_7") (pintype "passive"))
      (node (ref "U12") (pin "10") (pinfunction "VSS_PLL_10") (pintype "passive"))
      (node (ref "U12") (pin "15") (pinfunction "DVSS_15") (pintype "passive"))
      (node (ref "U12") (pin "28") (pinfunction "DVSS_28") (pintype "passive"))
      (node (ref "U12") (pin "31") (pinfunction "OVSS1_31") (pintype "passive"))
      (node (ref "U12") (pin "33") (pinfunction "DVSS_33") (pintype "passive"))
      (node (ref "U12") (pin "36") (pinfunction "DVSS_36") (pintype "passive"))
      (node (ref "U12") (pin "40") (pinfunction "DVSS_40") (pintype "passive"))
      (node (ref "U12") (pin "44") (pinfunction "DVSS_44") (pintype "passive"))
      (node (ref "U12") (pin "50") (pinfunction "OVSS0_50") (pintype "passive"))
      (node (ref "U12") (pin "53") (pinfunction "DVSS_53") (pintype "passive"))
      (node (ref "U12") (pin "61") (pinfunction "DVSS_61") (pintype "passive"))
      (node (ref "U12") (pin "64") (pinfunction "DVSS_64") (pintype "passive"))
      (node (ref "U12") (pin "65") (pinfunction "DVSS_EP_65") (pintype "passive"))
      (node (ref "U12") (pin "7") (pinfunction "VSSA_PLL_7") (pintype "passive"))
      (node (ref "U13") (pin "2") (pinfunction "GND_2") (pintype "passive"))
      (node (ref "U13") (pin "3") (pinfunction "GND_3") (pintype "passive"))
      (node (ref "U13") (pin "6") (pinfunction "GND_6") (pintype "passive"))
      (node (ref "U13") (pin "7") (pinfunction "GND_7") (pintype "passive"))
      (node (ref "U14") (pin "2") (pinfunction "GND_2") (pintype "passive"))
      (node (ref "U15") (pin "6") (pinfunction "GND_6") (pintype "passive"))
      (node (ref "U15") (pin "7") (pinfunction "GND_7") (pintype "passive"))
      (node (ref "U16") (pin "4") (pinfunction "GND_4") (pintype "passive"))
      (node (ref "U17") (pin "4") (pinfunction "GND_4") (pintype "passive"))
      (node (ref "U18") (pin "10") (pinfunction "VSS_PLL_10") (pintype "passive"))
      (node (ref "U18") (pin "15") (pinfunction "DVSS_15") (pintype "passive"))
      (node (ref "U18") (pin "16") (pinfunction "CHIP_ID0_16") (pintype "passive"))
      (node (ref "U18") (pin "17") (pinfunction "CHIP_ID1_17") (pintype "passive"))
      (node (ref "U18") (pin "18") (pinfunction "CHIP_ID2_18") (pintype "passive"))
      (node (ref "U18") (pin "28") (pinfunction "DVSS_28") (pintype "passive"))
      (node (ref "U18") (pin "31") (pinfunction "OVSS1_31") (pintype "passive"))
      (node (ref "U18") (pin "33") (pinfunction "DVSS_33") (pintype "passive"))
      (node (ref "U18") (pin "36") (pinfunction "DVSS_36") (pintype "passive"))
      (node (ref "U18") (pin "40") (pinfunction "DVSS_40") (pintype "passive"))
      (node (ref "U18") (pin "44") (pinfunction "DVSS_44") (pintype "passive"))
      (node (ref "U18") (pin "50") (pinfunction "OVSS0_50") (pintype "passive"))
      (node (ref "U18") (pin "53") (pinfunction "DVSS_53") (pintype "passive"))
      (node (ref "U18") (pin "61") (pinfunction "DVSS_61") (pintype "passive"))
      (node (ref "U18") (pin "64") (pinfunction "DVSS_64") (pintype "passive"))
      (node (ref "U18") (pin "65") (pinfunction "DVSS_EP_65") (pintype "passive"))
      (node (ref "U18") (pin "7") (pinfunction "VSSA_PLL_7") (pintype "passive"))
      (node (ref "U19") (pin "10") (pinfunction "VSS_PLL_10") (pintype "passive"))
      (node (ref "U19") (pin "15") (pinfunction "DVSS_15") (pintype "passive"))
      (node (ref "U19") (pin "17") (pinfunction "CHIP_ID1_17") (pintype "passive"))
      (node (ref "U19") (pin "18") (pinfunction "CHIP_ID2_18") (pintype "passive"))
      (node (ref "U19") (pin "28") (pinfunction "DVSS_28") (pintype "passive"))
      (node (ref "U19") (pin "31") (pinfunction "OVSS1_31") (pintype "passive"))
      (node (ref "U19") (pin "33") (pinfunction "DVSS_33") (pintype "passive"))
      (node (ref "U19") (pin "36") (pinfunction "DVSS_36") (pintype "passive"))
      (node (ref "U19") (pin "40") (pinfunction "DVSS_40") (pintype "passive"))
      (node (ref "U19") (pin "44") (pinfunction "DVSS_44") (pintype "passive"))
      (node (ref "U19") (pin "50") (pinfunction "OVSS0_50") (pintype "passive"))
      (node (ref "U19") (pin "53") (pinfunction "DVSS_53") (pintype "passive"))
      (node (ref "U19") (pin "61") (pinfunction "DVSS_61") (pintype "passive"))
      (node (ref "U19") (pin "64") (pinfunction "DVSS_64") (pintype "passive"))
      (node (ref "U19") (pin "65") (pinfunction "DVSS_EP_65") (pintype "passive"))
      (node (ref "U19") (pin "7") (pinfunction "VSSA_PLL_7") (pintype "passive"))
      (node (ref "U2") (pin "4") (pinfunction "GND_4") (pintype "passive"))
      (node (ref "U2") (pin "9") (pinfunction "EP_9") (pintype "passive"))
      (node (ref "U20") (pin "10") (pinfunction "VSS_PLL_10") (pintype "passive"))
      (node (ref "U20") (pin "15") (pinfunction "DVSS_15") (pintype "passive"))
      (node (ref "U20") (pin "16") (pinfunction "CHIP_ID0_16") (pintype "passive"))
      (node (ref "U20") (pin "18") (pinfunction "CHIP_ID2_18") (pintype "passive"))
      (node (ref "U20") (pin "28") (pinfunction "DVSS_28") (pintype "passive"))
      (node (ref "U20") (pin "31") (pinfunction "OVSS1_31") (pintype "passive"))
      (node (ref "U20") (pin "33") (pinfunction "DVSS_33") (pintype "passive"))
      (node (ref "U20") (pin "36") (pinfunction "DVSS_36") (pintype "passive"))
      (node (ref "U20") (pin "40") (pinfunction "DVSS_40") (pintype "passive"))
      (node (ref "U20") (pin "44") (pinfunction "DVSS_44") (pintype "passive"))
      (node (ref "U20") (pin "50") (pinfunction "OVSS0_50") (pintype "passive"))
      (node (ref "U20") (pin "53") (pinfunction "DVSS_53") (pintype "passive"))
      (node (ref "U20") (pin "61") (pinfunction "DVSS_61") (pintype "passive"))
      (node (ref "U20") (pin "64") (pinfunction "DVSS_64") (pintype "passive"))
      (node (ref "U20") (pin "65") (pinfunction "DVSS_EP_65") (pintype "passive"))
      (node (ref "U20") (pin "7") (pinfunction "VSSA_PLL_7") (pintype "passive"))
      (node (ref "U21") (pin "10") (pinfunction "VSS_PLL_10") (pintype "passive"))
      (node (ref "U21") (pin "15") (pinfunction "DVSS_15") (pintype "passive"))
      (node (ref "U21") (pin "16") (pinfunction "CHIP_ID0_16") (pintype "passive"))
      (node (ref "U21") (pin "28") (pinfunction "DVSS_28") (pintype "passive"))
      (node (ref "U21") (pin "31") (pinfunction "OVSS1_31") (pintype "passive"))
      (node (ref "U21") (pin "33") (pinfunction "DVSS_33") (pintype "passive"))
      (node (ref "U21") (pin "36") (pinfunction "DVSS_36") (pintype "passive"))
      (node (ref "U21") (pin "40") (pinfunction "DVSS_40") (pintype "passive"))
      (node (ref "U21") (pin "44") (pinfunction "DVSS_44") (pintype "passive"))
      (node (ref "U21") (pin "50") (pinfunction "OVSS0_50") (pintype "passive"))
      (node (ref "U21") (pin "53") (pinfunction "DVSS_53") (pintype "passive"))
      (node (ref "U21") (pin "61") (pinfunction "DVSS_61") (pintype "passive"))
      (node (ref "U21") (pin "64") (pinfunction "DVSS_64") (pintype "passive"))
      (node (ref "U21") (pin "65") (pinfunction "DVSS_EP_65") (pintype "passive"))
      (node (ref "U21") (pin "7") (pinfunction "VSSA_PLL_7") (pintype "passive"))
      (node (ref "U22") (pin "6") (pinfunction "GND_6") (pintype "passive"))
      (node (ref "U22") (pin "7") (pinfunction "GND_7") (pintype "passive"))
      (node (ref "U23") (pin "6") (pinfunction "GND_6") (pintype "passive"))
      (node (ref "U23") (pin "7") (pinfunction "GND_7") (pintype "passive"))
      (node (ref "U24") (pin "10") (pinfunction "VSS_PLL_10") (pintype "passive"))
      (node (ref "U24") (pin "15") (pinfunction "DVSS_15") (pintype "passive"))
      (node (ref "U24") (pin "16") (pinfunction "CHIP_ID0_16") (pintype "passive"))
      (node (ref "U24") (pin "17") (pinfunction "CHIP_ID1_17") (pintype "passive"))
      (node (ref "U24") (pin "28") (pinfunction "DVSS_28") (pintype "passive"))
      (node (ref "U24") (pin "31") (pinfunction "OVSS1_31") (pintype "passive"))
      (node (ref "U24") (pin "33") (pinfunction "DVSS_33") (pintype "passive"))
      (node (ref "U24") (pin "36") (pinfunction "DVSS_36") (pintype "passive"))
      (node (ref "U24") (pin "40") (pinfunction "DVSS_40") (pintype "passive"))
      (node (ref "U24") (pin "44") (pinfunction "DVSS_44") (pintype "passive"))
      (node (ref "U24") (pin "50") (pinfunction "OVSS0_50") (pintype "passive"))
      (node (ref "U24") (pin "53") (pinfunction "DVSS_53") (pintype "passive"))
      (node (ref "U24") (pin "61") (pinfunction "DVSS_61") (pintype "passive"))
      (node (ref "U24") (pin "64") (pinfunction "DVSS_64") (pintype "passive"))
      (node (ref "U24") (pin "65") (pinfunction "DVSS_EP_65") (pintype "passive"))
      (node (ref "U24") (pin "7") (pinfunction "VSSA_PLL_7") (pintype "passive"))
      (node (ref "U25") (pin "10") (pinfunction "VSS_PLL_10") (pintype "passive"))
      (node (ref "U25") (pin "15") (pinfunction "DVSS_15") (pintype "passive"))
      (node (ref "U25") (pin "17") (pinfunction "CHIP_ID1_17") (pintype "passive"))
      (node (ref "U25") (pin "28") (pinfunction "DVSS_28") (pintype "passive"))
      (node (ref "U25") (pin "31") (pinfunction "OVSS1_31") (pintype "passive"))
      (node (ref "U25") (pin "33") (pinfunction "DVSS_33") (pintype "passive"))
      (node (ref "U25") (pin "36") (pinfunction "DVSS_36") (pintype "passive"))
      (node (ref "U25") (pin "40") (pinfunction "DVSS_40") (pintype "passive"))
      (node (ref "U25") (pin "44") (pinfunction "DVSS_44") (pintype "passive"))
      (node (ref "U25") (pin "50") (pinfunction "OVSS0_50") (pintype "passive"))
      (node (ref "U25") (pin "53") (pinfunction "DVSS_53") (pintype "passive"))
      (node (ref "U25") (pin "61") (pinfunction "DVSS_61") (pintype "passive"))
      (node (ref "U25") (pin "64") (pinfunction "DVSS_64") (pintype "passive"))
      (node (ref "U25") (pin "65") (pinfunction "DVSS_EP_65") (pintype "passive"))
      (node (ref "U25") (pin "7") (pinfunction "VSSA_PLL_7") (pintype "passive"))
      (node (ref "U26") (pin "10") (pinfunction "VSS_PLL_10") (pintype "passive"))
      (node (ref "U26") (pin "15") (pinfunction "DVSS_15") (pintype "passive"))
      (node (ref "U26") (pin "16") (pinfunction "CHIP_ID0_16") (pintype "passive"))
      (node (ref "U26") (pin "28") (pinfunction "DVSS_28") (pintype "passive"))
      (node (ref "U26") (pin "31") (pinfunction "OVSS1_31") (pintype "passive"))
      (node (ref "U26") (pin "33") (pinfunction "DVSS_33") (pintype "passive"))
      (node (ref "U26") (pin "36") (pinfunction "DVSS_36") (pintype "passive"))
      (node (ref "U26") (pin "40") (pinfunction "DVSS_40") (pintype "passive"))
      (node (ref "U26") (pin "44") (pinfunction "DVSS_44") (pintype "passive"))
      (node (ref "U26") (pin "50") (pinfunction "OVSS0_50") (pintype "passive"))
      (node (ref "U26") (pin "53") (pinfunction "DVSS_53") (pintype "passive"))
      (node (ref "U26") (pin "61") (pinfunction "DVSS_61") (pintype "passive"))
      (node (ref "U26") (pin "64") (pinfunction "DVSS_64") (pintype "passive"))
      (node (ref "U26") (pin "65") (pinfunction "DVSS_EP_65") (pintype "passive"))
      (node (ref "U26") (pin "7") (pinfunction "VSSA_PLL_7") (pintype "passive"))
      (node (ref "U27") (pin "10") (pinfunction "VSS_PLL_10") (pintype "passive"))
      (node (ref "U27") (pin "15") (pinfunction "DVSS_15") (pintype "passive"))
      (node (ref "U27") (pin "28") (pinfunction "DVSS_28") (pintype "passive"))
      (node (ref "U27") (pin "31") (pinfunction "OVSS1_31") (pintype "passive"))
      (node (ref "U27") (pin "33") (pinfunction "DVSS_33") (pintype "passive"))
      (node (ref "U27") (pin "36") (pinfunction "DVSS_36") (pintype "passive"))
      (node (ref "U27") (pin "40") (pinfunction "DVSS_40") (pintype "passive"))
      (node (ref "U27") (pin "44") (pinfunction "DVSS_44") (pintype "passive"))
      (node (ref "U27") (pin "50") (pinfunction "OVSS0_50") (pintype "passive"))
      (node (ref "U27") (pin "53") (pinfunction "DVSS_53") (pintype "passive"))
      (node (ref "U27") (pin "61") (pinfunction "DVSS_61") (pintype "passive"))
      (node (ref "U27") (pin "64") (pinfunction "DVSS_64") (pintype "passive"))
      (node (ref "U27") (pin "65") (pinfunction "DVSS_EP_65") (pintype "passive"))
      (node (ref "U27") (pin "7") (pinfunction "VSSA_PLL_7") (pintype "passive"))
      (node (ref "U3") (pin "4") (pinfunction "GND_4") (pintype "passive"))
      (node (ref "U3") (pin "9") (pinfunction "EP_9") (pintype "passive"))
      (node (ref "U4") (pin "10") (pinfunction "VSS_PLL_10") (pintype "passive"))
      (node (ref "U4") (pin "15") (pinfunction "DVSS_15") (pintype "passive"))
      (node (ref "U4") (pin "16") (pinfunction "CHIP_ID0_16") (pintype "passive"))
      (node (ref "U4") (pin "17") (pinfunction "CHIP_ID1_17") (pintype "passive"))
      (node (ref "U4") (pin "18") (pinfunction "CHIP_ID2_18") (pintype "passive"))
      (node (ref "U4") (pin "28") (pinfunction "DVSS_28") (pintype "passive"))
      (node (ref "U4") (pin "31") (pinfunction "OVSS1_31") (pintype "passive"))
      (node (ref "U4") (pin "33") (pinfunction "DVSS_33") (pintype "passive"))
      (node (ref "U4") (pin "36") (pinfunction "DVSS_36") (pintype "passive"))
      (node (ref "U4") (pin "40") (pinfunction "DVSS_40") (pintype "passive"))
      (node (ref "U4") (pin "44") (pinfunction "DVSS_44") (pintype "passive"))
      (node (ref "U4") (pin "50") (pinfunction "OVSS0_50") (pintype "passive"))
      (node (ref "U4") (pin "53") (pinfunction "DVSS_53") (pintype "passive"))
      (node (ref "U4") (pin "61") (pinfunction "DVSS_61") (pintype "passive"))
      (node (ref "U4") (pin "64") (pinfunction "DVSS_64") (pintype "passive"))
      (node (ref "U4") (pin "65") (pinfunction "DVSS_EP_65") (pintype "passive"))
      (node (ref "U4") (pin "7") (pinfunction "VSSA_PLL_7") (pintype "passive"))
      (node (ref "U5") (pin "10") (pinfunction "VSS_PLL_10") (pintype "passive"))
      (node (ref "U5") (pin "15") (pinfunction "DVSS_15") (pintype "passive"))
      (node (ref "U5") (pin "17") (pinfunction "CHIP_ID1_17") (pintype "passive"))
      (node (ref "U5") (pin "18") (pinfunction "CHIP_ID2_18") (pintype "passive"))
      (node (ref "U5") (pin "28") (pinfunction "DVSS_28") (pintype "passive"))
      (node (ref "U5") (pin "31") (pinfunction "OVSS1_31") (pintype "passive"))
      (node (ref "U5") (pin "33") (pinfunction "DVSS_33") (pintype "passive"))
      (node (ref "U5") (pin "36") (pinfunction "DVSS_36") (pintype "passive"))
      (node (ref "U5") (pin "40") (pinfunction "DVSS_40") (pintype "passive"))
      (node (ref "U5") (pin "44") (pinfunction "DVSS_44") (pintype "passive"))
      (node (ref "U5") (pin "50") (pinfunction "OVSS0_50") (pintype "passive"))
      (node (ref "U5") (pin "53") (pinfunction "DVSS_53") (pintype "passive"))
      (node (ref "U5") (pin "61") (pinfunction "DVSS_61") (pintype "passive"))
      (node (ref "U5") (pin "64") (pinfunction "DVSS_64") (pintype "passive"))
      (node (ref "U5") (pin "65") (pinfunction "DVSS_EP_65") (pintype "passive"))
      (node (ref "U5") (pin "7") (pinfunction "VSSA_PLL_7") (pintype "passive"))
      (node (ref "U6") (pin "10") (pinfunction "VSS_PLL_10") (pintype "passive"))
      (node (ref "U6") (pin "15") (pinfunction "DVSS_15") (pintype "passive"))
      (node (ref "U6") (pin "16") (pinfunction "CHIP_ID0_16") (pintype "passive"))
      (node (ref "U6") (pin "18") (pinfunction "CHIP_ID2_18") (pintype "passive"))
      (node (ref "U6") (pin "28") (pinfunction "DVSS_28") (pintype "passive"))
      (node (ref "U6") (pin "31") (pinfunction "OVSS1_31") (pintype "passive"))
      (node (ref "U6") (pin "33") (pinfunction "DVSS_33") (pintype "passive"))
      (node (ref "U6") (pin "36") (pinfunction "DVSS_36") (pintype "passive"))
      (node (ref "U6") (pin "40") (pinfunction "DVSS_40") (pintype "passive"))
      (node (ref "U6") (pin "44") (pinfunction "DVSS_44") (pintype "passive"))
      (node (ref "U6") (pin "50") (pinfunction "OVSS0_50") (pintype "passive"))
      (node (ref "U6") (pin "53") (pinfunction "DVSS_53") (pintype "passive"))
      (node (ref "U6") (pin "61") (pinfunction "DVSS_61") (pintype "passive"))
      (node (ref "U6") (pin "64") (pinfunction "DVSS_64") (pintype "passive"))
      (node (ref "U6") (pin "65") (pinfunction "DVSS_EP_65") (pintype "passive"))
      (node (ref "U6") (pin "7") (pinfunction "VSSA_PLL_7") (pintype "passive"))
      (node (ref "U7") (pin "10") (pinfunction "VSS_PLL_10") (pintype "passive"))
      (node (ref "U7") (pin "15") (pinfunction "DVSS_15") (pintype "passive"))
      (node (ref "U7") (pin "18") (pinfunction "CHIP_ID2_18") (pintype "passive"))
      (node (ref "U7") (pin "28") (pinfunction "DVSS_28") (pintype "passive"))
      (node (ref "U7") (pin "31") (pinfunction "OVSS1_31") (pintype "passive"))
      (node (ref "U7") (pin "33") (pinfunction "DVSS_33") (pintype "passive"))
      (node (ref "U7") (pin "36") (pinfunction "DVSS_36") (pintype "passive"))
      (node (ref "U7") (pin "40") (pinfunction "DVSS_40") (pintype "passive"))
      (node (ref "U7") (pin "44") (pinfunction "DVSS_44") (pintype "passive"))
      (node (ref "U7") (pin "50") (pinfunction "OVSS0_50") (pintype "passive"))
      (node (ref "U7") (pin "53") (pinfunction "DVSS_53") (pintype "passive"))
      (node (ref "U7") (pin "61") (pinfunction "DVSS_61") (pintype "passive"))
      (node (ref "U7") (pin "64") (pinfunction "DVSS_64") (pintype "passive"))
      (node (ref "U7") (pin "65") (pinfunction "DVSS_EP_65") (pintype "passive"))
      (node (ref "U7") (pin "7") (pinfunction "VSSA_PLL_7") (pintype "passive"))
      (node (ref "U8") (pin "20") (pinfunction "AVSS_20") (pintype "passive"))
      (node (ref "U8") (pin "25") (pinfunction "VSS_25") (pintype "passive"))
      (node (ref "U8") (pin "41") (pinfunction "VSS_41") (pintype "passive"))
      (node (ref "U8") (pin "9") (pinfunction "VSS_9") (pintype "passive"))
      (node (ref "U9") (pin "10") (pinfunction "VSS_PLL_10") (pintype "passive"))
      (node (ref "U9") (pin "15") (pinfunction "DVSS_15") (pintype "passive"))
      (node (ref "U9") (pin "16") (pinfunction "CHIP_ID0_16") (pintype "passive"))
      (node (ref "U9") (pin "17") (pinfunction "CHIP_ID1_17") (pintype "passive"))
      (node (ref "U9") (pin "28") (pinfunction "DVSS_28") (pintype "passive"))
      (node (ref "U9") (pin "31") (pinfunction "OVSS1_31") (pintype "passive"))
      (node (ref "U9") (pin "33") (pinfunction "DVSS_33") (pintype "passive"))
      (node (ref "U9") (pin "36") (pinfunction "DVSS_36") (pintype "passive"))
      (node (ref "U9") (pin "40") (pinfunction "DVSS_40") (pintype "passive"))
      (node (ref "U9") (pin "44") (pinfunction "DVSS_44") (pintype "passive"))
      (node (ref "U9") (pin "50") (pinfunction "OVSS0_50") (pintype "passive"))
      (node (ref "U9") (pin "53") (pinfunction "DVSS_53") (pintype "passive"))
      (node (ref "U9") (pin "61") (pinfunction "DVSS_61") (pintype "passive"))
      (node (ref "U9") (pin "64") (pinfunction "DVSS_64") (pintype "passive"))
      (node (ref "U9") (pin "65") (pinfunction "DVSS_EP_65") (pintype "passive"))
      (node (ref "U9") (pin "7") (pinfunction "VSSA_PLL_7") (pintype "passive"))
    )
    (net (code "119") (name "Net-(U8-AN2{slash}C2IN2-{slash}VMIO{slash}RPI34{slash}RB2)") (class "Default")
      (node (ref "TP17") (pin "1") (pinfunction "1_1") (pintype "passive"))
      (node (ref "U8") (pin "14") (pinfunction "AN2/C2IN2-/VMIO/RPI34/RB2_14") (pintype "passive"))
    )
    (net (code "120") (name "Net-(U8-AN3{slash}C2IN1+{slash}VPIO{slash}RPI35{slash}RB3)") (class "Default")
      (node (ref "TP12") (pin "1") (pinfunction "1_1") (pintype "passive"))
      (node (ref "U8") (pin "13") (pinfunction "AN3/C2IN1+/VPIO/RPI35/RB3_13") (pintype "passive"))
    )
    (net (code "121") (name "Net-(U8-AN4{slash}C1IN2-{slash}USBOEN{slash}RPI36{slash}RB4)") (class "Default")
      (node (ref "TP54") (pin "1") (pinfunction "1_1") (pintype "passive"))
      (node (ref "U8") (pin "12") (pinfunction "AN4/C1IN2-/USBOEN/RPI36/RB4_12") (pintype "passive"))
    )
    (net (code "122") (name "Net-(U8-AN5{slash}C1IN1+{slash}VBUSON{slash}VBUSST{slash}RPI37{slash}RB5)") (class "Default")
      (node (ref "TP53") (pin "1") (pinfunction "1_1") (pintype "passive"))
      (node (ref "U8") (pin "11") (pinfunction "AN5/C1IN1+/VBUSON/VBUSST/RPI37/RB5_11") (pintype "passive"))
    )
    (net (code "123") (name "Net-(U8-AN8{slash}PMA6{slash}RPI40{slash}RB8)") (class "Default")
      (node (ref "TP20") (pin "1") (pinfunction "1_1") (pintype "passive"))
      (node (ref "U8") (pin "21") (pinfunction "AN8/PMA6/RPI40/RB8_21") (pintype "passive"))
    )
    (net (code "124") (name "Net-(U8-AN9{slash}PMA7{slash}{slash}RPI41{slash}RB9)") (class "Default")
      (node (ref "TP21") (pin "1") (pinfunction "1_1") (pintype "passive"))
      (node (ref "U8") (pin "22") (pinfunction "AN9/PMA7//RPI41/RB9_22") (pintype "passive"))
    )
    (net (code "125") (name "Net-(U8-AN14{slash}PMA1{slash}RPI46{slash}RB14)") (class "Default")
      (node (ref "TP27") (pin "1") (pinfunction "1_1") (pintype "passive"))
      (node (ref "U8") (pin "29") (pinfunction "AN14/PMA1/RPI46/RB14_29") (pintype "passive"))
    )
    (net (code "126") (name "Net-(U8-AN15{slash}PMA0{slash}RPI47{slash}RB15)") (class "Default")
      (node (ref "TP28") (pin "1") (pinfunction "1_1") (pintype "passive"))
      (node (ref "U8") (pin "30") (pinfunction "AN15/PMA0/RPI47/RB15_30") (pintype "passive"))
    )
    (net (code "127") (name "Net-(U8-ASDA1{slash}DPLN{slash}RPI73{slash}RD9)") (class "Default")
      (node (ref "TP22") (pin "1") (pinfunction "1_1") (pintype "passive"))
      (node (ref "U8") (pin "43") (pinfunction "ASDA1/DPLN/RPI73/RD9_43") (pintype "passive"))
    )
    (net (code "128") (name "Net-(U8-C2IN1-{slash}PMA2{slash}RPI121{slash}RG9)") (class "Default")
      (node (ref "TP10") (pin "1") (pinfunction "1_1") (pintype "passive"))
      (node (ref "U8") (pin "8") (pinfunction "C2IN1-/PMA2/RPI121/RG9_8") (pintype "passive"))
    )
    (net (code "129") (name "Net-(U8-C2IN3-{slash}SDO2{slash}PMA3{slash}RP120{slash}RG8)") (class "Default")
      (node (ref "TP9") (pin "1") (pinfunction "1_1") (pintype "passive"))
      (node (ref "U8") (pin "6") (pinfunction "C2IN3-/SDO2/PMA3/RP120/RG8_6") (pintype "passive"))
    )
    (net (code "130") (name "Net-(U8-C3IN2-{slash}RP70{slash}RD6)") (class "Default")
      (node (ref "TP11") (pin "1") (pinfunction "1_1") (pintype "passive"))
      (node (ref "U8") (pin "54") (pinfunction "C3IN2-/RP70/RD6_54") (pintype "passive"))
    )
    (net (code "131") (name "Net-(U8-DPH{slash}RP66{slash}RD2)") (class "Default")
      (node (ref "TP19") (pin "1") (pinfunction "1_1") (pintype "passive"))
      (node (ref "U8") (pin "50") (pinfunction "DPH/RP66/RD2_50") (pintype "passive"))
    )
    (net (code "132") (name "Net-(U8-PMBE{slash}RP67{slash}RD3)") (class "Default")
      (node (ref "TP18") (pin "1") (pinfunction "1_1") (pintype "passive"))
      (node (ref "U8") (pin "51") (pinfunction "PMBE/RP67/RD3_51") (pintype "passive"))
    )
    (net (code "133") (name "Net-(U8-RTCC{slash}DMLN{slash}RPI72{slash}RD8)") (class "Default")
      (node (ref "TP23") (pin "1") (pinfunction "1_1") (pintype "passive"))
      (node (ref "U8") (pin "42") (pinfunction "RTCC/DMLN/RPI72/RD8_42") (pintype "passive"))
    )
    (net (code "134") (name "Net-(U8-SCL2{slash}PMA8{slash}RP101{slash}RF5)") (class "Default")
      (node (ref "TP30") (pin "1") (pinfunction "1_1") (pintype "passive"))
      (node (ref "U8") (pin "32") (pinfunction "SCL2/PMA8/RP101/RF5_32") (pintype "passive"))
    )
    (net (code "135") (name "Net-(U8-SDA2{slash}PMA9{slash}RP100{slash}RF4)") (class "Default")
      (node (ref "TP29") (pin "1") (pinfunction "1_1") (pintype "passive"))
      (node (ref "U8") (pin "31") (pinfunction "SDA2/PMA9/RP100/RF4_31") (pintype "passive"))
    )
    (net (code "136") (name "Net-(U8-TCK{slash}AN12{slash}PMA11{slash}RPI44{slash}RB12)") (class "Default")
      (node (ref "TP25") (pin "1") (pinfunction "1_1") (pintype "passive"))
      (node (ref "U8") (pin "27") (pinfunction "TCK/AN12/PMA11/RPI44/RB12_27") (pintype "passive"))
    )
    (net (code "137") (name "Net-(U8-TDI{slash}AN13{slash}PMA10{slash}RPI45{slash}RB13)") (class "Default")
      (node (ref "TP26") (pin "1") (pinfunction "1_1") (pintype "passive"))
      (node (ref "U8") (pin "28") (pinfunction "TDI/AN13/PMA10/RPI45/RB13_28") (pintype "passive"))
    )
    (net (code "138") (name "Net-(U8-TDO{slash}AN11{slash}PMA12{slash}RPI43{slash}RB11)") (class "Default")
      (node (ref "TP24") (pin "1") (pinfunction "1_1") (pintype "passive"))
      (node (ref "U8") (pin "24") (pinfunction "TDO/AN11/PMA12/RPI43/RB11_24") (pintype "passive"))
    )
    (net (code "139") (name "Net-(U8-USBID{slash}RP99{slash}RF3)") (class "Default")
      (node (ref "TP31") (pin "1") (pinfunction "1_1") (pintype "passive"))
      (node (ref "U8") (pin "33") (pinfunction "USBID/RP99/RF3_33") (pintype "passive"))
    )
    (net (code "140") (name "Net-(U22-ADJ)") (class "Default")
      (node (ref "R50") (pin "2") (pinfunction "2_2") (pintype "passive"))
      (node (ref "R51") (pin "1") (pinfunction "1_1") (pintype "passive"))
      (node (ref "U22") (pin "2") (pinfunction "ADJ_2") (pintype "passive"))
    )
    (net (code "141") (name "Net-(U23-ADJ)") (class "Default")
      (node (ref "R52") (pin "2") (pinfunction "2_2") (pintype "passive"))
      (node (ref "R55") (pin "1") (pinfunction "1_1") (pintype "passive"))
      (node (ref "U23") (pin "2") (pinfunction "ADJ_2") (pintype "passive"))
    )
    (net (code "142") (name "unconnected-(J2-Pad4)") (class "Default")
      (node (ref "J2") (pin "4") (pinfunction "4_4") (pintype "passive"))
    )
    (net (code "143") (name "unconnected-(U13-N.C.-Pad4)") (class "Default")
      (node (ref "U13") (pin "4") (pinfunction "N.C._4") (pintype "passive+no_connect"))
    )
    (net (code "144") (name "unconnected-(U13-N.C.-Pad5)") (class "Default")
      (node (ref "U13") (pin "5") (pinfunction "N.C._5") (pintype "passive+no_connect"))
    )
    (net (code "145") (name "unconnected-(U14-N.C.-Pad4)") (class "Default")
      (node (ref "U14") (pin "4") (pinfunction "N.C._4") (pintype "passive+no_connect"))
    )
    (net (code "146") (name "unconnected-(U15-NC-Pad2)") (class "Default")
      (node (ref "U15") (pin "2") (pinfunction "NC_2") (pintype "passive+no_connect"))
    )
    (net (code "147") (name "unconnected-(U15-NC-Pad3)") (class "Default")
      (node (ref "U15") (pin "3") (pinfunction "NC_3") (pintype "passive+no_connect"))
    )
    (net (code "148") (name "unconnected-(U15-NC-Pad4)") (class "Default")
      (node (ref "U15") (pin "4") (pinfunction "NC_4") (pintype "passive+no_connect"))
    )
    (net (code "149") (name "unconnected-(U22-NC-Pad3)") (class "Default")
      (node (ref "U22") (pin "3") (pinfunction "NC_3") (pintype "passive+no_connect"))
    )
    (net (code "150") (name "unconnected-(U22-NC-Pad4)") (class "Default")
      (node (ref "U22") (pin "4") (pinfunction "NC_4") (pintype "passive+no_connect"))
    )
    (net (code "151") (name "unconnected-(U23-NC-Pad3)") (class "Default")
      (node (ref "U23") (pin "3") (pinfunction "NC_3") (pintype "passive+no_connect"))
    )
    (net (code "152") (name "unconnected-(U23-NC-Pad4)") (class "Default")
      (node (ref "U23") (pin "4") (pinfunction "NC_4") (pintype "passive+no_connect"))
    )
  )
)
